# digital_PIN_interface.net
KiCad netlist of a schematic drawn in Altium Designer
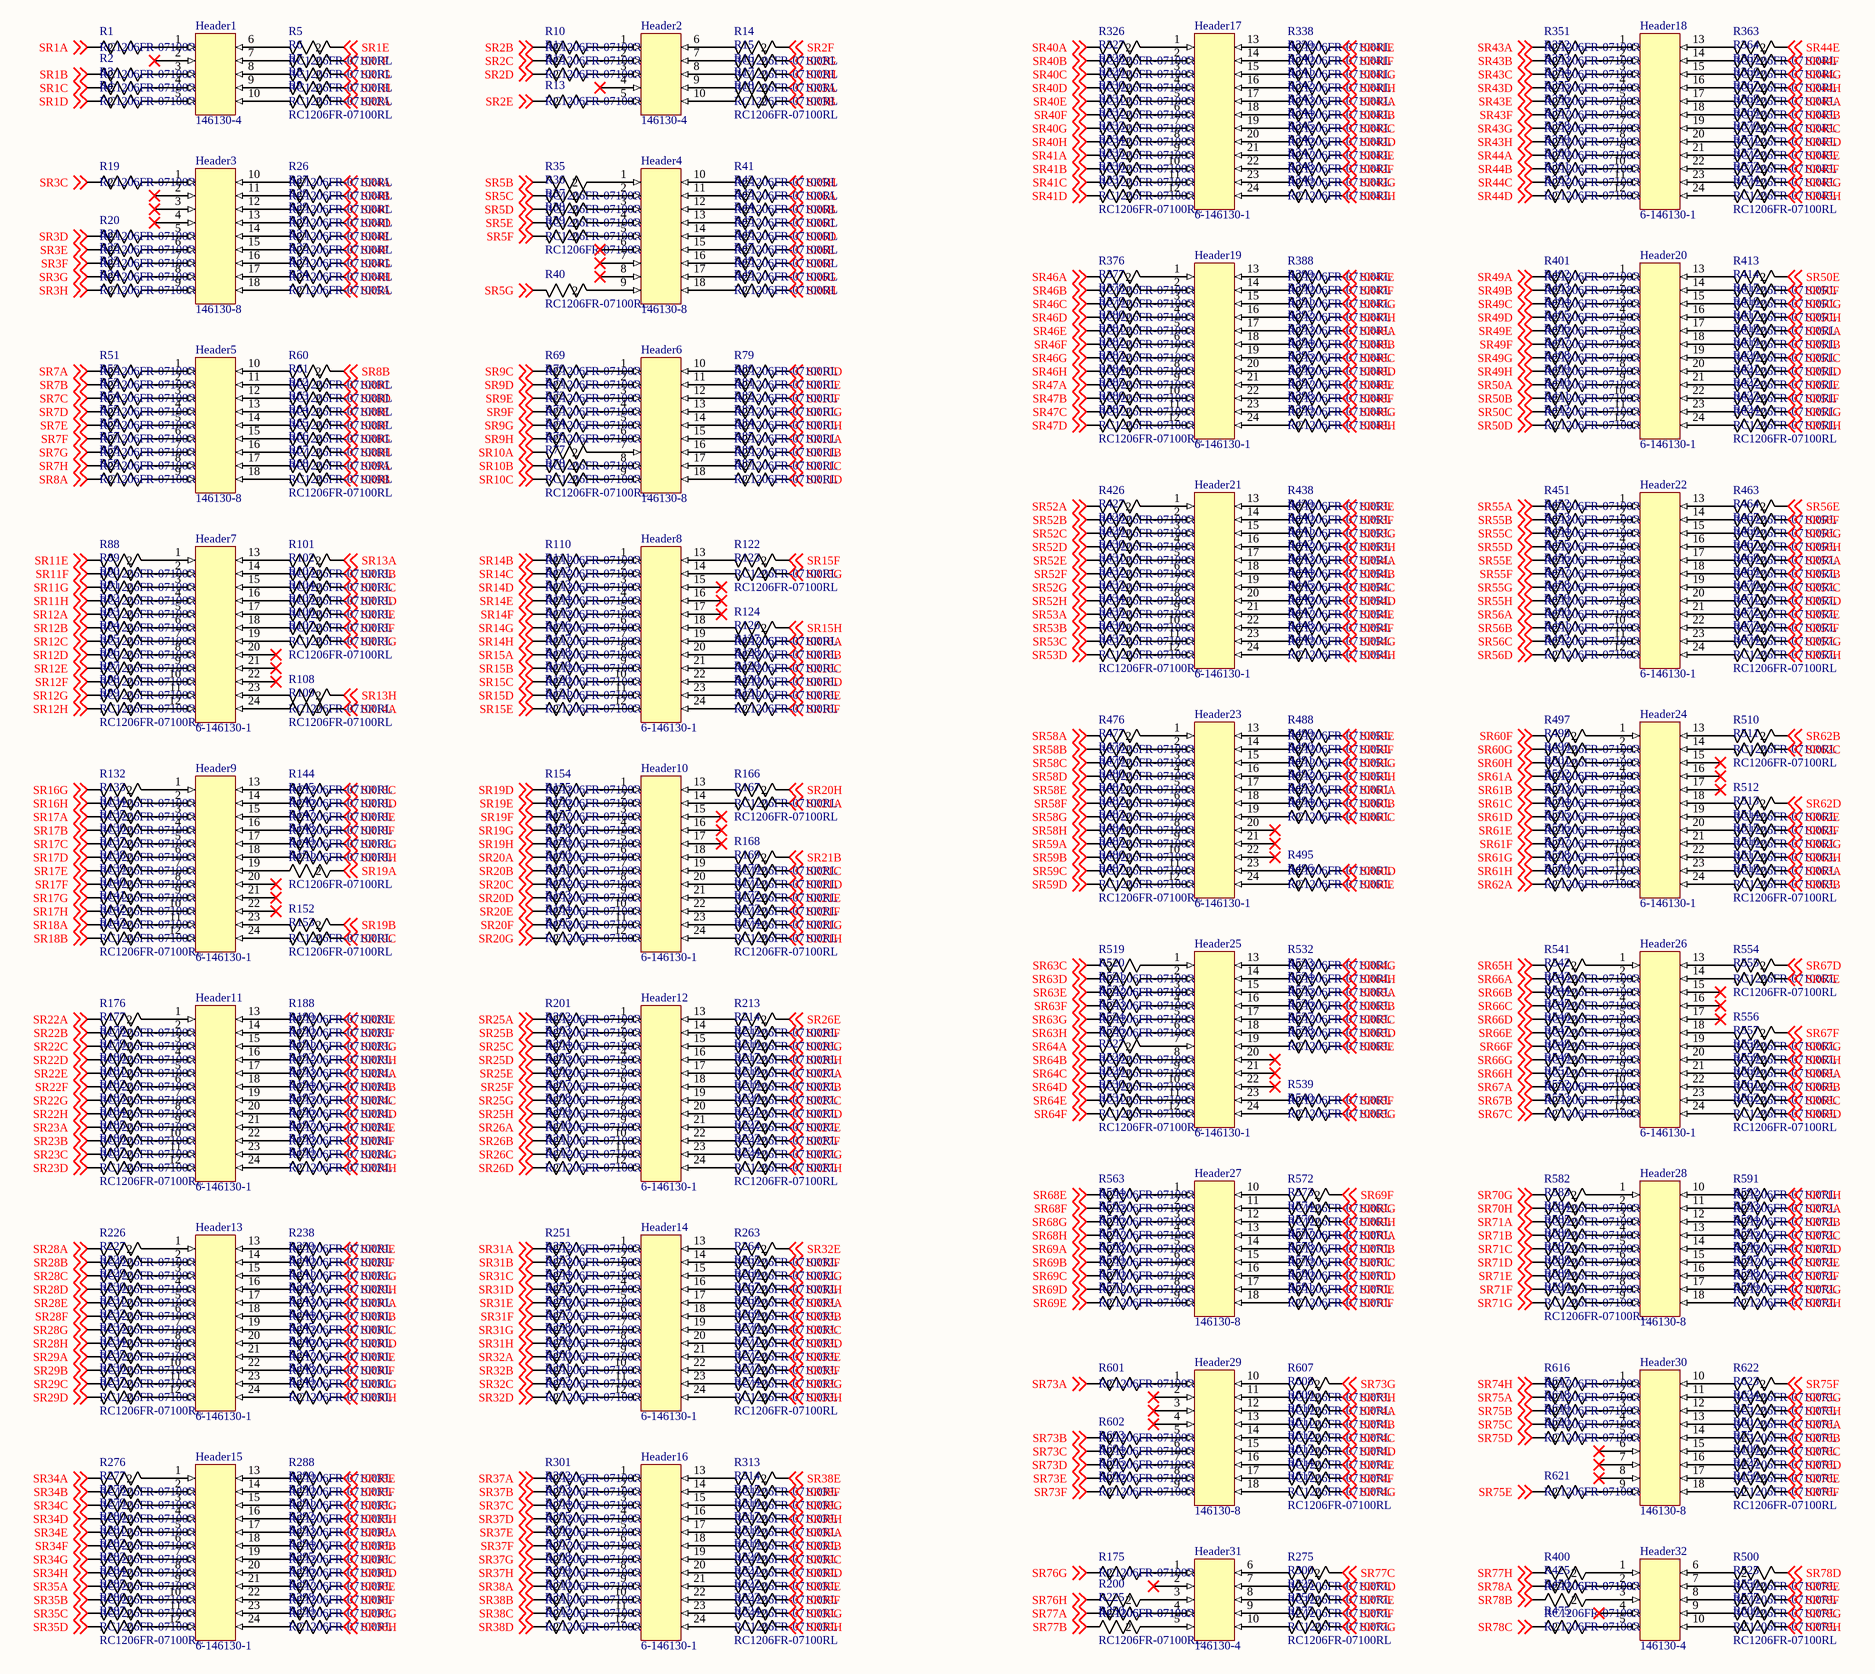
[diagram p0: digital_PIN_interface.SchDoc]

(export (version "E")
  (design (tool "Eeschema 10.0.6"))
  (components
    (comp (ref "Header1")
      (value "146130-4")
      (footprint "CONN_5-146130-7_TYCO - duplicate - duplicate - duplicate")
      (description "2*5 Header")
      (libsource (lib "5-146130-7") (part "146130-4"))
    )
    (comp (ref "Header2")
      (value "146130-4")
      (footprint "CONN_5-146130-7_TYCO - duplicate - duplicate - duplicate")
      (description "2*5 Header")
      (libsource (lib "5-146130-7") (part "146130-4"))
    )
    (comp (ref "Header3")
      (value "146130-8")
      (footprint "CONN_5-146130-7_TYCO - duplicate - duplicate")
      (description "2*9 Header")
      (libsource (lib "5-146130-7") (part "146130-8"))
    )
    (comp (ref "Header4")
      (value "146130-8")
      (footprint "CONN_5-146130-7_TYCO - duplicate - duplicate")
      (description "2*9 Header")
      (libsource (lib "5-146130-7") (part "146130-8"))
    )
    (comp (ref "Header5")
      (value "146130-8")
      (footprint "CONN_5-146130-7_TYCO - duplicate - duplicate")
      (description "2*9 Header")
      (libsource (lib "5-146130-7") (part "146130-8"))
    )
    (comp (ref "Header6")
      (value "146130-8")
      (footprint "CONN_5-146130-7_TYCO - duplicate - duplicate")
      (description "2*9 Header")
      (libsource (lib "5-146130-7") (part "146130-8"))
    )
    (comp (ref "Header7")
      (value "6-146130-1")
      (footprint "CONN_5-146130-7_TYCO - duplicate")
      (description "2*12 Header")
      (libsource (lib "5-146130-7") (part "6-146130-1"))
    )
    (comp (ref "Header8")
      (value "6-146130-1")
      (footprint "CONN_5-146130-7_TYCO - duplicate")
      (description "2*12 Header")
      (libsource (lib "5-146130-7") (part "6-146130-1"))
    )
    (comp (ref "Header9")
      (value "6-146130-1")
      (footprint "CONN_5-146130-7_TYCO - duplicate")
      (description "2*12 Header")
      (libsource (lib "5-146130-7") (part "6-146130-1"))
    )
    (comp (ref "Header10")
      (value "6-146130-1")
      (footprint "CONN_5-146130-7_TYCO - duplicate")
      (description "2*12 Header")
      (libsource (lib "5-146130-7") (part "6-146130-1"))
    )
    (comp (ref "Header11")
      (value "6-146130-1")
      (footprint "CONN_5-146130-7_TYCO - duplicate")
      (description "2*12 Header")
      (libsource (lib "5-146130-7") (part "6-146130-1"))
    )
    (comp (ref "Header12")
      (value "6-146130-1")
      (footprint "CONN_5-146130-7_TYCO - duplicate")
      (description "2*12 Header")
      (libsource (lib "5-146130-7") (part "6-146130-1"))
    )
    (comp (ref "Header13")
      (value "6-146130-1")
      (footprint "CONN_5-146130-7_TYCO - duplicate")
      (description "2*12 Header")
      (libsource (lib "5-146130-7") (part "6-146130-1"))
    )
    (comp (ref "Header14")
      (value "6-146130-1")
      (footprint "CONN_5-146130-7_TYCO - duplicate")
      (description "2*12 Header")
      (libsource (lib "5-146130-7") (part "6-146130-1"))
    )
    (comp (ref "Header15")
      (value "6-146130-1")
      (footprint "CONN_5-146130-7_TYCO - duplicate")
      (description "2*12 Header")
      (libsource (lib "5-146130-7") (part "6-146130-1"))
    )
    (comp (ref "Header16")
      (value "6-146130-1")
      (footprint "CONN_5-146130-7_TYCO - duplicate")
      (description "2*12 Header")
      (libsource (lib "5-146130-7") (part "6-146130-1"))
    )
    (comp (ref "Header17")
      (value "6-146130-1")
      (footprint "CONN_5-146130-7_TYCO - duplicate")
      (description "2*12 Header")
      (libsource (lib "5-146130-7") (part "6-146130-1"))
    )
    (comp (ref "Header18")
      (value "6-146130-1")
      (footprint "CONN_5-146130-7_TYCO - duplicate")
      (description "2*12 Header")
      (libsource (lib "5-146130-7") (part "6-146130-1"))
    )
    (comp (ref "Header19")
      (value "6-146130-1")
      (footprint "CONN_5-146130-7_TYCO - duplicate")
      (description "2*12 Header")
      (libsource (lib "5-146130-7") (part "6-146130-1"))
    )
    (comp (ref "Header20")
      (value "6-146130-1")
      (footprint "CONN_5-146130-7_TYCO - duplicate")
      (description "2*12 Header")
      (libsource (lib "5-146130-7") (part "6-146130-1"))
    )
    (comp (ref "Header21")
      (value "6-146130-1")
      (footprint "CONN_5-146130-7_TYCO - duplicate")
      (description "2*12 Header")
      (libsource (lib "5-146130-7") (part "6-146130-1"))
    )
    (comp (ref "Header22")
      (value "6-146130-1")
      (footprint "CONN_5-146130-7_TYCO - duplicate")
      (description "2*12 Header")
      (libsource (lib "5-146130-7") (part "6-146130-1"))
    )
    (comp (ref "Header23")
      (value "6-146130-1")
      (footprint "CONN_5-146130-7_TYCO - duplicate")
      (description "2*12 Header")
      (libsource (lib "5-146130-7") (part "6-146130-1"))
    )
    (comp (ref "Header24")
      (value "6-146130-1")
      (footprint "CONN_5-146130-7_TYCO - duplicate")
      (description "2*12 Header")
      (libsource (lib "5-146130-7") (part "6-146130-1"))
    )
    (comp (ref "Header25")
      (value "6-146130-1")
      (footprint "CONN_5-146130-7_TYCO - duplicate")
      (description "2*12 Header")
      (libsource (lib "5-146130-7") (part "6-146130-1"))
    )
    (comp (ref "Header26")
      (value "6-146130-1")
      (footprint "CONN_5-146130-7_TYCO - duplicate")
      (description "2*12 Header")
      (libsource (lib "5-146130-7") (part "6-146130-1"))
    )
    (comp (ref "Header27")
      (value "146130-8")
      (footprint "CONN_5-146130-7_TYCO - duplicate - duplicate")
      (description "2*9 Header")
      (libsource (lib "5-146130-7") (part "146130-8"))
    )
    (comp (ref "Header28")
      (value "146130-8")
      (footprint "CONN_5-146130-7_TYCO - duplicate - duplicate")
      (description "2*9 Header")
      (libsource (lib "5-146130-7") (part "146130-8"))
    )
    (comp (ref "Header29")
      (value "146130-8")
      (footprint "CONN_5-146130-7_TYCO - duplicate - duplicate")
      (description "2*9 Header")
      (libsource (lib "5-146130-7") (part "146130-8"))
    )
    (comp (ref "Header30")
      (value "146130-8")
      (footprint "CONN_5-146130-7_TYCO - duplicate - duplicate")
      (description "2*9 Header")
      (libsource (lib "5-146130-7") (part "146130-8"))
    )
    (comp (ref "Header31")
      (value "146130-4")
      (footprint "CONN_5-146130-7_TYCO - duplicate - duplicate - duplicate")
      (description "2*5 Header")
      (libsource (lib "5-146130-7") (part "146130-4"))
    )
    (comp (ref "Header32")
      (value "146130-4")
      (footprint "CONN_5-146130-7_TYCO - duplicate - duplicate - duplicate")
      (description "2*5 Header")
      (libsource (lib "5-146130-7") (part "146130-4"))
    )
    (comp (ref "R1")
      (value "RC1206FR-07100RL")
      (footprint "RC1206N_YAG")
      (description "No Description Available")
      (fields (field (name "COPYRIGHT") "Copyright (C) 2022 Ultra Librarian. All rights reserved."))
      (libsource (lib "RC1206FR-07100RL") (part "RC1206FR-07100RL"))
    )
    (comp (ref "R2")
      (value "RC1206FR-07100RL")
      (footprint "RC1206N_YAG")
      (description "No Description Available")
      (fields (field (name "COPYRIGHT") "Copyright (C) 2022 Ultra Librarian. All rights reserved."))
      (libsource (lib "RC1206FR-07100RL") (part "RC1206FR-07100RL"))
    )
    (comp (ref "R3")
      (value "RC1206FR-07100RL")
      (footprint "RC1206N_YAG")
      (description "No Description Available")
      (fields (field (name "COPYRIGHT") "Copyright (C) 2022 Ultra Librarian. All rights reserved."))
      (libsource (lib "RC1206FR-07100RL") (part "RC1206FR-07100RL"))
    )
    (comp (ref "R4")
      (value "RC1206FR-07100RL")
      (footprint "RC1206N_YAG")
      (description "No Description Available")
      (fields (field (name "COPYRIGHT") "Copyright (C) 2022 Ultra Librarian. All rights reserved."))
      (libsource (lib "RC1206FR-07100RL") (part "RC1206FR-07100RL"))
    )
    (comp (ref "R5")
      (value "RC1206FR-07100RL")
      (footprint "RC1206N_YAG")
      (description "No Description Available")
      (fields (field (name "COPYRIGHT") "Copyright (C) 2022 Ultra Librarian. All rights reserved."))
      (libsource (lib "RC1206FR-07100RL") (part "RC1206FR-07100RL"))
    )
    (comp (ref "R6")
      (value "RC1206FR-07100RL")
      (footprint "RC1206N_YAG")
      (description "No Description Available")
      (fields (field (name "COPYRIGHT") "Copyright (C) 2022 Ultra Librarian. All rights reserved."))
      (libsource (lib "RC1206FR-07100RL") (part "RC1206FR-07100RL"))
    )
    (comp (ref "R7")
      (value "RC1206FR-07100RL")
      (footprint "RC1206N_YAG")
      (description "No Description Available")
      (fields (field (name "COPYRIGHT") "Copyright (C) 2022 Ultra Librarian. All rights reserved."))
      (libsource (lib "RC1206FR-07100RL") (part "RC1206FR-07100RL"))
    )
    (comp (ref "R8")
      (value "RC1206FR-07100RL")
      (footprint "RC1206N_YAG")
      (description "No Description Available")
      (fields (field (name "COPYRIGHT") "Copyright (C) 2022 Ultra Librarian. All rights reserved."))
      (libsource (lib "RC1206FR-07100RL") (part "RC1206FR-07100RL"))
    )
    (comp (ref "R9")
      (value "RC1206FR-07100RL")
      (footprint "RC1206N_YAG")
      (description "No Description Available")
      (fields (field (name "COPYRIGHT") "Copyright (C) 2022 Ultra Librarian. All rights reserved."))
      (libsource (lib "RC1206FR-07100RL") (part "RC1206FR-07100RL"))
    )
    (comp (ref "R10")
      (value "RC1206FR-07100RL")
      (footprint "RC1206N_YAG")
      (description "No Description Available")
      (fields (field (name "COPYRIGHT") "Copyright (C) 2022 Ultra Librarian. All rights reserved."))
      (libsource (lib "RC1206FR-07100RL") (part "RC1206FR-07100RL"))
    )
    (comp (ref "R11")
      (value "RC1206FR-07100RL")
      (footprint "RC1206N_YAG")
      (description "No Description Available")
      (fields (field (name "COPYRIGHT") "Copyright (C) 2022 Ultra Librarian. All rights reserved."))
      (libsource (lib "RC1206FR-07100RL") (part "RC1206FR-07100RL"))
    )
    (comp (ref "R12")
      (value "RC1206FR-07100RL")
      (footprint "RC1206N_YAG")
      (description "No Description Available")
      (fields (field (name "COPYRIGHT") "Copyright (C) 2022 Ultra Librarian. All rights reserved."))
      (libsource (lib "RC1206FR-07100RL") (part "RC1206FR-07100RL"))
    )
    (comp (ref "R13")
      (value "RC1206FR-07100RL")
      (footprint "RC1206N_YAG")
      (description "No Description Available")
      (fields (field (name "COPYRIGHT") "Copyright (C) 2022 Ultra Librarian. All rights reserved."))
      (libsource (lib "RC1206FR-07100RL") (part "RC1206FR-07100RL"))
    )
    (comp (ref "R14")
      (value "RC1206FR-07100RL")
      (footprint "RC1206N_YAG")
      (description "No Description Available")
      (fields (field (name "COPYRIGHT") "Copyright (C) 2022 Ultra Librarian. All rights reserved."))
      (libsource (lib "RC1206FR-07100RL") (part "RC1206FR-07100RL"))
    )
    (comp (ref "R15")
      (value "RC1206FR-07100RL")
      (footprint "RC1206N_YAG")
      (description "No Description Available")
      (fields (field (name "COPYRIGHT") "Copyright (C) 2022 Ultra Librarian. All rights reserved."))
      (libsource (lib "RC1206FR-07100RL") (part "RC1206FR-07100RL"))
    )
    (comp (ref "R16")
      (value "RC1206FR-07100RL")
      (footprint "RC1206N_YAG")
      (description "No Description Available")
      (fields (field (name "COPYRIGHT") "Copyright (C) 2022 Ultra Librarian. All rights reserved."))
      (libsource (lib "RC1206FR-07100RL") (part "RC1206FR-07100RL"))
    )
    (comp (ref "R17")
      (value "RC1206FR-07100RL")
      (footprint "RC1206N_YAG")
      (description "No Description Available")
      (fields (field (name "COPYRIGHT") "Copyright (C) 2022 Ultra Librarian. All rights reserved."))
      (libsource (lib "RC1206FR-07100RL") (part "RC1206FR-07100RL"))
    )
    (comp (ref "R18")
      (value "RC1206FR-07100RL")
      (footprint "RC1206N_YAG")
      (description "No Description Available")
      (fields (field (name "COPYRIGHT") "Copyright (C) 2022 Ultra Librarian. All rights reserved."))
      (libsource (lib "RC1206FR-07100RL") (part "RC1206FR-07100RL"))
    )
    (comp (ref "R19")
      (value "RC1206FR-07100RL")
      (footprint "RC1206N_YAG")
      (description "No Description Available")
      (fields (field (name "COPYRIGHT") "Copyright (C) 2022 Ultra Librarian. All rights reserved."))
      (libsource (lib "RC1206FR-07100RL") (part "RC1206FR-07100RL"))
    )
    (comp (ref "R20")
      (value "RC1206FR-07100RL")
      (footprint "RC1206N_YAG")
      (description "No Description Available")
      (fields (field (name "COPYRIGHT") "Copyright (C) 2022 Ultra Librarian. All rights reserved."))
      (libsource (lib "RC1206FR-07100RL") (part "RC1206FR-07100RL"))
    )
    (comp (ref "R21")
      (value "RC1206FR-07100RL")
      (footprint "RC1206N_YAG")
      (description "No Description Available")
      (fields (field (name "COPYRIGHT") "Copyright (C) 2022 Ultra Librarian. All rights reserved."))
      (libsource (lib "RC1206FR-07100RL") (part "RC1206FR-07100RL"))
    )
    (comp (ref "R22")
      (value "RC1206FR-07100RL")
      (footprint "RC1206N_YAG")
      (description "No Description Available")
      (fields (field (name "COPYRIGHT") "Copyright (C) 2022 Ultra Librarian. All rights reserved."))
      (libsource (lib "RC1206FR-07100RL") (part "RC1206FR-07100RL"))
    )
    (comp (ref "R23")
      (value "RC1206FR-07100RL")
      (footprint "RC1206N_YAG")
      (description "No Description Available")
      (fields (field (name "COPYRIGHT") "Copyright (C) 2022 Ultra Librarian. All rights reserved."))
      (libsource (lib "RC1206FR-07100RL") (part "RC1206FR-07100RL"))
    )
    (comp (ref "R24")
      (value "RC1206FR-07100RL")
      (footprint "RC1206N_YAG")
      (description "No Description Available")
      (fields (field (name "COPYRIGHT") "Copyright (C) 2022 Ultra Librarian. All rights reserved."))
      (libsource (lib "RC1206FR-07100RL") (part "RC1206FR-07100RL"))
    )
    (comp (ref "R25")
      (value "RC1206FR-07100RL")
      (footprint "RC1206N_YAG")
      (description "No Description Available")
      (fields (field (name "COPYRIGHT") "Copyright (C) 2022 Ultra Librarian. All rights reserved."))
      (libsource (lib "RC1206FR-07100RL") (part "RC1206FR-07100RL"))
    )
    (comp (ref "R26")
      (value "RC1206FR-07100RL")
      (footprint "RC1206N_YAG")
      (description "No Description Available")
      (fields (field (name "COPYRIGHT") "Copyright (C) 2022 Ultra Librarian. All rights reserved."))
      (libsource (lib "RC1206FR-07100RL") (part "RC1206FR-07100RL"))
    )
    (comp (ref "R27")
      (value "RC1206FR-07100RL")
      (footprint "RC1206N_YAG")
      (description "No Description Available")
      (fields (field (name "COPYRIGHT") "Copyright (C) 2022 Ultra Librarian. All rights reserved."))
      (libsource (lib "RC1206FR-07100RL") (part "RC1206FR-07100RL"))
    )
    (comp (ref "R28")
      (value "RC1206FR-07100RL")
      (footprint "RC1206N_YAG")
      (description "No Description Available")
      (fields (field (name "COPYRIGHT") "Copyright (C) 2022 Ultra Librarian. All rights reserved."))
      (libsource (lib "RC1206FR-07100RL") (part "RC1206FR-07100RL"))
    )
    (comp (ref "R29")
      (value "RC1206FR-07100RL")
      (footprint "RC1206N_YAG")
      (description "No Description Available")
      (fields (field (name "COPYRIGHT") "Copyright (C) 2022 Ultra Librarian. All rights reserved."))
      (libsource (lib "RC1206FR-07100RL") (part "RC1206FR-07100RL"))
    )
    (comp (ref "R30")
      (value "RC1206FR-07100RL")
      (footprint "RC1206N_YAG")
      (description "No Description Available")
      (fields (field (name "COPYRIGHT") "Copyright (C) 2022 Ultra Librarian. All rights reserved."))
      (libsource (lib "RC1206FR-07100RL") (part "RC1206FR-07100RL"))
    )
    (comp (ref "R31")
      (value "RC1206FR-07100RL")
      (footprint "RC1206N_YAG")
      (description "No Description Available")
      (fields (field (name "COPYRIGHT") "Copyright (C) 2022 Ultra Librarian. All rights reserved."))
      (libsource (lib "RC1206FR-07100RL") (part "RC1206FR-07100RL"))
    )
    (comp (ref "R32")
      (value "RC1206FR-07100RL")
      (footprint "RC1206N_YAG")
      (description "No Description Available")
      (fields (field (name "COPYRIGHT") "Copyright (C) 2022 Ultra Librarian. All rights reserved."))
      (libsource (lib "RC1206FR-07100RL") (part "RC1206FR-07100RL"))
    )
    (comp (ref "R33")
      (value "RC1206FR-07100RL")
      (footprint "RC1206N_YAG")
      (description "No Description Available")
      (fields (field (name "COPYRIGHT") "Copyright (C) 2022 Ultra Librarian. All rights reserved."))
      (libsource (lib "RC1206FR-07100RL") (part "RC1206FR-07100RL"))
    )
    (comp (ref "R34")
      (value "RC1206FR-07100RL")
      (footprint "RC1206N_YAG")
      (description "No Description Available")
      (fields (field (name "COPYRIGHT") "Copyright (C) 2022 Ultra Librarian. All rights reserved."))
      (libsource (lib "RC1206FR-07100RL") (part "RC1206FR-07100RL"))
    )
    (comp (ref "R35")
      (value "RC1206FR-07100RL")
      (footprint "RC1206N_YAG")
      (description "No Description Available")
      (fields (field (name "COPYRIGHT") "Copyright (C) 2022 Ultra Librarian. All rights reserved."))
      (libsource (lib "RC1206FR-07100RL") (part "RC1206FR-07100RL"))
    )
    (comp (ref "R36")
      (value "RC1206FR-07100RL")
      (footprint "RC1206N_YAG")
      (description "No Description Available")
      (fields (field (name "COPYRIGHT") "Copyright (C) 2022 Ultra Librarian. All rights reserved."))
      (libsource (lib "RC1206FR-07100RL") (part "RC1206FR-07100RL"))
    )
    (comp (ref "R37")
      (value "RC1206FR-07100RL")
      (footprint "RC1206N_YAG")
      (description "No Description Available")
      (fields (field (name "COPYRIGHT") "Copyright (C) 2022 Ultra Librarian. All rights reserved."))
      (libsource (lib "RC1206FR-07100RL") (part "RC1206FR-07100RL"))
    )
    (comp (ref "R38")
      (value "RC1206FR-07100RL")
      (footprint "RC1206N_YAG")
      (description "No Description Available")
      (fields (field (name "COPYRIGHT") "Copyright (C) 2022 Ultra Librarian. All rights reserved."))
      (libsource (lib "RC1206FR-07100RL") (part "RC1206FR-07100RL"))
    )
    (comp (ref "R39")
      (value "RC1206FR-07100RL")
      (footprint "RC1206N_YAG")
      (description "No Description Available")
      (fields (field (name "COPYRIGHT") "Copyright (C) 2022 Ultra Librarian. All rights reserved."))
      (libsource (lib "RC1206FR-07100RL") (part "RC1206FR-07100RL"))
    )
    (comp (ref "R40")
      (value "RC1206FR-07100RL")
      (footprint "RC1206N_YAG")
      (description "No Description Available")
      (fields (field (name "COPYRIGHT") "Copyright (C) 2022 Ultra Librarian. All rights reserved."))
      (libsource (lib "RC1206FR-07100RL") (part "RC1206FR-07100RL"))
    )
    (comp (ref "R41")
      (value "RC1206FR-07100RL")
      (footprint "RC1206N_YAG")
      (description "No Description Available")
      (fields (field (name "COPYRIGHT") "Copyright (C) 2022 Ultra Librarian. All rights reserved."))
      (libsource (lib "RC1206FR-07100RL") (part "RC1206FR-07100RL"))
    )
    (comp (ref "R42")
      (value "RC1206FR-07100RL")
      (footprint "RC1206N_YAG")
      (description "No Description Available")
      (fields (field (name "COPYRIGHT") "Copyright (C) 2022 Ultra Librarian. All rights reserved."))
      (libsource (lib "RC1206FR-07100RL") (part "RC1206FR-07100RL"))
    )
    (comp (ref "R43")
      (value "RC1206FR-07100RL")
      (footprint "RC1206N_YAG")
      (description "No Description Available")
      (fields (field (name "COPYRIGHT") "Copyright (C) 2022 Ultra Librarian. All rights reserved."))
      (libsource (lib "RC1206FR-07100RL") (part "RC1206FR-07100RL"))
    )
    (comp (ref "R44")
      (value "RC1206FR-07100RL")
      (footprint "RC1206N_YAG")
      (description "No Description Available")
      (fields (field (name "COPYRIGHT") "Copyright (C) 2022 Ultra Librarian. All rights reserved."))
      (libsource (lib "RC1206FR-07100RL") (part "RC1206FR-07100RL"))
    )
    (comp (ref "R45")
      (value "RC1206FR-07100RL")
      (footprint "RC1206N_YAG")
      (description "No Description Available")
      (fields (field (name "COPYRIGHT") "Copyright (C) 2022 Ultra Librarian. All rights reserved."))
      (libsource (lib "RC1206FR-07100RL") (part "RC1206FR-07100RL"))
    )
    (comp (ref "R46")
      (value "RC1206FR-07100RL")
      (footprint "RC1206N_YAG")
      (description "No Description Available")
      (fields (field (name "COPYRIGHT") "Copyright (C) 2022 Ultra Librarian. All rights reserved."))
      (libsource (lib "RC1206FR-07100RL") (part "RC1206FR-07100RL"))
    )
    (comp (ref "R47")
      (value "RC1206FR-07100RL")
      (footprint "RC1206N_YAG")
      (description "No Description Available")
      (fields (field (name "COPYRIGHT") "Copyright (C) 2022 Ultra Librarian. All rights reserved."))
      (libsource (lib "RC1206FR-07100RL") (part "RC1206FR-07100RL"))
    )
    (comp (ref "R48")
      (value "RC1206FR-07100RL")
      (footprint "RC1206N_YAG")
      (description "No Description Available")
      (fields (field (name "COPYRIGHT") "Copyright (C) 2022 Ultra Librarian. All rights reserved."))
      (libsource (lib "RC1206FR-07100RL") (part "RC1206FR-07100RL"))
    )
    (comp (ref "R49")
      (value "RC1206FR-07100RL")
      (footprint "RC1206N_YAG")
      (description "No Description Available")
      (fields (field (name "COPYRIGHT") "Copyright (C) 2022 Ultra Librarian. All rights reserved."))
      (libsource (lib "RC1206FR-07100RL") (part "RC1206FR-07100RL"))
    )
    (comp (ref "R50")
      (value "RC1206FR-07100RL")
      (footprint "RC1206N_YAG")
      (description "No Description Available")
      (fields (field (name "COPYRIGHT") "Copyright (C) 2022 Ultra Librarian. All rights reserved."))
      (libsource (lib "RC1206FR-07100RL") (part "RC1206FR-07100RL"))
    )
    (comp (ref "R51")
      (value "RC1206FR-07100RL")
      (footprint "RC1206N_YAG")
      (description "No Description Available")
      (fields (field (name "COPYRIGHT") "Copyright (C) 2022 Ultra Librarian. All rights reserved."))
      (libsource (lib "RC1206FR-07100RL") (part "RC1206FR-07100RL"))
    )
    (comp (ref "R52")
      (value "RC1206FR-07100RL")
      (footprint "RC1206N_YAG")
      (description "No Description Available")
      (fields (field (name "COPYRIGHT") "Copyright (C) 2022 Ultra Librarian. All rights reserved."))
      (libsource (lib "RC1206FR-07100RL") (part "RC1206FR-07100RL"))
    )
    (comp (ref "R53")
      (value "RC1206FR-07100RL")
      (footprint "RC1206N_YAG")
      (description "No Description Available")
      (fields (field (name "COPYRIGHT") "Copyright (C) 2022 Ultra Librarian. All rights reserved."))
      (libsource (lib "RC1206FR-07100RL") (part "RC1206FR-07100RL"))
    )
    (comp (ref "R54")
      (value "RC1206FR-07100RL")
      (footprint "RC1206N_YAG")
      (description "No Description Available")
      (fields (field (name "COPYRIGHT") "Copyright (C) 2022 Ultra Librarian. All rights reserved."))
      (libsource (lib "RC1206FR-07100RL") (part "RC1206FR-07100RL"))
    )
    (comp (ref "R55")
      (value "RC1206FR-07100RL")
      (footprint "RC1206N_YAG")
      (description "No Description Available")
      (fields (field (name "COPYRIGHT") "Copyright (C) 2022 Ultra Librarian. All rights reserved."))
      (libsource (lib "RC1206FR-07100RL") (part "RC1206FR-07100RL"))
    )
    (comp (ref "R56")
      (value "RC1206FR-07100RL")
      (footprint "RC1206N_YAG")
      (description "No Description Available")
      (fields (field (name "COPYRIGHT") "Copyright (C) 2022 Ultra Librarian. All rights reserved."))
      (libsource (lib "RC1206FR-07100RL") (part "RC1206FR-07100RL"))
    )
    (comp (ref "R57")
      (value "RC1206FR-07100RL")
      (footprint "RC1206N_YAG")
      (description "No Description Available")
      (fields (field (name "COPYRIGHT") "Copyright (C) 2022 Ultra Librarian. All rights reserved."))
      (libsource (lib "RC1206FR-07100RL") (part "RC1206FR-07100RL"))
    )
    (comp (ref "R58")
      (value "RC1206FR-07100RL")
      (footprint "RC1206N_YAG")
      (description "No Description Available")
      (fields (field (name "COPYRIGHT") "Copyright (C) 2022 Ultra Librarian. All rights reserved."))
      (libsource (lib "RC1206FR-07100RL") (part "RC1206FR-07100RL"))
    )
    (comp (ref "R59")
      (value "RC1206FR-07100RL")
      (footprint "RC1206N_YAG")
      (description "No Description Available")
      (fields (field (name "COPYRIGHT") "Copyright (C) 2022 Ultra Librarian. All rights reserved."))
      (libsource (lib "RC1206FR-07100RL") (part "RC1206FR-07100RL"))
    )
    (comp (ref "R60")
      (value "RC1206FR-07100RL")
      (footprint "RC1206N_YAG")
      (description "No Description Available")
      (fields (field (name "COPYRIGHT") "Copyright (C) 2022 Ultra Librarian. All rights reserved."))
      (libsource (lib "RC1206FR-07100RL") (part "RC1206FR-07100RL"))
    )
    (comp (ref "R61")
      (value "RC1206FR-07100RL")
      (footprint "RC1206N_YAG")
      (description "No Description Available")
      (fields (field (name "COPYRIGHT") "Copyright (C) 2022 Ultra Librarian. All rights reserved."))
      (libsource (lib "RC1206FR-07100RL") (part "RC1206FR-07100RL"))
    )
    (comp (ref "R62")
      (value "RC1206FR-07100RL")
      (footprint "RC1206N_YAG")
      (description "No Description Available")
      (fields (field (name "COPYRIGHT") "Copyright (C) 2022 Ultra Librarian. All rights reserved."))
      (libsource (lib "RC1206FR-07100RL") (part "RC1206FR-07100RL"))
    )
    (comp (ref "R63")
      (value "RC1206FR-07100RL")
      (footprint "RC1206N_YAG")
      (description "No Description Available")
      (fields (field (name "COPYRIGHT") "Copyright (C) 2022 Ultra Librarian. All rights reserved."))
      (libsource (lib "RC1206FR-07100RL") (part "RC1206FR-07100RL"))
    )
    (comp (ref "R64")
      (value "RC1206FR-07100RL")
      (footprint "RC1206N_YAG")
      (description "No Description Available")
      (fields (field (name "COPYRIGHT") "Copyright (C) 2022 Ultra Librarian. All rights reserved."))
      (libsource (lib "RC1206FR-07100RL") (part "RC1206FR-07100RL"))
    )
    (comp (ref "R65")
      (value "RC1206FR-07100RL")
      (footprint "RC1206N_YAG")
      (description "No Description Available")
      (fields (field (name "COPYRIGHT") "Copyright (C) 2022 Ultra Librarian. All rights reserved."))
      (libsource (lib "RC1206FR-07100RL") (part "RC1206FR-07100RL"))
    )
    (comp (ref "R66")
      (value "RC1206FR-07100RL")
      (footprint "RC1206N_YAG")
      (description "No Description Available")
      (fields (field (name "COPYRIGHT") "Copyright (C) 2022 Ultra Librarian. All rights reserved."))
      (libsource (lib "RC1206FR-07100RL") (part "RC1206FR-07100RL"))
    )
    (comp (ref "R67")
      (value "RC1206FR-07100RL")
      (footprint "RC1206N_YAG")
      (description "No Description Available")
      (fields (field (name "COPYRIGHT") "Copyright (C) 2022 Ultra Librarian. All rights reserved."))
      (libsource (lib "RC1206FR-07100RL") (part "RC1206FR-07100RL"))
    )
    (comp (ref "R68")
      (value "RC1206FR-07100RL")
      (footprint "RC1206N_YAG")
      (description "No Description Available")
      (fields (field (name "COPYRIGHT") "Copyright (C) 2022 Ultra Librarian. All rights reserved."))
      (libsource (lib "RC1206FR-07100RL") (part "RC1206FR-07100RL"))
    )
    (comp (ref "R69")
      (value "RC1206FR-07100RL")
      (footprint "RC1206N_YAG")
      (description "No Description Available")
      (fields (field (name "COPYRIGHT") "Copyright (C) 2022 Ultra Librarian. All rights reserved."))
      (libsource (lib "RC1206FR-07100RL") (part "RC1206FR-07100RL"))
    )
    (comp (ref "R70")
      (value "RC1206FR-07100RL")
      (footprint "RC1206N_YAG")
      (description "No Description Available")
      (fields (field (name "COPYRIGHT") "Copyright (C) 2022 Ultra Librarian. All rights reserved."))
      (libsource (lib "RC1206FR-07100RL") (part "RC1206FR-07100RL"))
    )
    (comp (ref "R71")
      (value "RC1206FR-07100RL")
      (footprint "RC1206N_YAG")
      (description "No Description Available")
      (fields (field (name "COPYRIGHT") "Copyright (C) 2022 Ultra Librarian. All rights reserved."))
      (libsource (lib "RC1206FR-07100RL") (part "RC1206FR-07100RL"))
    )
    (comp (ref "R72")
      (value "RC1206FR-07100RL")
      (footprint "RC1206N_YAG")
      (description "No Description Available")
      (fields (field (name "COPYRIGHT") "Copyright (C) 2022 Ultra Librarian. All rights reserved."))
      (libsource (lib "RC1206FR-07100RL") (part "RC1206FR-07100RL"))
    )
    (comp (ref "R73")
      (value "RC1206FR-07100RL")
      (footprint "RC1206N_YAG")
      (description "No Description Available")
      (fields (field (name "COPYRIGHT") "Copyright (C) 2022 Ultra Librarian. All rights reserved."))
      (libsource (lib "RC1206FR-07100RL") (part "RC1206FR-07100RL"))
    )
    (comp (ref "R74")
      (value "RC1206FR-07100RL")
      (footprint "RC1206N_YAG")
      (description "No Description Available")
      (fields (field (name "COPYRIGHT") "Copyright (C) 2022 Ultra Librarian. All rights reserved."))
      (libsource (lib "RC1206FR-07100RL") (part "RC1206FR-07100RL"))
    )
    (comp (ref "R75")
      (value "RC1206FR-07100RL")
      (footprint "RC1206N_YAG")
      (description "No Description Available")
      (fields (field (name "COPYRIGHT") "Copyright (C) 2022 Ultra Librarian. All rights reserved."))
      (libsource (lib "RC1206FR-07100RL") (part "RC1206FR-07100RL"))
    )
    (comp (ref "R76")
      (value "RC1206FR-07100RL")
      (footprint "RC1206N_YAG")
      (description "No Description Available")
      (fields (field (name "COPYRIGHT") "Copyright (C) 2022 Ultra Librarian. All rights reserved."))
      (libsource (lib "RC1206FR-07100RL") (part "RC1206FR-07100RL"))
    )
    (comp (ref "R77")
      (value "RC1206FR-07100RL")
      (footprint "RC1206N_YAG")
      (description "No Description Available")
      (fields (field (name "COPYRIGHT") "Copyright (C) 2022 Ultra Librarian. All rights reserved."))
      (libsource (lib "RC1206FR-07100RL") (part "RC1206FR-07100RL"))
    )
    (comp (ref "R78")
      (value "RC1206FR-07100RL")
      (footprint "RC1206N_YAG")
      (description "No Description Available")
      (fields (field (name "COPYRIGHT") "Copyright (C) 2022 Ultra Librarian. All rights reserved."))
      (libsource (lib "RC1206FR-07100RL") (part "RC1206FR-07100RL"))
    )
    (comp (ref "R79")
      (value "RC1206FR-07100RL")
      (footprint "RC1206N_YAG")
      (description "No Description Available")
      (fields (field (name "COPYRIGHT") "Copyright (C) 2022 Ultra Librarian. All rights reserved."))
      (libsource (lib "RC1206FR-07100RL") (part "RC1206FR-07100RL"))
    )
    (comp (ref "R80")
      (value "RC1206FR-07100RL")
      (footprint "RC1206N_YAG")
      (description "No Description Available")
      (fields (field (name "COPYRIGHT") "Copyright (C) 2022 Ultra Librarian. All rights reserved."))
      (libsource (lib "RC1206FR-07100RL") (part "RC1206FR-07100RL"))
    )
    (comp (ref "R81")
      (value "RC1206FR-07100RL")
      (footprint "RC1206N_YAG")
      (description "No Description Available")
      (fields (field (name "COPYRIGHT") "Copyright (C) 2022 Ultra Librarian. All rights reserved."))
      (libsource (lib "RC1206FR-07100RL") (part "RC1206FR-07100RL"))
    )
    (comp (ref "R82")
      (value "RC1206FR-07100RL")
      (footprint "RC1206N_YAG")
      (description "No Description Available")
      (fields (field (name "COPYRIGHT") "Copyright (C) 2022 Ultra Librarian. All rights reserved."))
      (libsource (lib "RC1206FR-07100RL") (part "RC1206FR-07100RL"))
    )
    (comp (ref "R83")
      (value "RC1206FR-07100RL")
      (footprint "RC1206N_YAG")
      (description "No Description Available")
      (fields (field (name "COPYRIGHT") "Copyright (C) 2022 Ultra Librarian. All rights reserved."))
      (libsource (lib "RC1206FR-07100RL") (part "RC1206FR-07100RL"))
    )
    (comp (ref "R84")
      (value "RC1206FR-07100RL")
      (footprint "RC1206N_YAG")
      (description "No Description Available")
      (fields (field (name "COPYRIGHT") "Copyright (C) 2022 Ultra Librarian. All rights reserved."))
      (libsource (lib "RC1206FR-07100RL") (part "RC1206FR-07100RL"))
    )
    (comp (ref "R85")
      (value "RC1206FR-07100RL")
      (footprint "RC1206N_YAG")
      (description "No Description Available")
      (fields (field (name "COPYRIGHT") "Copyright (C) 2022 Ultra Librarian. All rights reserved."))
      (libsource (lib "RC1206FR-07100RL") (part "RC1206FR-07100RL"))
    )
    (comp (ref "R86")
      (value "RC1206FR-07100RL")
      (footprint "RC1206N_YAG")
      (description "No Description Available")
      (fields (field (name "COPYRIGHT") "Copyright (C) 2022 Ultra Librarian. All rights reserved."))
      (libsource (lib "RC1206FR-07100RL") (part "RC1206FR-07100RL"))
    )
    (comp (ref "R87")
      (value "RC1206FR-07100RL")
      (footprint "RC1206N_YAG")
      (description "No Description Available")
      (fields (field (name "COPYRIGHT") "Copyright (C) 2022 Ultra Librarian. All rights reserved."))
      (libsource (lib "RC1206FR-07100RL") (part "RC1206FR-07100RL"))
    )
    (comp (ref "R88")
      (value "RC1206FR-07100RL")
      (footprint "RC1206N_YAG")
      (description "No Description Available")
      (fields (field (name "COPYRIGHT") "Copyright (C) 2022 Ultra Librarian. All rights reserved."))
      (libsource (lib "RC1206FR-07100RL") (part "RC1206FR-07100RL"))
    )
    (comp (ref "R89")
      (value "RC1206FR-07100RL")
      (footprint "RC1206N_YAG")
      (description "No Description Available")
      (fields (field (name "COPYRIGHT") "Copyright (C) 2022 Ultra Librarian. All rights reserved."))
      (libsource (lib "RC1206FR-07100RL") (part "RC1206FR-07100RL"))
    )
    (comp (ref "R90")
      (value "RC1206FR-07100RL")
      (footprint "RC1206N_YAG")
      (description "No Description Available")
      (fields (field (name "COPYRIGHT") "Copyright (C) 2022 Ultra Librarian. All rights reserved."))
      (libsource (lib "RC1206FR-07100RL") (part "RC1206FR-07100RL"))
    )
    (comp (ref "R91")
      (value "RC1206FR-07100RL")
      (footprint "RC1206N_YAG")
      (description "No Description Available")
      (fields (field (name "COPYRIGHT") "Copyright (C) 2022 Ultra Librarian. All rights reserved."))
      (libsource (lib "RC1206FR-07100RL") (part "RC1206FR-07100RL"))
    )
    (comp (ref "R92")
      (value "RC1206FR-07100RL")
      (footprint "RC1206N_YAG")
      (description "No Description Available")
      (fields (field (name "COPYRIGHT") "Copyright (C) 2022 Ultra Librarian. All rights reserved."))
      (libsource (lib "RC1206FR-07100RL") (part "RC1206FR-07100RL"))
    )
    (comp (ref "R93")
      (value "RC1206FR-07100RL")
      (footprint "RC1206N_YAG")
      (description "No Description Available")
      (fields (field (name "COPYRIGHT") "Copyright (C) 2022 Ultra Librarian. All rights reserved."))
      (libsource (lib "RC1206FR-07100RL") (part "RC1206FR-07100RL"))
    )
    (comp (ref "R94")
      (value "RC1206FR-07100RL")
      (footprint "RC1206N_YAG")
      (description "No Description Available")
      (fields (field (name "COPYRIGHT") "Copyright (C) 2022 Ultra Librarian. All rights reserved."))
      (libsource (lib "RC1206FR-07100RL") (part "RC1206FR-07100RL"))
    )
    (comp (ref "R95")
      (value "RC1206FR-07100RL")
      (footprint "RC1206N_YAG")
      (description "No Description Available")
      (fields (field (name "COPYRIGHT") "Copyright (C) 2022 Ultra Librarian. All rights reserved."))
      (libsource (lib "RC1206FR-07100RL") (part "RC1206FR-07100RL"))
    )
    (comp (ref "R96")
      (value "RC1206FR-07100RL")
      (footprint "RC1206N_YAG")
      (description "No Description Available")
      (fields (field (name "COPYRIGHT") "Copyright (C) 2022 Ultra Librarian. All rights reserved."))
      (libsource (lib "RC1206FR-07100RL") (part "RC1206FR-07100RL"))
    )
    (comp (ref "R97")
      (value "RC1206FR-07100RL")
      (footprint "RC1206N_YAG")
      (description "No Description Available")
      (fields (field (name "COPYRIGHT") "Copyright (C) 2022 Ultra Librarian. All rights reserved."))
      (libsource (lib "RC1206FR-07100RL") (part "RC1206FR-07100RL"))
    )
    (comp (ref "R98")
      (value "RC1206FR-07100RL")
      (footprint "RC1206N_YAG")
      (description "No Description Available")
      (fields (field (name "COPYRIGHT") "Copyright (C) 2022 Ultra Librarian. All rights reserved."))
      (libsource (lib "RC1206FR-07100RL") (part "RC1206FR-07100RL"))
    )
    (comp (ref "R99")
      (value "RC1206FR-07100RL")
      (footprint "RC1206N_YAG")
      (description "No Description Available")
      (fields (field (name "COPYRIGHT") "Copyright (C) 2022 Ultra Librarian. All rights reserved."))
      (libsource (lib "RC1206FR-07100RL") (part "RC1206FR-07100RL"))
    )
    (comp (ref "R100")
      (value "RC1206FR-07100RL")
      (footprint "RC1206N_YAG")
      (description "No Description Available")
      (fields (field (name "COPYRIGHT") "Copyright (C) 2022 Ultra Librarian. All rights reserved."))
      (libsource (lib "RC1206FR-07100RL") (part "RC1206FR-07100RL"))
    )
    (comp (ref "R101")
      (value "RC1206FR-07100RL")
      (footprint "RC1206N_YAG")
      (description "No Description Available")
      (fields (field (name "COPYRIGHT") "Copyright (C) 2022 Ultra Librarian. All rights reserved."))
      (libsource (lib "RC1206FR-07100RL") (part "RC1206FR-07100RL"))
    )
    (comp (ref "R102")
      (value "RC1206FR-07100RL")
      (footprint "RC1206N_YAG")
      (description "No Description Available")
      (fields (field (name "COPYRIGHT") "Copyright (C) 2022 Ultra Librarian. All rights reserved."))
      (libsource (lib "RC1206FR-07100RL") (part "RC1206FR-07100RL"))
    )
    (comp (ref "R103")
      (value "RC1206FR-07100RL")
      (footprint "RC1206N_YAG")
      (description "No Description Available")
      (fields (field (name "COPYRIGHT") "Copyright (C) 2022 Ultra Librarian. All rights reserved."))
      (libsource (lib "RC1206FR-07100RL") (part "RC1206FR-07100RL"))
    )
    (comp (ref "R104")
      (value "RC1206FR-07100RL")
      (footprint "RC1206N_YAG")
      (description "No Description Available")
      (fields (field (name "COPYRIGHT") "Copyright (C) 2022 Ultra Librarian. All rights reserved."))
      (libsource (lib "RC1206FR-07100RL") (part "RC1206FR-07100RL"))
    )
    (comp (ref "R105")
      (value "RC1206FR-07100RL")
      (footprint "RC1206N_YAG")
      (description "No Description Available")
      (fields (field (name "COPYRIGHT") "Copyright (C) 2022 Ultra Librarian. All rights reserved."))
      (libsource (lib "RC1206FR-07100RL") (part "RC1206FR-07100RL"))
    )
    (comp (ref "R106")
      (value "RC1206FR-07100RL")
      (footprint "RC1206N_YAG")
      (description "No Description Available")
      (fields (field (name "COPYRIGHT") "Copyright (C) 2022 Ultra Librarian. All rights reserved."))
      (libsource (lib "RC1206FR-07100RL") (part "RC1206FR-07100RL"))
    )
    (comp (ref "R107")
      (value "RC1206FR-07100RL")
      (footprint "RC1206N_YAG")
      (description "No Description Available")
      (fields (field (name "COPYRIGHT") "Copyright (C) 2022 Ultra Librarian. All rights reserved."))
      (libsource (lib "RC1206FR-07100RL") (part "RC1206FR-07100RL"))
    )
    (comp (ref "R108")
      (value "RC1206FR-07100RL")
      (footprint "RC1206N_YAG")
      (description "No Description Available")
      (fields (field (name "COPYRIGHT") "Copyright (C) 2022 Ultra Librarian. All rights reserved."))
      (libsource (lib "RC1206FR-07100RL") (part "RC1206FR-07100RL"))
    )
    (comp (ref "R109")
      (value "RC1206FR-07100RL")
      (footprint "RC1206N_YAG")
      (description "No Description Available")
      (fields (field (name "COPYRIGHT") "Copyright (C) 2022 Ultra Librarian. All rights reserved."))
      (libsource (lib "RC1206FR-07100RL") (part "RC1206FR-07100RL"))
    )
    (comp (ref "R110")
      (value "RC1206FR-07100RL")
      (footprint "RC1206N_YAG")
      (description "No Description Available")
      (fields (field (name "COPYRIGHT") "Copyright (C) 2022 Ultra Librarian. All rights reserved."))
      (libsource (lib "RC1206FR-07100RL") (part "RC1206FR-07100RL"))
    )
    (comp (ref "R111")
      (value "RC1206FR-07100RL")
      (footprint "RC1206N_YAG")
      (description "No Description Available")
      (fields (field (name "COPYRIGHT") "Copyright (C) 2022 Ultra Librarian. All rights reserved."))
      (libsource (lib "RC1206FR-07100RL") (part "RC1206FR-07100RL"))
    )
    (comp (ref "R112")
      (value "RC1206FR-07100RL")
      (footprint "RC1206N_YAG")
      (description "No Description Available")
      (fields (field (name "COPYRIGHT") "Copyright (C) 2022 Ultra Librarian. All rights reserved."))
      (libsource (lib "RC1206FR-07100RL") (part "RC1206FR-07100RL"))
    )
    (comp (ref "R113")
      (value "RC1206FR-07100RL")
      (footprint "RC1206N_YAG")
      (description "No Description Available")
      (fields (field (name "COPYRIGHT") "Copyright (C) 2022 Ultra Librarian. All rights reserved."))
      (libsource (lib "RC1206FR-07100RL") (part "RC1206FR-07100RL"))
    )
    (comp (ref "R114")
      (value "RC1206FR-07100RL")
      (footprint "RC1206N_YAG")
      (description "No Description Available")
      (fields (field (name "COPYRIGHT") "Copyright (C) 2022 Ultra Librarian. All rights reserved."))
      (libsource (lib "RC1206FR-07100RL") (part "RC1206FR-07100RL"))
    )
    (comp (ref "R115")
      (value "RC1206FR-07100RL")
      (footprint "RC1206N_YAG")
      (description "No Description Available")
      (fields (field (name "COPYRIGHT") "Copyright (C) 2022 Ultra Librarian. All rights reserved."))
      (libsource (lib "RC1206FR-07100RL") (part "RC1206FR-07100RL"))
    )
    (comp (ref "R116")
      (value "RC1206FR-07100RL")
      (footprint "RC1206N_YAG")
      (description "No Description Available")
      (fields (field (name "COPYRIGHT") "Copyright (C) 2022 Ultra Librarian. All rights reserved."))
      (libsource (lib "RC1206FR-07100RL") (part "RC1206FR-07100RL"))
    )
    (comp (ref "R117")
      (value "RC1206FR-07100RL")
      (footprint "RC1206N_YAG")
      (description "No Description Available")
      (fields (field (name "COPYRIGHT") "Copyright (C) 2022 Ultra Librarian. All rights reserved."))
      (libsource (lib "RC1206FR-07100RL") (part "RC1206FR-07100RL"))
    )
    (comp (ref "R118")
      (value "RC1206FR-07100RL")
      (footprint "RC1206N_YAG")
      (description "No Description Available")
      (fields (field (name "COPYRIGHT") "Copyright (C) 2022 Ultra Librarian. All rights reserved."))
      (libsource (lib "RC1206FR-07100RL") (part "RC1206FR-07100RL"))
    )
    (comp (ref "R119")
      (value "RC1206FR-07100RL")
      (footprint "RC1206N_YAG")
      (description "No Description Available")
      (fields (field (name "COPYRIGHT") "Copyright (C) 2022 Ultra Librarian. All rights reserved."))
      (libsource (lib "RC1206FR-07100RL") (part "RC1206FR-07100RL"))
    )
    (comp (ref "R120")
      (value "RC1206FR-07100RL")
      (footprint "RC1206N_YAG")
      (description "No Description Available")
      (fields (field (name "COPYRIGHT") "Copyright (C) 2022 Ultra Librarian. All rights reserved."))
      (libsource (lib "RC1206FR-07100RL") (part "RC1206FR-07100RL"))
    )
    (comp (ref "R121")
      (value "RC1206FR-07100RL")
      (footprint "RC1206N_YAG")
      (description "No Description Available")
      (fields (field (name "COPYRIGHT") "Copyright (C) 2022 Ultra Librarian. All rights reserved."))
      (libsource (lib "RC1206FR-07100RL") (part "RC1206FR-07100RL"))
    )
    (comp (ref "R122")
      (value "RC1206FR-07100RL")
      (footprint "RC1206N_YAG")
      (description "No Description Available")
      (fields (field (name "COPYRIGHT") "Copyright (C) 2022 Ultra Librarian. All rights reserved."))
      (libsource (lib "RC1206FR-07100RL") (part "RC1206FR-07100RL"))
    )
    (comp (ref "R123")
      (value "RC1206FR-07100RL")
      (footprint "RC1206N_YAG")
      (description "No Description Available")
      (fields (field (name "COPYRIGHT") "Copyright (C) 2022 Ultra Librarian. All rights reserved."))
      (libsource (lib "RC1206FR-07100RL") (part "RC1206FR-07100RL"))
    )
    (comp (ref "R124")
      (value "RC1206FR-07100RL")
      (footprint "RC1206N_YAG")
      (description "No Description Available")
      (fields (field (name "COPYRIGHT") "Copyright (C) 2022 Ultra Librarian. All rights reserved."))
      (libsource (lib "RC1206FR-07100RL") (part "RC1206FR-07100RL"))
    )
    (comp (ref "R125")
      (value "RC1206FR-07100RL")
      (footprint "RC1206N_YAG")
      (description "No Description Available")
      (fields (field (name "COPYRIGHT") "Copyright (C) 2022 Ultra Librarian. All rights reserved."))
      (libsource (lib "RC1206FR-07100RL") (part "RC1206FR-07100RL"))
    )
    (comp (ref "R126")
      (value "RC1206FR-07100RL")
      (footprint "RC1206N_YAG")
      (description "No Description Available")
      (fields (field (name "COPYRIGHT") "Copyright (C) 2022 Ultra Librarian. All rights reserved."))
      (libsource (lib "RC1206FR-07100RL") (part "RC1206FR-07100RL"))
    )
    (comp (ref "R127")
      (value "RC1206FR-07100RL")
      (footprint "RC1206N_YAG")
      (description "No Description Available")
      (fields (field (name "COPYRIGHT") "Copyright (C) 2022 Ultra Librarian. All rights reserved."))
      (libsource (lib "RC1206FR-07100RL") (part "RC1206FR-07100RL"))
    )
    (comp (ref "R128")
      (value "RC1206FR-07100RL")
      (footprint "RC1206N_YAG")
      (description "No Description Available")
      (fields (field (name "COPYRIGHT") "Copyright (C) 2022 Ultra Librarian. All rights reserved."))
      (libsource (lib "RC1206FR-07100RL") (part "RC1206FR-07100RL"))
    )
    (comp (ref "R129")
      (value "RC1206FR-07100RL")
      (footprint "RC1206N_YAG")
      (description "No Description Available")
      (fields (field (name "COPYRIGHT") "Copyright (C) 2022 Ultra Librarian. All rights reserved."))
      (libsource (lib "RC1206FR-07100RL") (part "RC1206FR-07100RL"))
    )
    (comp (ref "R130")
      (value "RC1206FR-07100RL")
      (footprint "RC1206N_YAG")
      (description "No Description Available")
      (fields (field (name "COPYRIGHT") "Copyright (C) 2022 Ultra Librarian. All rights reserved."))
      (libsource (lib "RC1206FR-07100RL") (part "RC1206FR-07100RL"))
    )
    (comp (ref "R131")
      (value "RC1206FR-07100RL")
      (footprint "RC1206N_YAG")
      (description "No Description Available")
      (fields (field (name "COPYRIGHT") "Copyright (C) 2022 Ultra Librarian. All rights reserved."))
      (libsource (lib "RC1206FR-07100RL") (part "RC1206FR-07100RL"))
    )
    (comp (ref "R132")
      (value "RC1206FR-07100RL")
      (footprint "RC1206N_YAG")
      (description "No Description Available")
      (fields (field (name "COPYRIGHT") "Copyright (C) 2022 Ultra Librarian. All rights reserved."))
      (libsource (lib "RC1206FR-07100RL") (part "RC1206FR-07100RL"))
    )
    (comp (ref "R133")
      (value "RC1206FR-07100RL")
      (footprint "RC1206N_YAG")
      (description "No Description Available")
      (fields (field (name "COPYRIGHT") "Copyright (C) 2022 Ultra Librarian. All rights reserved."))
      (libsource (lib "RC1206FR-07100RL") (part "RC1206FR-07100RL"))
    )
    (comp (ref "R134")
      (value "RC1206FR-07100RL")
      (footprint "RC1206N_YAG")
      (description "No Description Available")
      (fields (field (name "COPYRIGHT") "Copyright (C) 2022 Ultra Librarian. All rights reserved."))
      (libsource (lib "RC1206FR-07100RL") (part "RC1206FR-07100RL"))
    )
    (comp (ref "R135")
      (value "RC1206FR-07100RL")
      (footprint "RC1206N_YAG")
      (description "No Description Available")
      (fields (field (name "COPYRIGHT") "Copyright (C) 2022 Ultra Librarian. All rights reserved."))
      (libsource (lib "RC1206FR-07100RL") (part "RC1206FR-07100RL"))
    )
    (comp (ref "R136")
      (value "RC1206FR-07100RL")
      (footprint "RC1206N_YAG")
      (description "No Description Available")
      (fields (field (name "COPYRIGHT") "Copyright (C) 2022 Ultra Librarian. All rights reserved."))
      (libsource (lib "RC1206FR-07100RL") (part "RC1206FR-07100RL"))
    )
    (comp (ref "R137")
      (value "RC1206FR-07100RL")
      (footprint "RC1206N_YAG")
      (description "No Description Available")
      (fields (field (name "COPYRIGHT") "Copyright (C) 2022 Ultra Librarian. All rights reserved."))
      (libsource (lib "RC1206FR-07100RL") (part "RC1206FR-07100RL"))
    )
    (comp (ref "R138")
      (value "RC1206FR-07100RL")
      (footprint "RC1206N_YAG")
      (description "No Description Available")
      (fields (field (name "COPYRIGHT") "Copyright (C) 2022 Ultra Librarian. All rights reserved."))
      (libsource (lib "RC1206FR-07100RL") (part "RC1206FR-07100RL"))
    )
    (comp (ref "R139")
      (value "RC1206FR-07100RL")
      (footprint "RC1206N_YAG")
      (description "No Description Available")
      (fields (field (name "COPYRIGHT") "Copyright (C) 2022 Ultra Librarian. All rights reserved."))
      (libsource (lib "RC1206FR-07100RL") (part "RC1206FR-07100RL"))
    )
    (comp (ref "R140")
      (value "RC1206FR-07100RL")
      (footprint "RC1206N_YAG")
      (description "No Description Available")
      (fields (field (name "COPYRIGHT") "Copyright (C) 2022 Ultra Librarian. All rights reserved."))
      (libsource (lib "RC1206FR-07100RL") (part "RC1206FR-07100RL"))
    )
    (comp (ref "R141")
      (value "RC1206FR-07100RL")
      (footprint "RC1206N_YAG")
      (description "No Description Available")
      (fields (field (name "COPYRIGHT") "Copyright (C) 2022 Ultra Librarian. All rights reserved."))
      (libsource (lib "RC1206FR-07100RL") (part "RC1206FR-07100RL"))
    )
    (comp (ref "R142")
      (value "RC1206FR-07100RL")
      (footprint "RC1206N_YAG")
      (description "No Description Available")
      (fields (field (name "COPYRIGHT") "Copyright (C) 2022 Ultra Librarian. All rights reserved."))
      (libsource (lib "RC1206FR-07100RL") (part "RC1206FR-07100RL"))
    )
    (comp (ref "R143")
      (value "RC1206FR-07100RL")
      (footprint "RC1206N_YAG")
      (description "No Description Available")
      (fields (field (name "COPYRIGHT") "Copyright (C) 2022 Ultra Librarian. All rights reserved."))
      (libsource (lib "RC1206FR-07100RL") (part "RC1206FR-07100RL"))
    )
    (comp (ref "R144")
      (value "RC1206FR-07100RL")
      (footprint "RC1206N_YAG")
      (description "No Description Available")
      (fields (field (name "COPYRIGHT") "Copyright (C) 2022 Ultra Librarian. All rights reserved."))
      (libsource (lib "RC1206FR-07100RL") (part "RC1206FR-07100RL"))
    )
    (comp (ref "R145")
      (value "RC1206FR-07100RL")
      (footprint "RC1206N_YAG")
      (description "No Description Available")
      (fields (field (name "COPYRIGHT") "Copyright (C) 2022 Ultra Librarian. All rights reserved."))
      (libsource (lib "RC1206FR-07100RL") (part "RC1206FR-07100RL"))
    )
    (comp (ref "R146")
      (value "RC1206FR-07100RL")
      (footprint "RC1206N_YAG")
      (description "No Description Available")
      (fields (field (name "COPYRIGHT") "Copyright (C) 2022 Ultra Librarian. All rights reserved."))
      (libsource (lib "RC1206FR-07100RL") (part "RC1206FR-07100RL"))
    )
    (comp (ref "R147")
      (value "RC1206FR-07100RL")
      (footprint "RC1206N_YAG")
      (description "No Description Available")
      (fields (field (name "COPYRIGHT") "Copyright (C) 2022 Ultra Librarian. All rights reserved."))
      (libsource (lib "RC1206FR-07100RL") (part "RC1206FR-07100RL"))
    )
    (comp (ref "R148")
      (value "RC1206FR-07100RL")
      (footprint "RC1206N_YAG")
      (description "No Description Available")
      (fields (field (name "COPYRIGHT") "Copyright (C) 2022 Ultra Librarian. All rights reserved."))
      (libsource (lib "RC1206FR-07100RL") (part "RC1206FR-07100RL"))
    )
    (comp (ref "R149")
      (value "RC1206FR-07100RL")
      (footprint "RC1206N_YAG")
      (description "No Description Available")
      (fields (field (name "COPYRIGHT") "Copyright (C) 2022 Ultra Librarian. All rights reserved."))
      (libsource (lib "RC1206FR-07100RL") (part "RC1206FR-07100RL"))
    )
    (comp (ref "R150")
      (value "RC1206FR-07100RL")
      (footprint "RC1206N_YAG")
      (description "No Description Available")
      (fields (field (name "COPYRIGHT") "Copyright (C) 2022 Ultra Librarian. All rights reserved."))
      (libsource (lib "RC1206FR-07100RL") (part "RC1206FR-07100RL"))
    )
    (comp (ref "R151")
      (value "RC1206FR-07100RL")
      (footprint "RC1206N_YAG")
      (description "No Description Available")
      (fields (field (name "COPYRIGHT") "Copyright (C) 2022 Ultra Librarian. All rights reserved."))
      (libsource (lib "RC1206FR-07100RL") (part "RC1206FR-07100RL"))
    )
    (comp (ref "R152")
      (value "RC1206FR-07100RL")
      (footprint "RC1206N_YAG")
      (description "No Description Available")
      (fields (field (name "COPYRIGHT") "Copyright (C) 2022 Ultra Librarian. All rights reserved."))
      (libsource (lib "RC1206FR-07100RL") (part "RC1206FR-07100RL"))
    )
    (comp (ref "R153")
      (value "RC1206FR-07100RL")
      (footprint "RC1206N_YAG")
      (description "No Description Available")
      (fields (field (name "COPYRIGHT") "Copyright (C) 2022 Ultra Librarian. All rights reserved."))
      (libsource (lib "RC1206FR-07100RL") (part "RC1206FR-07100RL"))
    )
    (comp (ref "R154")
      (value "RC1206FR-07100RL")
      (footprint "RC1206N_YAG")
      (description "No Description Available")
      (fields (field (name "COPYRIGHT") "Copyright (C) 2022 Ultra Librarian. All rights reserved."))
      (libsource (lib "RC1206FR-07100RL") (part "RC1206FR-07100RL"))
    )
    (comp (ref "R155")
      (value "RC1206FR-07100RL")
      (footprint "RC1206N_YAG")
      (description "No Description Available")
      (fields (field (name "COPYRIGHT") "Copyright (C) 2022 Ultra Librarian. All rights reserved."))
      (libsource (lib "RC1206FR-07100RL") (part "RC1206FR-07100RL"))
    )
    (comp (ref "R156")
      (value "RC1206FR-07100RL")
      (footprint "RC1206N_YAG")
      (description "No Description Available")
      (fields (field (name "COPYRIGHT") "Copyright (C) 2022 Ultra Librarian. All rights reserved."))
      (libsource (lib "RC1206FR-07100RL") (part "RC1206FR-07100RL"))
    )
    (comp (ref "R157")
      (value "RC1206FR-07100RL")
      (footprint "RC1206N_YAG")
      (description "No Description Available")
      (fields (field (name "COPYRIGHT") "Copyright (C) 2022 Ultra Librarian. All rights reserved."))
      (libsource (lib "RC1206FR-07100RL") (part "RC1206FR-07100RL"))
    )
    (comp (ref "R158")
      (value "RC1206FR-07100RL")
      (footprint "RC1206N_YAG")
      (description "No Description Available")
      (fields (field (name "COPYRIGHT") "Copyright (C) 2022 Ultra Librarian. All rights reserved."))
      (libsource (lib "RC1206FR-07100RL") (part "RC1206FR-07100RL"))
    )
    (comp (ref "R159")
      (value "RC1206FR-07100RL")
      (footprint "RC1206N_YAG")
      (description "No Description Available")
      (fields (field (name "COPYRIGHT") "Copyright (C) 2022 Ultra Librarian. All rights reserved."))
      (libsource (lib "RC1206FR-07100RL") (part "RC1206FR-07100RL"))
    )
    (comp (ref "R160")
      (value "RC1206FR-07100RL")
      (footprint "RC1206N_YAG")
      (description "No Description Available")
      (fields (field (name "COPYRIGHT") "Copyright (C) 2022 Ultra Librarian. All rights reserved."))
      (libsource (lib "RC1206FR-07100RL") (part "RC1206FR-07100RL"))
    )
    (comp (ref "R161")
      (value "RC1206FR-07100RL")
      (footprint "RC1206N_YAG")
      (description "No Description Available")
      (fields (field (name "COPYRIGHT") "Copyright (C) 2022 Ultra Librarian. All rights reserved."))
      (libsource (lib "RC1206FR-07100RL") (part "RC1206FR-07100RL"))
    )
    (comp (ref "R162")
      (value "RC1206FR-07100RL")
      (footprint "RC1206N_YAG")
      (description "No Description Available")
      (fields (field (name "COPYRIGHT") "Copyright (C) 2022 Ultra Librarian. All rights reserved."))
      (libsource (lib "RC1206FR-07100RL") (part "RC1206FR-07100RL"))
    )
    (comp (ref "R163")
      (value "RC1206FR-07100RL")
      (footprint "RC1206N_YAG")
      (description "No Description Available")
      (fields (field (name "COPYRIGHT") "Copyright (C) 2022 Ultra Librarian. All rights reserved."))
      (libsource (lib "RC1206FR-07100RL") (part "RC1206FR-07100RL"))
    )
    (comp (ref "R164")
      (value "RC1206FR-07100RL")
      (footprint "RC1206N_YAG")
      (description "No Description Available")
      (fields (field (name "COPYRIGHT") "Copyright (C) 2022 Ultra Librarian. All rights reserved."))
      (libsource (lib "RC1206FR-07100RL") (part "RC1206FR-07100RL"))
    )
    (comp (ref "R165")
      (value "RC1206FR-07100RL")
      (footprint "RC1206N_YAG")
      (description "No Description Available")
      (fields (field (name "COPYRIGHT") "Copyright (C) 2022 Ultra Librarian. All rights reserved."))
      (libsource (lib "RC1206FR-07100RL") (part "RC1206FR-07100RL"))
    )
    (comp (ref "R166")
      (value "RC1206FR-07100RL")
      (footprint "RC1206N_YAG")
      (description "No Description Available")
      (fields (field (name "COPYRIGHT") "Copyright (C) 2022 Ultra Librarian. All rights reserved."))
      (libsource (lib "RC1206FR-07100RL") (part "RC1206FR-07100RL"))
    )
    (comp (ref "R167")
      (value "RC1206FR-07100RL")
      (footprint "RC1206N_YAG")
      (description "No Description Available")
      (fields (field (name "COPYRIGHT") "Copyright (C) 2022 Ultra Librarian. All rights reserved."))
      (libsource (lib "RC1206FR-07100RL") (part "RC1206FR-07100RL"))
    )
    (comp (ref "R168")
      (value "RC1206FR-07100RL")
      (footprint "RC1206N_YAG")
      (description "No Description Available")
      (fields (field (name "COPYRIGHT") "Copyright (C) 2022 Ultra Librarian. All rights reserved."))
      (libsource (lib "RC1206FR-07100RL") (part "RC1206FR-07100RL"))
    )
    (comp (ref "R169")
      (value "RC1206FR-07100RL")
      (footprint "RC1206N_YAG")
      (description "No Description Available")
      (fields (field (name "COPYRIGHT") "Copyright (C) 2022 Ultra Librarian. All rights reserved."))
      (libsource (lib "RC1206FR-07100RL") (part "RC1206FR-07100RL"))
    )
    (comp (ref "R170")
      (value "RC1206FR-07100RL")
      (footprint "RC1206N_YAG")
      (description "No Description Available")
      (fields (field (name "COPYRIGHT") "Copyright (C) 2022 Ultra Librarian. All rights reserved."))
      (libsource (lib "RC1206FR-07100RL") (part "RC1206FR-07100RL"))
    )
    (comp (ref "R171")
      (value "RC1206FR-07100RL")
      (footprint "RC1206N_YAG")
      (description "No Description Available")
      (fields (field (name "COPYRIGHT") "Copyright (C) 2022 Ultra Librarian. All rights reserved."))
      (libsource (lib "RC1206FR-07100RL") (part "RC1206FR-07100RL"))
    )
    (comp (ref "R172")
      (value "RC1206FR-07100RL")
      (footprint "RC1206N_YAG")
      (description "No Description Available")
      (fields (field (name "COPYRIGHT") "Copyright (C) 2022 Ultra Librarian. All rights reserved."))
      (libsource (lib "RC1206FR-07100RL") (part "RC1206FR-07100RL"))
    )
    (comp (ref "R173")
      (value "RC1206FR-07100RL")
      (footprint "RC1206N_YAG")
      (description "No Description Available")
      (fields (field (name "COPYRIGHT") "Copyright (C) 2022 Ultra Librarian. All rights reserved."))
      (libsource (lib "RC1206FR-07100RL") (part "RC1206FR-07100RL"))
    )
    (comp (ref "R174")
      (value "RC1206FR-07100RL")
      (footprint "RC1206N_YAG")
      (description "No Description Available")
      (fields (field (name "COPYRIGHT") "Copyright (C) 2022 Ultra Librarian. All rights reserved."))
      (libsource (lib "RC1206FR-07100RL") (part "RC1206FR-07100RL"))
    )
    (comp (ref "R175")
      (value "RC1206FR-07100RL")
      (footprint "RC1206N_YAG")
      (description "No Description Available")
      (fields (field (name "COPYRIGHT") "Copyright (C) 2022 Ultra Librarian. All rights reserved."))
      (libsource (lib "RC1206FR-07100RL") (part "RC1206FR-07100RL"))
    )
    (comp (ref "R176")
      (value "RC1206FR-07100RL")
      (footprint "RC1206N_YAG")
      (description "No Description Available")
      (fields (field (name "COPYRIGHT") "Copyright (C) 2022 Ultra Librarian. All rights reserved."))
      (libsource (lib "RC1206FR-07100RL") (part "RC1206FR-07100RL"))
    )
    (comp (ref "R177")
      (value "RC1206FR-07100RL")
      (footprint "RC1206N_YAG")
      (description "No Description Available")
      (fields (field (name "COPYRIGHT") "Copyright (C) 2022 Ultra Librarian. All rights reserved."))
      (libsource (lib "RC1206FR-07100RL") (part "RC1206FR-07100RL"))
    )
    (comp (ref "R178")
      (value "RC1206FR-07100RL")
      (footprint "RC1206N_YAG")
      (description "No Description Available")
      (fields (field (name "COPYRIGHT") "Copyright (C) 2022 Ultra Librarian. All rights reserved."))
      (libsource (lib "RC1206FR-07100RL") (part "RC1206FR-07100RL"))
    )
    (comp (ref "R179")
      (value "RC1206FR-07100RL")
      (footprint "RC1206N_YAG")
      (description "No Description Available")
      (fields (field (name "COPYRIGHT") "Copyright (C) 2022 Ultra Librarian. All rights reserved."))
      (libsource (lib "RC1206FR-07100RL") (part "RC1206FR-07100RL"))
    )
    (comp (ref "R180")
      (value "RC1206FR-07100RL")
      (footprint "RC1206N_YAG")
      (description "No Description Available")
      (fields (field (name "COPYRIGHT") "Copyright (C) 2022 Ultra Librarian. All rights reserved."))
      (libsource (lib "RC1206FR-07100RL") (part "RC1206FR-07100RL"))
    )
    (comp (ref "R181")
      (value "RC1206FR-07100RL")
      (footprint "RC1206N_YAG")
      (description "No Description Available")
      (fields (field (name "COPYRIGHT") "Copyright (C) 2022 Ultra Librarian. All rights reserved."))
      (libsource (lib "RC1206FR-07100RL") (part "RC1206FR-07100RL"))
    )
    (comp (ref "R182")
      (value "RC1206FR-07100RL")
      (footprint "RC1206N_YAG")
      (description "No Description Available")
      (fields (field (name "COPYRIGHT") "Copyright (C) 2022 Ultra Librarian. All rights reserved."))
      (libsource (lib "RC1206FR-07100RL") (part "RC1206FR-07100RL"))
    )
    (comp (ref "R183")
      (value "RC1206FR-07100RL")
      (footprint "RC1206N_YAG")
      (description "No Description Available")
      (fields (field (name "COPYRIGHT") "Copyright (C) 2022 Ultra Librarian. All rights reserved."))
      (libsource (lib "RC1206FR-07100RL") (part "RC1206FR-07100RL"))
    )
    (comp (ref "R184")
      (value "RC1206FR-07100RL")
      (footprint "RC1206N_YAG")
      (description "No Description Available")
      (fields (field (name "COPYRIGHT") "Copyright (C) 2022 Ultra Librarian. All rights reserved."))
      (libsource (lib "RC1206FR-07100RL") (part "RC1206FR-07100RL"))
    )
    (comp (ref "R185")
      (value "RC1206FR-07100RL")
      (footprint "RC1206N_YAG")
      (description "No Description Available")
      (fields (field (name "COPYRIGHT") "Copyright (C) 2022 Ultra Librarian. All rights reserved."))
      (libsource (lib "RC1206FR-07100RL") (part "RC1206FR-07100RL"))
    )
    (comp (ref "R186")
      (value "RC1206FR-07100RL")
      (footprint "RC1206N_YAG")
      (description "No Description Available")
      (fields (field (name "COPYRIGHT") "Copyright (C) 2022 Ultra Librarian. All rights reserved."))
      (libsource (lib "RC1206FR-07100RL") (part "RC1206FR-07100RL"))
    )
    (comp (ref "R187")
      (value "RC1206FR-07100RL")
      (footprint "RC1206N_YAG")
      (description "No Description Available")
      (fields (field (name "COPYRIGHT") "Copyright (C) 2022 Ultra Librarian. All rights reserved."))
      (libsource (lib "RC1206FR-07100RL") (part "RC1206FR-07100RL"))
    )
    (comp (ref "R188")
      (value "RC1206FR-07100RL")
      (footprint "RC1206N_YAG")
      (description "No Description Available")
      (fields (field (name "COPYRIGHT") "Copyright (C) 2022 Ultra Librarian. All rights reserved."))
      (libsource (lib "RC1206FR-07100RL") (part "RC1206FR-07100RL"))
    )
    (comp (ref "R189")
      (value "RC1206FR-07100RL")
      (footprint "RC1206N_YAG")
      (description "No Description Available")
      (fields (field (name "COPYRIGHT") "Copyright (C) 2022 Ultra Librarian. All rights reserved."))
      (libsource (lib "RC1206FR-07100RL") (part "RC1206FR-07100RL"))
    )
    (comp (ref "R190")
      (value "RC1206FR-07100RL")
      (footprint "RC1206N_YAG")
      (description "No Description Available")
      (fields (field (name "COPYRIGHT") "Copyright (C) 2022 Ultra Librarian. All rights reserved."))
      (libsource (lib "RC1206FR-07100RL") (part "RC1206FR-07100RL"))
    )
    (comp (ref "R191")
      (value "RC1206FR-07100RL")
      (footprint "RC1206N_YAG")
      (description "No Description Available")
      (fields (field (name "COPYRIGHT") "Copyright (C) 2022 Ultra Librarian. All rights reserved."))
      (libsource (lib "RC1206FR-07100RL") (part "RC1206FR-07100RL"))
    )
    (comp (ref "R192")
      (value "RC1206FR-07100RL")
      (footprint "RC1206N_YAG")
      (description "No Description Available")
      (fields (field (name "COPYRIGHT") "Copyright (C) 2022 Ultra Librarian. All rights reserved."))
      (libsource (lib "RC1206FR-07100RL") (part "RC1206FR-07100RL"))
    )
    (comp (ref "R193")
      (value "RC1206FR-07100RL")
      (footprint "RC1206N_YAG")
      (description "No Description Available")
      (fields (field (name "COPYRIGHT") "Copyright (C) 2022 Ultra Librarian. All rights reserved."))
      (libsource (lib "RC1206FR-07100RL") (part "RC1206FR-07100RL"))
    )
    (comp (ref "R194")
      (value "RC1206FR-07100RL")
      (footprint "RC1206N_YAG")
      (description "No Description Available")
      (fields (field (name "COPYRIGHT") "Copyright (C) 2022 Ultra Librarian. All rights reserved."))
      (libsource (lib "RC1206FR-07100RL") (part "RC1206FR-07100RL"))
    )
    (comp (ref "R195")
      (value "RC1206FR-07100RL")
      (footprint "RC1206N_YAG")
      (description "No Description Available")
      (fields (field (name "COPYRIGHT") "Copyright (C) 2022 Ultra Librarian. All rights reserved."))
      (libsource (lib "RC1206FR-07100RL") (part "RC1206FR-07100RL"))
    )
    (comp (ref "R196")
      (value "RC1206FR-07100RL")
      (footprint "RC1206N_YAG")
      (description "No Description Available")
      (fields (field (name "COPYRIGHT") "Copyright (C) 2022 Ultra Librarian. All rights reserved."))
      (libsource (lib "RC1206FR-07100RL") (part "RC1206FR-07100RL"))
    )
    (comp (ref "R197")
      (value "RC1206FR-07100RL")
      (footprint "RC1206N_YAG")
      (description "No Description Available")
      (fields (field (name "COPYRIGHT") "Copyright (C) 2022 Ultra Librarian. All rights reserved."))
      (libsource (lib "RC1206FR-07100RL") (part "RC1206FR-07100RL"))
    )
    (comp (ref "R198")
      (value "RC1206FR-07100RL")
      (footprint "RC1206N_YAG")
      (description "No Description Available")
      (fields (field (name "COPYRIGHT") "Copyright (C) 2022 Ultra Librarian. All rights reserved."))
      (libsource (lib "RC1206FR-07100RL") (part "RC1206FR-07100RL"))
    )
    (comp (ref "R199")
      (value "RC1206FR-07100RL")
      (footprint "RC1206N_YAG")
      (description "No Description Available")
      (fields (field (name "COPYRIGHT") "Copyright (C) 2022 Ultra Librarian. All rights reserved."))
      (libsource (lib "RC1206FR-07100RL") (part "RC1206FR-07100RL"))
    )
    (comp (ref "R200")
      (value "RC1206FR-07100RL")
      (footprint "RC1206N_YAG")
      (description "No Description Available")
      (fields (field (name "COPYRIGHT") "Copyright (C) 2022 Ultra Librarian. All rights reserved."))
      (libsource (lib "RC1206FR-07100RL") (part "RC1206FR-07100RL"))
    )
    (comp (ref "R201")
      (value "RC1206FR-07100RL")
      (footprint "RC1206N_YAG")
      (description "No Description Available")
      (fields (field (name "COPYRIGHT") "Copyright (C) 2022 Ultra Librarian. All rights reserved."))
      (libsource (lib "RC1206FR-07100RL") (part "RC1206FR-07100RL"))
    )
    (comp (ref "R202")
      (value "RC1206FR-07100RL")
      (footprint "RC1206N_YAG")
      (description "No Description Available")
      (fields (field (name "COPYRIGHT") "Copyright (C) 2022 Ultra Librarian. All rights reserved."))
      (libsource (lib "RC1206FR-07100RL") (part "RC1206FR-07100RL"))
    )
    (comp (ref "R203")
      (value "RC1206FR-07100RL")
      (footprint "RC1206N_YAG")
      (description "No Description Available")
      (fields (field (name "COPYRIGHT") "Copyright (C) 2022 Ultra Librarian. All rights reserved."))
      (libsource (lib "RC1206FR-07100RL") (part "RC1206FR-07100RL"))
    )
    (comp (ref "R204")
      (value "RC1206FR-07100RL")
      (footprint "RC1206N_YAG")
      (description "No Description Available")
      (fields (field (name "COPYRIGHT") "Copyright (C) 2022 Ultra Librarian. All rights reserved."))
      (libsource (lib "RC1206FR-07100RL") (part "RC1206FR-07100RL"))
    )
    (comp (ref "R205")
      (value "RC1206FR-07100RL")
      (footprint "RC1206N_YAG")
      (description "No Description Available")
      (fields (field (name "COPYRIGHT") "Copyright (C) 2022 Ultra Librarian. All rights reserved."))
      (libsource (lib "RC1206FR-07100RL") (part "RC1206FR-07100RL"))
    )
    (comp (ref "R206")
      (value "RC1206FR-07100RL")
      (footprint "RC1206N_YAG")
      (description "No Description Available")
      (fields (field (name "COPYRIGHT") "Copyright (C) 2022 Ultra Librarian. All rights reserved."))
      (libsource (lib "RC1206FR-07100RL") (part "RC1206FR-07100RL"))
    )
    (comp (ref "R207")
      (value "RC1206FR-07100RL")
      (footprint "RC1206N_YAG")
      (description "No Description Available")
      (fields (field (name "COPYRIGHT") "Copyright (C) 2022 Ultra Librarian. All rights reserved."))
      (libsource (lib "RC1206FR-07100RL") (part "RC1206FR-07100RL"))
    )
    (comp (ref "R208")
      (value "RC1206FR-07100RL")
      (footprint "RC1206N_YAG")
      (description "No Description Available")
      (fields (field (name "COPYRIGHT") "Copyright (C) 2022 Ultra Librarian. All rights reserved."))
      (libsource (lib "RC1206FR-07100RL") (part "RC1206FR-07100RL"))
    )
    (comp (ref "R209")
      (value "RC1206FR-07100RL")
      (footprint "RC1206N_YAG")
      (description "No Description Available")
      (fields (field (name "COPYRIGHT") "Copyright (C) 2022 Ultra Librarian. All rights reserved."))
      (libsource (lib "RC1206FR-07100RL") (part "RC1206FR-07100RL"))
    )
    (comp (ref "R210")
      (value "RC1206FR-07100RL")
      (footprint "RC1206N_YAG")
      (description "No Description Available")
      (fields (field (name "COPYRIGHT") "Copyright (C) 2022 Ultra Librarian. All rights reserved."))
      (libsource (lib "RC1206FR-07100RL") (part "RC1206FR-07100RL"))
    )
    (comp (ref "R211")
      (value "RC1206FR-07100RL")
      (footprint "RC1206N_YAG")
      (description "No Description Available")
      (fields (field (name "COPYRIGHT") "Copyright (C) 2022 Ultra Librarian. All rights reserved."))
      (libsource (lib "RC1206FR-07100RL") (part "RC1206FR-07100RL"))
    )
    (comp (ref "R212")
      (value "RC1206FR-07100RL")
      (footprint "RC1206N_YAG")
      (description "No Description Available")
      (fields (field (name "COPYRIGHT") "Copyright (C) 2022 Ultra Librarian. All rights reserved."))
      (libsource (lib "RC1206FR-07100RL") (part "RC1206FR-07100RL"))
    )
    (comp (ref "R213")
      (value "RC1206FR-07100RL")
      (footprint "RC1206N_YAG")
      (description "No Description Available")
      (fields (field (name "COPYRIGHT") "Copyright (C) 2022 Ultra Librarian. All rights reserved."))
      (libsource (lib "RC1206FR-07100RL") (part "RC1206FR-07100RL"))
    )
    (comp (ref "R214")
      (value "RC1206FR-07100RL")
      (footprint "RC1206N_YAG")
      (description "No Description Available")
      (fields (field (name "COPYRIGHT") "Copyright (C) 2022 Ultra Librarian. All rights reserved."))
      (libsource (lib "RC1206FR-07100RL") (part "RC1206FR-07100RL"))
    )
    (comp (ref "R215")
      (value "RC1206FR-07100RL")
      (footprint "RC1206N_YAG")
      (description "No Description Available")
      (fields (field (name "COPYRIGHT") "Copyright (C) 2022 Ultra Librarian. All rights reserved."))
      (libsource (lib "RC1206FR-07100RL") (part "RC1206FR-07100RL"))
    )
    (comp (ref "R216")
      (value "RC1206FR-07100RL")
      (footprint "RC1206N_YAG")
      (description "No Description Available")
      (fields (field (name "COPYRIGHT") "Copyright (C) 2022 Ultra Librarian. All rights reserved."))
      (libsource (lib "RC1206FR-07100RL") (part "RC1206FR-07100RL"))
    )
    (comp (ref "R217")
      (value "RC1206FR-07100RL")
      (footprint "RC1206N_YAG")
      (description "No Description Available")
      (fields (field (name "COPYRIGHT") "Copyright (C) 2022 Ultra Librarian. All rights reserved."))
      (libsource (lib "RC1206FR-07100RL") (part "RC1206FR-07100RL"))
    )
    (comp (ref "R218")
      (value "RC1206FR-07100RL")
      (footprint "RC1206N_YAG")
      (description "No Description Available")
      (fields (field (name "COPYRIGHT") "Copyright (C) 2022 Ultra Librarian. All rights reserved."))
      (libsource (lib "RC1206FR-07100RL") (part "RC1206FR-07100RL"))
    )
    (comp (ref "R219")
      (value "RC1206FR-07100RL")
      (footprint "RC1206N_YAG")
      (description "No Description Available")
      (fields (field (name "COPYRIGHT") "Copyright (C) 2022 Ultra Librarian. All rights reserved."))
      (libsource (lib "RC1206FR-07100RL") (part "RC1206FR-07100RL"))
    )
    (comp (ref "R220")
      (value "RC1206FR-07100RL")
      (footprint "RC1206N_YAG")
      (description "No Description Available")
      (fields (field (name "COPYRIGHT") "Copyright (C) 2022 Ultra Librarian. All rights reserved."))
      (libsource (lib "RC1206FR-07100RL") (part "RC1206FR-07100RL"))
    )
    (comp (ref "R221")
      (value "RC1206FR-07100RL")
      (footprint "RC1206N_YAG")
      (description "No Description Available")
      (fields (field (name "COPYRIGHT") "Copyright (C) 2022 Ultra Librarian. All rights reserved."))
      (libsource (lib "RC1206FR-07100RL") (part "RC1206FR-07100RL"))
    )
    (comp (ref "R222")
      (value "RC1206FR-07100RL")
      (footprint "RC1206N_YAG")
      (description "No Description Available")
      (fields (field (name "COPYRIGHT") "Copyright (C) 2022 Ultra Librarian. All rights reserved."))
      (libsource (lib "RC1206FR-07100RL") (part "RC1206FR-07100RL"))
    )
    (comp (ref "R223")
      (value "RC1206FR-07100RL")
      (footprint "RC1206N_YAG")
      (description "No Description Available")
      (fields (field (name "COPYRIGHT") "Copyright (C) 2022 Ultra Librarian. All rights reserved."))
      (libsource (lib "RC1206FR-07100RL") (part "RC1206FR-07100RL"))
    )
    (comp (ref "R224")
      (value "RC1206FR-07100RL")
      (footprint "RC1206N_YAG")
      (description "No Description Available")
      (fields (field (name "COPYRIGHT") "Copyright (C) 2022 Ultra Librarian. All rights reserved."))
      (libsource (lib "RC1206FR-07100RL") (part "RC1206FR-07100RL"))
    )
    (comp (ref "R225")
      (value "RC1206FR-07100RL")
      (footprint "RC1206N_YAG")
      (description "No Description Available")
      (fields (field (name "COPYRIGHT") "Copyright (C) 2022 Ultra Librarian. All rights reserved."))
      (libsource (lib "RC1206FR-07100RL") (part "RC1206FR-07100RL"))
    )
    (comp (ref "R226")
      (value "RC1206FR-07100RL")
      (footprint "RC1206N_YAG")
      (description "No Description Available")
      (fields (field (name "COPYRIGHT") "Copyright (C) 2022 Ultra Librarian. All rights reserved."))
      (libsource (lib "RC1206FR-07100RL") (part "RC1206FR-07100RL"))
    )
    (comp (ref "R227")
      (value "RC1206FR-07100RL")
      (footprint "RC1206N_YAG")
      (description "No Description Available")
      (fields (field (name "COPYRIGHT") "Copyright (C) 2022 Ultra Librarian. All rights reserved."))
      (libsource (lib "RC1206FR-07100RL") (part "RC1206FR-07100RL"))
    )
    (comp (ref "R228")
      (value "RC1206FR-07100RL")
      (footprint "RC1206N_YAG")
      (description "No Description Available")
      (fields (field (name "COPYRIGHT") "Copyright (C) 2022 Ultra Librarian. All rights reserved."))
      (libsource (lib "RC1206FR-07100RL") (part "RC1206FR-07100RL"))
    )
    (comp (ref "R229")
      (value "RC1206FR-07100RL")
      (footprint "RC1206N_YAG")
      (description "No Description Available")
      (fields (field (name "COPYRIGHT") "Copyright (C) 2022 Ultra Librarian. All rights reserved."))
      (libsource (lib "RC1206FR-07100RL") (part "RC1206FR-07100RL"))
    )
    (comp (ref "R230")
      (value "RC1206FR-07100RL")
      (footprint "RC1206N_YAG")
      (description "No Description Available")
      (fields (field (name "COPYRIGHT") "Copyright (C) 2022 Ultra Librarian. All rights reserved."))
      (libsource (lib "RC1206FR-07100RL") (part "RC1206FR-07100RL"))
    )
    (comp (ref "R231")
      (value "RC1206FR-07100RL")
      (footprint "RC1206N_YAG")
      (description "No Description Available")
      (fields (field (name "COPYRIGHT") "Copyright (C) 2022 Ultra Librarian. All rights reserved."))
      (libsource (lib "RC1206FR-07100RL") (part "RC1206FR-07100RL"))
    )
    (comp (ref "R232")
      (value "RC1206FR-07100RL")
      (footprint "RC1206N_YAG")
      (description "No Description Available")
      (fields (field (name "COPYRIGHT") "Copyright (C) 2022 Ultra Librarian. All rights reserved."))
      (libsource (lib "RC1206FR-07100RL") (part "RC1206FR-07100RL"))
    )
    (comp (ref "R233")
      (value "RC1206FR-07100RL")
      (footprint "RC1206N_YAG")
      (description "No Description Available")
      (fields (field (name "COPYRIGHT") "Copyright (C) 2022 Ultra Librarian. All rights reserved."))
      (libsource (lib "RC1206FR-07100RL") (part "RC1206FR-07100RL"))
    )
    (comp (ref "R234")
      (value "RC1206FR-07100RL")
      (footprint "RC1206N_YAG")
      (description "No Description Available")
      (fields (field (name "COPYRIGHT") "Copyright (C) 2022 Ultra Librarian. All rights reserved."))
      (libsource (lib "RC1206FR-07100RL") (part "RC1206FR-07100RL"))
    )
    (comp (ref "R235")
      (value "RC1206FR-07100RL")
      (footprint "RC1206N_YAG")
      (description "No Description Available")
      (fields (field (name "COPYRIGHT") "Copyright (C) 2022 Ultra Librarian. All rights reserved."))
      (libsource (lib "RC1206FR-07100RL") (part "RC1206FR-07100RL"))
    )
    (comp (ref "R236")
      (value "RC1206FR-07100RL")
      (footprint "RC1206N_YAG")
      (description "No Description Available")
      (fields (field (name "COPYRIGHT") "Copyright (C) 2022 Ultra Librarian. All rights reserved."))
      (libsource (lib "RC1206FR-07100RL") (part "RC1206FR-07100RL"))
    )
    (comp (ref "R237")
      (value "RC1206FR-07100RL")
      (footprint "RC1206N_YAG")
      (description "No Description Available")
      (fields (field (name "COPYRIGHT") "Copyright (C) 2022 Ultra Librarian. All rights reserved."))
      (libsource (lib "RC1206FR-07100RL") (part "RC1206FR-07100RL"))
    )
    (comp (ref "R238")
      (value "RC1206FR-07100RL")
      (footprint "RC1206N_YAG")
      (description "No Description Available")
      (fields (field (name "COPYRIGHT") "Copyright (C) 2022 Ultra Librarian. All rights reserved."))
      (libsource (lib "RC1206FR-07100RL") (part "RC1206FR-07100RL"))
    )
    (comp (ref "R239")
      (value "RC1206FR-07100RL")
      (footprint "RC1206N_YAG")
      (description "No Description Available")
      (fields (field (name "COPYRIGHT") "Copyright (C) 2022 Ultra Librarian. All rights reserved."))
      (libsource (lib "RC1206FR-07100RL") (part "RC1206FR-07100RL"))
    )
    (comp (ref "R240")
      (value "RC1206FR-07100RL")
      (footprint "RC1206N_YAG")
      (description "No Description Available")
      (fields (field (name "COPYRIGHT") "Copyright (C) 2022 Ultra Librarian. All rights reserved."))
      (libsource (lib "RC1206FR-07100RL") (part "RC1206FR-07100RL"))
    )
    (comp (ref "R241")
      (value "RC1206FR-07100RL")
      (footprint "RC1206N_YAG")
      (description "No Description Available")
      (fields (field (name "COPYRIGHT") "Copyright (C) 2022 Ultra Librarian. All rights reserved."))
      (libsource (lib "RC1206FR-07100RL") (part "RC1206FR-07100RL"))
    )
    (comp (ref "R242")
      (value "RC1206FR-07100RL")
      (footprint "RC1206N_YAG")
      (description "No Description Available")
      (fields (field (name "COPYRIGHT") "Copyright (C) 2022 Ultra Librarian. All rights reserved."))
      (libsource (lib "RC1206FR-07100RL") (part "RC1206FR-07100RL"))
    )
    (comp (ref "R243")
      (value "RC1206FR-07100RL")
      (footprint "RC1206N_YAG")
      (description "No Description Available")
      (fields (field (name "COPYRIGHT") "Copyright (C) 2022 Ultra Librarian. All rights reserved."))
      (libsource (lib "RC1206FR-07100RL") (part "RC1206FR-07100RL"))
    )
    (comp (ref "R244")
      (value "RC1206FR-07100RL")
      (footprint "RC1206N_YAG")
      (description "No Description Available")
      (fields (field (name "COPYRIGHT") "Copyright (C) 2022 Ultra Librarian. All rights reserved."))
      (libsource (lib "RC1206FR-07100RL") (part "RC1206FR-07100RL"))
    )
    (comp (ref "R245")
      (value "RC1206FR-07100RL")
      (footprint "RC1206N_YAG")
      (description "No Description Available")
      (fields (field (name "COPYRIGHT") "Copyright (C) 2022 Ultra Librarian. All rights reserved."))
      (libsource (lib "RC1206FR-07100RL") (part "RC1206FR-07100RL"))
    )
    (comp (ref "R246")
      (value "RC1206FR-07100RL")
      (footprint "RC1206N_YAG")
      (description "No Description Available")
      (fields (field (name "COPYRIGHT") "Copyright (C) 2022 Ultra Librarian. All rights reserved."))
      (libsource (lib "RC1206FR-07100RL") (part "RC1206FR-07100RL"))
    )
    (comp (ref "R247")
      (value "RC1206FR-07100RL")
      (footprint "RC1206N_YAG")
      (description "No Description Available")
      (fields (field (name "COPYRIGHT") "Copyright (C) 2022 Ultra Librarian. All rights reserved."))
      (libsource (lib "RC1206FR-07100RL") (part "RC1206FR-07100RL"))
    )
    (comp (ref "R248")
      (value "RC1206FR-07100RL")
      (footprint "RC1206N_YAG")
      (description "No Description Available")
      (fields (field (name "COPYRIGHT") "Copyright (C) 2022 Ultra Librarian. All rights reserved."))
      (libsource (lib "RC1206FR-07100RL") (part "RC1206FR-07100RL"))
    )
    (comp (ref "R249")
      (value "RC1206FR-07100RL")
      (footprint "RC1206N_YAG")
      (description "No Description Available")
      (fields (field (name "COPYRIGHT") "Copyright (C) 2022 Ultra Librarian. All rights reserved."))
      (libsource (lib "RC1206FR-07100RL") (part "RC1206FR-07100RL"))
    )
    (comp (ref "R250")
      (value "RC1206FR-07100RL")
      (footprint "RC1206N_YAG")
      (description "No Description Available")
      (fields (field (name "COPYRIGHT") "Copyright (C) 2022 Ultra Librarian. All rights reserved."))
      (libsource (lib "RC1206FR-07100RL") (part "RC1206FR-07100RL"))
    )
    (comp (ref "R251")
      (value "RC1206FR-07100RL")
      (footprint "RC1206N_YAG")
      (description "No Description Available")
      (fields (field (name "COPYRIGHT") "Copyright (C) 2022 Ultra Librarian. All rights reserved."))
      (libsource (lib "RC1206FR-07100RL") (part "RC1206FR-07100RL"))
    )
    (comp (ref "R252")
      (value "RC1206FR-07100RL")
      (footprint "RC1206N_YAG")
      (description "No Description Available")
      (fields (field (name "COPYRIGHT") "Copyright (C) 2022 Ultra Librarian. All rights reserved."))
      (libsource (lib "RC1206FR-07100RL") (part "RC1206FR-07100RL"))
    )
    (comp (ref "R253")
      (value "RC1206FR-07100RL")
      (footprint "RC1206N_YAG")
      (description "No Description Available")
      (fields (field (name "COPYRIGHT") "Copyright (C) 2022 Ultra Librarian. All rights reserved."))
      (libsource (lib "RC1206FR-07100RL") (part "RC1206FR-07100RL"))
    )
    (comp (ref "R254")
      (value "RC1206FR-07100RL")
      (footprint "RC1206N_YAG")
      (description "No Description Available")
      (fields (field (name "COPYRIGHT") "Copyright (C) 2022 Ultra Librarian. All rights reserved."))
      (libsource (lib "RC1206FR-07100RL") (part "RC1206FR-07100RL"))
    )
    (comp (ref "R255")
      (value "RC1206FR-07100RL")
      (footprint "RC1206N_YAG")
      (description "No Description Available")
      (fields (field (name "COPYRIGHT") "Copyright (C) 2022 Ultra Librarian. All rights reserved."))
      (libsource (lib "RC1206FR-07100RL") (part "RC1206FR-07100RL"))
    )
    (comp (ref "R256")
      (value "RC1206FR-07100RL")
      (footprint "RC1206N_YAG")
      (description "No Description Available")
      (fields (field (name "COPYRIGHT") "Copyright (C) 2022 Ultra Librarian. All rights reserved."))
      (libsource (lib "RC1206FR-07100RL") (part "RC1206FR-07100RL"))
    )
    (comp (ref "R257")
      (value "RC1206FR-07100RL")
      (footprint "RC1206N_YAG")
      (description "No Description Available")
      (fields (field (name "COPYRIGHT") "Copyright (C) 2022 Ultra Librarian. All rights reserved."))
      (libsource (lib "RC1206FR-07100RL") (part "RC1206FR-07100RL"))
    )
    (comp (ref "R258")
      (value "RC1206FR-07100RL")
      (footprint "RC1206N_YAG")
      (description "No Description Available")
      (fields (field (name "COPYRIGHT") "Copyright (C) 2022 Ultra Librarian. All rights reserved."))
      (libsource (lib "RC1206FR-07100RL") (part "RC1206FR-07100RL"))
    )
    (comp (ref "R259")
      (value "RC1206FR-07100RL")
      (footprint "RC1206N_YAG")
      (description "No Description Available")
      (fields (field (name "COPYRIGHT") "Copyright (C) 2022 Ultra Librarian. All rights reserved."))
      (libsource (lib "RC1206FR-07100RL") (part "RC1206FR-07100RL"))
    )
    (comp (ref "R260")
      (value "RC1206FR-07100RL")
      (footprint "RC1206N_YAG")
      (description "No Description Available")
      (fields (field (name "COPYRIGHT") "Copyright (C) 2022 Ultra Librarian. All rights reserved."))
      (libsource (lib "RC1206FR-07100RL") (part "RC1206FR-07100RL"))
    )
    (comp (ref "R261")
      (value "RC1206FR-07100RL")
      (footprint "RC1206N_YAG")
      (description "No Description Available")
      (fields (field (name "COPYRIGHT") "Copyright (C) 2022 Ultra Librarian. All rights reserved."))
      (libsource (lib "RC1206FR-07100RL") (part "RC1206FR-07100RL"))
    )
    (comp (ref "R262")
      (value "RC1206FR-07100RL")
      (footprint "RC1206N_YAG")
      (description "No Description Available")
      (fields (field (name "COPYRIGHT") "Copyright (C) 2022 Ultra Librarian. All rights reserved."))
      (libsource (lib "RC1206FR-07100RL") (part "RC1206FR-07100RL"))
    )
    (comp (ref "R263")
      (value "RC1206FR-07100RL")
      (footprint "RC1206N_YAG")
      (description "No Description Available")
      (fields (field (name "COPYRIGHT") "Copyright (C) 2022 Ultra Librarian. All rights reserved."))
      (libsource (lib "RC1206FR-07100RL") (part "RC1206FR-07100RL"))
    )
    (comp (ref "R264")
      (value "RC1206FR-07100RL")
      (footprint "RC1206N_YAG")
      (description "No Description Available")
      (fields (field (name "COPYRIGHT") "Copyright (C) 2022 Ultra Librarian. All rights reserved."))
      (libsource (lib "RC1206FR-07100RL") (part "RC1206FR-07100RL"))
    )
    (comp (ref "R265")
      (value "RC1206FR-07100RL")
      (footprint "RC1206N_YAG")
      (description "No Description Available")
      (fields (field (name "COPYRIGHT") "Copyright (C) 2022 Ultra Librarian. All rights reserved."))
      (libsource (lib "RC1206FR-07100RL") (part "RC1206FR-07100RL"))
    )
    (comp (ref "R266")
      (value "RC1206FR-07100RL")
      (footprint "RC1206N_YAG")
      (description "No Description Available")
      (fields (field (name "COPYRIGHT") "Copyright (C) 2022 Ultra Librarian. All rights reserved."))
      (libsource (lib "RC1206FR-07100RL") (part "RC1206FR-07100RL"))
    )
    (comp (ref "R267")
      (value "RC1206FR-07100RL")
      (footprint "RC1206N_YAG")
      (description "No Description Available")
      (fields (field (name "COPYRIGHT") "Copyright (C) 2022 Ultra Librarian. All rights reserved."))
      (libsource (lib "RC1206FR-07100RL") (part "RC1206FR-07100RL"))
    )
    (comp (ref "R268")
      (value "RC1206FR-07100RL")
      (footprint "RC1206N_YAG")
      (description "No Description Available")
      (fields (field (name "COPYRIGHT") "Copyright (C) 2022 Ultra Librarian. All rights reserved."))
      (libsource (lib "RC1206FR-07100RL") (part "RC1206FR-07100RL"))
    )
    (comp (ref "R269")
      (value "RC1206FR-07100RL")
      (footprint "RC1206N_YAG")
      (description "No Description Available")
      (fields (field (name "COPYRIGHT") "Copyright (C) 2022 Ultra Librarian. All rights reserved."))
      (libsource (lib "RC1206FR-07100RL") (part "RC1206FR-07100RL"))
    )
    (comp (ref "R270")
      (value "RC1206FR-07100RL")
      (footprint "RC1206N_YAG")
      (description "No Description Available")
      (fields (field (name "COPYRIGHT") "Copyright (C) 2022 Ultra Librarian. All rights reserved."))
      (libsource (lib "RC1206FR-07100RL") (part "RC1206FR-07100RL"))
    )
    (comp (ref "R271")
      (value "RC1206FR-07100RL")
      (footprint "RC1206N_YAG")
      (description "No Description Available")
      (fields (field (name "COPYRIGHT") "Copyright (C) 2022 Ultra Librarian. All rights reserved."))
      (libsource (lib "RC1206FR-07100RL") (part "RC1206FR-07100RL"))
    )
    (comp (ref "R272")
      (value "RC1206FR-07100RL")
      (footprint "RC1206N_YAG")
      (description "No Description Available")
      (fields (field (name "COPYRIGHT") "Copyright (C) 2022 Ultra Librarian. All rights reserved."))
      (libsource (lib "RC1206FR-07100RL") (part "RC1206FR-07100RL"))
    )
    (comp (ref "R273")
      (value "RC1206FR-07100RL")
      (footprint "RC1206N_YAG")
      (description "No Description Available")
      (fields (field (name "COPYRIGHT") "Copyright (C) 2022 Ultra Librarian. All rights reserved."))
      (libsource (lib "RC1206FR-07100RL") (part "RC1206FR-07100RL"))
    )
    (comp (ref "R274")
      (value "RC1206FR-07100RL")
      (footprint "RC1206N_YAG")
      (description "No Description Available")
      (fields (field (name "COPYRIGHT") "Copyright (C) 2022 Ultra Librarian. All rights reserved."))
      (libsource (lib "RC1206FR-07100RL") (part "RC1206FR-07100RL"))
    )
    (comp (ref "R275")
      (value "RC1206FR-07100RL")
      (footprint "RC1206N_YAG")
      (description "No Description Available")
      (fields (field (name "COPYRIGHT") "Copyright (C) 2022 Ultra Librarian. All rights reserved."))
      (libsource (lib "RC1206FR-07100RL") (part "RC1206FR-07100RL"))
    )
    (comp (ref "R276")
      (value "RC1206FR-07100RL")
      (footprint "RC1206N_YAG")
      (description "No Description Available")
      (fields (field (name "COPYRIGHT") "Copyright (C) 2022 Ultra Librarian. All rights reserved."))
      (libsource (lib "RC1206FR-07100RL") (part "RC1206FR-07100RL"))
    )
    (comp (ref "R277")
      (value "RC1206FR-07100RL")
      (footprint "RC1206N_YAG")
      (description "No Description Available")
      (fields (field (name "COPYRIGHT") "Copyright (C) 2022 Ultra Librarian. All rights reserved."))
      (libsource (lib "RC1206FR-07100RL") (part "RC1206FR-07100RL"))
    )
    (comp (ref "R278")
      (value "RC1206FR-07100RL")
      (footprint "RC1206N_YAG")
      (description "No Description Available")
      (fields (field (name "COPYRIGHT") "Copyright (C) 2022 Ultra Librarian. All rights reserved."))
      (libsource (lib "RC1206FR-07100RL") (part "RC1206FR-07100RL"))
    )
    (comp (ref "R279")
      (value "RC1206FR-07100RL")
      (footprint "RC1206N_YAG")
      (description "No Description Available")
      (fields (field (name "COPYRIGHT") "Copyright (C) 2022 Ultra Librarian. All rights reserved."))
      (libsource (lib "RC1206FR-07100RL") (part "RC1206FR-07100RL"))
    )
    (comp (ref "R280")
      (value "RC1206FR-07100RL")
      (footprint "RC1206N_YAG")
      (description "No Description Available")
      (fields (field (name "COPYRIGHT") "Copyright (C) 2022 Ultra Librarian. All rights reserved."))
      (libsource (lib "RC1206FR-07100RL") (part "RC1206FR-07100RL"))
    )
    (comp (ref "R281")
      (value "RC1206FR-07100RL")
      (footprint "RC1206N_YAG")
      (description "No Description Available")
      (fields (field (name "COPYRIGHT") "Copyright (C) 2022 Ultra Librarian. All rights reserved."))
      (libsource (lib "RC1206FR-07100RL") (part "RC1206FR-07100RL"))
    )
    (comp (ref "R282")
      (value "RC1206FR-07100RL")
      (footprint "RC1206N_YAG")
      (description "No Description Available")
      (fields (field (name "COPYRIGHT") "Copyright (C) 2022 Ultra Librarian. All rights reserved."))
      (libsource (lib "RC1206FR-07100RL") (part "RC1206FR-07100RL"))
    )
    (comp (ref "R283")
      (value "RC1206FR-07100RL")
      (footprint "RC1206N_YAG")
      (description "No Description Available")
      (fields (field (name "COPYRIGHT") "Copyright (C) 2022 Ultra Librarian. All rights reserved."))
      (libsource (lib "RC1206FR-07100RL") (part "RC1206FR-07100RL"))
    )
    (comp (ref "R284")
      (value "RC1206FR-07100RL")
      (footprint "RC1206N_YAG")
      (description "No Description Available")
      (fields (field (name "COPYRIGHT") "Copyright (C) 2022 Ultra Librarian. All rights reserved."))
      (libsource (lib "RC1206FR-07100RL") (part "RC1206FR-07100RL"))
    )
    (comp (ref "R285")
      (value "RC1206FR-07100RL")
      (footprint "RC1206N_YAG")
      (description "No Description Available")
      (fields (field (name "COPYRIGHT") "Copyright (C) 2022 Ultra Librarian. All rights reserved."))
      (libsource (lib "RC1206FR-07100RL") (part "RC1206FR-07100RL"))
    )
    (comp (ref "R286")
      (value "RC1206FR-07100RL")
      (footprint "RC1206N_YAG")
      (description "No Description Available")
      (fields (field (name "COPYRIGHT") "Copyright (C) 2022 Ultra Librarian. All rights reserved."))
      (libsource (lib "RC1206FR-07100RL") (part "RC1206FR-07100RL"))
    )
    (comp (ref "R287")
      (value "RC1206FR-07100RL")
      (footprint "RC1206N_YAG")
      (description "No Description Available")
      (fields (field (name "COPYRIGHT") "Copyright (C) 2022 Ultra Librarian. All rights reserved."))
      (libsource (lib "RC1206FR-07100RL") (part "RC1206FR-07100RL"))
    )
    (comp (ref "R288")
      (value "RC1206FR-07100RL")
      (footprint "RC1206N_YAG")
      (description "No Description Available")
      (fields (field (name "COPYRIGHT") "Copyright (C) 2022 Ultra Librarian. All rights reserved."))
      (libsource (lib "RC1206FR-07100RL") (part "RC1206FR-07100RL"))
    )
    (comp (ref "R289")
      (value "RC1206FR-07100RL")
      (footprint "RC1206N_YAG")
      (description "No Description Available")
      (fields (field (name "COPYRIGHT") "Copyright (C) 2022 Ultra Librarian. All rights reserved."))
      (libsource (lib "RC1206FR-07100RL") (part "RC1206FR-07100RL"))
    )
    (comp (ref "R290")
      (value "RC1206FR-07100RL")
      (footprint "RC1206N_YAG")
      (description "No Description Available")
      (fields (field (name "COPYRIGHT") "Copyright (C) 2022 Ultra Librarian. All rights reserved."))
      (libsource (lib "RC1206FR-07100RL") (part "RC1206FR-07100RL"))
    )
    (comp (ref "R291")
      (value "RC1206FR-07100RL")
      (footprint "RC1206N_YAG")
      (description "No Description Available")
      (fields (field (name "COPYRIGHT") "Copyright (C) 2022 Ultra Librarian. All rights reserved."))
      (libsource (lib "RC1206FR-07100RL") (part "RC1206FR-07100RL"))
    )
    (comp (ref "R292")
      (value "RC1206FR-07100RL")
      (footprint "RC1206N_YAG")
      (description "No Description Available")
      (fields (field (name "COPYRIGHT") "Copyright (C) 2022 Ultra Librarian. All rights reserved."))
      (libsource (lib "RC1206FR-07100RL") (part "RC1206FR-07100RL"))
    )
    (comp (ref "R293")
      (value "RC1206FR-07100RL")
      (footprint "RC1206N_YAG")
      (description "No Description Available")
      (fields (field (name "COPYRIGHT") "Copyright (C) 2022 Ultra Librarian. All rights reserved."))
      (libsource (lib "RC1206FR-07100RL") (part "RC1206FR-07100RL"))
    )
    (comp (ref "R294")
      (value "RC1206FR-07100RL")
      (footprint "RC1206N_YAG")
      (description "No Description Available")
      (fields (field (name "COPYRIGHT") "Copyright (C) 2022 Ultra Librarian. All rights reserved."))
      (libsource (lib "RC1206FR-07100RL") (part "RC1206FR-07100RL"))
    )
    (comp (ref "R295")
      (value "RC1206FR-07100RL")
      (footprint "RC1206N_YAG")
      (description "No Description Available")
      (fields (field (name "COPYRIGHT") "Copyright (C) 2022 Ultra Librarian. All rights reserved."))
      (libsource (lib "RC1206FR-07100RL") (part "RC1206FR-07100RL"))
    )
    (comp (ref "R296")
      (value "RC1206FR-07100RL")
      (footprint "RC1206N_YAG")
      (description "No Description Available")
      (fields (field (name "COPYRIGHT") "Copyright (C) 2022 Ultra Librarian. All rights reserved."))
      (libsource (lib "RC1206FR-07100RL") (part "RC1206FR-07100RL"))
    )
    (comp (ref "R297")
      (value "RC1206FR-07100RL")
      (footprint "RC1206N_YAG")
      (description "No Description Available")
      (fields (field (name "COPYRIGHT") "Copyright (C) 2022 Ultra Librarian. All rights reserved."))
      (libsource (lib "RC1206FR-07100RL") (part "RC1206FR-07100RL"))
    )
    (comp (ref "R298")
      (value "RC1206FR-07100RL")
      (footprint "RC1206N_YAG")
      (description "No Description Available")
      (fields (field (name "COPYRIGHT") "Copyright (C) 2022 Ultra Librarian. All rights reserved."))
      (libsource (lib "RC1206FR-07100RL") (part "RC1206FR-07100RL"))
    )
    (comp (ref "R299")
      (value "RC1206FR-07100RL")
      (footprint "RC1206N_YAG")
      (description "No Description Available")
      (fields (field (name "COPYRIGHT") "Copyright (C) 2022 Ultra Librarian. All rights reserved."))
      (libsource (lib "RC1206FR-07100RL") (part "RC1206FR-07100RL"))
    )
    (comp (ref "R300")
      (value "RC1206FR-07100RL")
      (footprint "RC1206N_YAG")
      (description "No Description Available")
      (fields (field (name "COPYRIGHT") "Copyright (C) 2022 Ultra Librarian. All rights reserved."))
      (libsource (lib "RC1206FR-07100RL") (part "RC1206FR-07100RL"))
    )
    (comp (ref "R301")
      (value "RC1206FR-07100RL")
      (footprint "RC1206N_YAG")
      (description "No Description Available")
      (fields (field (name "COPYRIGHT") "Copyright (C) 2022 Ultra Librarian. All rights reserved."))
      (libsource (lib "RC1206FR-07100RL") (part "RC1206FR-07100RL"))
    )
    (comp (ref "R302")
      (value "RC1206FR-07100RL")
      (footprint "RC1206N_YAG")
      (description "No Description Available")
      (fields (field (name "COPYRIGHT") "Copyright (C) 2022 Ultra Librarian. All rights reserved."))
      (libsource (lib "RC1206FR-07100RL") (part "RC1206FR-07100RL"))
    )
    (comp (ref "R303")
      (value "RC1206FR-07100RL")
      (footprint "RC1206N_YAG")
      (description "No Description Available")
      (fields (field (name "COPYRIGHT") "Copyright (C) 2022 Ultra Librarian. All rights reserved."))
      (libsource (lib "RC1206FR-07100RL") (part "RC1206FR-07100RL"))
    )
    (comp (ref "R304")
      (value "RC1206FR-07100RL")
      (footprint "RC1206N_YAG")
      (description "No Description Available")
      (fields (field (name "COPYRIGHT") "Copyright (C) 2022 Ultra Librarian. All rights reserved."))
      (libsource (lib "RC1206FR-07100RL") (part "RC1206FR-07100RL"))
    )
    (comp (ref "R305")
      (value "RC1206FR-07100RL")
      (footprint "RC1206N_YAG")
      (description "No Description Available")
      (fields (field (name "COPYRIGHT") "Copyright (C) 2022 Ultra Librarian. All rights reserved."))
      (libsource (lib "RC1206FR-07100RL") (part "RC1206FR-07100RL"))
    )
    (comp (ref "R306")
      (value "RC1206FR-07100RL")
      (footprint "RC1206N_YAG")
      (description "No Description Available")
      (fields (field (name "COPYRIGHT") "Copyright (C) 2022 Ultra Librarian. All rights reserved."))
      (libsource (lib "RC1206FR-07100RL") (part "RC1206FR-07100RL"))
    )
    (comp (ref "R307")
      (value "RC1206FR-07100RL")
      (footprint "RC1206N_YAG")
      (description "No Description Available")
      (fields (field (name "COPYRIGHT") "Copyright (C) 2022 Ultra Librarian. All rights reserved."))
      (libsource (lib "RC1206FR-07100RL") (part "RC1206FR-07100RL"))
    )
    (comp (ref "R308")
      (value "RC1206FR-07100RL")
      (footprint "RC1206N_YAG")
      (description "No Description Available")
      (fields (field (name "COPYRIGHT") "Copyright (C) 2022 Ultra Librarian. All rights reserved."))
      (libsource (lib "RC1206FR-07100RL") (part "RC1206FR-07100RL"))
    )
    (comp (ref "R309")
      (value "RC1206FR-07100RL")
      (footprint "RC1206N_YAG")
      (description "No Description Available")
      (fields (field (name "COPYRIGHT") "Copyright (C) 2022 Ultra Librarian. All rights reserved."))
      (libsource (lib "RC1206FR-07100RL") (part "RC1206FR-07100RL"))
    )
    (comp (ref "R310")
      (value "RC1206FR-07100RL")
      (footprint "RC1206N_YAG")
      (description "No Description Available")
      (fields (field (name "COPYRIGHT") "Copyright (C) 2022 Ultra Librarian. All rights reserved."))
      (libsource (lib "RC1206FR-07100RL") (part "RC1206FR-07100RL"))
    )
    (comp (ref "R311")
      (value "RC1206FR-07100RL")
      (footprint "RC1206N_YAG")
      (description "No Description Available")
      (fields (field (name "COPYRIGHT") "Copyright (C) 2022 Ultra Librarian. All rights reserved."))
      (libsource (lib "RC1206FR-07100RL") (part "RC1206FR-07100RL"))
    )
    (comp (ref "R312")
      (value "RC1206FR-07100RL")
      (footprint "RC1206N_YAG")
      (description "No Description Available")
      (fields (field (name "COPYRIGHT") "Copyright (C) 2022 Ultra Librarian. All rights reserved."))
      (libsource (lib "RC1206FR-07100RL") (part "RC1206FR-07100RL"))
    )
    (comp (ref "R313")
      (value "RC1206FR-07100RL")
      (footprint "RC1206N_YAG")
      (description "No Description Available")
      (fields (field (name "COPYRIGHT") "Copyright (C) 2022 Ultra Librarian. All rights reserved."))
      (libsource (lib "RC1206FR-07100RL") (part "RC1206FR-07100RL"))
    )
    (comp (ref "R314")
      (value "RC1206FR-07100RL")
      (footprint "RC1206N_YAG")
      (description "No Description Available")
      (fields (field (name "COPYRIGHT") "Copyright (C) 2022 Ultra Librarian. All rights reserved."))
      (libsource (lib "RC1206FR-07100RL") (part "RC1206FR-07100RL"))
    )
    (comp (ref "R315")
      (value "RC1206FR-07100RL")
      (footprint "RC1206N_YAG")
      (description "No Description Available")
      (fields (field (name "COPYRIGHT") "Copyright (C) 2022 Ultra Librarian. All rights reserved."))
      (libsource (lib "RC1206FR-07100RL") (part "RC1206FR-07100RL"))
    )
    (comp (ref "R316")
      (value "RC1206FR-07100RL")
      (footprint "RC1206N_YAG")
      (description "No Description Available")
      (fields (field (name "COPYRIGHT") "Copyright (C) 2022 Ultra Librarian. All rights reserved."))
      (libsource (lib "RC1206FR-07100RL") (part "RC1206FR-07100RL"))
    )
    (comp (ref "R317")
      (value "RC1206FR-07100RL")
      (footprint "RC1206N_YAG")
      (description "No Description Available")
      (fields (field (name "COPYRIGHT") "Copyright (C) 2022 Ultra Librarian. All rights reserved."))
      (libsource (lib "RC1206FR-07100RL") (part "RC1206FR-07100RL"))
    )
    (comp (ref "R318")
      (value "RC1206FR-07100RL")
      (footprint "RC1206N_YAG")
      (description "No Description Available")
      (fields (field (name "COPYRIGHT") "Copyright (C) 2022 Ultra Librarian. All rights reserved."))
      (libsource (lib "RC1206FR-07100RL") (part "RC1206FR-07100RL"))
    )
    (comp (ref "R319")
      (value "RC1206FR-07100RL")
      (footprint "RC1206N_YAG")
      (description "No Description Available")
      (fields (field (name "COPYRIGHT") "Copyright (C) 2022 Ultra Librarian. All rights reserved."))
      (libsource (lib "RC1206FR-07100RL") (part "RC1206FR-07100RL"))
    )
    (comp (ref "R320")
      (value "RC1206FR-07100RL")
      (footprint "RC1206N_YAG")
      (description "No Description Available")
      (fields (field (name "COPYRIGHT") "Copyright (C) 2022 Ultra Librarian. All rights reserved."))
      (libsource (lib "RC1206FR-07100RL") (part "RC1206FR-07100RL"))
    )
    (comp (ref "R321")
      (value "RC1206FR-07100RL")
      (footprint "RC1206N_YAG")
      (description "No Description Available")
      (fields (field (name "COPYRIGHT") "Copyright (C) 2022 Ultra Librarian. All rights reserved."))
      (libsource (lib "RC1206FR-07100RL") (part "RC1206FR-07100RL"))
    )
    (comp (ref "R322")
      (value "RC1206FR-07100RL")
      (footprint "RC1206N_YAG")
      (description "No Description Available")
      (fields (field (name "COPYRIGHT") "Copyright (C) 2022 Ultra Librarian. All rights reserved."))
      (libsource (lib "RC1206FR-07100RL") (part "RC1206FR-07100RL"))
    )
    (comp (ref "R323")
      (value "RC1206FR-07100RL")
      (footprint "RC1206N_YAG")
      (description "No Description Available")
      (fields (field (name "COPYRIGHT") "Copyright (C) 2022 Ultra Librarian. All rights reserved."))
      (libsource (lib "RC1206FR-07100RL") (part "RC1206FR-07100RL"))
    )
    (comp (ref "R324")
      (value "RC1206FR-07100RL")
      (footprint "RC1206N_YAG")
      (description "No Description Available")
      (fields (field (name "COPYRIGHT") "Copyright (C) 2022 Ultra Librarian. All rights reserved."))
      (libsource (lib "RC1206FR-07100RL") (part "RC1206FR-07100RL"))
    )
    (comp (ref "R325")
      (value "RC1206FR-07100RL")
      (footprint "RC1206N_YAG")
      (description "No Description Available")
      (fields (field (name "COPYRIGHT") "Copyright (C) 2022 Ultra Librarian. All rights reserved."))
      (libsource (lib "RC1206FR-07100RL") (part "RC1206FR-07100RL"))
    )
    (comp (ref "R326")
      (value "RC1206FR-07100RL")
      (footprint "RC1206N_YAG")
      (description "No Description Available")
      (fields (field (name "COPYRIGHT") "Copyright (C) 2022 Ultra Librarian. All rights reserved."))
      (libsource (lib "RC1206FR-07100RL") (part "RC1206FR-07100RL"))
    )
    (comp (ref "R327")
      (value "RC1206FR-07100RL")
      (footprint "RC1206N_YAG")
      (description "No Description Available")
      (fields (field (name "COPYRIGHT") "Copyright (C) 2022 Ultra Librarian. All rights reserved."))
      (libsource (lib "RC1206FR-07100RL") (part "RC1206FR-07100RL"))
    )
    (comp (ref "R328")
      (value "RC1206FR-07100RL")
      (footprint "RC1206N_YAG")
      (description "No Description Available")
      (fields (field (name "COPYRIGHT") "Copyright (C) 2022 Ultra Librarian. All rights reserved."))
      (libsource (lib "RC1206FR-07100RL") (part "RC1206FR-07100RL"))
    )
    (comp (ref "R329")
      (value "RC1206FR-07100RL")
      (footprint "RC1206N_YAG")
      (description "No Description Available")
      (fields (field (name "COPYRIGHT") "Copyright (C) 2022 Ultra Librarian. All rights reserved."))
      (libsource (lib "RC1206FR-07100RL") (part "RC1206FR-07100RL"))
    )
    (comp (ref "R330")
      (value "RC1206FR-07100RL")
      (footprint "RC1206N_YAG")
      (description "No Description Available")
      (fields (field (name "COPYRIGHT") "Copyright (C) 2022 Ultra Librarian. All rights reserved."))
      (libsource (lib "RC1206FR-07100RL") (part "RC1206FR-07100RL"))
    )
    (comp (ref "R331")
      (value "RC1206FR-07100RL")
      (footprint "RC1206N_YAG")
      (description "No Description Available")
      (fields (field (name "COPYRIGHT") "Copyright (C) 2022 Ultra Librarian. All rights reserved."))
      (libsource (lib "RC1206FR-07100RL") (part "RC1206FR-07100RL"))
    )
    (comp (ref "R332")
      (value "RC1206FR-07100RL")
      (footprint "RC1206N_YAG")
      (description "No Description Available")
      (fields (field (name "COPYRIGHT") "Copyright (C) 2022 Ultra Librarian. All rights reserved."))
      (libsource (lib "RC1206FR-07100RL") (part "RC1206FR-07100RL"))
    )
    (comp (ref "R333")
      (value "RC1206FR-07100RL")
      (footprint "RC1206N_YAG")
      (description "No Description Available")
      (fields (field (name "COPYRIGHT") "Copyright (C) 2022 Ultra Librarian. All rights reserved."))
      (libsource (lib "RC1206FR-07100RL") (part "RC1206FR-07100RL"))
    )
    (comp (ref "R334")
      (value "RC1206FR-07100RL")
      (footprint "RC1206N_YAG")
      (description "No Description Available")
      (fields (field (name "COPYRIGHT") "Copyright (C) 2022 Ultra Librarian. All rights reserved."))
      (libsource (lib "RC1206FR-07100RL") (part "RC1206FR-07100RL"))
    )
    (comp (ref "R335")
      (value "RC1206FR-07100RL")
      (footprint "RC1206N_YAG")
      (description "No Description Available")
      (fields (field (name "COPYRIGHT") "Copyright (C) 2022 Ultra Librarian. All rights reserved."))
      (libsource (lib "RC1206FR-07100RL") (part "RC1206FR-07100RL"))
    )
    (comp (ref "R336")
      (value "RC1206FR-07100RL")
      (footprint "RC1206N_YAG")
      (description "No Description Available")
      (fields (field (name "COPYRIGHT") "Copyright (C) 2022 Ultra Librarian. All rights reserved."))
      (libsource (lib "RC1206FR-07100RL") (part "RC1206FR-07100RL"))
    )
    (comp (ref "R337")
      (value "RC1206FR-07100RL")
      (footprint "RC1206N_YAG")
      (description "No Description Available")
      (fields (field (name "COPYRIGHT") "Copyright (C) 2022 Ultra Librarian. All rights reserved."))
      (libsource (lib "RC1206FR-07100RL") (part "RC1206FR-07100RL"))
    )
    (comp (ref "R338")
      (value "RC1206FR-07100RL")
      (footprint "RC1206N_YAG")
      (description "No Description Available")
      (fields (field (name "COPYRIGHT") "Copyright (C) 2022 Ultra Librarian. All rights reserved."))
      (libsource (lib "RC1206FR-07100RL") (part "RC1206FR-07100RL"))
    )
    (comp (ref "R339")
      (value "RC1206FR-07100RL")
      (footprint "RC1206N_YAG")
      (description "No Description Available")
      (fields (field (name "COPYRIGHT") "Copyright (C) 2022 Ultra Librarian. All rights reserved."))
      (libsource (lib "RC1206FR-07100RL") (part "RC1206FR-07100RL"))
    )
    (comp (ref "R340")
      (value "RC1206FR-07100RL")
      (footprint "RC1206N_YAG")
      (description "No Description Available")
      (fields (field (name "COPYRIGHT") "Copyright (C) 2022 Ultra Librarian. All rights reserved."))
      (libsource (lib "RC1206FR-07100RL") (part "RC1206FR-07100RL"))
    )
    (comp (ref "R341")
      (value "RC1206FR-07100RL")
      (footprint "RC1206N_YAG")
      (description "No Description Available")
      (fields (field (name "COPYRIGHT") "Copyright (C) 2022 Ultra Librarian. All rights reserved."))
      (libsource (lib "RC1206FR-07100RL") (part "RC1206FR-07100RL"))
    )
    (comp (ref "R342")
      (value "RC1206FR-07100RL")
      (footprint "RC1206N_YAG")
      (description "No Description Available")
      (fields (field (name "COPYRIGHT") "Copyright (C) 2022 Ultra Librarian. All rights reserved."))
      (libsource (lib "RC1206FR-07100RL") (part "RC1206FR-07100RL"))
    )
    (comp (ref "R343")
      (value "RC1206FR-07100RL")
      (footprint "RC1206N_YAG")
      (description "No Description Available")
      (fields (field (name "COPYRIGHT") "Copyright (C) 2022 Ultra Librarian. All rights reserved."))
      (libsource (lib "RC1206FR-07100RL") (part "RC1206FR-07100RL"))
    )
    (comp (ref "R344")
      (value "RC1206FR-07100RL")
      (footprint "RC1206N_YAG")
      (description "No Description Available")
      (fields (field (name "COPYRIGHT") "Copyright (C) 2022 Ultra Librarian. All rights reserved."))
      (libsource (lib "RC1206FR-07100RL") (part "RC1206FR-07100RL"))
    )
    (comp (ref "R345")
      (value "RC1206FR-07100RL")
      (footprint "RC1206N_YAG")
      (description "No Description Available")
      (fields (field (name "COPYRIGHT") "Copyright (C) 2022 Ultra Librarian. All rights reserved."))
      (libsource (lib "RC1206FR-07100RL") (part "RC1206FR-07100RL"))
    )
    (comp (ref "R346")
      (value "RC1206FR-07100RL")
      (footprint "RC1206N_YAG")
      (description "No Description Available")
      (fields (field (name "COPYRIGHT") "Copyright (C) 2022 Ultra Librarian. All rights reserved."))
      (libsource (lib "RC1206FR-07100RL") (part "RC1206FR-07100RL"))
    )
    (comp (ref "R347")
      (value "RC1206FR-07100RL")
      (footprint "RC1206N_YAG")
      (description "No Description Available")
      (fields (field (name "COPYRIGHT") "Copyright (C) 2022 Ultra Librarian. All rights reserved."))
      (libsource (lib "RC1206FR-07100RL") (part "RC1206FR-07100RL"))
    )
    (comp (ref "R348")
      (value "RC1206FR-07100RL")
      (footprint "RC1206N_YAG")
      (description "No Description Available")
      (fields (field (name "COPYRIGHT") "Copyright (C) 2022 Ultra Librarian. All rights reserved."))
      (libsource (lib "RC1206FR-07100RL") (part "RC1206FR-07100RL"))
    )
    (comp (ref "R349")
      (value "RC1206FR-07100RL")
      (footprint "RC1206N_YAG")
      (description "No Description Available")
      (fields (field (name "COPYRIGHT") "Copyright (C) 2022 Ultra Librarian. All rights reserved."))
      (libsource (lib "RC1206FR-07100RL") (part "RC1206FR-07100RL"))
    )
    (comp (ref "R350")
      (value "RC1206FR-07100RL")
      (footprint "RC1206N_YAG")
      (description "No Description Available")
      (fields (field (name "COPYRIGHT") "Copyright (C) 2022 Ultra Librarian. All rights reserved."))
      (libsource (lib "RC1206FR-07100RL") (part "RC1206FR-07100RL"))
    )
    (comp (ref "R351")
      (value "RC1206FR-07100RL")
      (footprint "RC1206N_YAG")
      (description "No Description Available")
      (fields (field (name "COPYRIGHT") "Copyright (C) 2022 Ultra Librarian. All rights reserved."))
      (libsource (lib "RC1206FR-07100RL") (part "RC1206FR-07100RL"))
    )
    (comp (ref "R352")
      (value "RC1206FR-07100RL")
      (footprint "RC1206N_YAG")
      (description "No Description Available")
      (fields (field (name "COPYRIGHT") "Copyright (C) 2022 Ultra Librarian. All rights reserved."))
      (libsource (lib "RC1206FR-07100RL") (part "RC1206FR-07100RL"))
    )
    (comp (ref "R353")
      (value "RC1206FR-07100RL")
      (footprint "RC1206N_YAG")
      (description "No Description Available")
      (fields (field (name "COPYRIGHT") "Copyright (C) 2022 Ultra Librarian. All rights reserved."))
      (libsource (lib "RC1206FR-07100RL") (part "RC1206FR-07100RL"))
    )
    (comp (ref "R354")
      (value "RC1206FR-07100RL")
      (footprint "RC1206N_YAG")
      (description "No Description Available")
      (fields (field (name "COPYRIGHT") "Copyright (C) 2022 Ultra Librarian. All rights reserved."))
      (libsource (lib "RC1206FR-07100RL") (part "RC1206FR-07100RL"))
    )
    (comp (ref "R355")
      (value "RC1206FR-07100RL")
      (footprint "RC1206N_YAG")
      (description "No Description Available")
      (fields (field (name "COPYRIGHT") "Copyright (C) 2022 Ultra Librarian. All rights reserved."))
      (libsource (lib "RC1206FR-07100RL") (part "RC1206FR-07100RL"))
    )
    (comp (ref "R356")
      (value "RC1206FR-07100RL")
      (footprint "RC1206N_YAG")
      (description "No Description Available")
      (fields (field (name "COPYRIGHT") "Copyright (C) 2022 Ultra Librarian. All rights reserved."))
      (libsource (lib "RC1206FR-07100RL") (part "RC1206FR-07100RL"))
    )
    (comp (ref "R357")
      (value "RC1206FR-07100RL")
      (footprint "RC1206N_YAG")
      (description "No Description Available")
      (fields (field (name "COPYRIGHT") "Copyright (C) 2022 Ultra Librarian. All rights reserved."))
      (libsource (lib "RC1206FR-07100RL") (part "RC1206FR-07100RL"))
    )
    (comp (ref "R358")
      (value "RC1206FR-07100RL")
      (footprint "RC1206N_YAG")
      (description "No Description Available")
      (fields (field (name "COPYRIGHT") "Copyright (C) 2022 Ultra Librarian. All rights reserved."))
      (libsource (lib "RC1206FR-07100RL") (part "RC1206FR-07100RL"))
    )
    (comp (ref "R359")
      (value "RC1206FR-07100RL")
      (footprint "RC1206N_YAG")
      (description "No Description Available")
      (fields (field (name "COPYRIGHT") "Copyright (C) 2022 Ultra Librarian. All rights reserved."))
      (libsource (lib "RC1206FR-07100RL") (part "RC1206FR-07100RL"))
    )
    (comp (ref "R360")
      (value "RC1206FR-07100RL")
      (footprint "RC1206N_YAG")
      (description "No Description Available")
      (fields (field (name "COPYRIGHT") "Copyright (C) 2022 Ultra Librarian. All rights reserved."))
      (libsource (lib "RC1206FR-07100RL") (part "RC1206FR-07100RL"))
    )
    (comp (ref "R361")
      (value "RC1206FR-07100RL")
      (footprint "RC1206N_YAG")
      (description "No Description Available")
      (fields (field (name "COPYRIGHT") "Copyright (C) 2022 Ultra Librarian. All rights reserved."))
      (libsource (lib "RC1206FR-07100RL") (part "RC1206FR-07100RL"))
    )
    (comp (ref "R362")
      (value "RC1206FR-07100RL")
      (footprint "RC1206N_YAG")
      (description "No Description Available")
      (fields (field (name "COPYRIGHT") "Copyright (C) 2022 Ultra Librarian. All rights reserved."))
      (libsource (lib "RC1206FR-07100RL") (part "RC1206FR-07100RL"))
    )
    (comp (ref "R363")
      (value "RC1206FR-07100RL")
      (footprint "RC1206N_YAG")
      (description "No Description Available")
      (fields (field (name "COPYRIGHT") "Copyright (C) 2022 Ultra Librarian. All rights reserved."))
      (libsource (lib "RC1206FR-07100RL") (part "RC1206FR-07100RL"))
    )
    (comp (ref "R364")
      (value "RC1206FR-07100RL")
      (footprint "RC1206N_YAG")
      (description "No Description Available")
      (fields (field (name "COPYRIGHT") "Copyright (C) 2022 Ultra Librarian. All rights reserved."))
      (libsource (lib "RC1206FR-07100RL") (part "RC1206FR-07100RL"))
    )
    (comp (ref "R365")
      (value "RC1206FR-07100RL")
      (footprint "RC1206N_YAG")
      (description "No Description Available")
      (fields (field (name "COPYRIGHT") "Copyright (C) 2022 Ultra Librarian. All rights reserved."))
      (libsource (lib "RC1206FR-07100RL") (part "RC1206FR-07100RL"))
    )
    (comp (ref "R366")
      (value "RC1206FR-07100RL")
      (footprint "RC1206N_YAG")
      (description "No Description Available")
      (fields (field (name "COPYRIGHT") "Copyright (C) 2022 Ultra Librarian. All rights reserved."))
      (libsource (lib "RC1206FR-07100RL") (part "RC1206FR-07100RL"))
    )
    (comp (ref "R367")
      (value "RC1206FR-07100RL")
      (footprint "RC1206N_YAG")
      (description "No Description Available")
      (fields (field (name "COPYRIGHT") "Copyright (C) 2022 Ultra Librarian. All rights reserved."))
      (libsource (lib "RC1206FR-07100RL") (part "RC1206FR-07100RL"))
    )
    (comp (ref "R368")
      (value "RC1206FR-07100RL")
      (footprint "RC1206N_YAG")
      (description "No Description Available")
      (fields (field (name "COPYRIGHT") "Copyright (C) 2022 Ultra Librarian. All rights reserved."))
      (libsource (lib "RC1206FR-07100RL") (part "RC1206FR-07100RL"))
    )
    (comp (ref "R369")
      (value "RC1206FR-07100RL")
      (footprint "RC1206N_YAG")
      (description "No Description Available")
      (fields (field (name "COPYRIGHT") "Copyright (C) 2022 Ultra Librarian. All rights reserved."))
      (libsource (lib "RC1206FR-07100RL") (part "RC1206FR-07100RL"))
    )
    (comp (ref "R370")
      (value "RC1206FR-07100RL")
      (footprint "RC1206N_YAG")
      (description "No Description Available")
      (fields (field (name "COPYRIGHT") "Copyright (C) 2022 Ultra Librarian. All rights reserved."))
      (libsource (lib "RC1206FR-07100RL") (part "RC1206FR-07100RL"))
    )
    (comp (ref "R371")
      (value "RC1206FR-07100RL")
      (footprint "RC1206N_YAG")
      (description "No Description Available")
      (fields (field (name "COPYRIGHT") "Copyright (C) 2022 Ultra Librarian. All rights reserved."))
      (libsource (lib "RC1206FR-07100RL") (part "RC1206FR-07100RL"))
    )
    (comp (ref "R372")
      (value "RC1206FR-07100RL")
      (footprint "RC1206N_YAG")
      (description "No Description Available")
      (fields (field (name "COPYRIGHT") "Copyright (C) 2022 Ultra Librarian. All rights reserved."))
      (libsource (lib "RC1206FR-07100RL") (part "RC1206FR-07100RL"))
    )
    (comp (ref "R373")
      (value "RC1206FR-07100RL")
      (footprint "RC1206N_YAG")
      (description "No Description Available")
      (fields (field (name "COPYRIGHT") "Copyright (C) 2022 Ultra Librarian. All rights reserved."))
      (libsource (lib "RC1206FR-07100RL") (part "RC1206FR-07100RL"))
    )
    (comp (ref "R374")
      (value "RC1206FR-07100RL")
      (footprint "RC1206N_YAG")
      (description "No Description Available")
      (fields (field (name "COPYRIGHT") "Copyright (C) 2022 Ultra Librarian. All rights reserved."))
      (libsource (lib "RC1206FR-07100RL") (part "RC1206FR-07100RL"))
    )
    (comp (ref "R375")
      (value "RC1206FR-07100RL")
      (footprint "RC1206N_YAG")
      (description "No Description Available")
      (fields (field (name "COPYRIGHT") "Copyright (C) 2022 Ultra Librarian. All rights reserved."))
      (libsource (lib "RC1206FR-07100RL") (part "RC1206FR-07100RL"))
    )
    (comp (ref "R376")
      (value "RC1206FR-07100RL")
      (footprint "RC1206N_YAG")
      (description "No Description Available")
      (fields (field (name "COPYRIGHT") "Copyright (C) 2022 Ultra Librarian. All rights reserved."))
      (libsource (lib "RC1206FR-07100RL") (part "RC1206FR-07100RL"))
    )
    (comp (ref "R377")
      (value "RC1206FR-07100RL")
      (footprint "RC1206N_YAG")
      (description "No Description Available")
      (fields (field (name "COPYRIGHT") "Copyright (C) 2022 Ultra Librarian. All rights reserved."))
      (libsource (lib "RC1206FR-07100RL") (part "RC1206FR-07100RL"))
    )
    (comp (ref "R378")
      (value "RC1206FR-07100RL")
      (footprint "RC1206N_YAG")
      (description "No Description Available")
      (fields (field (name "COPYRIGHT") "Copyright (C) 2022 Ultra Librarian. All rights reserved."))
      (libsource (lib "RC1206FR-07100RL") (part "RC1206FR-07100RL"))
    )
    (comp (ref "R379")
      (value "RC1206FR-07100RL")
      (footprint "RC1206N_YAG")
      (description "No Description Available")
      (fields (field (name "COPYRIGHT") "Copyright (C) 2022 Ultra Librarian. All rights reserved."))
      (libsource (lib "RC1206FR-07100RL") (part "RC1206FR-07100RL"))
    )
    (comp (ref "R380")
      (value "RC1206FR-07100RL")
      (footprint "RC1206N_YAG")
      (description "No Description Available")
      (fields (field (name "COPYRIGHT") "Copyright (C) 2022 Ultra Librarian. All rights reserved."))
      (libsource (lib "RC1206FR-07100RL") (part "RC1206FR-07100RL"))
    )
    (comp (ref "R381")
      (value "RC1206FR-07100RL")
      (footprint "RC1206N_YAG")
      (description "No Description Available")
      (fields (field (name "COPYRIGHT") "Copyright (C) 2022 Ultra Librarian. All rights reserved."))
      (libsource (lib "RC1206FR-07100RL") (part "RC1206FR-07100RL"))
    )
    (comp (ref "R382")
      (value "RC1206FR-07100RL")
      (footprint "RC1206N_YAG")
      (description "No Description Available")
      (fields (field (name "COPYRIGHT") "Copyright (C) 2022 Ultra Librarian. All rights reserved."))
      (libsource (lib "RC1206FR-07100RL") (part "RC1206FR-07100RL"))
    )
    (comp (ref "R383")
      (value "RC1206FR-07100RL")
      (footprint "RC1206N_YAG")
      (description "No Description Available")
      (fields (field (name "COPYRIGHT") "Copyright (C) 2022 Ultra Librarian. All rights reserved."))
      (libsource (lib "RC1206FR-07100RL") (part "RC1206FR-07100RL"))
    )
    (comp (ref "R384")
      (value "RC1206FR-07100RL")
      (footprint "RC1206N_YAG")
      (description "No Description Available")
      (fields (field (name "COPYRIGHT") "Copyright (C) 2022 Ultra Librarian. All rights reserved."))
      (libsource (lib "RC1206FR-07100RL") (part "RC1206FR-07100RL"))
    )
    (comp (ref "R385")
      (value "RC1206FR-07100RL")
      (footprint "RC1206N_YAG")
      (description "No Description Available")
      (fields (field (name "COPYRIGHT") "Copyright (C) 2022 Ultra Librarian. All rights reserved."))
      (libsource (lib "RC1206FR-07100RL") (part "RC1206FR-07100RL"))
    )
    (comp (ref "R386")
      (value "RC1206FR-07100RL")
      (footprint "RC1206N_YAG")
      (description "No Description Available")
      (fields (field (name "COPYRIGHT") "Copyright (C) 2022 Ultra Librarian. All rights reserved."))
      (libsource (lib "RC1206FR-07100RL") (part "RC1206FR-07100RL"))
    )
    (comp (ref "R387")
      (value "RC1206FR-07100RL")
      (footprint "RC1206N_YAG")
      (description "No Description Available")
      (fields (field (name "COPYRIGHT") "Copyright (C) 2022 Ultra Librarian. All rights reserved."))
      (libsource (lib "RC1206FR-07100RL") (part "RC1206FR-07100RL"))
    )
    (comp (ref "R388")
      (value "RC1206FR-07100RL")
      (footprint "RC1206N_YAG")
      (description "No Description Available")
      (fields (field (name "COPYRIGHT") "Copyright (C) 2022 Ultra Librarian. All rights reserved."))
      (libsource (lib "RC1206FR-07100RL") (part "RC1206FR-07100RL"))
    )
    (comp (ref "R389")
      (value "RC1206FR-07100RL")
      (footprint "RC1206N_YAG")
      (description "No Description Available")
      (fields (field (name "COPYRIGHT") "Copyright (C) 2022 Ultra Librarian. All rights reserved."))
      (libsource (lib "RC1206FR-07100RL") (part "RC1206FR-07100RL"))
    )
    (comp (ref "R390")
      (value "RC1206FR-07100RL")
      (footprint "RC1206N_YAG")
      (description "No Description Available")
      (fields (field (name "COPYRIGHT") "Copyright (C) 2022 Ultra Librarian. All rights reserved."))
      (libsource (lib "RC1206FR-07100RL") (part "RC1206FR-07100RL"))
    )
    (comp (ref "R391")
      (value "RC1206FR-07100RL")
      (footprint "RC1206N_YAG")
      (description "No Description Available")
      (fields (field (name "COPYRIGHT") "Copyright (C) 2022 Ultra Librarian. All rights reserved."))
      (libsource (lib "RC1206FR-07100RL") (part "RC1206FR-07100RL"))
    )
    (comp (ref "R392")
      (value "RC1206FR-07100RL")
      (footprint "RC1206N_YAG")
      (description "No Description Available")
      (fields (field (name "COPYRIGHT") "Copyright (C) 2022 Ultra Librarian. All rights reserved."))
      (libsource (lib "RC1206FR-07100RL") (part "RC1206FR-07100RL"))
    )
    (comp (ref "R393")
      (value "RC1206FR-07100RL")
      (footprint "RC1206N_YAG")
      (description "No Description Available")
      (fields (field (name "COPYRIGHT") "Copyright (C) 2022 Ultra Librarian. All rights reserved."))
      (libsource (lib "RC1206FR-07100RL") (part "RC1206FR-07100RL"))
    )
    (comp (ref "R394")
      (value "RC1206FR-07100RL")
      (footprint "RC1206N_YAG")
      (description "No Description Available")
      (fields (field (name "COPYRIGHT") "Copyright (C) 2022 Ultra Librarian. All rights reserved."))
      (libsource (lib "RC1206FR-07100RL") (part "RC1206FR-07100RL"))
    )
    (comp (ref "R395")
      (value "RC1206FR-07100RL")
      (footprint "RC1206N_YAG")
      (description "No Description Available")
      (fields (field (name "COPYRIGHT") "Copyright (C) 2022 Ultra Librarian. All rights reserved."))
      (libsource (lib "RC1206FR-07100RL") (part "RC1206FR-07100RL"))
    )
    (comp (ref "R396")
      (value "RC1206FR-07100RL")
      (footprint "RC1206N_YAG")
      (description "No Description Available")
      (fields (field (name "COPYRIGHT") "Copyright (C) 2022 Ultra Librarian. All rights reserved."))
      (libsource (lib "RC1206FR-07100RL") (part "RC1206FR-07100RL"))
    )
    (comp (ref "R397")
      (value "RC1206FR-07100RL")
      (footprint "RC1206N_YAG")
      (description "No Description Available")
      (fields (field (name "COPYRIGHT") "Copyright (C) 2022 Ultra Librarian. All rights reserved."))
      (libsource (lib "RC1206FR-07100RL") (part "RC1206FR-07100RL"))
    )
    (comp (ref "R398")
      (value "RC1206FR-07100RL")
      (footprint "RC1206N_YAG")
      (description "No Description Available")
      (fields (field (name "COPYRIGHT") "Copyright (C) 2022 Ultra Librarian. All rights reserved."))
      (libsource (lib "RC1206FR-07100RL") (part "RC1206FR-07100RL"))
    )
    (comp (ref "R399")
      (value "RC1206FR-07100RL")
      (footprint "RC1206N_YAG")
      (description "No Description Available")
      (fields (field (name "COPYRIGHT") "Copyright (C) 2022 Ultra Librarian. All rights reserved."))
      (libsource (lib "RC1206FR-07100RL") (part "RC1206FR-07100RL"))
    )
    (comp (ref "R400")
      (value "RC1206FR-07100RL")
      (footprint "RC1206N_YAG")
      (description "No Description Available")
      (fields (field (name "COPYRIGHT") "Copyright (C) 2022 Ultra Librarian. All rights reserved."))
      (libsource (lib "RC1206FR-07100RL") (part "RC1206FR-07100RL"))
    )
    (comp (ref "R401")
      (value "RC1206FR-07100RL")
      (footprint "RC1206N_YAG")
      (description "No Description Available")
      (fields (field (name "COPYRIGHT") "Copyright (C) 2022 Ultra Librarian. All rights reserved."))
      (libsource (lib "RC1206FR-07100RL") (part "RC1206FR-07100RL"))
    )
    (comp (ref "R402")
      (value "RC1206FR-07100RL")
      (footprint "RC1206N_YAG")
      (description "No Description Available")
      (fields (field (name "COPYRIGHT") "Copyright (C) 2022 Ultra Librarian. All rights reserved."))
      (libsource (lib "RC1206FR-07100RL") (part "RC1206FR-07100RL"))
    )
    (comp (ref "R403")
      (value "RC1206FR-07100RL")
      (footprint "RC1206N_YAG")
      (description "No Description Available")
      (fields (field (name "COPYRIGHT") "Copyright (C) 2022 Ultra Librarian. All rights reserved."))
      (libsource (lib "RC1206FR-07100RL") (part "RC1206FR-07100RL"))
    )
    (comp (ref "R404")
      (value "RC1206FR-07100RL")
      (footprint "RC1206N_YAG")
      (description "No Description Available")
      (fields (field (name "COPYRIGHT") "Copyright (C) 2022 Ultra Librarian. All rights reserved."))
      (libsource (lib "RC1206FR-07100RL") (part "RC1206FR-07100RL"))
    )
    (comp (ref "R405")
      (value "RC1206FR-07100RL")
      (footprint "RC1206N_YAG")
      (description "No Description Available")
      (fields (field (name "COPYRIGHT") "Copyright (C) 2022 Ultra Librarian. All rights reserved."))
      (libsource (lib "RC1206FR-07100RL") (part "RC1206FR-07100RL"))
    )
    (comp (ref "R406")
      (value "RC1206FR-07100RL")
      (footprint "RC1206N_YAG")
      (description "No Description Available")
      (fields (field (name "COPYRIGHT") "Copyright (C) 2022 Ultra Librarian. All rights reserved."))
      (libsource (lib "RC1206FR-07100RL") (part "RC1206FR-07100RL"))
    )
    (comp (ref "R407")
      (value "RC1206FR-07100RL")
      (footprint "RC1206N_YAG")
      (description "No Description Available")
      (fields (field (name "COPYRIGHT") "Copyright (C) 2022 Ultra Librarian. All rights reserved."))
      (libsource (lib "RC1206FR-07100RL") (part "RC1206FR-07100RL"))
    )
    (comp (ref "R408")
      (value "RC1206FR-07100RL")
      (footprint "RC1206N_YAG")
      (description "No Description Available")
      (fields (field (name "COPYRIGHT") "Copyright (C) 2022 Ultra Librarian. All rights reserved."))
      (libsource (lib "RC1206FR-07100RL") (part "RC1206FR-07100RL"))
    )
    (comp (ref "R409")
      (value "RC1206FR-07100RL")
      (footprint "RC1206N_YAG")
      (description "No Description Available")
      (fields (field (name "COPYRIGHT") "Copyright (C) 2022 Ultra Librarian. All rights reserved."))
      (libsource (lib "RC1206FR-07100RL") (part "RC1206FR-07100RL"))
    )
    (comp (ref "R410")
      (value "RC1206FR-07100RL")
      (footprint "RC1206N_YAG")
      (description "No Description Available")
      (fields (field (name "COPYRIGHT") "Copyright (C) 2022 Ultra Librarian. All rights reserved."))
      (libsource (lib "RC1206FR-07100RL") (part "RC1206FR-07100RL"))
    )
    (comp (ref "R411")
      (value "RC1206FR-07100RL")
      (footprint "RC1206N_YAG")
      (description "No Description Available")
      (fields (field (name "COPYRIGHT") "Copyright (C) 2022 Ultra Librarian. All rights reserved."))
      (libsource (lib "RC1206FR-07100RL") (part "RC1206FR-07100RL"))
    )
    (comp (ref "R412")
      (value "RC1206FR-07100RL")
      (footprint "RC1206N_YAG")
      (description "No Description Available")
      (fields (field (name "COPYRIGHT") "Copyright (C) 2022 Ultra Librarian. All rights reserved."))
      (libsource (lib "RC1206FR-07100RL") (part "RC1206FR-07100RL"))
    )
    (comp (ref "R413")
      (value "RC1206FR-07100RL")
      (footprint "RC1206N_YAG")
      (description "No Description Available")
      (fields (field (name "COPYRIGHT") "Copyright (C) 2022 Ultra Librarian. All rights reserved."))
      (libsource (lib "RC1206FR-07100RL") (part "RC1206FR-07100RL"))
    )
    (comp (ref "R414")
      (value "RC1206FR-07100RL")
      (footprint "RC1206N_YAG")
      (description "No Description Available")
      (fields (field (name "COPYRIGHT") "Copyright (C) 2022 Ultra Librarian. All rights reserved."))
      (libsource (lib "RC1206FR-07100RL") (part "RC1206FR-07100RL"))
    )
    (comp (ref "R415")
      (value "RC1206FR-07100RL")
      (footprint "RC1206N_YAG")
      (description "No Description Available")
      (fields (field (name "COPYRIGHT") "Copyright (C) 2022 Ultra Librarian. All rights reserved."))
      (libsource (lib "RC1206FR-07100RL") (part "RC1206FR-07100RL"))
    )
    (comp (ref "R416")
      (value "RC1206FR-07100RL")
      (footprint "RC1206N_YAG")
      (description "No Description Available")
      (fields (field (name "COPYRIGHT") "Copyright (C) 2022 Ultra Librarian. All rights reserved."))
      (libsource (lib "RC1206FR-07100RL") (part "RC1206FR-07100RL"))
    )
    (comp (ref "R417")
      (value "RC1206FR-07100RL")
      (footprint "RC1206N_YAG")
      (description "No Description Available")
      (fields (field (name "COPYRIGHT") "Copyright (C) 2022 Ultra Librarian. All rights reserved."))
      (libsource (lib "RC1206FR-07100RL") (part "RC1206FR-07100RL"))
    )
    (comp (ref "R418")
      (value "RC1206FR-07100RL")
      (footprint "RC1206N_YAG")
      (description "No Description Available")
      (fields (field (name "COPYRIGHT") "Copyright (C) 2022 Ultra Librarian. All rights reserved."))
      (libsource (lib "RC1206FR-07100RL") (part "RC1206FR-07100RL"))
    )
    (comp (ref "R419")
      (value "RC1206FR-07100RL")
      (footprint "RC1206N_YAG")
      (description "No Description Available")
      (fields (field (name "COPYRIGHT") "Copyright (C) 2022 Ultra Librarian. All rights reserved."))
      (libsource (lib "RC1206FR-07100RL") (part "RC1206FR-07100RL"))
    )
    (comp (ref "R420")
      (value "RC1206FR-07100RL")
      (footprint "RC1206N_YAG")
      (description "No Description Available")
      (fields (field (name "COPYRIGHT") "Copyright (C) 2022 Ultra Librarian. All rights reserved."))
      (libsource (lib "RC1206FR-07100RL") (part "RC1206FR-07100RL"))
    )
    (comp (ref "R421")
      (value "RC1206FR-07100RL")
      (footprint "RC1206N_YAG")
      (description "No Description Available")
      (fields (field (name "COPYRIGHT") "Copyright (C) 2022 Ultra Librarian. All rights reserved."))
      (libsource (lib "RC1206FR-07100RL") (part "RC1206FR-07100RL"))
    )
    (comp (ref "R422")
      (value "RC1206FR-07100RL")
      (footprint "RC1206N_YAG")
      (description "No Description Available")
      (fields (field (name "COPYRIGHT") "Copyright (C) 2022 Ultra Librarian. All rights reserved."))
      (libsource (lib "RC1206FR-07100RL") (part "RC1206FR-07100RL"))
    )
    (comp (ref "R423")
      (value "RC1206FR-07100RL")
      (footprint "RC1206N_YAG")
      (description "No Description Available")
      (fields (field (name "COPYRIGHT") "Copyright (C) 2022 Ultra Librarian. All rights reserved."))
      (libsource (lib "RC1206FR-07100RL") (part "RC1206FR-07100RL"))
    )
    (comp (ref "R424")
      (value "RC1206FR-07100RL")
      (footprint "RC1206N_YAG")
      (description "No Description Available")
      (fields (field (name "COPYRIGHT") "Copyright (C) 2022 Ultra Librarian. All rights reserved."))
      (libsource (lib "RC1206FR-07100RL") (part "RC1206FR-07100RL"))
    )
    (comp (ref "R425")
      (value "RC1206FR-07100RL")
      (footprint "RC1206N_YAG")
      (description "No Description Available")
      (fields (field (name "COPYRIGHT") "Copyright (C) 2022 Ultra Librarian. All rights reserved."))
      (libsource (lib "RC1206FR-07100RL") (part "RC1206FR-07100RL"))
    )
    (comp (ref "R426")
      (value "RC1206FR-07100RL")
      (footprint "RC1206N_YAG")
      (description "No Description Available")
      (fields (field (name "COPYRIGHT") "Copyright (C) 2022 Ultra Librarian. All rights reserved."))
      (libsource (lib "RC1206FR-07100RL") (part "RC1206FR-07100RL"))
    )
    (comp (ref "R427")
      (value "RC1206FR-07100RL")
      (footprint "RC1206N_YAG")
      (description "No Description Available")
      (fields (field (name "COPYRIGHT") "Copyright (C) 2022 Ultra Librarian. All rights reserved."))
      (libsource (lib "RC1206FR-07100RL") (part "RC1206FR-07100RL"))
    )
    (comp (ref "R428")
      (value "RC1206FR-07100RL")
      (footprint "RC1206N_YAG")
      (description "No Description Available")
      (fields (field (name "COPYRIGHT") "Copyright (C) 2022 Ultra Librarian. All rights reserved."))
      (libsource (lib "RC1206FR-07100RL") (part "RC1206FR-07100RL"))
    )
    (comp (ref "R429")
      (value "RC1206FR-07100RL")
      (footprint "RC1206N_YAG")
      (description "No Description Available")
      (fields (field (name "COPYRIGHT") "Copyright (C) 2022 Ultra Librarian. All rights reserved."))
      (libsource (lib "RC1206FR-07100RL") (part "RC1206FR-07100RL"))
    )
    (comp (ref "R430")
      (value "RC1206FR-07100RL")
      (footprint "RC1206N_YAG")
      (description "No Description Available")
      (fields (field (name "COPYRIGHT") "Copyright (C) 2022 Ultra Librarian. All rights reserved."))
      (libsource (lib "RC1206FR-07100RL") (part "RC1206FR-07100RL"))
    )
    (comp (ref "R431")
      (value "RC1206FR-07100RL")
      (footprint "RC1206N_YAG")
      (description "No Description Available")
      (fields (field (name "COPYRIGHT") "Copyright (C) 2022 Ultra Librarian. All rights reserved."))
      (libsource (lib "RC1206FR-07100RL") (part "RC1206FR-07100RL"))
    )
    (comp (ref "R432")
      (value "RC1206FR-07100RL")
      (footprint "RC1206N_YAG")
      (description "No Description Available")
      (fields (field (name "COPYRIGHT") "Copyright (C) 2022 Ultra Librarian. All rights reserved."))
      (libsource (lib "RC1206FR-07100RL") (part "RC1206FR-07100RL"))
    )
    (comp (ref "R433")
      (value "RC1206FR-07100RL")
      (footprint "RC1206N_YAG")
      (description "No Description Available")
      (fields (field (name "COPYRIGHT") "Copyright (C) 2022 Ultra Librarian. All rights reserved."))
      (libsource (lib "RC1206FR-07100RL") (part "RC1206FR-07100RL"))
    )
    (comp (ref "R434")
      (value "RC1206FR-07100RL")
      (footprint "RC1206N_YAG")
      (description "No Description Available")
      (fields (field (name "COPYRIGHT") "Copyright (C) 2022 Ultra Librarian. All rights reserved."))
      (libsource (lib "RC1206FR-07100RL") (part "RC1206FR-07100RL"))
    )
    (comp (ref "R435")
      (value "RC1206FR-07100RL")
      (footprint "RC1206N_YAG")
      (description "No Description Available")
      (fields (field (name "COPYRIGHT") "Copyright (C) 2022 Ultra Librarian. All rights reserved."))
      (libsource (lib "RC1206FR-07100RL") (part "RC1206FR-07100RL"))
    )
    (comp (ref "R436")
      (value "RC1206FR-07100RL")
      (footprint "RC1206N_YAG")
      (description "No Description Available")
      (fields (field (name "COPYRIGHT") "Copyright (C) 2022 Ultra Librarian. All rights reserved."))
      (libsource (lib "RC1206FR-07100RL") (part "RC1206FR-07100RL"))
    )
    (comp (ref "R437")
      (value "RC1206FR-07100RL")
      (footprint "RC1206N_YAG")
      (description "No Description Available")
      (fields (field (name "COPYRIGHT") "Copyright (C) 2022 Ultra Librarian. All rights reserved."))
      (libsource (lib "RC1206FR-07100RL") (part "RC1206FR-07100RL"))
    )
    (comp (ref "R438")
      (value "RC1206FR-07100RL")
      (footprint "RC1206N_YAG")
      (description "No Description Available")
      (fields (field (name "COPYRIGHT") "Copyright (C) 2022 Ultra Librarian. All rights reserved."))
      (libsource (lib "RC1206FR-07100RL") (part "RC1206FR-07100RL"))
    )
    (comp (ref "R439")
      (value "RC1206FR-07100RL")
      (footprint "RC1206N_YAG")
      (description "No Description Available")
      (fields (field (name "COPYRIGHT") "Copyright (C) 2022 Ultra Librarian. All rights reserved."))
      (libsource (lib "RC1206FR-07100RL") (part "RC1206FR-07100RL"))
    )
    (comp (ref "R440")
      (value "RC1206FR-07100RL")
      (footprint "RC1206N_YAG")
      (description "No Description Available")
      (fields (field (name "COPYRIGHT") "Copyright (C) 2022 Ultra Librarian. All rights reserved."))
      (libsource (lib "RC1206FR-07100RL") (part "RC1206FR-07100RL"))
    )
    (comp (ref "R441")
      (value "RC1206FR-07100RL")
      (footprint "RC1206N_YAG")
      (description "No Description Available")
      (fields (field (name "COPYRIGHT") "Copyright (C) 2022 Ultra Librarian. All rights reserved."))
      (libsource (lib "RC1206FR-07100RL") (part "RC1206FR-07100RL"))
    )
    (comp (ref "R442")
      (value "RC1206FR-07100RL")
      (footprint "RC1206N_YAG")
      (description "No Description Available")
      (fields (field (name "COPYRIGHT") "Copyright (C) 2022 Ultra Librarian. All rights reserved."))
      (libsource (lib "RC1206FR-07100RL") (part "RC1206FR-07100RL"))
    )
    (comp (ref "R443")
      (value "RC1206FR-07100RL")
      (footprint "RC1206N_YAG")
      (description "No Description Available")
      (fields (field (name "COPYRIGHT") "Copyright (C) 2022 Ultra Librarian. All rights reserved."))
      (libsource (lib "RC1206FR-07100RL") (part "RC1206FR-07100RL"))
    )
    (comp (ref "R444")
      (value "RC1206FR-07100RL")
      (footprint "RC1206N_YAG")
      (description "No Description Available")
      (fields (field (name "COPYRIGHT") "Copyright (C) 2022 Ultra Librarian. All rights reserved."))
      (libsource (lib "RC1206FR-07100RL") (part "RC1206FR-07100RL"))
    )
    (comp (ref "R445")
      (value "RC1206FR-07100RL")
      (footprint "RC1206N_YAG")
      (description "No Description Available")
      (fields (field (name "COPYRIGHT") "Copyright (C) 2022 Ultra Librarian. All rights reserved."))
      (libsource (lib "RC1206FR-07100RL") (part "RC1206FR-07100RL"))
    )
    (comp (ref "R446")
      (value "RC1206FR-07100RL")
      (footprint "RC1206N_YAG")
      (description "No Description Available")
      (fields (field (name "COPYRIGHT") "Copyright (C) 2022 Ultra Librarian. All rights reserved."))
      (libsource (lib "RC1206FR-07100RL") (part "RC1206FR-07100RL"))
    )
    (comp (ref "R447")
      (value "RC1206FR-07100RL")
      (footprint "RC1206N_YAG")
      (description "No Description Available")
      (fields (field (name "COPYRIGHT") "Copyright (C) 2022 Ultra Librarian. All rights reserved."))
      (libsource (lib "RC1206FR-07100RL") (part "RC1206FR-07100RL"))
    )
    (comp (ref "R448")
      (value "RC1206FR-07100RL")
      (footprint "RC1206N_YAG")
      (description "No Description Available")
      (fields (field (name "COPYRIGHT") "Copyright (C) 2022 Ultra Librarian. All rights reserved."))
      (libsource (lib "RC1206FR-07100RL") (part "RC1206FR-07100RL"))
    )
    (comp (ref "R449")
      (value "RC1206FR-07100RL")
      (footprint "RC1206N_YAG")
      (description "No Description Available")
      (fields (field (name "COPYRIGHT") "Copyright (C) 2022 Ultra Librarian. All rights reserved."))
      (libsource (lib "RC1206FR-07100RL") (part "RC1206FR-07100RL"))
    )
    (comp (ref "R450")
      (value "RC1206FR-07100RL")
      (footprint "RC1206N_YAG")
      (description "No Description Available")
      (fields (field (name "COPYRIGHT") "Copyright (C) 2022 Ultra Librarian. All rights reserved."))
      (libsource (lib "RC1206FR-07100RL") (part "RC1206FR-07100RL"))
    )
    (comp (ref "R451")
      (value "RC1206FR-07100RL")
      (footprint "RC1206N_YAG")
      (description "No Description Available")
      (fields (field (name "COPYRIGHT") "Copyright (C) 2022 Ultra Librarian. All rights reserved."))
      (libsource (lib "RC1206FR-07100RL") (part "RC1206FR-07100RL"))
    )
    (comp (ref "R452")
      (value "RC1206FR-07100RL")
      (footprint "RC1206N_YAG")
      (description "No Description Available")
      (fields (field (name "COPYRIGHT") "Copyright (C) 2022 Ultra Librarian. All rights reserved."))
      (libsource (lib "RC1206FR-07100RL") (part "RC1206FR-07100RL"))
    )
    (comp (ref "R453")
      (value "RC1206FR-07100RL")
      (footprint "RC1206N_YAG")
      (description "No Description Available")
      (fields (field (name "COPYRIGHT") "Copyright (C) 2022 Ultra Librarian. All rights reserved."))
      (libsource (lib "RC1206FR-07100RL") (part "RC1206FR-07100RL"))
    )
    (comp (ref "R454")
      (value "RC1206FR-07100RL")
      (footprint "RC1206N_YAG")
      (description "No Description Available")
      (fields (field (name "COPYRIGHT") "Copyright (C) 2022 Ultra Librarian. All rights reserved."))
      (libsource (lib "RC1206FR-07100RL") (part "RC1206FR-07100RL"))
    )
    (comp (ref "R455")
      (value "RC1206FR-07100RL")
      (footprint "RC1206N_YAG")
      (description "No Description Available")
      (fields (field (name "COPYRIGHT") "Copyright (C) 2022 Ultra Librarian. All rights reserved."))
      (libsource (lib "RC1206FR-07100RL") (part "RC1206FR-07100RL"))
    )
    (comp (ref "R456")
      (value "RC1206FR-07100RL")
      (footprint "RC1206N_YAG")
      (description "No Description Available")
      (fields (field (name "COPYRIGHT") "Copyright (C) 2022 Ultra Librarian. All rights reserved."))
      (libsource (lib "RC1206FR-07100RL") (part "RC1206FR-07100RL"))
    )
    (comp (ref "R457")
      (value "RC1206FR-07100RL")
      (footprint "RC1206N_YAG")
      (description "No Description Available")
      (fields (field (name "COPYRIGHT") "Copyright (C) 2022 Ultra Librarian. All rights reserved."))
      (libsource (lib "RC1206FR-07100RL") (part "RC1206FR-07100RL"))
    )
    (comp (ref "R458")
      (value "RC1206FR-07100RL")
      (footprint "RC1206N_YAG")
      (description "No Description Available")
      (fields (field (name "COPYRIGHT") "Copyright (C) 2022 Ultra Librarian. All rights reserved."))
      (libsource (lib "RC1206FR-07100RL") (part "RC1206FR-07100RL"))
    )
    (comp (ref "R459")
      (value "RC1206FR-07100RL")
      (footprint "RC1206N_YAG")
      (description "No Description Available")
      (fields (field (name "COPYRIGHT") "Copyright (C) 2022 Ultra Librarian. All rights reserved."))
      (libsource (lib "RC1206FR-07100RL") (part "RC1206FR-07100RL"))
    )
    (comp (ref "R460")
      (value "RC1206FR-07100RL")
      (footprint "RC1206N_YAG")
      (description "No Description Available")
      (fields (field (name "COPYRIGHT") "Copyright (C) 2022 Ultra Librarian. All rights reserved."))
      (libsource (lib "RC1206FR-07100RL") (part "RC1206FR-07100RL"))
    )
    (comp (ref "R461")
      (value "RC1206FR-07100RL")
      (footprint "RC1206N_YAG")
      (description "No Description Available")
      (fields (field (name "COPYRIGHT") "Copyright (C) 2022 Ultra Librarian. All rights reserved."))
      (libsource (lib "RC1206FR-07100RL") (part "RC1206FR-07100RL"))
    )
    (comp (ref "R462")
      (value "RC1206FR-07100RL")
      (footprint "RC1206N_YAG")
      (description "No Description Available")
      (fields (field (name "COPYRIGHT") "Copyright (C) 2022 Ultra Librarian. All rights reserved."))
      (libsource (lib "RC1206FR-07100RL") (part "RC1206FR-07100RL"))
    )
    (comp (ref "R463")
      (value "RC1206FR-07100RL")
      (footprint "RC1206N_YAG")
      (description "No Description Available")
      (fields (field (name "COPYRIGHT") "Copyright (C) 2022 Ultra Librarian. All rights reserved."))
      (libsource (lib "RC1206FR-07100RL") (part "RC1206FR-07100RL"))
    )
    (comp (ref "R464")
      (value "RC1206FR-07100RL")
      (footprint "RC1206N_YAG")
      (description "No Description Available")
      (fields (field (name "COPYRIGHT") "Copyright (C) 2022 Ultra Librarian. All rights reserved."))
      (libsource (lib "RC1206FR-07100RL") (part "RC1206FR-07100RL"))
    )
    (comp (ref "R465")
      (value "RC1206FR-07100RL")
      (footprint "RC1206N_YAG")
      (description "No Description Available")
      (fields (field (name "COPYRIGHT") "Copyright (C) 2022 Ultra Librarian. All rights reserved."))
      (libsource (lib "RC1206FR-07100RL") (part "RC1206FR-07100RL"))
    )
    (comp (ref "R466")
      (value "RC1206FR-07100RL")
      (footprint "RC1206N_YAG")
      (description "No Description Available")
      (fields (field (name "COPYRIGHT") "Copyright (C) 2022 Ultra Librarian. All rights reserved."))
      (libsource (lib "RC1206FR-07100RL") (part "RC1206FR-07100RL"))
    )
    (comp (ref "R467")
      (value "RC1206FR-07100RL")
      (footprint "RC1206N_YAG")
      (description "No Description Available")
      (fields (field (name "COPYRIGHT") "Copyright (C) 2022 Ultra Librarian. All rights reserved."))
      (libsource (lib "RC1206FR-07100RL") (part "RC1206FR-07100RL"))
    )
    (comp (ref "R468")
      (value "RC1206FR-07100RL")
      (footprint "RC1206N_YAG")
      (description "No Description Available")
      (fields (field (name "COPYRIGHT") "Copyright (C) 2022 Ultra Librarian. All rights reserved."))
      (libsource (lib "RC1206FR-07100RL") (part "RC1206FR-07100RL"))
    )
    (comp (ref "R469")
      (value "RC1206FR-07100RL")
      (footprint "RC1206N_YAG")
      (description "No Description Available")
      (fields (field (name "COPYRIGHT") "Copyright (C) 2022 Ultra Librarian. All rights reserved."))
      (libsource (lib "RC1206FR-07100RL") (part "RC1206FR-07100RL"))
    )
    (comp (ref "R470")
      (value "RC1206FR-07100RL")
      (footprint "RC1206N_YAG")
      (description "No Description Available")
      (fields (field (name "COPYRIGHT") "Copyright (C) 2022 Ultra Librarian. All rights reserved."))
      (libsource (lib "RC1206FR-07100RL") (part "RC1206FR-07100RL"))
    )
    (comp (ref "R471")
      (value "RC1206FR-07100RL")
      (footprint "RC1206N_YAG")
      (description "No Description Available")
      (fields (field (name "COPYRIGHT") "Copyright (C) 2022 Ultra Librarian. All rights reserved."))
      (libsource (lib "RC1206FR-07100RL") (part "RC1206FR-07100RL"))
    )
    (comp (ref "R472")
      (value "RC1206FR-07100RL")
      (footprint "RC1206N_YAG")
      (description "No Description Available")
      (fields (field (name "COPYRIGHT") "Copyright (C) 2022 Ultra Librarian. All rights reserved."))
      (libsource (lib "RC1206FR-07100RL") (part "RC1206FR-07100RL"))
    )
    (comp (ref "R473")
      (value "RC1206FR-07100RL")
      (footprint "RC1206N_YAG")
      (description "No Description Available")
      (fields (field (name "COPYRIGHT") "Copyright (C) 2022 Ultra Librarian. All rights reserved."))
      (libsource (lib "RC1206FR-07100RL") (part "RC1206FR-07100RL"))
    )
    (comp (ref "R474")
      (value "RC1206FR-07100RL")
      (footprint "RC1206N_YAG")
      (description "No Description Available")
      (fields (field (name "COPYRIGHT") "Copyright (C) 2022 Ultra Librarian. All rights reserved."))
      (libsource (lib "RC1206FR-07100RL") (part "RC1206FR-07100RL"))
    )
    (comp (ref "R475")
      (value "RC1206FR-07100RL")
      (footprint "RC1206N_YAG")
      (description "No Description Available")
      (fields (field (name "COPYRIGHT") "Copyright (C) 2022 Ultra Librarian. All rights reserved."))
      (libsource (lib "RC1206FR-07100RL") (part "RC1206FR-07100RL"))
    )
    (comp (ref "R476")
      (value "RC1206FR-07100RL")
      (footprint "RC1206N_YAG")
      (description "No Description Available")
      (fields (field (name "COPYRIGHT") "Copyright (C) 2022 Ultra Librarian. All rights reserved."))
      (libsource (lib "RC1206FR-07100RL") (part "RC1206FR-07100RL"))
    )
    (comp (ref "R477")
      (value "RC1206FR-07100RL")
      (footprint "RC1206N_YAG")
      (description "No Description Available")
      (fields (field (name "COPYRIGHT") "Copyright (C) 2022 Ultra Librarian. All rights reserved."))
      (libsource (lib "RC1206FR-07100RL") (part "RC1206FR-07100RL"))
    )
    (comp (ref "R478")
      (value "RC1206FR-07100RL")
      (footprint "RC1206N_YAG")
      (description "No Description Available")
      (fields (field (name "COPYRIGHT") "Copyright (C) 2022 Ultra Librarian. All rights reserved."))
      (libsource (lib "RC1206FR-07100RL") (part "RC1206FR-07100RL"))
    )
    (comp (ref "R479")
      (value "RC1206FR-07100RL")
      (footprint "RC1206N_YAG")
      (description "No Description Available")
      (fields (field (name "COPYRIGHT") "Copyright (C) 2022 Ultra Librarian. All rights reserved."))
      (libsource (lib "RC1206FR-07100RL") (part "RC1206FR-07100RL"))
    )
    (comp (ref "R480")
      (value "RC1206FR-07100RL")
      (footprint "RC1206N_YAG")
      (description "No Description Available")
      (fields (field (name "COPYRIGHT") "Copyright (C) 2022 Ultra Librarian. All rights reserved."))
      (libsource (lib "RC1206FR-07100RL") (part "RC1206FR-07100RL"))
    )
    (comp (ref "R481")
      (value "RC1206FR-07100RL")
      (footprint "RC1206N_YAG")
      (description "No Description Available")
      (fields (field (name "COPYRIGHT") "Copyright (C) 2022 Ultra Librarian. All rights reserved."))
      (libsource (lib "RC1206FR-07100RL") (part "RC1206FR-07100RL"))
    )
    (comp (ref "R482")
      (value "RC1206FR-07100RL")
      (footprint "RC1206N_YAG")
      (description "No Description Available")
      (fields (field (name "COPYRIGHT") "Copyright (C) 2022 Ultra Librarian. All rights reserved."))
      (libsource (lib "RC1206FR-07100RL") (part "RC1206FR-07100RL"))
    )
    (comp (ref "R483")
      (value "RC1206FR-07100RL")
      (footprint "RC1206N_YAG")
      (description "No Description Available")
      (fields (field (name "COPYRIGHT") "Copyright (C) 2022 Ultra Librarian. All rights reserved."))
      (libsource (lib "RC1206FR-07100RL") (part "RC1206FR-07100RL"))
    )
    (comp (ref "R484")
      (value "RC1206FR-07100RL")
      (footprint "RC1206N_YAG")
      (description "No Description Available")
      (fields (field (name "COPYRIGHT") "Copyright (C) 2022 Ultra Librarian. All rights reserved."))
      (libsource (lib "RC1206FR-07100RL") (part "RC1206FR-07100RL"))
    )
    (comp (ref "R485")
      (value "RC1206FR-07100RL")
      (footprint "RC1206N_YAG")
      (description "No Description Available")
      (fields (field (name "COPYRIGHT") "Copyright (C) 2022 Ultra Librarian. All rights reserved."))
      (libsource (lib "RC1206FR-07100RL") (part "RC1206FR-07100RL"))
    )
    (comp (ref "R486")
      (value "RC1206FR-07100RL")
      (footprint "RC1206N_YAG")
      (description "No Description Available")
      (fields (field (name "COPYRIGHT") "Copyright (C) 2022 Ultra Librarian. All rights reserved."))
      (libsource (lib "RC1206FR-07100RL") (part "RC1206FR-07100RL"))
    )
    (comp (ref "R487")
      (value "RC1206FR-07100RL")
      (footprint "RC1206N_YAG")
      (description "No Description Available")
      (fields (field (name "COPYRIGHT") "Copyright (C) 2022 Ultra Librarian. All rights reserved."))
      (libsource (lib "RC1206FR-07100RL") (part "RC1206FR-07100RL"))
    )
    (comp (ref "R488")
      (value "RC1206FR-07100RL")
      (footprint "RC1206N_YAG")
      (description "No Description Available")
      (fields (field (name "COPYRIGHT") "Copyright (C) 2022 Ultra Librarian. All rights reserved."))
      (libsource (lib "RC1206FR-07100RL") (part "RC1206FR-07100RL"))
    )
    (comp (ref "R489")
      (value "RC1206FR-07100RL")
      (footprint "RC1206N_YAG")
      (description "No Description Available")
      (fields (field (name "COPYRIGHT") "Copyright (C) 2022 Ultra Librarian. All rights reserved."))
      (libsource (lib "RC1206FR-07100RL") (part "RC1206FR-07100RL"))
    )
    (comp (ref "R490")
      (value "RC1206FR-07100RL")
      (footprint "RC1206N_YAG")
      (description "No Description Available")
      (fields (field (name "COPYRIGHT") "Copyright (C) 2022 Ultra Librarian. All rights reserved."))
      (libsource (lib "RC1206FR-07100RL") (part "RC1206FR-07100RL"))
    )
    (comp (ref "R491")
      (value "RC1206FR-07100RL")
      (footprint "RC1206N_YAG")
      (description "No Description Available")
      (fields (field (name "COPYRIGHT") "Copyright (C) 2022 Ultra Librarian. All rights reserved."))
      (libsource (lib "RC1206FR-07100RL") (part "RC1206FR-07100RL"))
    )
    (comp (ref "R492")
      (value "RC1206FR-07100RL")
      (footprint "RC1206N_YAG")
      (description "No Description Available")
      (fields (field (name "COPYRIGHT") "Copyright (C) 2022 Ultra Librarian. All rights reserved."))
      (libsource (lib "RC1206FR-07100RL") (part "RC1206FR-07100RL"))
    )
    (comp (ref "R493")
      (value "RC1206FR-07100RL")
      (footprint "RC1206N_YAG")
      (description "No Description Available")
      (fields (field (name "COPYRIGHT") "Copyright (C) 2022 Ultra Librarian. All rights reserved."))
      (libsource (lib "RC1206FR-07100RL") (part "RC1206FR-07100RL"))
    )
    (comp (ref "R494")
      (value "RC1206FR-07100RL")
      (footprint "RC1206N_YAG")
      (description "No Description Available")
      (fields (field (name "COPYRIGHT") "Copyright (C) 2022 Ultra Librarian. All rights reserved."))
      (libsource (lib "RC1206FR-07100RL") (part "RC1206FR-07100RL"))
    )
    (comp (ref "R495")
      (value "RC1206FR-07100RL")
      (footprint "RC1206N_YAG")
      (description "No Description Available")
      (fields (field (name "COPYRIGHT") "Copyright (C) 2022 Ultra Librarian. All rights reserved."))
      (libsource (lib "RC1206FR-07100RL") (part "RC1206FR-07100RL"))
    )
    (comp (ref "R496")
      (value "RC1206FR-07100RL")
      (footprint "RC1206N_YAG")
      (description "No Description Available")
      (fields (field (name "COPYRIGHT") "Copyright (C) 2022 Ultra Librarian. All rights reserved."))
      (libsource (lib "RC1206FR-07100RL") (part "RC1206FR-07100RL"))
    )
    (comp (ref "R497")
      (value "RC1206FR-07100RL")
      (footprint "RC1206N_YAG")
      (description "No Description Available")
      (fields (field (name "COPYRIGHT") "Copyright (C) 2022 Ultra Librarian. All rights reserved."))
      (libsource (lib "RC1206FR-07100RL") (part "RC1206FR-07100RL"))
    )
    (comp (ref "R498")
      (value "RC1206FR-07100RL")
      (footprint "RC1206N_YAG")
      (description "No Description Available")
      (fields (field (name "COPYRIGHT") "Copyright (C) 2022 Ultra Librarian. All rights reserved."))
      (libsource (lib "RC1206FR-07100RL") (part "RC1206FR-07100RL"))
    )
    (comp (ref "R499")
      (value "RC1206FR-07100RL")
      (footprint "RC1206N_YAG")
      (description "No Description Available")
      (fields (field (name "COPYRIGHT") "Copyright (C) 2022 Ultra Librarian. All rights reserved."))
      (libsource (lib "RC1206FR-07100RL") (part "RC1206FR-07100RL"))
    )
    (comp (ref "R500")
      (value "RC1206FR-07100RL")
      (footprint "RC1206N_YAG")
      (description "No Description Available")
      (fields (field (name "COPYRIGHT") "Copyright (C) 2022 Ultra Librarian. All rights reserved."))
      (libsource (lib "RC1206FR-07100RL") (part "RC1206FR-07100RL"))
    )
    (comp (ref "R501")
      (value "RC1206FR-07100RL")
      (footprint "RC1206N_YAG")
      (description "No Description Available")
      (fields (field (name "COPYRIGHT") "Copyright (C) 2022 Ultra Librarian. All rights reserved."))
      (libsource (lib "RC1206FR-07100RL") (part "RC1206FR-07100RL"))
    )
    (comp (ref "R502")
      (value "RC1206FR-07100RL")
      (footprint "RC1206N_YAG")
      (description "No Description Available")
      (fields (field (name "COPYRIGHT") "Copyright (C) 2022 Ultra Librarian. All rights reserved."))
      (libsource (lib "RC1206FR-07100RL") (part "RC1206FR-07100RL"))
    )
    (comp (ref "R503")
      (value "RC1206FR-07100RL")
      (footprint "RC1206N_YAG")
      (description "No Description Available")
      (fields (field (name "COPYRIGHT") "Copyright (C) 2022 Ultra Librarian. All rights reserved."))
      (libsource (lib "RC1206FR-07100RL") (part "RC1206FR-07100RL"))
    )
    (comp (ref "R504")
      (value "RC1206FR-07100RL")
      (footprint "RC1206N_YAG")
      (description "No Description Available")
      (fields (field (name "COPYRIGHT") "Copyright (C) 2022 Ultra Librarian. All rights reserved."))
      (libsource (lib "RC1206FR-07100RL") (part "RC1206FR-07100RL"))
    )
    (comp (ref "R505")
      (value "RC1206FR-07100RL")
      (footprint "RC1206N_YAG")
      (description "No Description Available")
      (fields (field (name "COPYRIGHT") "Copyright (C) 2022 Ultra Librarian. All rights reserved."))
      (libsource (lib "RC1206FR-07100RL") (part "RC1206FR-07100RL"))
    )
    (comp (ref "R506")
      (value "RC1206FR-07100RL")
      (footprint "RC1206N_YAG")
      (description "No Description Available")
      (fields (field (name "COPYRIGHT") "Copyright (C) 2022 Ultra Librarian. All rights reserved."))
      (libsource (lib "RC1206FR-07100RL") (part "RC1206FR-07100RL"))
    )
    (comp (ref "R507")
      (value "RC1206FR-07100RL")
      (footprint "RC1206N_YAG")
      (description "No Description Available")
      (fields (field (name "COPYRIGHT") "Copyright (C) 2022 Ultra Librarian. All rights reserved."))
      (libsource (lib "RC1206FR-07100RL") (part "RC1206FR-07100RL"))
    )
    (comp (ref "R508")
      (value "RC1206FR-07100RL")
      (footprint "RC1206N_YAG")
      (description "No Description Available")
      (fields (field (name "COPYRIGHT") "Copyright (C) 2022 Ultra Librarian. All rights reserved."))
      (libsource (lib "RC1206FR-07100RL") (part "RC1206FR-07100RL"))
    )
    (comp (ref "R509")
      (value "RC1206FR-07100RL")
      (footprint "RC1206N_YAG")
      (description "No Description Available")
      (fields (field (name "COPYRIGHT") "Copyright (C) 2022 Ultra Librarian. All rights reserved."))
      (libsource (lib "RC1206FR-07100RL") (part "RC1206FR-07100RL"))
    )
    (comp (ref "R510")
      (value "RC1206FR-07100RL")
      (footprint "RC1206N_YAG")
      (description "No Description Available")
      (fields (field (name "COPYRIGHT") "Copyright (C) 2022 Ultra Librarian. All rights reserved."))
      (libsource (lib "RC1206FR-07100RL") (part "RC1206FR-07100RL"))
    )
    (comp (ref "R511")
      (value "RC1206FR-07100RL")
      (footprint "RC1206N_YAG")
      (description "No Description Available")
      (fields (field (name "COPYRIGHT") "Copyright (C) 2022 Ultra Librarian. All rights reserved."))
      (libsource (lib "RC1206FR-07100RL") (part "RC1206FR-07100RL"))
    )
    (comp (ref "R512")
      (value "RC1206FR-07100RL")
      (footprint "RC1206N_YAG")
      (description "No Description Available")
      (fields (field (name "COPYRIGHT") "Copyright (C) 2022 Ultra Librarian. All rights reserved."))
      (libsource (lib "RC1206FR-07100RL") (part "RC1206FR-07100RL"))
    )
    (comp (ref "R513")
      (value "RC1206FR-07100RL")
      (footprint "RC1206N_YAG")
      (description "No Description Available")
      (fields (field (name "COPYRIGHT") "Copyright (C) 2022 Ultra Librarian. All rights reserved."))
      (libsource (lib "RC1206FR-07100RL") (part "RC1206FR-07100RL"))
    )
    (comp (ref "R514")
      (value "RC1206FR-07100RL")
      (footprint "RC1206N_YAG")
      (description "No Description Available")
      (fields (field (name "COPYRIGHT") "Copyright (C) 2022 Ultra Librarian. All rights reserved."))
      (libsource (lib "RC1206FR-07100RL") (part "RC1206FR-07100RL"))
    )
    (comp (ref "R515")
      (value "RC1206FR-07100RL")
      (footprint "RC1206N_YAG")
      (description "No Description Available")
      (fields (field (name "COPYRIGHT") "Copyright (C) 2022 Ultra Librarian. All rights reserved."))
      (libsource (lib "RC1206FR-07100RL") (part "RC1206FR-07100RL"))
    )
    (comp (ref "R516")
      (value "RC1206FR-07100RL")
      (footprint "RC1206N_YAG")
      (description "No Description Available")
      (fields (field (name "COPYRIGHT") "Copyright (C) 2022 Ultra Librarian. All rights reserved."))
      (libsource (lib "RC1206FR-07100RL") (part "RC1206FR-07100RL"))
    )
    (comp (ref "R517")
      (value "RC1206FR-07100RL")
      (footprint "RC1206N_YAG")
      (description "No Description Available")
      (fields (field (name "COPYRIGHT") "Copyright (C) 2022 Ultra Librarian. All rights reserved."))
      (libsource (lib "RC1206FR-07100RL") (part "RC1206FR-07100RL"))
    )
    (comp (ref "R518")
      (value "RC1206FR-07100RL")
      (footprint "RC1206N_YAG")
      (description "No Description Available")
      (fields (field (name "COPYRIGHT") "Copyright (C) 2022 Ultra Librarian. All rights reserved."))
      (libsource (lib "RC1206FR-07100RL") (part "RC1206FR-07100RL"))
    )
    (comp (ref "R519")
      (value "RC1206FR-07100RL")
      (footprint "RC1206N_YAG")
      (description "No Description Available")
      (fields (field (name "COPYRIGHT") "Copyright (C) 2022 Ultra Librarian. All rights reserved."))
      (libsource (lib "RC1206FR-07100RL") (part "RC1206FR-07100RL"))
    )
    (comp (ref "R520")
      (value "RC1206FR-07100RL")
      (footprint "RC1206N_YAG")
      (description "No Description Available")
      (fields (field (name "COPYRIGHT") "Copyright (C) 2022 Ultra Librarian. All rights reserved."))
      (libsource (lib "RC1206FR-07100RL") (part "RC1206FR-07100RL"))
    )
    (comp (ref "R521")
      (value "RC1206FR-07100RL")
      (footprint "RC1206N_YAG")
      (description "No Description Available")
      (fields (field (name "COPYRIGHT") "Copyright (C) 2022 Ultra Librarian. All rights reserved."))
      (libsource (lib "RC1206FR-07100RL") (part "RC1206FR-07100RL"))
    )
    (comp (ref "R522")
      (value "RC1206FR-07100RL")
      (footprint "RC1206N_YAG")
      (description "No Description Available")
      (fields (field (name "COPYRIGHT") "Copyright (C) 2022 Ultra Librarian. All rights reserved."))
      (libsource (lib "RC1206FR-07100RL") (part "RC1206FR-07100RL"))
    )
    (comp (ref "R523")
      (value "RC1206FR-07100RL")
      (footprint "RC1206N_YAG")
      (description "No Description Available")
      (fields (field (name "COPYRIGHT") "Copyright (C) 2022 Ultra Librarian. All rights reserved."))
      (libsource (lib "RC1206FR-07100RL") (part "RC1206FR-07100RL"))
    )
    (comp (ref "R524")
      (value "RC1206FR-07100RL")
      (footprint "RC1206N_YAG")
      (description "No Description Available")
      (fields (field (name "COPYRIGHT") "Copyright (C) 2022 Ultra Librarian. All rights reserved."))
      (libsource (lib "RC1206FR-07100RL") (part "RC1206FR-07100RL"))
    )
    (comp (ref "R525")
      (value "RC1206FR-07100RL")
      (footprint "RC1206N_YAG")
      (description "No Description Available")
      (fields (field (name "COPYRIGHT") "Copyright (C) 2022 Ultra Librarian. All rights reserved."))
      (libsource (lib "RC1206FR-07100RL") (part "RC1206FR-07100RL"))
    )
    (comp (ref "R526")
      (value "RC1206FR-07100RL")
      (footprint "RC1206N_YAG")
      (description "No Description Available")
      (fields (field (name "COPYRIGHT") "Copyright (C) 2022 Ultra Librarian. All rights reserved."))
      (libsource (lib "RC1206FR-07100RL") (part "RC1206FR-07100RL"))
    )
    (comp (ref "R527")
      (value "RC1206FR-07100RL")
      (footprint "RC1206N_YAG")
      (description "No Description Available")
      (fields (field (name "COPYRIGHT") "Copyright (C) 2022 Ultra Librarian. All rights reserved."))
      (libsource (lib "RC1206FR-07100RL") (part "RC1206FR-07100RL"))
    )
    (comp (ref "R528")
      (value "RC1206FR-07100RL")
      (footprint "RC1206N_YAG")
      (description "No Description Available")
      (fields (field (name "COPYRIGHT") "Copyright (C) 2022 Ultra Librarian. All rights reserved."))
      (libsource (lib "RC1206FR-07100RL") (part "RC1206FR-07100RL"))
    )
    (comp (ref "R529")
      (value "RC1206FR-07100RL")
      (footprint "RC1206N_YAG")
      (description "No Description Available")
      (fields (field (name "COPYRIGHT") "Copyright (C) 2022 Ultra Librarian. All rights reserved."))
      (libsource (lib "RC1206FR-07100RL") (part "RC1206FR-07100RL"))
    )
    (comp (ref "R530")
      (value "RC1206FR-07100RL")
      (footprint "RC1206N_YAG")
      (description "No Description Available")
      (fields (field (name "COPYRIGHT") "Copyright (C) 2022 Ultra Librarian. All rights reserved."))
      (libsource (lib "RC1206FR-07100RL") (part "RC1206FR-07100RL"))
    )
    (comp (ref "R531")
      (value "RC1206FR-07100RL")
      (footprint "RC1206N_YAG")
      (description "No Description Available")
      (fields (field (name "COPYRIGHT") "Copyright (C) 2022 Ultra Librarian. All rights reserved."))
      (libsource (lib "RC1206FR-07100RL") (part "RC1206FR-07100RL"))
    )
    (comp (ref "R532")
      (value "RC1206FR-07100RL")
      (footprint "RC1206N_YAG")
      (description "No Description Available")
      (fields (field (name "COPYRIGHT") "Copyright (C) 2022 Ultra Librarian. All rights reserved."))
      (libsource (lib "RC1206FR-07100RL") (part "RC1206FR-07100RL"))
    )
    (comp (ref "R533")
      (value "RC1206FR-07100RL")
      (footprint "RC1206N_YAG")
      (description "No Description Available")
      (fields (field (name "COPYRIGHT") "Copyright (C) 2022 Ultra Librarian. All rights reserved."))
      (libsource (lib "RC1206FR-07100RL") (part "RC1206FR-07100RL"))
    )
    (comp (ref "R534")
      (value "RC1206FR-07100RL")
      (footprint "RC1206N_YAG")
      (description "No Description Available")
      (fields (field (name "COPYRIGHT") "Copyright (C) 2022 Ultra Librarian. All rights reserved."))
      (libsource (lib "RC1206FR-07100RL") (part "RC1206FR-07100RL"))
    )
    (comp (ref "R535")
      (value "RC1206FR-07100RL")
      (footprint "RC1206N_YAG")
      (description "No Description Available")
      (fields (field (name "COPYRIGHT") "Copyright (C) 2022 Ultra Librarian. All rights reserved."))
      (libsource (lib "RC1206FR-07100RL") (part "RC1206FR-07100RL"))
    )
    (comp (ref "R536")
      (value "RC1206FR-07100RL")
      (footprint "RC1206N_YAG")
      (description "No Description Available")
      (fields (field (name "COPYRIGHT") "Copyright (C) 2022 Ultra Librarian. All rights reserved."))
      (libsource (lib "RC1206FR-07100RL") (part "RC1206FR-07100RL"))
    )
    (comp (ref "R537")
      (value "RC1206FR-07100RL")
      (footprint "RC1206N_YAG")
      (description "No Description Available")
      (fields (field (name "COPYRIGHT") "Copyright (C) 2022 Ultra Librarian. All rights reserved."))
      (libsource (lib "RC1206FR-07100RL") (part "RC1206FR-07100RL"))
    )
    (comp (ref "R538")
      (value "RC1206FR-07100RL")
      (footprint "RC1206N_YAG")
      (description "No Description Available")
      (fields (field (name "COPYRIGHT") "Copyright (C) 2022 Ultra Librarian. All rights reserved."))
      (libsource (lib "RC1206FR-07100RL") (part "RC1206FR-07100RL"))
    )
    (comp (ref "R539")
      (value "RC1206FR-07100RL")
      (footprint "RC1206N_YAG")
      (description "No Description Available")
      (fields (field (name "COPYRIGHT") "Copyright (C) 2022 Ultra Librarian. All rights reserved."))
      (libsource (lib "RC1206FR-07100RL") (part "RC1206FR-07100RL"))
    )
    (comp (ref "R540")
      (value "RC1206FR-07100RL")
      (footprint "RC1206N_YAG")
      (description "No Description Available")
      (fields (field (name "COPYRIGHT") "Copyright (C) 2022 Ultra Librarian. All rights reserved."))
      (libsource (lib "RC1206FR-07100RL") (part "RC1206FR-07100RL"))
    )
    (comp (ref "R541")
      (value "RC1206FR-07100RL")
      (footprint "RC1206N_YAG")
      (description "No Description Available")
      (fields (field (name "COPYRIGHT") "Copyright (C) 2022 Ultra Librarian. All rights reserved."))
      (libsource (lib "RC1206FR-07100RL") (part "RC1206FR-07100RL"))
    )
    (comp (ref "R542")
      (value "RC1206FR-07100RL")
      (footprint "RC1206N_YAG")
      (description "No Description Available")
      (fields (field (name "COPYRIGHT") "Copyright (C) 2022 Ultra Librarian. All rights reserved."))
      (libsource (lib "RC1206FR-07100RL") (part "RC1206FR-07100RL"))
    )
    (comp (ref "R543")
      (value "RC1206FR-07100RL")
      (footprint "RC1206N_YAG")
      (description "No Description Available")
      (fields (field (name "COPYRIGHT") "Copyright (C) 2022 Ultra Librarian. All rights reserved."))
      (libsource (lib "RC1206FR-07100RL") (part "RC1206FR-07100RL"))
    )
    (comp (ref "R544")
      (value "RC1206FR-07100RL")
      (footprint "RC1206N_YAG")
      (description "No Description Available")
      (fields (field (name "COPYRIGHT") "Copyright (C) 2022 Ultra Librarian. All rights reserved."))
      (libsource (lib "RC1206FR-07100RL") (part "RC1206FR-07100RL"))
    )
    (comp (ref "R545")
      (value "RC1206FR-07100RL")
      (footprint "RC1206N_YAG")
      (description "No Description Available")
      (fields (field (name "COPYRIGHT") "Copyright (C) 2022 Ultra Librarian. All rights reserved."))
      (libsource (lib "RC1206FR-07100RL") (part "RC1206FR-07100RL"))
    )
    (comp (ref "R546")
      (value "RC1206FR-07100RL")
      (footprint "RC1206N_YAG")
      (description "No Description Available")
      (fields (field (name "COPYRIGHT") "Copyright (C) 2022 Ultra Librarian. All rights reserved."))
      (libsource (lib "RC1206FR-07100RL") (part "RC1206FR-07100RL"))
    )
    (comp (ref "R547")
      (value "RC1206FR-07100RL")
      (footprint "RC1206N_YAG")
      (description "No Description Available")
      (fields (field (name "COPYRIGHT") "Copyright (C) 2022 Ultra Librarian. All rights reserved."))
      (libsource (lib "RC1206FR-07100RL") (part "RC1206FR-07100RL"))
    )
    (comp (ref "R548")
      (value "RC1206FR-07100RL")
      (footprint "RC1206N_YAG")
      (description "No Description Available")
      (fields (field (name "COPYRIGHT") "Copyright (C) 2022 Ultra Librarian. All rights reserved."))
      (libsource (lib "RC1206FR-07100RL") (part "RC1206FR-07100RL"))
    )
    (comp (ref "R549")
      (value "RC1206FR-07100RL")
      (footprint "RC1206N_YAG")
      (description "No Description Available")
      (fields (field (name "COPYRIGHT") "Copyright (C) 2022 Ultra Librarian. All rights reserved."))
      (libsource (lib "RC1206FR-07100RL") (part "RC1206FR-07100RL"))
    )
    (comp (ref "R550")
      (value "RC1206FR-07100RL")
      (footprint "RC1206N_YAG")
      (description "No Description Available")
      (fields (field (name "COPYRIGHT") "Copyright (C) 2022 Ultra Librarian. All rights reserved."))
      (libsource (lib "RC1206FR-07100RL") (part "RC1206FR-07100RL"))
    )
    (comp (ref "R551")
      (value "RC1206FR-07100RL")
      (footprint "RC1206N_YAG")
      (description "No Description Available")
      (fields (field (name "COPYRIGHT") "Copyright (C) 2022 Ultra Librarian. All rights reserved."))
      (libsource (lib "RC1206FR-07100RL") (part "RC1206FR-07100RL"))
    )
    (comp (ref "R552")
      (value "RC1206FR-07100RL")
      (footprint "RC1206N_YAG")
      (description "No Description Available")
      (fields (field (name "COPYRIGHT") "Copyright (C) 2022 Ultra Librarian. All rights reserved."))
      (libsource (lib "RC1206FR-07100RL") (part "RC1206FR-07100RL"))
    )
    (comp (ref "R553")
      (value "RC1206FR-07100RL")
      (footprint "RC1206N_YAG")
      (description "No Description Available")
      (fields (field (name "COPYRIGHT") "Copyright (C) 2022 Ultra Librarian. All rights reserved."))
      (libsource (lib "RC1206FR-07100RL") (part "RC1206FR-07100RL"))
    )
    (comp (ref "R554")
      (value "RC1206FR-07100RL")
      (footprint "RC1206N_YAG")
      (description "No Description Available")
      (fields (field (name "COPYRIGHT") "Copyright (C) 2022 Ultra Librarian. All rights reserved."))
      (libsource (lib "RC1206FR-07100RL") (part "RC1206FR-07100RL"))
    )
    (comp (ref "R555")
      (value "RC1206FR-07100RL")
      (footprint "RC1206N_YAG")
      (description "No Description Available")
      (fields (field (name "COPYRIGHT") "Copyright (C) 2022 Ultra Librarian. All rights reserved."))
      (libsource (lib "RC1206FR-07100RL") (part "RC1206FR-07100RL"))
    )
    (comp (ref "R556")
      (value "RC1206FR-07100RL")
      (footprint "RC1206N_YAG")
      (description "No Description Available")
      (fields (field (name "COPYRIGHT") "Copyright (C) 2022 Ultra Librarian. All rights reserved."))
      (libsource (lib "RC1206FR-07100RL") (part "RC1206FR-07100RL"))
    )
    (comp (ref "R557")
      (value "RC1206FR-07100RL")
      (footprint "RC1206N_YAG")
      (description "No Description Available")
      (fields (field (name "COPYRIGHT") "Copyright (C) 2022 Ultra Librarian. All rights reserved."))
      (libsource (lib "RC1206FR-07100RL") (part "RC1206FR-07100RL"))
    )
    (comp (ref "R558")
      (value "RC1206FR-07100RL")
      (footprint "RC1206N_YAG")
      (description "No Description Available")
      (fields (field (name "COPYRIGHT") "Copyright (C) 2022 Ultra Librarian. All rights reserved."))
      (libsource (lib "RC1206FR-07100RL") (part "RC1206FR-07100RL"))
    )
    (comp (ref "R559")
      (value "RC1206FR-07100RL")
      (footprint "RC1206N_YAG")
      (description "No Description Available")
      (fields (field (name "COPYRIGHT") "Copyright (C) 2022 Ultra Librarian. All rights reserved."))
      (libsource (lib "RC1206FR-07100RL") (part "RC1206FR-07100RL"))
    )
    (comp (ref "R560")
      (value "RC1206FR-07100RL")
      (footprint "RC1206N_YAG")
      (description "No Description Available")
      (fields (field (name "COPYRIGHT") "Copyright (C) 2022 Ultra Librarian. All rights reserved."))
      (libsource (lib "RC1206FR-07100RL") (part "RC1206FR-07100RL"))
    )
    (comp (ref "R561")
      (value "RC1206FR-07100RL")
      (footprint "RC1206N_YAG")
      (description "No Description Available")
      (fields (field (name "COPYRIGHT") "Copyright (C) 2022 Ultra Librarian. All rights reserved."))
      (libsource (lib "RC1206FR-07100RL") (part "RC1206FR-07100RL"))
    )
    (comp (ref "R562")
      (value "RC1206FR-07100RL")
      (footprint "RC1206N_YAG")
      (description "No Description Available")
      (fields (field (name "COPYRIGHT") "Copyright (C) 2022 Ultra Librarian. All rights reserved."))
      (libsource (lib "RC1206FR-07100RL") (part "RC1206FR-07100RL"))
    )
    (comp (ref "R563")
      (value "RC1206FR-07100RL")
      (footprint "RC1206N_YAG")
      (description "No Description Available")
      (fields (field (name "COPYRIGHT") "Copyright (C) 2022 Ultra Librarian. All rights reserved."))
      (libsource (lib "RC1206FR-07100RL") (part "RC1206FR-07100RL"))
    )
    (comp (ref "R564")
      (value "RC1206FR-07100RL")
      (footprint "RC1206N_YAG")
      (description "No Description Available")
      (fields (field (name "COPYRIGHT") "Copyright (C) 2022 Ultra Librarian. All rights reserved."))
      (libsource (lib "RC1206FR-07100RL") (part "RC1206FR-07100RL"))
    )
    (comp (ref "R565")
      (value "RC1206FR-07100RL")
      (footprint "RC1206N_YAG")
      (description "No Description Available")
      (fields (field (name "COPYRIGHT") "Copyright (C) 2022 Ultra Librarian. All rights reserved."))
      (libsource (lib "RC1206FR-07100RL") (part "RC1206FR-07100RL"))
    )
    (comp (ref "R566")
      (value "RC1206FR-07100RL")
      (footprint "RC1206N_YAG")
      (description "No Description Available")
      (fields (field (name "COPYRIGHT") "Copyright (C) 2022 Ultra Librarian. All rights reserved."))
      (libsource (lib "RC1206FR-07100RL") (part "RC1206FR-07100RL"))
    )
    (comp (ref "R567")
      (value "RC1206FR-07100RL")
      (footprint "RC1206N_YAG")
      (description "No Description Available")
      (fields (field (name "COPYRIGHT") "Copyright (C) 2022 Ultra Librarian. All rights reserved."))
      (libsource (lib "RC1206FR-07100RL") (part "RC1206FR-07100RL"))
    )
    (comp (ref "R568")
      (value "RC1206FR-07100RL")
      (footprint "RC1206N_YAG")
      (description "No Description Available")
      (fields (field (name "COPYRIGHT") "Copyright (C) 2022 Ultra Librarian. All rights reserved."))
      (libsource (lib "RC1206FR-07100RL") (part "RC1206FR-07100RL"))
    )
    (comp (ref "R569")
      (value "RC1206FR-07100RL")
      (footprint "RC1206N_YAG")
      (description "No Description Available")
      (fields (field (name "COPYRIGHT") "Copyright (C) 2022 Ultra Librarian. All rights reserved."))
      (libsource (lib "RC1206FR-07100RL") (part "RC1206FR-07100RL"))
    )
    (comp (ref "R570")
      (value "RC1206FR-07100RL")
      (footprint "RC1206N_YAG")
      (description "No Description Available")
      (fields (field (name "COPYRIGHT") "Copyright (C) 2022 Ultra Librarian. All rights reserved."))
      (libsource (lib "RC1206FR-07100RL") (part "RC1206FR-07100RL"))
    )
    (comp (ref "R571")
      (value "RC1206FR-07100RL")
      (footprint "RC1206N_YAG")
      (description "No Description Available")
      (fields (field (name "COPYRIGHT") "Copyright (C) 2022 Ultra Librarian. All rights reserved."))
      (libsource (lib "RC1206FR-07100RL") (part "RC1206FR-07100RL"))
    )
    (comp (ref "R572")
      (value "RC1206FR-07100RL")
      (footprint "RC1206N_YAG")
      (description "No Description Available")
      (fields (field (name "COPYRIGHT") "Copyright (C) 2022 Ultra Librarian. All rights reserved."))
      (libsource (lib "RC1206FR-07100RL") (part "RC1206FR-07100RL"))
    )
    (comp (ref "R573")
      (value "RC1206FR-07100RL")
      (footprint "RC1206N_YAG")
      (description "No Description Available")
      (fields (field (name "COPYRIGHT") "Copyright (C) 2022 Ultra Librarian. All rights reserved."))
      (libsource (lib "RC1206FR-07100RL") (part "RC1206FR-07100RL"))
    )
    (comp (ref "R574")
      (value "RC1206FR-07100RL")
      (footprint "RC1206N_YAG")
      (description "No Description Available")
      (fields (field (name "COPYRIGHT") "Copyright (C) 2022 Ultra Librarian. All rights reserved."))
      (libsource (lib "RC1206FR-07100RL") (part "RC1206FR-07100RL"))
    )
    (comp (ref "R575")
      (value "RC1206FR-07100RL")
      (footprint "RC1206N_YAG")
      (description "No Description Available")
      (fields (field (name "COPYRIGHT") "Copyright (C) 2022 Ultra Librarian. All rights reserved."))
      (libsource (lib "RC1206FR-07100RL") (part "RC1206FR-07100RL"))
    )
    (comp (ref "R576")
      (value "RC1206FR-07100RL")
      (footprint "RC1206N_YAG")
      (description "No Description Available")
      (fields (field (name "COPYRIGHT") "Copyright (C) 2022 Ultra Librarian. All rights reserved."))
      (libsource (lib "RC1206FR-07100RL") (part "RC1206FR-07100RL"))
    )
    (comp (ref "R577")
      (value "RC1206FR-07100RL")
      (footprint "RC1206N_YAG")
      (description "No Description Available")
      (fields (field (name "COPYRIGHT") "Copyright (C) 2022 Ultra Librarian. All rights reserved."))
      (libsource (lib "RC1206FR-07100RL") (part "RC1206FR-07100RL"))
    )
    (comp (ref "R578")
      (value "RC1206FR-07100RL")
      (footprint "RC1206N_YAG")
      (description "No Description Available")
      (fields (field (name "COPYRIGHT") "Copyright (C) 2022 Ultra Librarian. All rights reserved."))
      (libsource (lib "RC1206FR-07100RL") (part "RC1206FR-07100RL"))
    )
    (comp (ref "R579")
      (value "RC1206FR-07100RL")
      (footprint "RC1206N_YAG")
      (description "No Description Available")
      (fields (field (name "COPYRIGHT") "Copyright (C) 2022 Ultra Librarian. All rights reserved."))
      (libsource (lib "RC1206FR-07100RL") (part "RC1206FR-07100RL"))
    )
    (comp (ref "R580")
      (value "RC1206FR-07100RL")
      (footprint "RC1206N_YAG")
      (description "No Description Available")
      (fields (field (name "COPYRIGHT") "Copyright (C) 2022 Ultra Librarian. All rights reserved."))
      (libsource (lib "RC1206FR-07100RL") (part "RC1206FR-07100RL"))
    )
    (comp (ref "R581")
      (value "RC1206FR-07100RL")
      (footprint "RC1206N_YAG")
      (description "No Description Available")
      (fields (field (name "COPYRIGHT") "Copyright (C) 2022 Ultra Librarian. All rights reserved."))
      (libsource (lib "RC1206FR-07100RL") (part "RC1206FR-07100RL"))
    )
    (comp (ref "R582")
      (value "RC1206FR-07100RL")
      (footprint "RC1206N_YAG")
      (description "No Description Available")
      (fields (field (name "COPYRIGHT") "Copyright (C) 2022 Ultra Librarian. All rights reserved."))
      (libsource (lib "RC1206FR-07100RL") (part "RC1206FR-07100RL"))
    )
    (comp (ref "R583")
      (value "RC1206FR-07100RL")
      (footprint "RC1206N_YAG")
      (description "No Description Available")
      (fields (field (name "COPYRIGHT") "Copyright (C) 2022 Ultra Librarian. All rights reserved."))
      (libsource (lib "RC1206FR-07100RL") (part "RC1206FR-07100RL"))
    )
    (comp (ref "R584")
      (value "RC1206FR-07100RL")
      (footprint "RC1206N_YAG")
      (description "No Description Available")
      (fields (field (name "COPYRIGHT") "Copyright (C) 2022 Ultra Librarian. All rights reserved."))
      (libsource (lib "RC1206FR-07100RL") (part "RC1206FR-07100RL"))
    )
    (comp (ref "R585")
      (value "RC1206FR-07100RL")
      (footprint "RC1206N_YAG")
      (description "No Description Available")
      (fields (field (name "COPYRIGHT") "Copyright (C) 2022 Ultra Librarian. All rights reserved."))
      (libsource (lib "RC1206FR-07100RL") (part "RC1206FR-07100RL"))
    )
    (comp (ref "R586")
      (value "RC1206FR-07100RL")
      (footprint "RC1206N_YAG")
      (description "No Description Available")
      (fields (field (name "COPYRIGHT") "Copyright (C) 2022 Ultra Librarian. All rights reserved."))
      (libsource (lib "RC1206FR-07100RL") (part "RC1206FR-07100RL"))
    )
    (comp (ref "R587")
      (value "RC1206FR-07100RL")
      (footprint "RC1206N_YAG")
      (description "No Description Available")
      (fields (field (name "COPYRIGHT") "Copyright (C) 2022 Ultra Librarian. All rights reserved."))
      (libsource (lib "RC1206FR-07100RL") (part "RC1206FR-07100RL"))
    )
    (comp (ref "R588")
      (value "RC1206FR-07100RL")
      (footprint "RC1206N_YAG")
      (description "No Description Available")
      (fields (field (name "COPYRIGHT") "Copyright (C) 2022 Ultra Librarian. All rights reserved."))
      (libsource (lib "RC1206FR-07100RL") (part "RC1206FR-07100RL"))
    )
    (comp (ref "R589")
      (value "RC1206FR-07100RL")
      (footprint "RC1206N_YAG")
      (description "No Description Available")
      (fields (field (name "COPYRIGHT") "Copyright (C) 2022 Ultra Librarian. All rights reserved."))
      (libsource (lib "RC1206FR-07100RL") (part "RC1206FR-07100RL"))
    )
    (comp (ref "R590")
      (value "RC1206FR-07100RL")
      (footprint "RC1206N_YAG")
      (description "No Description Available")
      (fields (field (name "COPYRIGHT") "Copyright (C) 2022 Ultra Librarian. All rights reserved."))
      (libsource (lib "RC1206FR-07100RL") (part "RC1206FR-07100RL"))
    )
    (comp (ref "R591")
      (value "RC1206FR-07100RL")
      (footprint "RC1206N_YAG")
      (description "No Description Available")
      (fields (field (name "COPYRIGHT") "Copyright (C) 2022 Ultra Librarian. All rights reserved."))
      (libsource (lib "RC1206FR-07100RL") (part "RC1206FR-07100RL"))
    )
    (comp (ref "R592")
      (value "RC1206FR-07100RL")
      (footprint "RC1206N_YAG")
      (description "No Description Available")
      (fields (field (name "COPYRIGHT") "Copyright (C) 2022 Ultra Librarian. All rights reserved."))
      (libsource (lib "RC1206FR-07100RL") (part "RC1206FR-07100RL"))
    )
    (comp (ref "R593")
      (value "RC1206FR-07100RL")
      (footprint "RC1206N_YAG")
      (description "No Description Available")
      (fields (field (name "COPYRIGHT") "Copyright (C) 2022 Ultra Librarian. All rights reserved."))
      (libsource (lib "RC1206FR-07100RL") (part "RC1206FR-07100RL"))
    )
    (comp (ref "R594")
      (value "RC1206FR-07100RL")
      (footprint "RC1206N_YAG")
      (description "No Description Available")
      (fields (field (name "COPYRIGHT") "Copyright (C) 2022 Ultra Librarian. All rights reserved."))
      (libsource (lib "RC1206FR-07100RL") (part "RC1206FR-07100RL"))
    )
    (comp (ref "R595")
      (value "RC1206FR-07100RL")
      (footprint "RC1206N_YAG")
      (description "No Description Available")
      (fields (field (name "COPYRIGHT") "Copyright (C) 2022 Ultra Librarian. All rights reserved."))
      (libsource (lib "RC1206FR-07100RL") (part "RC1206FR-07100RL"))
    )
    (comp (ref "R596")
      (value "RC1206FR-07100RL")
      (footprint "RC1206N_YAG")
      (description "No Description Available")
      (fields (field (name "COPYRIGHT") "Copyright (C) 2022 Ultra Librarian. All rights reserved."))
      (libsource (lib "RC1206FR-07100RL") (part "RC1206FR-07100RL"))
    )
    (comp (ref "R597")
      (value "RC1206FR-07100RL")
      (footprint "RC1206N_YAG")
      (description "No Description Available")
      (fields (field (name "COPYRIGHT") "Copyright (C) 2022 Ultra Librarian. All rights reserved."))
      (libsource (lib "RC1206FR-07100RL") (part "RC1206FR-07100RL"))
    )
    (comp (ref "R598")
      (value "RC1206FR-07100RL")
      (footprint "RC1206N_YAG")
      (description "No Description Available")
      (fields (field (name "COPYRIGHT") "Copyright (C) 2022 Ultra Librarian. All rights reserved."))
      (libsource (lib "RC1206FR-07100RL") (part "RC1206FR-07100RL"))
    )
    (comp (ref "R599")
      (value "RC1206FR-07100RL")
      (footprint "RC1206N_YAG")
      (description "No Description Available")
      (fields (field (name "COPYRIGHT") "Copyright (C) 2022 Ultra Librarian. All rights reserved."))
      (libsource (lib "RC1206FR-07100RL") (part "RC1206FR-07100RL"))
    )
    (comp (ref "R600")
      (value "RC1206FR-07100RL")
      (footprint "RC1206N_YAG")
      (description "No Description Available")
      (fields (field (name "COPYRIGHT") "Copyright (C) 2022 Ultra Librarian. All rights reserved."))
      (libsource (lib "RC1206FR-07100RL") (part "RC1206FR-07100RL"))
    )
    (comp (ref "R601")
      (value "RC1206FR-07100RL")
      (footprint "RC1206N_YAG")
      (description "No Description Available")
      (fields (field (name "COPYRIGHT") "Copyright (C) 2022 Ultra Librarian. All rights reserved."))
      (libsource (lib "RC1206FR-07100RL") (part "RC1206FR-07100RL"))
    )
    (comp (ref "R602")
      (value "RC1206FR-07100RL")
      (footprint "RC1206N_YAG")
      (description "No Description Available")
      (fields (field (name "COPYRIGHT") "Copyright (C) 2022 Ultra Librarian. All rights reserved."))
      (libsource (lib "RC1206FR-07100RL") (part "RC1206FR-07100RL"))
    )
    (comp (ref "R603")
      (value "RC1206FR-07100RL")
      (footprint "RC1206N_YAG")
      (description "No Description Available")
      (fields (field (name "COPYRIGHT") "Copyright (C) 2022 Ultra Librarian. All rights reserved."))
      (libsource (lib "RC1206FR-07100RL") (part "RC1206FR-07100RL"))
    )
    (comp (ref "R604")
      (value "RC1206FR-07100RL")
      (footprint "RC1206N_YAG")
      (description "No Description Available")
      (fields (field (name "COPYRIGHT") "Copyright (C) 2022 Ultra Librarian. All rights reserved."))
      (libsource (lib "RC1206FR-07100RL") (part "RC1206FR-07100RL"))
    )
    (comp (ref "R605")
      (value "RC1206FR-07100RL")
      (footprint "RC1206N_YAG")
      (description "No Description Available")
      (fields (field (name "COPYRIGHT") "Copyright (C) 2022 Ultra Librarian. All rights reserved."))
      (libsource (lib "RC1206FR-07100RL") (part "RC1206FR-07100RL"))
    )
    (comp (ref "R606")
      (value "RC1206FR-07100RL")
      (footprint "RC1206N_YAG")
      (description "No Description Available")
      (fields (field (name "COPYRIGHT") "Copyright (C) 2022 Ultra Librarian. All rights reserved."))
      (libsource (lib "RC1206FR-07100RL") (part "RC1206FR-07100RL"))
    )
    (comp (ref "R607")
      (value "RC1206FR-07100RL")
      (footprint "RC1206N_YAG")
      (description "No Description Available")
      (fields (field (name "COPYRIGHT") "Copyright (C) 2022 Ultra Librarian. All rights reserved."))
      (libsource (lib "RC1206FR-07100RL") (part "RC1206FR-07100RL"))
    )
    (comp (ref "R608")
      (value "RC1206FR-07100RL")
      (footprint "RC1206N_YAG")
      (description "No Description Available")
      (fields (field (name "COPYRIGHT") "Copyright (C) 2022 Ultra Librarian. All rights reserved."))
      (libsource (lib "RC1206FR-07100RL") (part "RC1206FR-07100RL"))
    )
    (comp (ref "R609")
      (value "RC1206FR-07100RL")
      (footprint "RC1206N_YAG")
      (description "No Description Available")
      (fields (field (name "COPYRIGHT") "Copyright (C) 2022 Ultra Librarian. All rights reserved."))
      (libsource (lib "RC1206FR-07100RL") (part "RC1206FR-07100RL"))
    )
    (comp (ref "R610")
      (value "RC1206FR-07100RL")
      (footprint "RC1206N_YAG")
      (description "No Description Available")
      (fields (field (name "COPYRIGHT") "Copyright (C) 2022 Ultra Librarian. All rights reserved."))
      (libsource (lib "RC1206FR-07100RL") (part "RC1206FR-07100RL"))
    )
    (comp (ref "R611")
      (value "RC1206FR-07100RL")
      (footprint "RC1206N_YAG")
      (description "No Description Available")
      (fields (field (name "COPYRIGHT") "Copyright (C) 2022 Ultra Librarian. All rights reserved."))
      (libsource (lib "RC1206FR-07100RL") (part "RC1206FR-07100RL"))
    )
    (comp (ref "R612")
      (value "RC1206FR-07100RL")
      (footprint "RC1206N_YAG")
      (description "No Description Available")
      (fields (field (name "COPYRIGHT") "Copyright (C) 2022 Ultra Librarian. All rights reserved."))
      (libsource (lib "RC1206FR-07100RL") (part "RC1206FR-07100RL"))
    )
    (comp (ref "R613")
      (value "RC1206FR-07100RL")
      (footprint "RC1206N_YAG")
      (description "No Description Available")
      (fields (field (name "COPYRIGHT") "Copyright (C) 2022 Ultra Librarian. All rights reserved."))
      (libsource (lib "RC1206FR-07100RL") (part "RC1206FR-07100RL"))
    )
    (comp (ref "R614")
      (value "RC1206FR-07100RL")
      (footprint "RC1206N_YAG")
      (description "No Description Available")
      (fields (field (name "COPYRIGHT") "Copyright (C) 2022 Ultra Librarian. All rights reserved."))
      (libsource (lib "RC1206FR-07100RL") (part "RC1206FR-07100RL"))
    )
    (comp (ref "R615")
      (value "RC1206FR-07100RL")
      (footprint "RC1206N_YAG")
      (description "No Description Available")
      (fields (field (name "COPYRIGHT") "Copyright (C) 2022 Ultra Librarian. All rights reserved."))
      (libsource (lib "RC1206FR-07100RL") (part "RC1206FR-07100RL"))
    )
    (comp (ref "R616")
      (value "RC1206FR-07100RL")
      (footprint "RC1206N_YAG")
      (description "No Description Available")
      (fields (field (name "COPYRIGHT") "Copyright (C) 2022 Ultra Librarian. All rights reserved."))
      (libsource (lib "RC1206FR-07100RL") (part "RC1206FR-07100RL"))
    )
    (comp (ref "R617")
      (value "RC1206FR-07100RL")
      (footprint "RC1206N_YAG")
      (description "No Description Available")
      (fields (field (name "COPYRIGHT") "Copyright (C) 2022 Ultra Librarian. All rights reserved."))
      (libsource (lib "RC1206FR-07100RL") (part "RC1206FR-07100RL"))
    )
    (comp (ref "R618")
      (value "RC1206FR-07100RL")
      (footprint "RC1206N_YAG")
      (description "No Description Available")
      (fields (field (name "COPYRIGHT") "Copyright (C) 2022 Ultra Librarian. All rights reserved."))
      (libsource (lib "RC1206FR-07100RL") (part "RC1206FR-07100RL"))
    )
    (comp (ref "R619")
      (value "RC1206FR-07100RL")
      (footprint "RC1206N_YAG")
      (description "No Description Available")
      (fields (field (name "COPYRIGHT") "Copyright (C) 2022 Ultra Librarian. All rights reserved."))
      (libsource (lib "RC1206FR-07100RL") (part "RC1206FR-07100RL"))
    )
    (comp (ref "R620")
      (value "RC1206FR-07100RL")
      (footprint "RC1206N_YAG")
      (description "No Description Available")
      (fields (field (name "COPYRIGHT") "Copyright (C) 2022 Ultra Librarian. All rights reserved."))
      (libsource (lib "RC1206FR-07100RL") (part "RC1206FR-07100RL"))
    )
    (comp (ref "R621")
      (value "RC1206FR-07100RL")
      (footprint "RC1206N_YAG")
      (description "No Description Available")
      (fields (field (name "COPYRIGHT") "Copyright (C) 2022 Ultra Librarian. All rights reserved."))
      (libsource (lib "RC1206FR-07100RL") (part "RC1206FR-07100RL"))
    )
    (comp (ref "R622")
      (value "RC1206FR-07100RL")
      (footprint "RC1206N_YAG")
      (description "No Description Available")
      (fields (field (name "COPYRIGHT") "Copyright (C) 2022 Ultra Librarian. All rights reserved."))
      (libsource (lib "RC1206FR-07100RL") (part "RC1206FR-07100RL"))
    )
    (comp (ref "R623")
      (value "RC1206FR-07100RL")
      (footprint "RC1206N_YAG")
      (description "No Description Available")
      (fields (field (name "COPYRIGHT") "Copyright (C) 2022 Ultra Librarian. All rights reserved."))
      (libsource (lib "RC1206FR-07100RL") (part "RC1206FR-07100RL"))
    )
    (comp (ref "R624")
      (value "RC1206FR-07100RL")
      (footprint "RC1206N_YAG")
      (description "No Description Available")
      (fields (field (name "COPYRIGHT") "Copyright (C) 2022 Ultra Librarian. All rights reserved."))
      (libsource (lib "RC1206FR-07100RL") (part "RC1206FR-07100RL"))
    )
  )
  (nets
    (net (code "1") (name "Net-(Header1-Pad1)") (class "Default")
      (node (ref "Header1") (pin "1") (pintype "input"))
      (node (ref "R1") (pin "1") (pinfunction "1_1") (pintype "passive"))
    )
    (net (code "2") (name "Net-(Header1-Pad3)") (class "Default")
      (node (ref "Header1") (pin "3") (pintype "input"))
      (node (ref "R2") (pin "1") (pinfunction "1_1") (pintype "passive"))
    )
    (net (code "3") (name "Net-(Header1-Pad4)") (class "Default")
      (node (ref "Header1") (pin "4") (pintype "input"))
      (node (ref "R3") (pin "1") (pinfunction "1_1") (pintype "passive"))
    )
    (net (code "4") (name "Net-(Header1-Pad5)") (class "Default")
      (node (ref "Header1") (pin "5") (pintype "input"))
      (node (ref "R4") (pin "1") (pinfunction "1_1") (pintype "passive"))
    )
    (net (code "5") (name "Net-(Header1-Pad6)") (class "Default")
      (node (ref "Header1") (pin "6") (pintype "input"))
      (node (ref "R5") (pin "1") (pinfunction "1_1") (pintype "passive"))
    )
    (net (code "6") (name "Net-(Header1-Pad7)") (class "Default")
      (node (ref "Header1") (pin "7") (pintype "input"))
      (node (ref "R6") (pin "1") (pinfunction "1_1") (pintype "passive"))
    )
    (net (code "7") (name "Net-(Header1-Pad8)") (class "Default")
      (node (ref "Header1") (pin "8") (pintype "input"))
      (node (ref "R7") (pin "1") (pinfunction "1_1") (pintype "passive"))
    )
    (net (code "8") (name "Net-(Header1-Pad9)") (class "Default")
      (node (ref "Header1") (pin "9") (pintype "input"))
      (node (ref "R8") (pin "1") (pinfunction "1_1") (pintype "passive"))
    )
    (net (code "9") (name "Net-(Header1-Pad10)") (class "Default")
      (node (ref "Header1") (pin "10") (pintype "input"))
      (node (ref "R9") (pin "1") (pinfunction "1_1") (pintype "passive"))
    )
    (net (code "10") (name "Net-(Header2-Pad1)") (class "Default")
      (node (ref "Header2") (pin "1") (pintype "input"))
      (node (ref "R10") (pin "1") (pinfunction "1_1") (pintype "passive"))
    )
    (net (code "11") (name "Net-(Header2-Pad2)") (class "Default")
      (node (ref "Header2") (pin "2") (pintype "input"))
      (node (ref "R11") (pin "1") (pinfunction "1_1") (pintype "passive"))
    )
    (net (code "12") (name "Net-(Header2-Pad3)") (class "Default")
      (node (ref "Header2") (pin "3") (pintype "input"))
      (node (ref "R12") (pin "1") (pinfunction "1_1") (pintype "passive"))
    )
    (net (code "13") (name "Net-(Header2-Pad5)") (class "Default")
      (node (ref "Header2") (pin "5") (pintype "input"))
      (node (ref "R13") (pin "1") (pinfunction "1_1") (pintype "passive"))
    )
    (net (code "14") (name "Net-(Header2-Pad6)") (class "Default")
      (node (ref "Header2") (pin "6") (pintype "input"))
      (node (ref "R14") (pin "1") (pinfunction "1_1") (pintype "passive"))
    )
    (net (code "15") (name "Net-(Header2-Pad7)") (class "Default")
      (node (ref "Header2") (pin "7") (pintype "input"))
      (node (ref "R15") (pin "1") (pinfunction "1_1") (pintype "passive"))
    )
    (net (code "16") (name "Net-(Header2-Pad8)") (class "Default")
      (node (ref "Header2") (pin "8") (pintype "input"))
      (node (ref "R16") (pin "1") (pinfunction "1_1") (pintype "passive"))
    )
    (net (code "17") (name "Net-(Header2-Pad9)") (class "Default")
      (node (ref "Header2") (pin "9") (pintype "input"))
      (node (ref "R17") (pin "1") (pinfunction "1_1") (pintype "passive"))
    )
    (net (code "18") (name "Net-(Header2-Pad10)") (class "Default")
      (node (ref "Header2") (pin "10") (pintype "input"))
      (node (ref "R18") (pin "1") (pinfunction "1_1") (pintype "passive"))
    )
    (net (code "19") (name "Net-(Header3-Pad1)") (class "Default")
      (node (ref "Header3") (pin "1") (pintype "input"))
      (node (ref "R19") (pin "1") (pinfunction "1_1") (pintype "passive"))
    )
    (net (code "20") (name "Net-(Header3-Pad5)") (class "Default")
      (node (ref "Header3") (pin "5") (pintype "input"))
      (node (ref "R20") (pin "1") (pinfunction "1_1") (pintype "passive"))
    )
    (net (code "21") (name "Net-(Header3-Pad6)") (class "Default")
      (node (ref "Header3") (pin "6") (pintype "input"))
      (node (ref "R21") (pin "1") (pinfunction "1_1") (pintype "passive"))
    )
    (net (code "22") (name "Net-(Header3-Pad7)") (class "Default")
      (node (ref "Header3") (pin "7") (pintype "input"))
      (node (ref "R22") (pin "1") (pinfunction "1_1") (pintype "passive"))
    )
    (net (code "23") (name "Net-(Header3-Pad8)") (class "Default")
      (node (ref "Header3") (pin "8") (pintype "input"))
      (node (ref "R23") (pin "1") (pinfunction "1_1") (pintype "passive"))
    )
    (net (code "24") (name "Net-(Header3-Pad9)") (class "Default")
      (node (ref "Header3") (pin "9") (pintype "input"))
      (node (ref "R24") (pin "1") (pinfunction "1_1") (pintype "passive"))
    )
    (net (code "25") (name "Net-(Header3-Pad10)") (class "Default")
      (node (ref "Header3") (pin "10") (pintype "input"))
      (node (ref "R26") (pin "2") (pinfunction "2_2") (pintype "passive"))
    )
    (net (code "26") (name "Net-(Header3-Pad11)") (class "Default")
      (node (ref "Header3") (pin "11") (pintype "input"))
      (node (ref "R27") (pin "2") (pinfunction "2_2") (pintype "passive"))
    )
    (net (code "27") (name "Net-(Header3-Pad12)") (class "Default")
      (node (ref "Header3") (pin "12") (pintype "input"))
      (node (ref "R28") (pin "2") (pinfunction "2_2") (pintype "passive"))
    )
    (net (code "28") (name "Net-(Header3-Pad13)") (class "Default")
      (node (ref "Header3") (pin "13") (pintype "input"))
      (node (ref "R29") (pin "2") (pinfunction "2_2") (pintype "passive"))
    )
    (net (code "29") (name "Net-(Header3-Pad14)") (class "Default")
      (node (ref "Header3") (pin "14") (pintype "input"))
      (node (ref "R30") (pin "2") (pinfunction "2_2") (pintype "passive"))
    )
    (net (code "30") (name "Net-(Header3-Pad15)") (class "Default")
      (node (ref "Header3") (pin "15") (pintype "input"))
      (node (ref "R31") (pin "2") (pinfunction "2_2") (pintype "passive"))
    )
    (net (code "31") (name "Net-(Header3-Pad16)") (class "Default")
      (node (ref "Header3") (pin "16") (pintype "input"))
      (node (ref "R32") (pin "2") (pinfunction "2_2") (pintype "passive"))
    )
    (net (code "32") (name "Net-(Header3-Pad17)") (class "Default")
      (node (ref "Header3") (pin "17") (pintype "input"))
      (node (ref "R33") (pin "2") (pinfunction "2_2") (pintype "passive"))
    )
    (net (code "33") (name "Net-(Header3-Pad18)") (class "Default")
      (node (ref "Header3") (pin "18") (pintype "input"))
      (node (ref "R34") (pin "2") (pinfunction "2_2") (pintype "passive"))
    )
    (net (code "34") (name "Net-(Header4-Pad1)") (class "Default")
      (node (ref "Header4") (pin "1") (pintype "input"))
      (node (ref "R35") (pin "2") (pinfunction "2_2") (pintype "passive"))
    )
    (net (code "35") (name "Net-(Header4-Pad2)") (class "Default")
      (node (ref "Header4") (pin "2") (pintype "input"))
      (node (ref "R36") (pin "2") (pinfunction "2_2") (pintype "passive"))
    )
    (net (code "36") (name "Net-(Header4-Pad3)") (class "Default")
      (node (ref "Header4") (pin "3") (pintype "input"))
      (node (ref "R37") (pin "2") (pinfunction "2_2") (pintype "passive"))
    )
    (net (code "37") (name "Net-(Header4-Pad4)") (class "Default")
      (node (ref "Header4") (pin "4") (pintype "input"))
      (node (ref "R38") (pin "2") (pinfunction "2_2") (pintype "passive"))
    )
    (net (code "38") (name "Net-(Header4-Pad5)") (class "Default")
      (node (ref "Header4") (pin "5") (pintype "input"))
      (node (ref "R39") (pin "2") (pinfunction "2_2") (pintype "passive"))
    )
    (net (code "39") (name "Net-(Header4-Pad9)") (class "Default")
      (node (ref "Header4") (pin "9") (pintype "input"))
      (node (ref "R40") (pin "2") (pinfunction "2_2") (pintype "passive"))
    )
    (net (code "40") (name "Net-(Header4-Pad10)") (class "Default")
      (node (ref "Header4") (pin "10") (pintype "input"))
      (node (ref "R41") (pin "2") (pinfunction "2_2") (pintype "passive"))
    )
    (net (code "41") (name "Net-(Header4-Pad11)") (class "Default")
      (node (ref "Header4") (pin "11") (pintype "input"))
      (node (ref "R42") (pin "2") (pinfunction "2_2") (pintype "passive"))
    )
    (net (code "42") (name "Net-(Header4-Pad12)") (class "Default")
      (node (ref "Header4") (pin "12") (pintype "input"))
      (node (ref "R43") (pin "2") (pinfunction "2_2") (pintype "passive"))
    )
    (net (code "43") (name "Net-(Header4-Pad13)") (class "Default")
      (node (ref "Header4") (pin "13") (pintype "input"))
      (node (ref "R44") (pin "2") (pinfunction "2_2") (pintype "passive"))
    )
    (net (code "44") (name "Net-(Header4-Pad14)") (class "Default")
      (node (ref "Header4") (pin "14") (pintype "input"))
      (node (ref "R45") (pin "2") (pinfunction "2_2") (pintype "passive"))
    )
    (net (code "45") (name "Net-(Header4-Pad15)") (class "Default")
      (node (ref "Header4") (pin "15") (pintype "input"))
      (node (ref "R46") (pin "2") (pinfunction "2_2") (pintype "passive"))
    )
    (net (code "46") (name "Net-(Header4-Pad16)") (class "Default")
      (node (ref "Header4") (pin "16") (pintype "input"))
      (node (ref "R47") (pin "2") (pinfunction "2_2") (pintype "passive"))
    )
    (net (code "47") (name "Net-(Header4-Pad17)") (class "Default")
      (node (ref "Header4") (pin "17") (pintype "input"))
      (node (ref "R48") (pin "2") (pinfunction "2_2") (pintype "passive"))
    )
    (net (code "48") (name "Net-(Header4-Pad18)") (class "Default")
      (node (ref "Header4") (pin "18") (pintype "input"))
      (node (ref "R49") (pin "2") (pinfunction "2_2") (pintype "passive"))
    )
    (net (code "49") (name "Net-(Header5-Pad1)") (class "Default")
      (node (ref "Header5") (pin "1") (pintype "input"))
      (node (ref "R51") (pin "1") (pinfunction "1_1") (pintype "passive"))
    )
    (net (code "50") (name "Net-(Header5-Pad2)") (class "Default")
      (node (ref "Header5") (pin "2") (pintype "input"))
      (node (ref "R52") (pin "1") (pinfunction "1_1") (pintype "passive"))
    )
    (net (code "51") (name "Net-(Header5-Pad3)") (class "Default")
      (node (ref "Header5") (pin "3") (pintype "input"))
      (node (ref "R53") (pin "1") (pinfunction "1_1") (pintype "passive"))
    )
    (net (code "52") (name "Net-(Header5-Pad4)") (class "Default")
      (node (ref "Header5") (pin "4") (pintype "input"))
      (node (ref "R54") (pin "1") (pinfunction "1_1") (pintype "passive"))
    )
    (net (code "53") (name "Net-(Header5-Pad5)") (class "Default")
      (node (ref "Header5") (pin "5") (pintype "input"))
      (node (ref "R55") (pin "1") (pinfunction "1_1") (pintype "passive"))
    )
    (net (code "54") (name "Net-(Header5-Pad6)") (class "Default")
      (node (ref "Header5") (pin "6") (pintype "input"))
      (node (ref "R56") (pin "1") (pinfunction "1_1") (pintype "passive"))
    )
    (net (code "55") (name "Net-(Header5-Pad7)") (class "Default")
      (node (ref "Header5") (pin "7") (pintype "input"))
      (node (ref "R57") (pin "1") (pinfunction "1_1") (pintype "passive"))
    )
    (net (code "56") (name "Net-(Header5-Pad8)") (class "Default")
      (node (ref "Header5") (pin "8") (pintype "input"))
      (node (ref "R58") (pin "1") (pinfunction "1_1") (pintype "passive"))
    )
    (net (code "57") (name "Net-(Header5-Pad9)") (class "Default")
      (node (ref "Header5") (pin "9") (pintype "input"))
      (node (ref "R59") (pin "1") (pinfunction "1_1") (pintype "passive"))
    )
    (net (code "58") (name "Net-(Header5-Pad10)") (class "Default")
      (node (ref "Header5") (pin "10") (pintype "input"))
      (node (ref "R60") (pin "1") (pinfunction "1_1") (pintype "passive"))
    )
    (net (code "59") (name "Net-(Header5-Pad11)") (class "Default")
      (node (ref "Header5") (pin "11") (pintype "input"))
      (node (ref "R61") (pin "1") (pinfunction "1_1") (pintype "passive"))
    )
    (net (code "60") (name "Net-(Header5-Pad12)") (class "Default")
      (node (ref "Header5") (pin "12") (pintype "input"))
      (node (ref "R62") (pin "1") (pinfunction "1_1") (pintype "passive"))
    )
    (net (code "61") (name "Net-(Header5-Pad13)") (class "Default")
      (node (ref "Header5") (pin "13") (pintype "input"))
      (node (ref "R63") (pin "1") (pinfunction "1_1") (pintype "passive"))
    )
    (net (code "62") (name "Net-(Header5-Pad14)") (class "Default")
      (node (ref "Header5") (pin "14") (pintype "input"))
      (node (ref "R64") (pin "1") (pinfunction "1_1") (pintype "passive"))
    )
    (net (code "63") (name "Net-(Header5-Pad15)") (class "Default")
      (node (ref "Header5") (pin "15") (pintype "input"))
      (node (ref "R65") (pin "1") (pinfunction "1_1") (pintype "passive"))
    )
    (net (code "64") (name "Net-(Header5-Pad16)") (class "Default")
      (node (ref "Header5") (pin "16") (pintype "input"))
      (node (ref "R66") (pin "1") (pinfunction "1_1") (pintype "passive"))
    )
    (net (code "65") (name "Net-(Header5-Pad17)") (class "Default")
      (node (ref "Header5") (pin "17") (pintype "input"))
      (node (ref "R67") (pin "1") (pinfunction "1_1") (pintype "passive"))
    )
    (net (code "66") (name "Net-(Header5-Pad18)") (class "Default")
      (node (ref "Header5") (pin "18") (pintype "input"))
      (node (ref "R68") (pin "1") (pinfunction "1_1") (pintype "passive"))
    )
    (net (code "67") (name "Net-(Header6-Pad1)") (class "Default")
      (node (ref "Header6") (pin "1") (pintype "input"))
      (node (ref "R69") (pin "1") (pinfunction "1_1") (pintype "passive"))
    )
    (net (code "68") (name "Net-(Header6-Pad2)") (class "Default")
      (node (ref "Header6") (pin "2") (pintype "input"))
      (node (ref "R70") (pin "1") (pinfunction "1_1") (pintype "passive"))
    )
    (net (code "69") (name "Net-(Header6-Pad3)") (class "Default")
      (node (ref "Header6") (pin "3") (pintype "input"))
      (node (ref "R71") (pin "1") (pinfunction "1_1") (pintype "passive"))
    )
    (net (code "70") (name "Net-(Header6-Pad4)") (class "Default")
      (node (ref "Header6") (pin "4") (pintype "input"))
      (node (ref "R72") (pin "1") (pinfunction "1_1") (pintype "passive"))
    )
    (net (code "71") (name "Net-(Header6-Pad5)") (class "Default")
      (node (ref "Header6") (pin "5") (pintype "input"))
      (node (ref "R73") (pin "1") (pinfunction "1_1") (pintype "passive"))
    )
    (net (code "72") (name "Net-(Header6-Pad6)") (class "Default")
      (node (ref "Header6") (pin "6") (pintype "input"))
      (node (ref "R74") (pin "1") (pinfunction "1_1") (pintype "passive"))
    )
    (net (code "73") (name "Net-(Header6-Pad7)") (class "Default")
      (node (ref "Header6") (pin "7") (pintype "input"))
      (node (ref "R76") (pin "2") (pinfunction "2_2") (pintype "passive"))
    )
    (net (code "74") (name "Net-(Header6-Pad8)") (class "Default")
      (node (ref "Header6") (pin "8") (pintype "input"))
      (node (ref "R77") (pin "2") (pinfunction "2_2") (pintype "passive"))
    )
    (net (code "75") (name "Net-(Header6-Pad9)") (class "Default")
      (node (ref "Header6") (pin "9") (pintype "input"))
      (node (ref "R78") (pin "2") (pinfunction "2_2") (pintype "passive"))
    )
    (net (code "76") (name "Net-(Header6-Pad10)") (class "Default")
      (node (ref "Header6") (pin "10") (pintype "input"))
      (node (ref "R79") (pin "2") (pinfunction "2_2") (pintype "passive"))
    )
    (net (code "77") (name "Net-(Header6-Pad11)") (class "Default")
      (node (ref "Header6") (pin "11") (pintype "input"))
      (node (ref "R80") (pin "2") (pinfunction "2_2") (pintype "passive"))
    )
    (net (code "78") (name "Net-(Header6-Pad12)") (class "Default")
      (node (ref "Header6") (pin "12") (pintype "input"))
      (node (ref "R81") (pin "2") (pinfunction "2_2") (pintype "passive"))
    )
    (net (code "79") (name "Net-(Header6-Pad13)") (class "Default")
      (node (ref "Header6") (pin "13") (pintype "input"))
      (node (ref "R82") (pin "2") (pinfunction "2_2") (pintype "passive"))
    )
    (net (code "80") (name "Net-(Header6-Pad14)") (class "Default")
      (node (ref "Header6") (pin "14") (pintype "input"))
      (node (ref "R83") (pin "2") (pinfunction "2_2") (pintype "passive"))
    )
    (net (code "81") (name "Net-(Header6-Pad15)") (class "Default")
      (node (ref "Header6") (pin "15") (pintype "input"))
      (node (ref "R84") (pin "2") (pinfunction "2_2") (pintype "passive"))
    )
    (net (code "82") (name "Net-(Header6-Pad16)") (class "Default")
      (node (ref "Header6") (pin "16") (pintype "input"))
      (node (ref "R85") (pin "2") (pinfunction "2_2") (pintype "passive"))
    )
    (net (code "83") (name "Net-(Header6-Pad17)") (class "Default")
      (node (ref "Header6") (pin "17") (pintype "input"))
      (node (ref "R86") (pin "2") (pinfunction "2_2") (pintype "passive"))
    )
    (net (code "84") (name "Net-(Header6-Pad18)") (class "Default")
      (node (ref "Header6") (pin "18") (pintype "input"))
      (node (ref "R87") (pin "2") (pinfunction "2_2") (pintype "passive"))
    )
    (net (code "85") (name "Net-(Header7-Pad1)") (class "Default")
      (node (ref "Header7") (pin "1") (pintype "input"))
      (node (ref "R88") (pin "2") (pinfunction "2_2") (pintype "passive"))
    )
    (net (code "86") (name "Net-(Header7-Pad2)") (class "Default")
      (node (ref "Header7") (pin "2") (pintype "input"))
      (node (ref "R89") (pin "2") (pinfunction "2_2") (pintype "passive"))
    )
    (net (code "87") (name "Net-(Header7-Pad3)") (class "Default")
      (node (ref "Header7") (pin "3") (pintype "input"))
      (node (ref "R90") (pin "2") (pinfunction "2_2") (pintype "passive"))
    )
    (net (code "88") (name "Net-(Header7-Pad4)") (class "Default")
      (node (ref "Header7") (pin "4") (pintype "input"))
      (node (ref "R91") (pin "2") (pinfunction "2_2") (pintype "passive"))
    )
    (net (code "89") (name "Net-(Header7-Pad5)") (class "Default")
      (node (ref "Header7") (pin "5") (pintype "input"))
      (node (ref "R92") (pin "2") (pinfunction "2_2") (pintype "passive"))
    )
    (net (code "90") (name "Net-(Header7-Pad6)") (class "Default")
      (node (ref "Header7") (pin "6") (pintype "input"))
      (node (ref "R93") (pin "2") (pinfunction "2_2") (pintype "passive"))
    )
    (net (code "91") (name "Net-(Header7-Pad7)") (class "Default")
      (node (ref "Header7") (pin "7") (pintype "input"))
      (node (ref "R94") (pin "2") (pinfunction "2_2") (pintype "passive"))
    )
    (net (code "92") (name "Net-(Header7-Pad8)") (class "Default")
      (node (ref "Header7") (pin "8") (pintype "input"))
      (node (ref "R95") (pin "2") (pinfunction "2_2") (pintype "passive"))
    )
    (net (code "93") (name "Net-(Header7-Pad9)") (class "Default")
      (node (ref "Header7") (pin "9") (pintype "input"))
      (node (ref "R96") (pin "2") (pinfunction "2_2") (pintype "passive"))
    )
    (net (code "94") (name "Net-(Header7-Pad10)") (class "Default")
      (node (ref "Header7") (pin "10") (pintype "input"))
      (node (ref "R97") (pin "2") (pinfunction "2_2") (pintype "passive"))
    )
    (net (code "95") (name "Net-(Header7-Pad11)") (class "Default")
      (node (ref "Header7") (pin "11") (pintype "input"))
      (node (ref "R98") (pin "2") (pinfunction "2_2") (pintype "passive"))
    )
    (net (code "96") (name "Net-(Header7-Pad12)") (class "Default")
      (node (ref "Header7") (pin "12") (pintype "input"))
      (node (ref "R99") (pin "2") (pinfunction "2_2") (pintype "passive"))
    )
    (net (code "97") (name "Net-(Header7-Pad13)") (class "Default")
      (node (ref "Header7") (pin "13") (pintype "input"))
      (node (ref "R101") (pin "1") (pinfunction "1_1") (pintype "passive"))
    )
    (net (code "98") (name "Net-(Header7-Pad14)") (class "Default")
      (node (ref "Header7") (pin "14") (pintype "input"))
      (node (ref "R102") (pin "1") (pinfunction "1_1") (pintype "passive"))
    )
    (net (code "99") (name "Net-(Header7-Pad15)") (class "Default")
      (node (ref "Header7") (pin "15") (pintype "input"))
      (node (ref "R103") (pin "1") (pinfunction "1_1") (pintype "passive"))
    )
    (net (code "100") (name "Net-(Header7-Pad16)") (class "Default")
      (node (ref "Header7") (pin "16") (pintype "input"))
      (node (ref "R104") (pin "1") (pinfunction "1_1") (pintype "passive"))
    )
    (net (code "101") (name "Net-(Header7-Pad17)") (class "Default")
      (node (ref "Header7") (pin "17") (pintype "input"))
      (node (ref "R105") (pin "1") (pinfunction "1_1") (pintype "passive"))
    )
    (net (code "102") (name "Net-(Header7-Pad18)") (class "Default")
      (node (ref "Header7") (pin "18") (pintype "input"))
      (node (ref "R106") (pin "1") (pinfunction "1_1") (pintype "passive"))
    )
    (net (code "103") (name "Net-(Header7-Pad19)") (class "Default")
      (node (ref "Header7") (pin "19") (pintype "input"))
      (node (ref "R107") (pin "1") (pinfunction "1_1") (pintype "passive"))
    )
    (net (code "104") (name "Net-(Header7-Pad23)") (class "Default")
      (node (ref "Header7") (pin "23") (pintype "input"))
      (node (ref "R108") (pin "1") (pinfunction "1_1") (pintype "passive"))
    )
    (net (code "105") (name "Net-(Header7-Pad24)") (class "Default")
      (node (ref "Header7") (pin "24") (pintype "input"))
      (node (ref "R109") (pin "1") (pinfunction "1_1") (pintype "passive"))
    )
    (net (code "106") (name "Net-(Header8-Pad1)") (class "Default")
      (node (ref "Header8") (pin "1") (pintype "input"))
      (node (ref "R110") (pin "1") (pinfunction "1_1") (pintype "passive"))
    )
    (net (code "107") (name "Net-(Header8-Pad2)") (class "Default")
      (node (ref "Header8") (pin "2") (pintype "input"))
      (node (ref "R111") (pin "1") (pinfunction "1_1") (pintype "passive"))
    )
    (net (code "108") (name "Net-(Header8-Pad3)") (class "Default")
      (node (ref "Header8") (pin "3") (pintype "input"))
      (node (ref "R112") (pin "1") (pinfunction "1_1") (pintype "passive"))
    )
    (net (code "109") (name "Net-(Header8-Pad4)") (class "Default")
      (node (ref "Header8") (pin "4") (pintype "input"))
      (node (ref "R113") (pin "1") (pinfunction "1_1") (pintype "passive"))
    )
    (net (code "110") (name "Net-(Header8-Pad5)") (class "Default")
      (node (ref "Header8") (pin "5") (pintype "input"))
      (node (ref "R114") (pin "1") (pinfunction "1_1") (pintype "passive"))
    )
    (net (code "111") (name "Net-(Header8-Pad6)") (class "Default")
      (node (ref "Header8") (pin "6") (pintype "input"))
      (node (ref "R115") (pin "1") (pinfunction "1_1") (pintype "passive"))
    )
    (net (code "112") (name "Net-(Header8-Pad7)") (class "Default")
      (node (ref "Header8") (pin "7") (pintype "input"))
      (node (ref "R116") (pin "1") (pinfunction "1_1") (pintype "passive"))
    )
    (net (code "113") (name "Net-(Header8-Pad8)") (class "Default")
      (node (ref "Header8") (pin "8") (pintype "input"))
      (node (ref "R117") (pin "1") (pinfunction "1_1") (pintype "passive"))
    )
    (net (code "114") (name "Net-(Header8-Pad9)") (class "Default")
      (node (ref "Header8") (pin "9") (pintype "input"))
      (node (ref "R118") (pin "1") (pinfunction "1_1") (pintype "passive"))
    )
    (net (code "115") (name "Net-(Header8-Pad10)") (class "Default")
      (node (ref "Header8") (pin "10") (pintype "input"))
      (node (ref "R119") (pin "1") (pinfunction "1_1") (pintype "passive"))
    )
    (net (code "116") (name "Net-(Header8-Pad11)") (class "Default")
      (node (ref "Header8") (pin "11") (pintype "input"))
      (node (ref "R120") (pin "1") (pinfunction "1_1") (pintype "passive"))
    )
    (net (code "117") (name "Net-(Header8-Pad12)") (class "Default")
      (node (ref "Header8") (pin "12") (pintype "input"))
      (node (ref "R121") (pin "1") (pinfunction "1_1") (pintype "passive"))
    )
    (net (code "118") (name "Net-(Header8-Pad13)") (class "Default")
      (node (ref "Header8") (pin "13") (pintype "input"))
      (node (ref "R122") (pin "1") (pinfunction "1_1") (pintype "passive"))
    )
    (net (code "119") (name "Net-(Header8-Pad14)") (class "Default")
      (node (ref "Header8") (pin "14") (pintype "input"))
      (node (ref "R123") (pin "1") (pinfunction "1_1") (pintype "passive"))
    )
    (net (code "120") (name "Net-(Header8-Pad18)") (class "Default")
      (node (ref "Header8") (pin "18") (pintype "input"))
      (node (ref "R124") (pin "1") (pinfunction "1_1") (pintype "passive"))
    )
    (net (code "121") (name "Net-(Header8-Pad19)") (class "Default")
      (node (ref "Header8") (pin "19") (pintype "input"))
      (node (ref "R126") (pin "2") (pinfunction "2_2") (pintype "passive"))
    )
    (net (code "122") (name "Net-(Header8-Pad20)") (class "Default")
      (node (ref "Header8") (pin "20") (pintype "input"))
      (node (ref "R127") (pin "2") (pinfunction "2_2") (pintype "passive"))
    )
    (net (code "123") (name "Net-(Header8-Pad21)") (class "Default")
      (node (ref "Header8") (pin "21") (pintype "input"))
      (node (ref "R128") (pin "2") (pinfunction "2_2") (pintype "passive"))
    )
    (net (code "124") (name "Net-(Header8-Pad22)") (class "Default")
      (node (ref "Header8") (pin "22") (pintype "input"))
      (node (ref "R129") (pin "2") (pinfunction "2_2") (pintype "passive"))
    )
    (net (code "125") (name "Net-(Header8-Pad23)") (class "Default")
      (node (ref "Header8") (pin "23") (pintype "input"))
      (node (ref "R130") (pin "2") (pinfunction "2_2") (pintype "passive"))
    )
    (net (code "126") (name "Net-(Header8-Pad24)") (class "Default")
      (node (ref "Header8") (pin "24") (pintype "input"))
      (node (ref "R131") (pin "2") (pinfunction "2_2") (pintype "passive"))
    )
    (net (code "127") (name "Net-(Header9-Pad1)") (class "Default")
      (node (ref "Header9") (pin "1") (pintype "input"))
      (node (ref "R132") (pin "2") (pinfunction "2_2") (pintype "passive"))
    )
    (net (code "128") (name "Net-(Header9-Pad2)") (class "Default")
      (node (ref "Header9") (pin "2") (pintype "input"))
      (node (ref "R133") (pin "2") (pinfunction "2_2") (pintype "passive"))
    )
    (net (code "129") (name "Net-(Header9-Pad3)") (class "Default")
      (node (ref "Header9") (pin "3") (pintype "input"))
      (node (ref "R134") (pin "2") (pinfunction "2_2") (pintype "passive"))
    )
    (net (code "130") (name "Net-(Header9-Pad4)") (class "Default")
      (node (ref "Header9") (pin "4") (pintype "input"))
      (node (ref "R135") (pin "2") (pinfunction "2_2") (pintype "passive"))
    )
    (net (code "131") (name "Net-(Header9-Pad5)") (class "Default")
      (node (ref "Header9") (pin "5") (pintype "input"))
      (node (ref "R136") (pin "2") (pinfunction "2_2") (pintype "passive"))
    )
    (net (code "132") (name "Net-(Header9-Pad6)") (class "Default")
      (node (ref "Header9") (pin "6") (pintype "input"))
      (node (ref "R137") (pin "2") (pinfunction "2_2") (pintype "passive"))
    )
    (net (code "133") (name "Net-(Header9-Pad7)") (class "Default")
      (node (ref "Header9") (pin "7") (pintype "input"))
      (node (ref "R138") (pin "2") (pinfunction "2_2") (pintype "passive"))
    )
    (net (code "134") (name "Net-(Header9-Pad8)") (class "Default")
      (node (ref "Header9") (pin "8") (pintype "input"))
      (node (ref "R139") (pin "2") (pinfunction "2_2") (pintype "passive"))
    )
    (net (code "135") (name "Net-(Header9-Pad9)") (class "Default")
      (node (ref "Header9") (pin "9") (pintype "input"))
      (node (ref "R140") (pin "2") (pinfunction "2_2") (pintype "passive"))
    )
    (net (code "136") (name "Net-(Header9-Pad10)") (class "Default")
      (node (ref "Header9") (pin "10") (pintype "input"))
      (node (ref "R141") (pin "2") (pinfunction "2_2") (pintype "passive"))
    )
    (net (code "137") (name "Net-(Header9-Pad11)") (class "Default")
      (node (ref "Header9") (pin "11") (pintype "input"))
      (node (ref "R142") (pin "2") (pinfunction "2_2") (pintype "passive"))
    )
    (net (code "138") (name "Net-(Header9-Pad12)") (class "Default")
      (node (ref "Header9") (pin "12") (pintype "input"))
      (node (ref "R143") (pin "2") (pinfunction "2_2") (pintype "passive"))
    )
    (net (code "139") (name "Net-(Header9-Pad13)") (class "Default")
      (node (ref "Header9") (pin "13") (pintype "input"))
      (node (ref "R144") (pin "2") (pinfunction "2_2") (pintype "passive"))
    )
    (net (code "140") (name "Net-(Header9-Pad14)") (class "Default")
      (node (ref "Header9") (pin "14") (pintype "input"))
      (node (ref "R145") (pin "2") (pinfunction "2_2") (pintype "passive"))
    )
    (net (code "141") (name "Net-(Header9-Pad15)") (class "Default")
      (node (ref "Header9") (pin "15") (pintype "input"))
      (node (ref "R146") (pin "2") (pinfunction "2_2") (pintype "passive"))
    )
    (net (code "142") (name "Net-(Header9-Pad16)") (class "Default")
      (node (ref "Header9") (pin "16") (pintype "input"))
      (node (ref "R147") (pin "2") (pinfunction "2_2") (pintype "passive"))
    )
    (net (code "143") (name "Net-(Header9-Pad17)") (class "Default")
      (node (ref "Header9") (pin "17") (pintype "input"))
      (node (ref "R148") (pin "2") (pinfunction "2_2") (pintype "passive"))
    )
    (net (code "144") (name "Net-(Header9-Pad18)") (class "Default")
      (node (ref "Header9") (pin "18") (pintype "input"))
      (node (ref "R149") (pin "2") (pinfunction "2_2") (pintype "passive"))
    )
    (net (code "145") (name "Net-(Header9-Pad19)") (class "Default")
      (node (ref "Header9") (pin "19") (pintype "input"))
      (node (ref "R151") (pin "1") (pinfunction "1_1") (pintype "passive"))
    )
    (net (code "146") (name "Net-(Header9-Pad23)") (class "Default")
      (node (ref "Header9") (pin "23") (pintype "input"))
      (node (ref "R152") (pin "1") (pinfunction "1_1") (pintype "passive"))
    )
    (net (code "147") (name "Net-(Header9-Pad24)") (class "Default")
      (node (ref "Header9") (pin "24") (pintype "input"))
      (node (ref "R153") (pin "1") (pinfunction "1_1") (pintype "passive"))
    )
    (net (code "148") (name "Net-(Header10-Pad1)") (class "Default")
      (node (ref "Header10") (pin "1") (pintype "input"))
      (node (ref "R154") (pin "1") (pinfunction "1_1") (pintype "passive"))
    )
    (net (code "149") (name "Net-(Header10-Pad2)") (class "Default")
      (node (ref "Header10") (pin "2") (pintype "input"))
      (node (ref "R155") (pin "1") (pinfunction "1_1") (pintype "passive"))
    )
    (net (code "150") (name "Net-(Header10-Pad3)") (class "Default")
      (node (ref "Header10") (pin "3") (pintype "input"))
      (node (ref "R156") (pin "1") (pinfunction "1_1") (pintype "passive"))
    )
    (net (code "151") (name "Net-(Header10-Pad4)") (class "Default")
      (node (ref "Header10") (pin "4") (pintype "input"))
      (node (ref "R157") (pin "1") (pinfunction "1_1") (pintype "passive"))
    )
    (net (code "152") (name "Net-(Header10-Pad5)") (class "Default")
      (node (ref "Header10") (pin "5") (pintype "input"))
      (node (ref "R158") (pin "1") (pinfunction "1_1") (pintype "passive"))
    )
    (net (code "153") (name "Net-(Header10-Pad6)") (class "Default")
      (node (ref "Header10") (pin "6") (pintype "input"))
      (node (ref "R159") (pin "1") (pinfunction "1_1") (pintype "passive"))
    )
    (net (code "154") (name "Net-(Header10-Pad7)") (class "Default")
      (node (ref "Header10") (pin "7") (pintype "input"))
      (node (ref "R160") (pin "1") (pinfunction "1_1") (pintype "passive"))
    )
    (net (code "155") (name "Net-(Header10-Pad8)") (class "Default")
      (node (ref "Header10") (pin "8") (pintype "input"))
      (node (ref "R161") (pin "1") (pinfunction "1_1") (pintype "passive"))
    )
    (net (code "156") (name "Net-(Header10-Pad9)") (class "Default")
      (node (ref "Header10") (pin "9") (pintype "input"))
      (node (ref "R162") (pin "1") (pinfunction "1_1") (pintype "passive"))
    )
    (net (code "157") (name "Net-(Header10-Pad10)") (class "Default")
      (node (ref "Header10") (pin "10") (pintype "input"))
      (node (ref "R163") (pin "1") (pinfunction "1_1") (pintype "passive"))
    )
    (net (code "158") (name "Net-(Header10-Pad11)") (class "Default")
      (node (ref "Header10") (pin "11") (pintype "input"))
      (node (ref "R164") (pin "1") (pinfunction "1_1") (pintype "passive"))
    )
    (net (code "159") (name "Net-(Header10-Pad12)") (class "Default")
      (node (ref "Header10") (pin "12") (pintype "input"))
      (node (ref "R165") (pin "1") (pinfunction "1_1") (pintype "passive"))
    )
    (net (code "160") (name "Net-(Header10-Pad13)") (class "Default")
      (node (ref "Header10") (pin "13") (pintype "input"))
      (node (ref "R166") (pin "1") (pinfunction "1_1") (pintype "passive"))
    )
    (net (code "161") (name "Net-(Header10-Pad14)") (class "Default")
      (node (ref "Header10") (pin "14") (pintype "input"))
      (node (ref "R167") (pin "1") (pinfunction "1_1") (pintype "passive"))
    )
    (net (code "162") (name "Net-(Header10-Pad18)") (class "Default")
      (node (ref "Header10") (pin "18") (pintype "input"))
      (node (ref "R168") (pin "1") (pinfunction "1_1") (pintype "passive"))
    )
    (net (code "163") (name "Net-(Header10-Pad19)") (class "Default")
      (node (ref "Header10") (pin "19") (pintype "input"))
      (node (ref "R169") (pin "1") (pinfunction "1_1") (pintype "passive"))
    )
    (net (code "164") (name "Net-(Header10-Pad20)") (class "Default")
      (node (ref "Header10") (pin "20") (pintype "input"))
      (node (ref "R170") (pin "1") (pinfunction "1_1") (pintype "passive"))
    )
    (net (code "165") (name "Net-(Header10-Pad21)") (class "Default")
      (node (ref "Header10") (pin "21") (pintype "input"))
      (node (ref "R171") (pin "1") (pinfunction "1_1") (pintype "passive"))
    )
    (net (code "166") (name "Net-(Header10-Pad22)") (class "Default")
      (node (ref "Header10") (pin "22") (pintype "input"))
      (node (ref "R172") (pin "1") (pinfunction "1_1") (pintype "passive"))
    )
    (net (code "167") (name "Net-(Header10-Pad23)") (class "Default")
      (node (ref "Header10") (pin "23") (pintype "input"))
      (node (ref "R173") (pin "1") (pinfunction "1_1") (pintype "passive"))
    )
    (net (code "168") (name "Net-(Header10-Pad24)") (class "Default")
      (node (ref "Header10") (pin "24") (pintype "input"))
      (node (ref "R174") (pin "1") (pinfunction "1_1") (pintype "passive"))
    )
    (net (code "169") (name "Net-(Header11-Pad1)") (class "Default")
      (node (ref "Header11") (pin "1") (pintype "input"))
      (node (ref "R176") (pin "2") (pinfunction "2_2") (pintype "passive"))
    )
    (net (code "170") (name "Net-(Header11-Pad2)") (class "Default")
      (node (ref "Header11") (pin "2") (pintype "input"))
      (node (ref "R177") (pin "2") (pinfunction "2_2") (pintype "passive"))
    )
    (net (code "171") (name "Net-(Header11-Pad3)") (class "Default")
      (node (ref "Header11") (pin "3") (pintype "input"))
      (node (ref "R178") (pin "2") (pinfunction "2_2") (pintype "passive"))
    )
    (net (code "172") (name "Net-(Header11-Pad4)") (class "Default")
      (node (ref "Header11") (pin "4") (pintype "input"))
      (node (ref "R179") (pin "2") (pinfunction "2_2") (pintype "passive"))
    )
    (net (code "173") (name "Net-(Header11-Pad5)") (class "Default")
      (node (ref "Header11") (pin "5") (pintype "input"))
      (node (ref "R180") (pin "2") (pinfunction "2_2") (pintype "passive"))
    )
    (net (code "174") (name "Net-(Header11-Pad6)") (class "Default")
      (node (ref "Header11") (pin "6") (pintype "input"))
      (node (ref "R181") (pin "2") (pinfunction "2_2") (pintype "passive"))
    )
    (net (code "175") (name "Net-(Header11-Pad7)") (class "Default")
      (node (ref "Header11") (pin "7") (pintype "input"))
      (node (ref "R182") (pin "2") (pinfunction "2_2") (pintype "passive"))
    )
    (net (code "176") (name "Net-(Header11-Pad8)") (class "Default")
      (node (ref "Header11") (pin "8") (pintype "input"))
      (node (ref "R183") (pin "2") (pinfunction "2_2") (pintype "passive"))
    )
    (net (code "177") (name "Net-(Header11-Pad9)") (class "Default")
      (node (ref "Header11") (pin "9") (pintype "input"))
      (node (ref "R184") (pin "2") (pinfunction "2_2") (pintype "passive"))
    )
    (net (code "178") (name "Net-(Header11-Pad10)") (class "Default")
      (node (ref "Header11") (pin "10") (pintype "input"))
      (node (ref "R185") (pin "2") (pinfunction "2_2") (pintype "passive"))
    )
    (net (code "179") (name "Net-(Header11-Pad11)") (class "Default")
      (node (ref "Header11") (pin "11") (pintype "input"))
      (node (ref "R186") (pin "2") (pinfunction "2_2") (pintype "passive"))
    )
    (net (code "180") (name "Net-(Header11-Pad12)") (class "Default")
      (node (ref "Header11") (pin "12") (pintype "input"))
      (node (ref "R187") (pin "2") (pinfunction "2_2") (pintype "passive"))
    )
    (net (code "181") (name "Net-(Header11-Pad13)") (class "Default")
      (node (ref "Header11") (pin "13") (pintype "input"))
      (node (ref "R188") (pin "2") (pinfunction "2_2") (pintype "passive"))
    )
    (net (code "182") (name "Net-(Header11-Pad14)") (class "Default")
      (node (ref "Header11") (pin "14") (pintype "input"))
      (node (ref "R189") (pin "2") (pinfunction "2_2") (pintype "passive"))
    )
    (net (code "183") (name "Net-(Header11-Pad15)") (class "Default")
      (node (ref "Header11") (pin "15") (pintype "input"))
      (node (ref "R190") (pin "2") (pinfunction "2_2") (pintype "passive"))
    )
    (net (code "184") (name "Net-(Header11-Pad16)") (class "Default")
      (node (ref "Header11") (pin "16") (pintype "input"))
      (node (ref "R191") (pin "2") (pinfunction "2_2") (pintype "passive"))
    )
    (net (code "185") (name "Net-(Header11-Pad17)") (class "Default")
      (node (ref "Header11") (pin "17") (pintype "input"))
      (node (ref "R192") (pin "2") (pinfunction "2_2") (pintype "passive"))
    )
    (net (code "186") (name "Net-(Header11-Pad18)") (class "Default")
      (node (ref "Header11") (pin "18") (pintype "input"))
      (node (ref "R193") (pin "2") (pinfunction "2_2") (pintype "passive"))
    )
    (net (code "187") (name "Net-(Header11-Pad19)") (class "Default")
      (node (ref "Header11") (pin "19") (pintype "input"))
      (node (ref "R194") (pin "2") (pinfunction "2_2") (pintype "passive"))
    )
    (net (code "188") (name "Net-(Header11-Pad20)") (class "Default")
      (node (ref "Header11") (pin "20") (pintype "input"))
      (node (ref "R195") (pin "2") (pinfunction "2_2") (pintype "passive"))
    )
    (net (code "189") (name "Net-(Header11-Pad21)") (class "Default")
      (node (ref "Header11") (pin "21") (pintype "input"))
      (node (ref "R196") (pin "2") (pinfunction "2_2") (pintype "passive"))
    )
    (net (code "190") (name "Net-(Header11-Pad22)") (class "Default")
      (node (ref "Header11") (pin "22") (pintype "input"))
      (node (ref "R197") (pin "2") (pinfunction "2_2") (pintype "passive"))
    )
    (net (code "191") (name "Net-(Header11-Pad23)") (class "Default")
      (node (ref "Header11") (pin "23") (pintype "input"))
      (node (ref "R198") (pin "2") (pinfunction "2_2") (pintype "passive"))
    )
    (net (code "192") (name "Net-(Header11-Pad24)") (class "Default")
      (node (ref "Header11") (pin "24") (pintype "input"))
      (node (ref "R199") (pin "2") (pinfunction "2_2") (pintype "passive"))
    )
    (net (code "193") (name "Net-(Header12-Pad1)") (class "Default")
      (node (ref "Header12") (pin "1") (pintype "input"))
      (node (ref "R201") (pin "1") (pinfunction "1_1") (pintype "passive"))
    )
    (net (code "194") (name "Net-(Header12-Pad2)") (class "Default")
      (node (ref "Header12") (pin "2") (pintype "input"))
      (node (ref "R202") (pin "1") (pinfunction "1_1") (pintype "passive"))
    )
    (net (code "195") (name "Net-(Header12-Pad3)") (class "Default")
      (node (ref "Header12") (pin "3") (pintype "input"))
      (node (ref "R203") (pin "1") (pinfunction "1_1") (pintype "passive"))
    )
    (net (code "196") (name "Net-(Header12-Pad4)") (class "Default")
      (node (ref "Header12") (pin "4") (pintype "input"))
      (node (ref "R204") (pin "1") (pinfunction "1_1") (pintype "passive"))
    )
    (net (code "197") (name "Net-(Header12-Pad5)") (class "Default")
      (node (ref "Header12") (pin "5") (pintype "input"))
      (node (ref "R205") (pin "1") (pinfunction "1_1") (pintype "passive"))
    )
    (net (code "198") (name "Net-(Header12-Pad6)") (class "Default")
      (node (ref "Header12") (pin "6") (pintype "input"))
      (node (ref "R206") (pin "1") (pinfunction "1_1") (pintype "passive"))
    )
    (net (code "199") (name "Net-(Header12-Pad7)") (class "Default")
      (node (ref "Header12") (pin "7") (pintype "input"))
      (node (ref "R207") (pin "1") (pinfunction "1_1") (pintype "passive"))
    )
    (net (code "200") (name "Net-(Header12-Pad8)") (class "Default")
      (node (ref "Header12") (pin "8") (pintype "input"))
      (node (ref "R208") (pin "1") (pinfunction "1_1") (pintype "passive"))
    )
    (net (code "201") (name "Net-(Header12-Pad9)") (class "Default")
      (node (ref "Header12") (pin "9") (pintype "input"))
      (node (ref "R209") (pin "1") (pinfunction "1_1") (pintype "passive"))
    )
    (net (code "202") (name "Net-(Header12-Pad10)") (class "Default")
      (node (ref "Header12") (pin "10") (pintype "input"))
      (node (ref "R210") (pin "1") (pinfunction "1_1") (pintype "passive"))
    )
    (net (code "203") (name "Net-(Header12-Pad11)") (class "Default")
      (node (ref "Header12") (pin "11") (pintype "input"))
      (node (ref "R211") (pin "1") (pinfunction "1_1") (pintype "passive"))
    )
    (net (code "204") (name "Net-(Header12-Pad12)") (class "Default")
      (node (ref "Header12") (pin "12") (pintype "input"))
      (node (ref "R212") (pin "1") (pinfunction "1_1") (pintype "passive"))
    )
    (net (code "205") (name "Net-(Header12-Pad13)") (class "Default")
      (node (ref "Header12") (pin "13") (pintype "input"))
      (node (ref "R213") (pin "1") (pinfunction "1_1") (pintype "passive"))
    )
    (net (code "206") (name "Net-(Header12-Pad14)") (class "Default")
      (node (ref "Header12") (pin "14") (pintype "input"))
      (node (ref "R214") (pin "1") (pinfunction "1_1") (pintype "passive"))
    )
    (net (code "207") (name "Net-(Header12-Pad15)") (class "Default")
      (node (ref "Header12") (pin "15") (pintype "input"))
      (node (ref "R215") (pin "1") (pinfunction "1_1") (pintype "passive"))
    )
    (net (code "208") (name "Net-(Header12-Pad16)") (class "Default")
      (node (ref "Header12") (pin "16") (pintype "input"))
      (node (ref "R216") (pin "1") (pinfunction "1_1") (pintype "passive"))
    )
    (net (code "209") (name "Net-(Header12-Pad17)") (class "Default")
      (node (ref "Header12") (pin "17") (pintype "input"))
      (node (ref "R217") (pin "1") (pinfunction "1_1") (pintype "passive"))
    )
    (net (code "210") (name "Net-(Header12-Pad18)") (class "Default")
      (node (ref "Header12") (pin "18") (pintype "input"))
      (node (ref "R218") (pin "1") (pinfunction "1_1") (pintype "passive"))
    )
    (net (code "211") (name "Net-(Header12-Pad19)") (class "Default")
      (node (ref "Header12") (pin "19") (pintype "input"))
      (node (ref "R219") (pin "1") (pinfunction "1_1") (pintype "passive"))
    )
    (net (code "212") (name "Net-(Header12-Pad20)") (class "Default")
      (node (ref "Header12") (pin "20") (pintype "input"))
      (node (ref "R220") (pin "1") (pinfunction "1_1") (pintype "passive"))
    )
    (net (code "213") (name "Net-(Header12-Pad21)") (class "Default")
      (node (ref "Header12") (pin "21") (pintype "input"))
      (node (ref "R221") (pin "1") (pinfunction "1_1") (pintype "passive"))
    )
    (net (code "214") (name "Net-(Header12-Pad22)") (class "Default")
      (node (ref "Header12") (pin "22") (pintype "input"))
      (node (ref "R222") (pin "1") (pinfunction "1_1") (pintype "passive"))
    )
    (net (code "215") (name "Net-(Header12-Pad23)") (class "Default")
      (node (ref "Header12") (pin "23") (pintype "input"))
      (node (ref "R223") (pin "1") (pinfunction "1_1") (pintype "passive"))
    )
    (net (code "216") (name "Net-(Header12-Pad24)") (class "Default")
      (node (ref "Header12") (pin "24") (pintype "input"))
      (node (ref "R224") (pin "1") (pinfunction "1_1") (pintype "passive"))
    )
    (net (code "217") (name "Net-(Header13-Pad1)") (class "Default")
      (node (ref "Header13") (pin "1") (pintype "input"))
      (node (ref "R226") (pin "2") (pinfunction "2_2") (pintype "passive"))
    )
    (net (code "218") (name "Net-(Header13-Pad2)") (class "Default")
      (node (ref "Header13") (pin "2") (pintype "input"))
      (node (ref "R227") (pin "2") (pinfunction "2_2") (pintype "passive"))
    )
    (net (code "219") (name "Net-(Header13-Pad3)") (class "Default")
      (node (ref "Header13") (pin "3") (pintype "input"))
      (node (ref "R228") (pin "2") (pinfunction "2_2") (pintype "passive"))
    )
    (net (code "220") (name "Net-(Header13-Pad4)") (class "Default")
      (node (ref "Header13") (pin "4") (pintype "input"))
      (node (ref "R229") (pin "2") (pinfunction "2_2") (pintype "passive"))
    )
    (net (code "221") (name "Net-(Header13-Pad5)") (class "Default")
      (node (ref "Header13") (pin "5") (pintype "input"))
      (node (ref "R230") (pin "2") (pinfunction "2_2") (pintype "passive"))
    )
    (net (code "222") (name "Net-(Header13-Pad6)") (class "Default")
      (node (ref "Header13") (pin "6") (pintype "input"))
      (node (ref "R231") (pin "2") (pinfunction "2_2") (pintype "passive"))
    )
    (net (code "223") (name "Net-(Header13-Pad7)") (class "Default")
      (node (ref "Header13") (pin "7") (pintype "input"))
      (node (ref "R232") (pin "2") (pinfunction "2_2") (pintype "passive"))
    )
    (net (code "224") (name "Net-(Header13-Pad8)") (class "Default")
      (node (ref "Header13") (pin "8") (pintype "input"))
      (node (ref "R233") (pin "2") (pinfunction "2_2") (pintype "passive"))
    )
    (net (code "225") (name "Net-(Header13-Pad9)") (class "Default")
      (node (ref "Header13") (pin "9") (pintype "input"))
      (node (ref "R234") (pin "2") (pinfunction "2_2") (pintype "passive"))
    )
    (net (code "226") (name "Net-(Header13-Pad10)") (class "Default")
      (node (ref "Header13") (pin "10") (pintype "input"))
      (node (ref "R235") (pin "2") (pinfunction "2_2") (pintype "passive"))
    )
    (net (code "227") (name "Net-(Header13-Pad11)") (class "Default")
      (node (ref "Header13") (pin "11") (pintype "input"))
      (node (ref "R236") (pin "2") (pinfunction "2_2") (pintype "passive"))
    )
    (net (code "228") (name "Net-(Header13-Pad12)") (class "Default")
      (node (ref "Header13") (pin "12") (pintype "input"))
      (node (ref "R237") (pin "2") (pinfunction "2_2") (pintype "passive"))
    )
    (net (code "229") (name "Net-(Header13-Pad13)") (class "Default")
      (node (ref "Header13") (pin "13") (pintype "input"))
      (node (ref "R238") (pin "2") (pinfunction "2_2") (pintype "passive"))
    )
    (net (code "230") (name "Net-(Header13-Pad14)") (class "Default")
      (node (ref "Header13") (pin "14") (pintype "input"))
      (node (ref "R239") (pin "2") (pinfunction "2_2") (pintype "passive"))
    )
    (net (code "231") (name "Net-(Header13-Pad15)") (class "Default")
      (node (ref "Header13") (pin "15") (pintype "input"))
      (node (ref "R240") (pin "2") (pinfunction "2_2") (pintype "passive"))
    )
    (net (code "232") (name "Net-(Header13-Pad16)") (class "Default")
      (node (ref "Header13") (pin "16") (pintype "input"))
      (node (ref "R241") (pin "2") (pinfunction "2_2") (pintype "passive"))
    )
    (net (code "233") (name "Net-(Header13-Pad17)") (class "Default")
      (node (ref "Header13") (pin "17") (pintype "input"))
      (node (ref "R242") (pin "2") (pinfunction "2_2") (pintype "passive"))
    )
    (net (code "234") (name "Net-(Header13-Pad18)") (class "Default")
      (node (ref "Header13") (pin "18") (pintype "input"))
      (node (ref "R243") (pin "2") (pinfunction "2_2") (pintype "passive"))
    )
    (net (code "235") (name "Net-(Header13-Pad19)") (class "Default")
      (node (ref "Header13") (pin "19") (pintype "input"))
      (node (ref "R244") (pin "2") (pinfunction "2_2") (pintype "passive"))
    )
    (net (code "236") (name "Net-(Header13-Pad20)") (class "Default")
      (node (ref "Header13") (pin "20") (pintype "input"))
      (node (ref "R245") (pin "2") (pinfunction "2_2") (pintype "passive"))
    )
    (net (code "237") (name "Net-(Header13-Pad21)") (class "Default")
      (node (ref "Header13") (pin "21") (pintype "input"))
      (node (ref "R246") (pin "2") (pinfunction "2_2") (pintype "passive"))
    )
    (net (code "238") (name "Net-(Header13-Pad22)") (class "Default")
      (node (ref "Header13") (pin "22") (pintype "input"))
      (node (ref "R247") (pin "2") (pinfunction "2_2") (pintype "passive"))
    )
    (net (code "239") (name "Net-(Header13-Pad23)") (class "Default")
      (node (ref "Header13") (pin "23") (pintype "input"))
      (node (ref "R248") (pin "2") (pinfunction "2_2") (pintype "passive"))
    )
    (net (code "240") (name "Net-(Header13-Pad24)") (class "Default")
      (node (ref "Header13") (pin "24") (pintype "input"))
      (node (ref "R249") (pin "2") (pinfunction "2_2") (pintype "passive"))
    )
    (net (code "241") (name "Net-(Header14-Pad1)") (class "Default")
      (node (ref "Header14") (pin "1") (pintype "input"))
      (node (ref "R251") (pin "1") (pinfunction "1_1") (pintype "passive"))
    )
    (net (code "242") (name "Net-(Header14-Pad2)") (class "Default")
      (node (ref "Header14") (pin "2") (pintype "input"))
      (node (ref "R252") (pin "1") (pinfunction "1_1") (pintype "passive"))
    )
    (net (code "243") (name "Net-(Header14-Pad3)") (class "Default")
      (node (ref "Header14") (pin "3") (pintype "input"))
      (node (ref "R253") (pin "1") (pinfunction "1_1") (pintype "passive"))
    )
    (net (code "244") (name "Net-(Header14-Pad4)") (class "Default")
      (node (ref "Header14") (pin "4") (pintype "input"))
      (node (ref "R254") (pin "1") (pinfunction "1_1") (pintype "passive"))
    )
    (net (code "245") (name "Net-(Header14-Pad5)") (class "Default")
      (node (ref "Header14") (pin "5") (pintype "input"))
      (node (ref "R255") (pin "1") (pinfunction "1_1") (pintype "passive"))
    )
    (net (code "246") (name "Net-(Header14-Pad6)") (class "Default")
      (node (ref "Header14") (pin "6") (pintype "input"))
      (node (ref "R256") (pin "1") (pinfunction "1_1") (pintype "passive"))
    )
    (net (code "247") (name "Net-(Header14-Pad7)") (class "Default")
      (node (ref "Header14") (pin "7") (pintype "input"))
      (node (ref "R257") (pin "1") (pinfunction "1_1") (pintype "passive"))
    )
    (net (code "248") (name "Net-(Header14-Pad8)") (class "Default")
      (node (ref "Header14") (pin "8") (pintype "input"))
      (node (ref "R258") (pin "1") (pinfunction "1_1") (pintype "passive"))
    )
    (net (code "249") (name "Net-(Header14-Pad9)") (class "Default")
      (node (ref "Header14") (pin "9") (pintype "input"))
      (node (ref "R259") (pin "1") (pinfunction "1_1") (pintype "passive"))
    )
    (net (code "250") (name "Net-(Header14-Pad10)") (class "Default")
      (node (ref "Header14") (pin "10") (pintype "input"))
      (node (ref "R260") (pin "1") (pinfunction "1_1") (pintype "passive"))
    )
    (net (code "251") (name "Net-(Header14-Pad11)") (class "Default")
      (node (ref "Header14") (pin "11") (pintype "input"))
      (node (ref "R261") (pin "1") (pinfunction "1_1") (pintype "passive"))
    )
    (net (code "252") (name "Net-(Header14-Pad12)") (class "Default")
      (node (ref "Header14") (pin "12") (pintype "input"))
      (node (ref "R262") (pin "1") (pinfunction "1_1") (pintype "passive"))
    )
    (net (code "253") (name "Net-(Header14-Pad13)") (class "Default")
      (node (ref "Header14") (pin "13") (pintype "input"))
      (node (ref "R263") (pin "1") (pinfunction "1_1") (pintype "passive"))
    )
    (net (code "254") (name "Net-(Header14-Pad14)") (class "Default")
      (node (ref "Header14") (pin "14") (pintype "input"))
      (node (ref "R264") (pin "1") (pinfunction "1_1") (pintype "passive"))
    )
    (net (code "255") (name "Net-(Header14-Pad15)") (class "Default")
      (node (ref "Header14") (pin "15") (pintype "input"))
      (node (ref "R265") (pin "1") (pinfunction "1_1") (pintype "passive"))
    )
    (net (code "256") (name "Net-(Header14-Pad16)") (class "Default")
      (node (ref "Header14") (pin "16") (pintype "input"))
      (node (ref "R266") (pin "1") (pinfunction "1_1") (pintype "passive"))
    )
    (net (code "257") (name "Net-(Header14-Pad17)") (class "Default")
      (node (ref "Header14") (pin "17") (pintype "input"))
      (node (ref "R267") (pin "1") (pinfunction "1_1") (pintype "passive"))
    )
    (net (code "258") (name "Net-(Header14-Pad18)") (class "Default")
      (node (ref "Header14") (pin "18") (pintype "input"))
      (node (ref "R268") (pin "1") (pinfunction "1_1") (pintype "passive"))
    )
    (net (code "259") (name "Net-(Header14-Pad19)") (class "Default")
      (node (ref "Header14") (pin "19") (pintype "input"))
      (node (ref "R269") (pin "1") (pinfunction "1_1") (pintype "passive"))
    )
    (net (code "260") (name "Net-(Header14-Pad20)") (class "Default")
      (node (ref "Header14") (pin "20") (pintype "input"))
      (node (ref "R270") (pin "1") (pinfunction "1_1") (pintype "passive"))
    )
    (net (code "261") (name "Net-(Header14-Pad21)") (class "Default")
      (node (ref "Header14") (pin "21") (pintype "input"))
      (node (ref "R271") (pin "1") (pinfunction "1_1") (pintype "passive"))
    )
    (net (code "262") (name "Net-(Header14-Pad22)") (class "Default")
      (node (ref "Header14") (pin "22") (pintype "input"))
      (node (ref "R272") (pin "1") (pinfunction "1_1") (pintype "passive"))
    )
    (net (code "263") (name "Net-(Header14-Pad23)") (class "Default")
      (node (ref "Header14") (pin "23") (pintype "input"))
      (node (ref "R273") (pin "1") (pinfunction "1_1") (pintype "passive"))
    )
    (net (code "264") (name "Net-(Header14-Pad24)") (class "Default")
      (node (ref "Header14") (pin "24") (pintype "input"))
      (node (ref "R274") (pin "1") (pinfunction "1_1") (pintype "passive"))
    )
    (net (code "265") (name "Net-(Header15-Pad1)") (class "Default")
      (node (ref "Header15") (pin "1") (pintype "input"))
      (node (ref "R276") (pin "2") (pinfunction "2_2") (pintype "passive"))
    )
    (net (code "266") (name "Net-(Header15-Pad2)") (class "Default")
      (node (ref "Header15") (pin "2") (pintype "input"))
      (node (ref "R277") (pin "2") (pinfunction "2_2") (pintype "passive"))
    )
    (net (code "267") (name "Net-(Header15-Pad3)") (class "Default")
      (node (ref "Header15") (pin "3") (pintype "input"))
      (node (ref "R278") (pin "2") (pinfunction "2_2") (pintype "passive"))
    )
    (net (code "268") (name "Net-(Header15-Pad4)") (class "Default")
      (node (ref "Header15") (pin "4") (pintype "input"))
      (node (ref "R279") (pin "2") (pinfunction "2_2") (pintype "passive"))
    )
    (net (code "269") (name "Net-(Header15-Pad5)") (class "Default")
      (node (ref "Header15") (pin "5") (pintype "input"))
      (node (ref "R280") (pin "2") (pinfunction "2_2") (pintype "passive"))
    )
    (net (code "270") (name "Net-(Header15-Pad6)") (class "Default")
      (node (ref "Header15") (pin "6") (pintype "input"))
      (node (ref "R281") (pin "2") (pinfunction "2_2") (pintype "passive"))
    )
    (net (code "271") (name "Net-(Header15-Pad7)") (class "Default")
      (node (ref "Header15") (pin "7") (pintype "input"))
      (node (ref "R282") (pin "2") (pinfunction "2_2") (pintype "passive"))
    )
    (net (code "272") (name "Net-(Header15-Pad8)") (class "Default")
      (node (ref "Header15") (pin "8") (pintype "input"))
      (node (ref "R283") (pin "2") (pinfunction "2_2") (pintype "passive"))
    )
    (net (code "273") (name "Net-(Header15-Pad9)") (class "Default")
      (node (ref "Header15") (pin "9") (pintype "input"))
      (node (ref "R284") (pin "2") (pinfunction "2_2") (pintype "passive"))
    )
    (net (code "274") (name "Net-(Header15-Pad10)") (class "Default")
      (node (ref "Header15") (pin "10") (pintype "input"))
      (node (ref "R285") (pin "2") (pinfunction "2_2") (pintype "passive"))
    )
    (net (code "275") (name "Net-(Header15-Pad11)") (class "Default")
      (node (ref "Header15") (pin "11") (pintype "input"))
      (node (ref "R286") (pin "2") (pinfunction "2_2") (pintype "passive"))
    )
    (net (code "276") (name "Net-(Header15-Pad12)") (class "Default")
      (node (ref "Header15") (pin "12") (pintype "input"))
      (node (ref "R287") (pin "2") (pinfunction "2_2") (pintype "passive"))
    )
    (net (code "277") (name "Net-(Header15-Pad13)") (class "Default")
      (node (ref "Header15") (pin "13") (pintype "input"))
      (node (ref "R288") (pin "2") (pinfunction "2_2") (pintype "passive"))
    )
    (net (code "278") (name "Net-(Header15-Pad14)") (class "Default")
      (node (ref "Header15") (pin "14") (pintype "input"))
      (node (ref "R289") (pin "2") (pinfunction "2_2") (pintype "passive"))
    )
    (net (code "279") (name "Net-(Header15-Pad15)") (class "Default")
      (node (ref "Header15") (pin "15") (pintype "input"))
      (node (ref "R290") (pin "2") (pinfunction "2_2") (pintype "passive"))
    )
    (net (code "280") (name "Net-(Header15-Pad16)") (class "Default")
      (node (ref "Header15") (pin "16") (pintype "input"))
      (node (ref "R291") (pin "2") (pinfunction "2_2") (pintype "passive"))
    )
    (net (code "281") (name "Net-(Header15-Pad17)") (class "Default")
      (node (ref "Header15") (pin "17") (pintype "input"))
      (node (ref "R292") (pin "2") (pinfunction "2_2") (pintype "passive"))
    )
    (net (code "282") (name "Net-(Header15-Pad18)") (class "Default")
      (node (ref "Header15") (pin "18") (pintype "input"))
      (node (ref "R293") (pin "2") (pinfunction "2_2") (pintype "passive"))
    )
    (net (code "283") (name "Net-(Header15-Pad19)") (class "Default")
      (node (ref "Header15") (pin "19") (pintype "input"))
      (node (ref "R294") (pin "2") (pinfunction "2_2") (pintype "passive"))
    )
    (net (code "284") (name "Net-(Header15-Pad20)") (class "Default")
      (node (ref "Header15") (pin "20") (pintype "input"))
      (node (ref "R295") (pin "2") (pinfunction "2_2") (pintype "passive"))
    )
    (net (code "285") (name "Net-(Header15-Pad21)") (class "Default")
      (node (ref "Header15") (pin "21") (pintype "input"))
      (node (ref "R296") (pin "2") (pinfunction "2_2") (pintype "passive"))
    )
    (net (code "286") (name "Net-(Header15-Pad22)") (class "Default")
      (node (ref "Header15") (pin "22") (pintype "input"))
      (node (ref "R297") (pin "2") (pinfunction "2_2") (pintype "passive"))
    )
    (net (code "287") (name "Net-(Header15-Pad23)") (class "Default")
      (node (ref "Header15") (pin "23") (pintype "input"))
      (node (ref "R298") (pin "2") (pinfunction "2_2") (pintype "passive"))
    )
    (net (code "288") (name "Net-(Header15-Pad24)") (class "Default")
      (node (ref "Header15") (pin "24") (pintype "input"))
      (node (ref "R299") (pin "2") (pinfunction "2_2") (pintype "passive"))
    )
    (net (code "289") (name "Net-(Header16-Pad1)") (class "Default")
      (node (ref "Header16") (pin "1") (pintype "input"))
      (node (ref "R301") (pin "1") (pinfunction "1_1") (pintype "passive"))
    )
    (net (code "290") (name "Net-(Header16-Pad2)") (class "Default")
      (node (ref "Header16") (pin "2") (pintype "input"))
      (node (ref "R302") (pin "1") (pinfunction "1_1") (pintype "passive"))
    )
    (net (code "291") (name "Net-(Header16-Pad3)") (class "Default")
      (node (ref "Header16") (pin "3") (pintype "input"))
      (node (ref "R303") (pin "1") (pinfunction "1_1") (pintype "passive"))
    )
    (net (code "292") (name "Net-(Header16-Pad4)") (class "Default")
      (node (ref "Header16") (pin "4") (pintype "input"))
      (node (ref "R304") (pin "1") (pinfunction "1_1") (pintype "passive"))
    )
    (net (code "293") (name "Net-(Header16-Pad5)") (class "Default")
      (node (ref "Header16") (pin "5") (pintype "input"))
      (node (ref "R305") (pin "1") (pinfunction "1_1") (pintype "passive"))
    )
    (net (code "294") (name "Net-(Header16-Pad6)") (class "Default")
      (node (ref "Header16") (pin "6") (pintype "input"))
      (node (ref "R306") (pin "1") (pinfunction "1_1") (pintype "passive"))
    )
    (net (code "295") (name "Net-(Header16-Pad7)") (class "Default")
      (node (ref "Header16") (pin "7") (pintype "input"))
      (node (ref "R307") (pin "1") (pinfunction "1_1") (pintype "passive"))
    )
    (net (code "296") (name "Net-(Header16-Pad8)") (class "Default")
      (node (ref "Header16") (pin "8") (pintype "input"))
      (node (ref "R308") (pin "1") (pinfunction "1_1") (pintype "passive"))
    )
    (net (code "297") (name "Net-(Header16-Pad9)") (class "Default")
      (node (ref "Header16") (pin "9") (pintype "input"))
      (node (ref "R309") (pin "1") (pinfunction "1_1") (pintype "passive"))
    )
    (net (code "298") (name "Net-(Header16-Pad10)") (class "Default")
      (node (ref "Header16") (pin "10") (pintype "input"))
      (node (ref "R310") (pin "1") (pinfunction "1_1") (pintype "passive"))
    )
    (net (code "299") (name "Net-(Header16-Pad11)") (class "Default")
      (node (ref "Header16") (pin "11") (pintype "input"))
      (node (ref "R311") (pin "1") (pinfunction "1_1") (pintype "passive"))
    )
    (net (code "300") (name "Net-(Header16-Pad12)") (class "Default")
      (node (ref "Header16") (pin "12") (pintype "input"))
      (node (ref "R312") (pin "1") (pinfunction "1_1") (pintype "passive"))
    )
    (net (code "301") (name "Net-(Header16-Pad13)") (class "Default")
      (node (ref "Header16") (pin "13") (pintype "input"))
      (node (ref "R313") (pin "1") (pinfunction "1_1") (pintype "passive"))
    )
    (net (code "302") (name "Net-(Header16-Pad14)") (class "Default")
      (node (ref "Header16") (pin "14") (pintype "input"))
      (node (ref "R314") (pin "1") (pinfunction "1_1") (pintype "passive"))
    )
    (net (code "303") (name "Net-(Header16-Pad15)") (class "Default")
      (node (ref "Header16") (pin "15") (pintype "input"))
      (node (ref "R315") (pin "1") (pinfunction "1_1") (pintype "passive"))
    )
    (net (code "304") (name "Net-(Header16-Pad16)") (class "Default")
      (node (ref "Header16") (pin "16") (pintype "input"))
      (node (ref "R316") (pin "1") (pinfunction "1_1") (pintype "passive"))
    )
    (net (code "305") (name "Net-(Header16-Pad17)") (class "Default")
      (node (ref "Header16") (pin "17") (pintype "input"))
      (node (ref "R317") (pin "1") (pinfunction "1_1") (pintype "passive"))
    )
    (net (code "306") (name "Net-(Header16-Pad18)") (class "Default")
      (node (ref "Header16") (pin "18") (pintype "input"))
      (node (ref "R318") (pin "1") (pinfunction "1_1") (pintype "passive"))
    )
    (net (code "307") (name "Net-(Header16-Pad19)") (class "Default")
      (node (ref "Header16") (pin "19") (pintype "input"))
      (node (ref "R319") (pin "1") (pinfunction "1_1") (pintype "passive"))
    )
    (net (code "308") (name "Net-(Header16-Pad20)") (class "Default")
      (node (ref "Header16") (pin "20") (pintype "input"))
      (node (ref "R320") (pin "1") (pinfunction "1_1") (pintype "passive"))
    )
    (net (code "309") (name "Net-(Header16-Pad21)") (class "Default")
      (node (ref "Header16") (pin "21") (pintype "input"))
      (node (ref "R321") (pin "1") (pinfunction "1_1") (pintype "passive"))
    )
    (net (code "310") (name "Net-(Header16-Pad22)") (class "Default")
      (node (ref "Header16") (pin "22") (pintype "input"))
      (node (ref "R322") (pin "1") (pinfunction "1_1") (pintype "passive"))
    )
    (net (code "311") (name "Net-(Header16-Pad23)") (class "Default")
      (node (ref "Header16") (pin "23") (pintype "input"))
      (node (ref "R323") (pin "1") (pinfunction "1_1") (pintype "passive"))
    )
    (net (code "312") (name "Net-(Header16-Pad24)") (class "Default")
      (node (ref "Header16") (pin "24") (pintype "input"))
      (node (ref "R324") (pin "1") (pinfunction "1_1") (pintype "passive"))
    )
    (net (code "313") (name "Net-(Header17-Pad1)") (class "Default")
      (node (ref "Header17") (pin "1") (pintype "input"))
      (node (ref "R326") (pin "2") (pinfunction "2_2") (pintype "passive"))
    )
    (net (code "314") (name "Net-(Header17-Pad2)") (class "Default")
      (node (ref "Header17") (pin "2") (pintype "input"))
      (node (ref "R327") (pin "2") (pinfunction "2_2") (pintype "passive"))
    )
    (net (code "315") (name "Net-(Header17-Pad3)") (class "Default")
      (node (ref "Header17") (pin "3") (pintype "input"))
      (node (ref "R328") (pin "2") (pinfunction "2_2") (pintype "passive"))
    )
    (net (code "316") (name "Net-(Header17-Pad4)") (class "Default")
      (node (ref "Header17") (pin "4") (pintype "input"))
      (node (ref "R329") (pin "2") (pinfunction "2_2") (pintype "passive"))
    )
    (net (code "317") (name "Net-(Header17-Pad5)") (class "Default")
      (node (ref "Header17") (pin "5") (pintype "input"))
      (node (ref "R330") (pin "2") (pinfunction "2_2") (pintype "passive"))
    )
    (net (code "318") (name "Net-(Header17-Pad6)") (class "Default")
      (node (ref "Header17") (pin "6") (pintype "input"))
      (node (ref "R331") (pin "2") (pinfunction "2_2") (pintype "passive"))
    )
    (net (code "319") (name "Net-(Header17-Pad7)") (class "Default")
      (node (ref "Header17") (pin "7") (pintype "input"))
      (node (ref "R332") (pin "2") (pinfunction "2_2") (pintype "passive"))
    )
    (net (code "320") (name "Net-(Header17-Pad8)") (class "Default")
      (node (ref "Header17") (pin "8") (pintype "input"))
      (node (ref "R333") (pin "2") (pinfunction "2_2") (pintype "passive"))
    )
    (net (code "321") (name "Net-(Header17-Pad9)") (class "Default")
      (node (ref "Header17") (pin "9") (pintype "input"))
      (node (ref "R334") (pin "2") (pinfunction "2_2") (pintype "passive"))
    )
    (net (code "322") (name "Net-(Header17-Pad10)") (class "Default")
      (node (ref "Header17") (pin "10") (pintype "input"))
      (node (ref "R335") (pin "2") (pinfunction "2_2") (pintype "passive"))
    )
    (net (code "323") (name "Net-(Header17-Pad11)") (class "Default")
      (node (ref "Header17") (pin "11") (pintype "input"))
      (node (ref "R336") (pin "2") (pinfunction "2_2") (pintype "passive"))
    )
    (net (code "324") (name "Net-(Header17-Pad12)") (class "Default")
      (node (ref "Header17") (pin "12") (pintype "input"))
      (node (ref "R337") (pin "2") (pinfunction "2_2") (pintype "passive"))
    )
    (net (code "325") (name "Net-(Header17-Pad13)") (class "Default")
      (node (ref "Header17") (pin "13") (pintype "input"))
      (node (ref "R338") (pin "2") (pinfunction "2_2") (pintype "passive"))
    )
    (net (code "326") (name "Net-(Header17-Pad14)") (class "Default")
      (node (ref "Header17") (pin "14") (pintype "input"))
      (node (ref "R339") (pin "2") (pinfunction "2_2") (pintype "passive"))
    )
    (net (code "327") (name "Net-(Header17-Pad15)") (class "Default")
      (node (ref "Header17") (pin "15") (pintype "input"))
      (node (ref "R340") (pin "2") (pinfunction "2_2") (pintype "passive"))
    )
    (net (code "328") (name "Net-(Header17-Pad16)") (class "Default")
      (node (ref "Header17") (pin "16") (pintype "input"))
      (node (ref "R341") (pin "2") (pinfunction "2_2") (pintype "passive"))
    )
    (net (code "329") (name "Net-(Header17-Pad17)") (class "Default")
      (node (ref "Header17") (pin "17") (pintype "input"))
      (node (ref "R342") (pin "2") (pinfunction "2_2") (pintype "passive"))
    )
    (net (code "330") (name "Net-(Header17-Pad18)") (class "Default")
      (node (ref "Header17") (pin "18") (pintype "input"))
      (node (ref "R343") (pin "2") (pinfunction "2_2") (pintype "passive"))
    )
    (net (code "331") (name "Net-(Header17-Pad19)") (class "Default")
      (node (ref "Header17") (pin "19") (pintype "input"))
      (node (ref "R344") (pin "2") (pinfunction "2_2") (pintype "passive"))
    )
    (net (code "332") (name "Net-(Header17-Pad20)") (class "Default")
      (node (ref "Header17") (pin "20") (pintype "input"))
      (node (ref "R345") (pin "2") (pinfunction "2_2") (pintype "passive"))
    )
    (net (code "333") (name "Net-(Header17-Pad21)") (class "Default")
      (node (ref "Header17") (pin "21") (pintype "input"))
      (node (ref "R346") (pin "2") (pinfunction "2_2") (pintype "passive"))
    )
    (net (code "334") (name "Net-(Header17-Pad22)") (class "Default")
      (node (ref "Header17") (pin "22") (pintype "input"))
      (node (ref "R347") (pin "2") (pinfunction "2_2") (pintype "passive"))
    )
    (net (code "335") (name "Net-(Header17-Pad23)") (class "Default")
      (node (ref "Header17") (pin "23") (pintype "input"))
      (node (ref "R348") (pin "2") (pinfunction "2_2") (pintype "passive"))
    )
    (net (code "336") (name "Net-(Header17-Pad24)") (class "Default")
      (node (ref "Header17") (pin "24") (pintype "input"))
      (node (ref "R349") (pin "2") (pinfunction "2_2") (pintype "passive"))
    )
    (net (code "337") (name "Net-(Header18-Pad1)") (class "Default")
      (node (ref "Header18") (pin "1") (pintype "input"))
      (node (ref "R351") (pin "1") (pinfunction "1_1") (pintype "passive"))
    )
    (net (code "338") (name "Net-(Header18-Pad2)") (class "Default")
      (node (ref "Header18") (pin "2") (pintype "input"))
      (node (ref "R352") (pin "1") (pinfunction "1_1") (pintype "passive"))
    )
    (net (code "339") (name "Net-(Header18-Pad3)") (class "Default")
      (node (ref "Header18") (pin "3") (pintype "input"))
      (node (ref "R353") (pin "1") (pinfunction "1_1") (pintype "passive"))
    )
    (net (code "340") (name "Net-(Header18-Pad4)") (class "Default")
      (node (ref "Header18") (pin "4") (pintype "input"))
      (node (ref "R354") (pin "1") (pinfunction "1_1") (pintype "passive"))
    )
    (net (code "341") (name "Net-(Header18-Pad5)") (class "Default")
      (node (ref "Header18") (pin "5") (pintype "input"))
      (node (ref "R355") (pin "1") (pinfunction "1_1") (pintype "passive"))
    )
    (net (code "342") (name "Net-(Header18-Pad6)") (class "Default")
      (node (ref "Header18") (pin "6") (pintype "input"))
      (node (ref "R356") (pin "1") (pinfunction "1_1") (pintype "passive"))
    )
    (net (code "343") (name "Net-(Header18-Pad7)") (class "Default")
      (node (ref "Header18") (pin "7") (pintype "input"))
      (node (ref "R357") (pin "1") (pinfunction "1_1") (pintype "passive"))
    )
    (net (code "344") (name "Net-(Header18-Pad8)") (class "Default")
      (node (ref "Header18") (pin "8") (pintype "input"))
      (node (ref "R358") (pin "1") (pinfunction "1_1") (pintype "passive"))
    )
    (net (code "345") (name "Net-(Header18-Pad9)") (class "Default")
      (node (ref "Header18") (pin "9") (pintype "input"))
      (node (ref "R359") (pin "1") (pinfunction "1_1") (pintype "passive"))
    )
    (net (code "346") (name "Net-(Header18-Pad10)") (class "Default")
      (node (ref "Header18") (pin "10") (pintype "input"))
      (node (ref "R360") (pin "1") (pinfunction "1_1") (pintype "passive"))
    )
    (net (code "347") (name "Net-(Header18-Pad11)") (class "Default")
      (node (ref "Header18") (pin "11") (pintype "input"))
      (node (ref "R361") (pin "1") (pinfunction "1_1") (pintype "passive"))
    )
    (net (code "348") (name "Net-(Header18-Pad12)") (class "Default")
      (node (ref "Header18") (pin "12") (pintype "input"))
      (node (ref "R362") (pin "1") (pinfunction "1_1") (pintype "passive"))
    )
    (net (code "349") (name "Net-(Header18-Pad13)") (class "Default")
      (node (ref "Header18") (pin "13") (pintype "input"))
      (node (ref "R363") (pin "1") (pinfunction "1_1") (pintype "passive"))
    )
    (net (code "350") (name "Net-(Header18-Pad14)") (class "Default")
      (node (ref "Header18") (pin "14") (pintype "input"))
      (node (ref "R364") (pin "1") (pinfunction "1_1") (pintype "passive"))
    )
    (net (code "351") (name "Net-(Header18-Pad15)") (class "Default")
      (node (ref "Header18") (pin "15") (pintype "input"))
      (node (ref "R365") (pin "1") (pinfunction "1_1") (pintype "passive"))
    )
    (net (code "352") (name "Net-(Header18-Pad16)") (class "Default")
      (node (ref "Header18") (pin "16") (pintype "input"))
      (node (ref "R366") (pin "1") (pinfunction "1_1") (pintype "passive"))
    )
    (net (code "353") (name "Net-(Header18-Pad17)") (class "Default")
      (node (ref "Header18") (pin "17") (pintype "input"))
      (node (ref "R367") (pin "1") (pinfunction "1_1") (pintype "passive"))
    )
    (net (code "354") (name "Net-(Header18-Pad18)") (class "Default")
      (node (ref "Header18") (pin "18") (pintype "input"))
      (node (ref "R368") (pin "1") (pinfunction "1_1") (pintype "passive"))
    )
    (net (code "355") (name "Net-(Header18-Pad19)") (class "Default")
      (node (ref "Header18") (pin "19") (pintype "input"))
      (node (ref "R369") (pin "1") (pinfunction "1_1") (pintype "passive"))
    )
    (net (code "356") (name "Net-(Header18-Pad20)") (class "Default")
      (node (ref "Header18") (pin "20") (pintype "input"))
      (node (ref "R370") (pin "1") (pinfunction "1_1") (pintype "passive"))
    )
    (net (code "357") (name "Net-(Header18-Pad21)") (class "Default")
      (node (ref "Header18") (pin "21") (pintype "input"))
      (node (ref "R371") (pin "1") (pinfunction "1_1") (pintype "passive"))
    )
    (net (code "358") (name "Net-(Header18-Pad22)") (class "Default")
      (node (ref "Header18") (pin "22") (pintype "input"))
      (node (ref "R372") (pin "1") (pinfunction "1_1") (pintype "passive"))
    )
    (net (code "359") (name "Net-(Header18-Pad23)") (class "Default")
      (node (ref "Header18") (pin "23") (pintype "input"))
      (node (ref "R373") (pin "1") (pinfunction "1_1") (pintype "passive"))
    )
    (net (code "360") (name "Net-(Header18-Pad24)") (class "Default")
      (node (ref "Header18") (pin "24") (pintype "input"))
      (node (ref "R374") (pin "1") (pinfunction "1_1") (pintype "passive"))
    )
    (net (code "361") (name "Net-(Header19-Pad1)") (class "Default")
      (node (ref "Header19") (pin "1") (pintype "input"))
      (node (ref "R376") (pin "2") (pinfunction "2_2") (pintype "passive"))
    )
    (net (code "362") (name "Net-(Header19-Pad2)") (class "Default")
      (node (ref "Header19") (pin "2") (pintype "input"))
      (node (ref "R377") (pin "2") (pinfunction "2_2") (pintype "passive"))
    )
    (net (code "363") (name "Net-(Header19-Pad3)") (class "Default")
      (node (ref "Header19") (pin "3") (pintype "input"))
      (node (ref "R378") (pin "2") (pinfunction "2_2") (pintype "passive"))
    )
    (net (code "364") (name "Net-(Header19-Pad4)") (class "Default")
      (node (ref "Header19") (pin "4") (pintype "input"))
      (node (ref "R379") (pin "2") (pinfunction "2_2") (pintype "passive"))
    )
    (net (code "365") (name "Net-(Header19-Pad5)") (class "Default")
      (node (ref "Header19") (pin "5") (pintype "input"))
      (node (ref "R380") (pin "2") (pinfunction "2_2") (pintype "passive"))
    )
    (net (code "366") (name "Net-(Header19-Pad6)") (class "Default")
      (node (ref "Header19") (pin "6") (pintype "input"))
      (node (ref "R381") (pin "2") (pinfunction "2_2") (pintype "passive"))
    )
    (net (code "367") (name "Net-(Header19-Pad7)") (class "Default")
      (node (ref "Header19") (pin "7") (pintype "input"))
      (node (ref "R382") (pin "2") (pinfunction "2_2") (pintype "passive"))
    )
    (net (code "368") (name "Net-(Header19-Pad8)") (class "Default")
      (node (ref "Header19") (pin "8") (pintype "input"))
      (node (ref "R383") (pin "2") (pinfunction "2_2") (pintype "passive"))
    )
    (net (code "369") (name "Net-(Header19-Pad9)") (class "Default")
      (node (ref "Header19") (pin "9") (pintype "input"))
      (node (ref "R384") (pin "2") (pinfunction "2_2") (pintype "passive"))
    )
    (net (code "370") (name "Net-(Header19-Pad10)") (class "Default")
      (node (ref "Header19") (pin "10") (pintype "input"))
      (node (ref "R385") (pin "2") (pinfunction "2_2") (pintype "passive"))
    )
    (net (code "371") (name "Net-(Header19-Pad11)") (class "Default")
      (node (ref "Header19") (pin "11") (pintype "input"))
      (node (ref "R386") (pin "2") (pinfunction "2_2") (pintype "passive"))
    )
    (net (code "372") (name "Net-(Header19-Pad12)") (class "Default")
      (node (ref "Header19") (pin "12") (pintype "input"))
      (node (ref "R387") (pin "2") (pinfunction "2_2") (pintype "passive"))
    )
    (net (code "373") (name "Net-(Header19-Pad13)") (class "Default")
      (node (ref "Header19") (pin "13") (pintype "input"))
      (node (ref "R388") (pin "2") (pinfunction "2_2") (pintype "passive"))
    )
    (net (code "374") (name "Net-(Header19-Pad14)") (class "Default")
      (node (ref "Header19") (pin "14") (pintype "input"))
      (node (ref "R389") (pin "2") (pinfunction "2_2") (pintype "passive"))
    )
    (net (code "375") (name "Net-(Header19-Pad15)") (class "Default")
      (node (ref "Header19") (pin "15") (pintype "input"))
      (node (ref "R390") (pin "2") (pinfunction "2_2") (pintype "passive"))
    )
    (net (code "376") (name "Net-(Header19-Pad16)") (class "Default")
      (node (ref "Header19") (pin "16") (pintype "input"))
      (node (ref "R391") (pin "2") (pinfunction "2_2") (pintype "passive"))
    )
    (net (code "377") (name "Net-(Header19-Pad17)") (class "Default")
      (node (ref "Header19") (pin "17") (pintype "input"))
      (node (ref "R392") (pin "2") (pinfunction "2_2") (pintype "passive"))
    )
    (net (code "378") (name "Net-(Header19-Pad18)") (class "Default")
      (node (ref "Header19") (pin "18") (pintype "input"))
      (node (ref "R393") (pin "2") (pinfunction "2_2") (pintype "passive"))
    )
    (net (code "379") (name "Net-(Header19-Pad19)") (class "Default")
      (node (ref "Header19") (pin "19") (pintype "input"))
      (node (ref "R394") (pin "2") (pinfunction "2_2") (pintype "passive"))
    )
    (net (code "380") (name "Net-(Header19-Pad20)") (class "Default")
      (node (ref "Header19") (pin "20") (pintype "input"))
      (node (ref "R395") (pin "2") (pinfunction "2_2") (pintype "passive"))
    )
    (net (code "381") (name "Net-(Header19-Pad21)") (class "Default")
      (node (ref "Header19") (pin "21") (pintype "input"))
      (node (ref "R396") (pin "2") (pinfunction "2_2") (pintype "passive"))
    )
    (net (code "382") (name "Net-(Header19-Pad22)") (class "Default")
      (node (ref "Header19") (pin "22") (pintype "input"))
      (node (ref "R397") (pin "2") (pinfunction "2_2") (pintype "passive"))
    )
    (net (code "383") (name "Net-(Header19-Pad23)") (class "Default")
      (node (ref "Header19") (pin "23") (pintype "input"))
      (node (ref "R398") (pin "2") (pinfunction "2_2") (pintype "passive"))
    )
    (net (code "384") (name "Net-(Header19-Pad24)") (class "Default")
      (node (ref "Header19") (pin "24") (pintype "input"))
      (node (ref "R399") (pin "2") (pinfunction "2_2") (pintype "passive"))
    )
    (net (code "385") (name "Net-(Header20-Pad1)") (class "Default")
      (node (ref "Header20") (pin "1") (pintype "input"))
      (node (ref "R401") (pin "1") (pinfunction "1_1") (pintype "passive"))
    )
    (net (code "386") (name "Net-(Header20-Pad2)") (class "Default")
      (node (ref "Header20") (pin "2") (pintype "input"))
      (node (ref "R402") (pin "1") (pinfunction "1_1") (pintype "passive"))
    )
    (net (code "387") (name "Net-(Header20-Pad3)") (class "Default")
      (node (ref "Header20") (pin "3") (pintype "input"))
      (node (ref "R403") (pin "1") (pinfunction "1_1") (pintype "passive"))
    )
    (net (code "388") (name "Net-(Header20-Pad4)") (class "Default")
      (node (ref "Header20") (pin "4") (pintype "input"))
      (node (ref "R404") (pin "1") (pinfunction "1_1") (pintype "passive"))
    )
    (net (code "389") (name "Net-(Header20-Pad5)") (class "Default")
      (node (ref "Header20") (pin "5") (pintype "input"))
      (node (ref "R405") (pin "1") (pinfunction "1_1") (pintype "passive"))
    )
    (net (code "390") (name "Net-(Header20-Pad6)") (class "Default")
      (node (ref "Header20") (pin "6") (pintype "input"))
      (node (ref "R406") (pin "1") (pinfunction "1_1") (pintype "passive"))
    )
    (net (code "391") (name "Net-(Header20-Pad7)") (class "Default")
      (node (ref "Header20") (pin "7") (pintype "input"))
      (node (ref "R407") (pin "1") (pinfunction "1_1") (pintype "passive"))
    )
    (net (code "392") (name "Net-(Header20-Pad8)") (class "Default")
      (node (ref "Header20") (pin "8") (pintype "input"))
      (node (ref "R408") (pin "1") (pinfunction "1_1") (pintype "passive"))
    )
    (net (code "393") (name "Net-(Header20-Pad9)") (class "Default")
      (node (ref "Header20") (pin "9") (pintype "input"))
      (node (ref "R409") (pin "1") (pinfunction "1_1") (pintype "passive"))
    )
    (net (code "394") (name "Net-(Header20-Pad10)") (class "Default")
      (node (ref "Header20") (pin "10") (pintype "input"))
      (node (ref "R410") (pin "1") (pinfunction "1_1") (pintype "passive"))
    )
    (net (code "395") (name "Net-(Header20-Pad11)") (class "Default")
      (node (ref "Header20") (pin "11") (pintype "input"))
      (node (ref "R411") (pin "1") (pinfunction "1_1") (pintype "passive"))
    )
    (net (code "396") (name "Net-(Header20-Pad12)") (class "Default")
      (node (ref "Header20") (pin "12") (pintype "input"))
      (node (ref "R412") (pin "1") (pinfunction "1_1") (pintype "passive"))
    )
    (net (code "397") (name "Net-(Header20-Pad13)") (class "Default")
      (node (ref "Header20") (pin "13") (pintype "input"))
      (node (ref "R413") (pin "1") (pinfunction "1_1") (pintype "passive"))
    )
    (net (code "398") (name "Net-(Header20-Pad14)") (class "Default")
      (node (ref "Header20") (pin "14") (pintype "input"))
      (node (ref "R414") (pin "1") (pinfunction "1_1") (pintype "passive"))
    )
    (net (code "399") (name "Net-(Header20-Pad15)") (class "Default")
      (node (ref "Header20") (pin "15") (pintype "input"))
      (node (ref "R415") (pin "1") (pinfunction "1_1") (pintype "passive"))
    )
    (net (code "400") (name "Net-(Header20-Pad16)") (class "Default")
      (node (ref "Header20") (pin "16") (pintype "input"))
      (node (ref "R416") (pin "1") (pinfunction "1_1") (pintype "passive"))
    )
    (net (code "401") (name "Net-(Header20-Pad17)") (class "Default")
      (node (ref "Header20") (pin "17") (pintype "input"))
      (node (ref "R417") (pin "1") (pinfunction "1_1") (pintype "passive"))
    )
    (net (code "402") (name "Net-(Header20-Pad18)") (class "Default")
      (node (ref "Header20") (pin "18") (pintype "input"))
      (node (ref "R418") (pin "1") (pinfunction "1_1") (pintype "passive"))
    )
    (net (code "403") (name "Net-(Header20-Pad19)") (class "Default")
      (node (ref "Header20") (pin "19") (pintype "input"))
      (node (ref "R419") (pin "1") (pinfunction "1_1") (pintype "passive"))
    )
    (net (code "404") (name "Net-(Header20-Pad20)") (class "Default")
      (node (ref "Header20") (pin "20") (pintype "input"))
      (node (ref "R420") (pin "1") (pinfunction "1_1") (pintype "passive"))
    )
    (net (code "405") (name "Net-(Header20-Pad21)") (class "Default")
      (node (ref "Header20") (pin "21") (pintype "input"))
      (node (ref "R421") (pin "1") (pinfunction "1_1") (pintype "passive"))
    )
    (net (code "406") (name "Net-(Header20-Pad22)") (class "Default")
      (node (ref "Header20") (pin "22") (pintype "input"))
      (node (ref "R422") (pin "1") (pinfunction "1_1") (pintype "passive"))
    )
    (net (code "407") (name "Net-(Header20-Pad23)") (class "Default")
      (node (ref "Header20") (pin "23") (pintype "input"))
      (node (ref "R423") (pin "1") (pinfunction "1_1") (pintype "passive"))
    )
    (net (code "408") (name "Net-(Header20-Pad24)") (class "Default")
      (node (ref "Header20") (pin "24") (pintype "input"))
      (node (ref "R424") (pin "1") (pinfunction "1_1") (pintype "passive"))
    )
    (net (code "409") (name "Net-(Header21-Pad1)") (class "Default")
      (node (ref "Header21") (pin "1") (pintype "input"))
      (node (ref "R426") (pin "2") (pinfunction "2_2") (pintype "passive"))
    )
    (net (code "410") (name "Net-(Header21-Pad2)") (class "Default")
      (node (ref "Header21") (pin "2") (pintype "input"))
      (node (ref "R427") (pin "2") (pinfunction "2_2") (pintype "passive"))
    )
    (net (code "411") (name "Net-(Header21-Pad3)") (class "Default")
      (node (ref "Header21") (pin "3") (pintype "input"))
      (node (ref "R428") (pin "2") (pinfunction "2_2") (pintype "passive"))
    )
    (net (code "412") (name "Net-(Header21-Pad4)") (class "Default")
      (node (ref "Header21") (pin "4") (pintype "input"))
      (node (ref "R429") (pin "2") (pinfunction "2_2") (pintype "passive"))
    )
    (net (code "413") (name "Net-(Header21-Pad5)") (class "Default")
      (node (ref "Header21") (pin "5") (pintype "input"))
      (node (ref "R430") (pin "2") (pinfunction "2_2") (pintype "passive"))
    )
    (net (code "414") (name "Net-(Header21-Pad6)") (class "Default")
      (node (ref "Header21") (pin "6") (pintype "input"))
      (node (ref "R431") (pin "2") (pinfunction "2_2") (pintype "passive"))
    )
    (net (code "415") (name "Net-(Header21-Pad7)") (class "Default")
      (node (ref "Header21") (pin "7") (pintype "input"))
      (node (ref "R432") (pin "2") (pinfunction "2_2") (pintype "passive"))
    )
    (net (code "416") (name "Net-(Header21-Pad8)") (class "Default")
      (node (ref "Header21") (pin "8") (pintype "input"))
      (node (ref "R433") (pin "2") (pinfunction "2_2") (pintype "passive"))
    )
    (net (code "417") (name "Net-(Header21-Pad9)") (class "Default")
      (node (ref "Header21") (pin "9") (pintype "input"))
      (node (ref "R434") (pin "2") (pinfunction "2_2") (pintype "passive"))
    )
    (net (code "418") (name "Net-(Header21-Pad10)") (class "Default")
      (node (ref "Header21") (pin "10") (pintype "input"))
      (node (ref "R435") (pin "2") (pinfunction "2_2") (pintype "passive"))
    )
    (net (code "419") (name "Net-(Header21-Pad11)") (class "Default")
      (node (ref "Header21") (pin "11") (pintype "input"))
      (node (ref "R436") (pin "2") (pinfunction "2_2") (pintype "passive"))
    )
    (net (code "420") (name "Net-(Header21-Pad12)") (class "Default")
      (node (ref "Header21") (pin "12") (pintype "input"))
      (node (ref "R437") (pin "2") (pinfunction "2_2") (pintype "passive"))
    )
    (net (code "421") (name "Net-(Header21-Pad13)") (class "Default")
      (node (ref "Header21") (pin "13") (pintype "input"))
      (node (ref "R438") (pin "2") (pinfunction "2_2") (pintype "passive"))
    )
    (net (code "422") (name "Net-(Header21-Pad14)") (class "Default")
      (node (ref "Header21") (pin "14") (pintype "input"))
      (node (ref "R439") (pin "2") (pinfunction "2_2") (pintype "passive"))
    )
    (net (code "423") (name "Net-(Header21-Pad15)") (class "Default")
      (node (ref "Header21") (pin "15") (pintype "input"))
      (node (ref "R440") (pin "2") (pinfunction "2_2") (pintype "passive"))
    )
    (net (code "424") (name "Net-(Header21-Pad16)") (class "Default")
      (node (ref "Header21") (pin "16") (pintype "input"))
      (node (ref "R441") (pin "2") (pinfunction "2_2") (pintype "passive"))
    )
    (net (code "425") (name "Net-(Header21-Pad17)") (class "Default")
      (node (ref "Header21") (pin "17") (pintype "input"))
      (node (ref "R442") (pin "2") (pinfunction "2_2") (pintype "passive"))
    )
    (net (code "426") (name "Net-(Header21-Pad18)") (class "Default")
      (node (ref "Header21") (pin "18") (pintype "input"))
      (node (ref "R443") (pin "2") (pinfunction "2_2") (pintype "passive"))
    )
    (net (code "427") (name "Net-(Header21-Pad19)") (class "Default")
      (node (ref "Header21") (pin "19") (pintype "input"))
      (node (ref "R444") (pin "2") (pinfunction "2_2") (pintype "passive"))
    )
    (net (code "428") (name "Net-(Header21-Pad20)") (class "Default")
      (node (ref "Header21") (pin "20") (pintype "input"))
      (node (ref "R445") (pin "2") (pinfunction "2_2") (pintype "passive"))
    )
    (net (code "429") (name "Net-(Header21-Pad21)") (class "Default")
      (node (ref "Header21") (pin "21") (pintype "input"))
      (node (ref "R446") (pin "2") (pinfunction "2_2") (pintype "passive"))
    )
    (net (code "430") (name "Net-(Header21-Pad22)") (class "Default")
      (node (ref "Header21") (pin "22") (pintype "input"))
      (node (ref "R447") (pin "2") (pinfunction "2_2") (pintype "passive"))
    )
    (net (code "431") (name "Net-(Header21-Pad23)") (class "Default")
      (node (ref "Header21") (pin "23") (pintype "input"))
      (node (ref "R448") (pin "2") (pinfunction "2_2") (pintype "passive"))
    )
    (net (code "432") (name "Net-(Header21-Pad24)") (class "Default")
      (node (ref "Header21") (pin "24") (pintype "input"))
      (node (ref "R449") (pin "2") (pinfunction "2_2") (pintype "passive"))
    )
    (net (code "433") (name "Net-(Header22-Pad1)") (class "Default")
      (node (ref "Header22") (pin "1") (pintype "input"))
      (node (ref "R451") (pin "1") (pinfunction "1_1") (pintype "passive"))
    )
    (net (code "434") (name "Net-(Header22-Pad2)") (class "Default")
      (node (ref "Header22") (pin "2") (pintype "input"))
      (node (ref "R452") (pin "1") (pinfunction "1_1") (pintype "passive"))
    )
    (net (code "435") (name "Net-(Header22-Pad3)") (class "Default")
      (node (ref "Header22") (pin "3") (pintype "input"))
      (node (ref "R453") (pin "1") (pinfunction "1_1") (pintype "passive"))
    )
    (net (code "436") (name "Net-(Header22-Pad4)") (class "Default")
      (node (ref "Header22") (pin "4") (pintype "input"))
      (node (ref "R454") (pin "1") (pinfunction "1_1") (pintype "passive"))
    )
    (net (code "437") (name "Net-(Header22-Pad5)") (class "Default")
      (node (ref "Header22") (pin "5") (pintype "input"))
      (node (ref "R455") (pin "1") (pinfunction "1_1") (pintype "passive"))
    )
    (net (code "438") (name "Net-(Header22-Pad6)") (class "Default")
      (node (ref "Header22") (pin "6") (pintype "input"))
      (node (ref "R456") (pin "1") (pinfunction "1_1") (pintype "passive"))
    )
    (net (code "439") (name "Net-(Header22-Pad7)") (class "Default")
      (node (ref "Header22") (pin "7") (pintype "input"))
      (node (ref "R457") (pin "1") (pinfunction "1_1") (pintype "passive"))
    )
    (net (code "440") (name "Net-(Header22-Pad8)") (class "Default")
      (node (ref "Header22") (pin "8") (pintype "input"))
      (node (ref "R458") (pin "1") (pinfunction "1_1") (pintype "passive"))
    )
    (net (code "441") (name "Net-(Header22-Pad9)") (class "Default")
      (node (ref "Header22") (pin "9") (pintype "input"))
      (node (ref "R459") (pin "1") (pinfunction "1_1") (pintype "passive"))
    )
    (net (code "442") (name "Net-(Header22-Pad10)") (class "Default")
      (node (ref "Header22") (pin "10") (pintype "input"))
      (node (ref "R460") (pin "1") (pinfunction "1_1") (pintype "passive"))
    )
    (net (code "443") (name "Net-(Header22-Pad11)") (class "Default")
      (node (ref "Header22") (pin "11") (pintype "input"))
      (node (ref "R461") (pin "1") (pinfunction "1_1") (pintype "passive"))
    )
    (net (code "444") (name "Net-(Header22-Pad12)") (class "Default")
      (node (ref "Header22") (pin "12") (pintype "input"))
      (node (ref "R462") (pin "1") (pinfunction "1_1") (pintype "passive"))
    )
    (net (code "445") (name "Net-(Header22-Pad13)") (class "Default")
      (node (ref "Header22") (pin "13") (pintype "input"))
      (node (ref "R463") (pin "1") (pinfunction "1_1") (pintype "passive"))
    )
    (net (code "446") (name "Net-(Header22-Pad14)") (class "Default")
      (node (ref "Header22") (pin "14") (pintype "input"))
      (node (ref "R464") (pin "1") (pinfunction "1_1") (pintype "passive"))
    )
    (net (code "447") (name "Net-(Header22-Pad15)") (class "Default")
      (node (ref "Header22") (pin "15") (pintype "input"))
      (node (ref "R465") (pin "1") (pinfunction "1_1") (pintype "passive"))
    )
    (net (code "448") (name "Net-(Header22-Pad16)") (class "Default")
      (node (ref "Header22") (pin "16") (pintype "input"))
      (node (ref "R466") (pin "1") (pinfunction "1_1") (pintype "passive"))
    )
    (net (code "449") (name "Net-(Header22-Pad17)") (class "Default")
      (node (ref "Header22") (pin "17") (pintype "input"))
      (node (ref "R467") (pin "1") (pinfunction "1_1") (pintype "passive"))
    )
    (net (code "450") (name "Net-(Header22-Pad18)") (class "Default")
      (node (ref "Header22") (pin "18") (pintype "input"))
      (node (ref "R468") (pin "1") (pinfunction "1_1") (pintype "passive"))
    )
    (net (code "451") (name "Net-(Header22-Pad19)") (class "Default")
      (node (ref "Header22") (pin "19") (pintype "input"))
      (node (ref "R469") (pin "1") (pinfunction "1_1") (pintype "passive"))
    )
    (net (code "452") (name "Net-(Header22-Pad20)") (class "Default")
      (node (ref "Header22") (pin "20") (pintype "input"))
      (node (ref "R470") (pin "1") (pinfunction "1_1") (pintype "passive"))
    )
    (net (code "453") (name "Net-(Header22-Pad21)") (class "Default")
      (node (ref "Header22") (pin "21") (pintype "input"))
      (node (ref "R471") (pin "1") (pinfunction "1_1") (pintype "passive"))
    )
    (net (code "454") (name "Net-(Header22-Pad22)") (class "Default")
      (node (ref "Header22") (pin "22") (pintype "input"))
      (node (ref "R472") (pin "1") (pinfunction "1_1") (pintype "passive"))
    )
    (net (code "455") (name "Net-(Header22-Pad23)") (class "Default")
      (node (ref "Header22") (pin "23") (pintype "input"))
      (node (ref "R473") (pin "1") (pinfunction "1_1") (pintype "passive"))
    )
    (net (code "456") (name "Net-(Header22-Pad24)") (class "Default")
      (node (ref "Header22") (pin "24") (pintype "input"))
      (node (ref "R474") (pin "1") (pinfunction "1_1") (pintype "passive"))
    )
    (net (code "457") (name "Net-(Header23-Pad1)") (class "Default")
      (node (ref "Header23") (pin "1") (pintype "input"))
      (node (ref "R476") (pin "2") (pinfunction "2_2") (pintype "passive"))
    )
    (net (code "458") (name "Net-(Header23-Pad2)") (class "Default")
      (node (ref "Header23") (pin "2") (pintype "input"))
      (node (ref "R477") (pin "2") (pinfunction "2_2") (pintype "passive"))
    )
    (net (code "459") (name "Net-(Header23-Pad3)") (class "Default")
      (node (ref "Header23") (pin "3") (pintype "input"))
      (node (ref "R478") (pin "2") (pinfunction "2_2") (pintype "passive"))
    )
    (net (code "460") (name "Net-(Header23-Pad4)") (class "Default")
      (node (ref "Header23") (pin "4") (pintype "input"))
      (node (ref "R479") (pin "2") (pinfunction "2_2") (pintype "passive"))
    )
    (net (code "461") (name "Net-(Header23-Pad5)") (class "Default")
      (node (ref "Header23") (pin "5") (pintype "input"))
      (node (ref "R480") (pin "2") (pinfunction "2_2") (pintype "passive"))
    )
    (net (code "462") (name "Net-(Header23-Pad6)") (class "Default")
      (node (ref "Header23") (pin "6") (pintype "input"))
      (node (ref "R481") (pin "2") (pinfunction "2_2") (pintype "passive"))
    )
    (net (code "463") (name "Net-(Header23-Pad7)") (class "Default")
      (node (ref "Header23") (pin "7") (pintype "input"))
      (node (ref "R482") (pin "2") (pinfunction "2_2") (pintype "passive"))
    )
    (net (code "464") (name "Net-(Header23-Pad8)") (class "Default")
      (node (ref "Header23") (pin "8") (pintype "input"))
      (node (ref "R483") (pin "2") (pinfunction "2_2") (pintype "passive"))
    )
    (net (code "465") (name "Net-(Header23-Pad9)") (class "Default")
      (node (ref "Header23") (pin "9") (pintype "input"))
      (node (ref "R484") (pin "2") (pinfunction "2_2") (pintype "passive"))
    )
    (net (code "466") (name "Net-(Header23-Pad10)") (class "Default")
      (node (ref "Header23") (pin "10") (pintype "input"))
      (node (ref "R485") (pin "2") (pinfunction "2_2") (pintype "passive"))
    )
    (net (code "467") (name "Net-(Header23-Pad11)") (class "Default")
      (node (ref "Header23") (pin "11") (pintype "input"))
      (node (ref "R486") (pin "2") (pinfunction "2_2") (pintype "passive"))
    )
    (net (code "468") (name "Net-(Header23-Pad12)") (class "Default")
      (node (ref "Header23") (pin "12") (pintype "input"))
      (node (ref "R487") (pin "2") (pinfunction "2_2") (pintype "passive"))
    )
    (net (code "469") (name "Net-(Header23-Pad13)") (class "Default")
      (node (ref "Header23") (pin "13") (pintype "input"))
      (node (ref "R488") (pin "2") (pinfunction "2_2") (pintype "passive"))
    )
    (net (code "470") (name "Net-(Header23-Pad14)") (class "Default")
      (node (ref "Header23") (pin "14") (pintype "input"))
      (node (ref "R489") (pin "2") (pinfunction "2_2") (pintype "passive"))
    )
    (net (code "471") (name "Net-(Header23-Pad15)") (class "Default")
      (node (ref "Header23") (pin "15") (pintype "input"))
      (node (ref "R490") (pin "2") (pinfunction "2_2") (pintype "passive"))
    )
    (net (code "472") (name "Net-(Header23-Pad16)") (class "Default")
      (node (ref "Header23") (pin "16") (pintype "input"))
      (node (ref "R491") (pin "2") (pinfunction "2_2") (pintype "passive"))
    )
    (net (code "473") (name "Net-(Header23-Pad17)") (class "Default")
      (node (ref "Header23") (pin "17") (pintype "input"))
      (node (ref "R492") (pin "2") (pinfunction "2_2") (pintype "passive"))
    )
    (net (code "474") (name "Net-(Header23-Pad18)") (class "Default")
      (node (ref "Header23") (pin "18") (pintype "input"))
      (node (ref "R493") (pin "2") (pinfunction "2_2") (pintype "passive"))
    )
    (net (code "475") (name "Net-(Header23-Pad19)") (class "Default")
      (node (ref "Header23") (pin "19") (pintype "input"))
      (node (ref "R494") (pin "2") (pinfunction "2_2") (pintype "passive"))
    )
    (net (code "476") (name "Net-(Header23-Pad23)") (class "Default")
      (node (ref "Header23") (pin "23") (pintype "input"))
      (node (ref "R495") (pin "2") (pinfunction "2_2") (pintype "passive"))
    )
    (net (code "477") (name "Net-(Header23-Pad24)") (class "Default")
      (node (ref "Header23") (pin "24") (pintype "input"))
      (node (ref "R496") (pin "2") (pinfunction "2_2") (pintype "passive"))
    )
    (net (code "478") (name "Net-(Header24-Pad1)") (class "Default")
      (node (ref "Header24") (pin "1") (pintype "input"))
      (node (ref "R497") (pin "2") (pinfunction "2_2") (pintype "passive"))
    )
    (net (code "479") (name "Net-(Header24-Pad2)") (class "Default")
      (node (ref "Header24") (pin "2") (pintype "input"))
      (node (ref "R498") (pin "2") (pinfunction "2_2") (pintype "passive"))
    )
    (net (code "480") (name "Net-(Header24-Pad3)") (class "Default")
      (node (ref "Header24") (pin "3") (pintype "input"))
      (node (ref "R499") (pin "2") (pinfunction "2_2") (pintype "passive"))
    )
    (net (code "481") (name "Net-(Header24-Pad4)") (class "Default")
      (node (ref "Header24") (pin "4") (pintype "input"))
      (node (ref "R501") (pin "1") (pinfunction "1_1") (pintype "passive"))
    )
    (net (code "482") (name "Net-(Header24-Pad5)") (class "Default")
      (node (ref "Header24") (pin "5") (pintype "input"))
      (node (ref "R502") (pin "1") (pinfunction "1_1") (pintype "passive"))
    )
    (net (code "483") (name "Net-(Header24-Pad6)") (class "Default")
      (node (ref "Header24") (pin "6") (pintype "input"))
      (node (ref "R503") (pin "1") (pinfunction "1_1") (pintype "passive"))
    )
    (net (code "484") (name "Net-(Header24-Pad7)") (class "Default")
      (node (ref "Header24") (pin "7") (pintype "input"))
      (node (ref "R504") (pin "1") (pinfunction "1_1") (pintype "passive"))
    )
    (net (code "485") (name "Net-(Header24-Pad8)") (class "Default")
      (node (ref "Header24") (pin "8") (pintype "input"))
      (node (ref "R505") (pin "1") (pinfunction "1_1") (pintype "passive"))
    )
    (net (code "486") (name "Net-(Header24-Pad9)") (class "Default")
      (node (ref "Header24") (pin "9") (pintype "input"))
      (node (ref "R506") (pin "1") (pinfunction "1_1") (pintype "passive"))
    )
    (net (code "487") (name "Net-(Header24-Pad10)") (class "Default")
      (node (ref "Header24") (pin "10") (pintype "input"))
      (node (ref "R507") (pin "1") (pinfunction "1_1") (pintype "passive"))
    )
    (net (code "488") (name "Net-(Header24-Pad11)") (class "Default")
      (node (ref "Header24") (pin "11") (pintype "input"))
      (node (ref "R508") (pin "1") (pinfunction "1_1") (pintype "passive"))
    )
    (net (code "489") (name "Net-(Header24-Pad12)") (class "Default")
      (node (ref "Header24") (pin "12") (pintype "input"))
      (node (ref "R509") (pin "1") (pinfunction "1_1") (pintype "passive"))
    )
    (net (code "490") (name "Net-(Header24-Pad13)") (class "Default")
      (node (ref "Header24") (pin "13") (pintype "input"))
      (node (ref "R510") (pin "1") (pinfunction "1_1") (pintype "passive"))
    )
    (net (code "491") (name "Net-(Header24-Pad14)") (class "Default")
      (node (ref "Header24") (pin "14") (pintype "input"))
      (node (ref "R511") (pin "1") (pinfunction "1_1") (pintype "passive"))
    )
    (net (code "492") (name "Net-(Header24-Pad18)") (class "Default")
      (node (ref "Header24") (pin "18") (pintype "input"))
      (node (ref "R512") (pin "1") (pinfunction "1_1") (pintype "passive"))
    )
    (net (code "493") (name "Net-(Header24-Pad19)") (class "Default")
      (node (ref "Header24") (pin "19") (pintype "input"))
      (node (ref "R513") (pin "1") (pinfunction "1_1") (pintype "passive"))
    )
    (net (code "494") (name "Net-(Header24-Pad20)") (class "Default")
      (node (ref "Header24") (pin "20") (pintype "input"))
      (node (ref "R514") (pin "1") (pinfunction "1_1") (pintype "passive"))
    )
    (net (code "495") (name "Net-(Header24-Pad21)") (class "Default")
      (node (ref "Header24") (pin "21") (pintype "input"))
      (node (ref "R515") (pin "1") (pinfunction "1_1") (pintype "passive"))
    )
    (net (code "496") (name "Net-(Header24-Pad22)") (class "Default")
      (node (ref "Header24") (pin "22") (pintype "input"))
      (node (ref "R516") (pin "1") (pinfunction "1_1") (pintype "passive"))
    )
    (net (code "497") (name "Net-(Header24-Pad23)") (class "Default")
      (node (ref "Header24") (pin "23") (pintype "input"))
      (node (ref "R517") (pin "1") (pinfunction "1_1") (pintype "passive"))
    )
    (net (code "498") (name "Net-(Header24-Pad24)") (class "Default")
      (node (ref "Header24") (pin "24") (pintype "input"))
      (node (ref "R518") (pin "1") (pinfunction "1_1") (pintype "passive"))
    )
    (net (code "499") (name "Net-(Header25-Pad1)") (class "Default")
      (node (ref "Header25") (pin "1") (pintype "input"))
      (node (ref "R519") (pin "1") (pinfunction "1_1") (pintype "passive"))
    )
    (net (code "500") (name "Net-(Header25-Pad2)") (class "Default")
      (node (ref "Header25") (pin "2") (pintype "input"))
      (node (ref "R520") (pin "1") (pinfunction "1_1") (pintype "passive"))
    )
    (net (code "501") (name "Net-(Header25-Pad3)") (class "Default")
      (node (ref "Header25") (pin "3") (pintype "input"))
      (node (ref "R521") (pin "1") (pinfunction "1_1") (pintype "passive"))
    )
    (net (code "502") (name "Net-(Header25-Pad4)") (class "Default")
      (node (ref "Header25") (pin "4") (pintype "input"))
      (node (ref "R522") (pin "1") (pinfunction "1_1") (pintype "passive"))
    )
    (net (code "503") (name "Net-(Header25-Pad5)") (class "Default")
      (node (ref "Header25") (pin "5") (pintype "input"))
      (node (ref "R523") (pin "1") (pinfunction "1_1") (pintype "passive"))
    )
    (net (code "504") (name "Net-(Header25-Pad6)") (class "Default")
      (node (ref "Header25") (pin "6") (pintype "input"))
      (node (ref "R524") (pin "1") (pinfunction "1_1") (pintype "passive"))
    )
    (net (code "505") (name "Net-(Header25-Pad7)") (class "Default")
      (node (ref "Header25") (pin "7") (pintype "input"))
      (node (ref "R526") (pin "2") (pinfunction "2_2") (pintype "passive"))
    )
    (net (code "506") (name "Net-(Header25-Pad8)") (class "Default")
      (node (ref "Header25") (pin "8") (pintype "input"))
      (node (ref "R527") (pin "2") (pinfunction "2_2") (pintype "passive"))
    )
    (net (code "507") (name "Net-(Header25-Pad9)") (class "Default")
      (node (ref "Header25") (pin "9") (pintype "input"))
      (node (ref "R528") (pin "2") (pinfunction "2_2") (pintype "passive"))
    )
    (net (code "508") (name "Net-(Header25-Pad10)") (class "Default")
      (node (ref "Header25") (pin "10") (pintype "input"))
      (node (ref "R529") (pin "2") (pinfunction "2_2") (pintype "passive"))
    )
    (net (code "509") (name "Net-(Header25-Pad11)") (class "Default")
      (node (ref "Header25") (pin "11") (pintype "input"))
      (node (ref "R530") (pin "2") (pinfunction "2_2") (pintype "passive"))
    )
    (net (code "510") (name "Net-(Header25-Pad12)") (class "Default")
      (node (ref "Header25") (pin "12") (pintype "input"))
      (node (ref "R531") (pin "2") (pinfunction "2_2") (pintype "passive"))
    )
    (net (code "511") (name "Net-(Header25-Pad13)") (class "Default")
      (node (ref "Header25") (pin "13") (pintype "input"))
      (node (ref "R532") (pin "2") (pinfunction "2_2") (pintype "passive"))
    )
    (net (code "512") (name "Net-(Header25-Pad14)") (class "Default")
      (node (ref "Header25") (pin "14") (pintype "input"))
      (node (ref "R533") (pin "2") (pinfunction "2_2") (pintype "passive"))
    )
    (net (code "513") (name "Net-(Header25-Pad15)") (class "Default")
      (node (ref "Header25") (pin "15") (pintype "input"))
      (node (ref "R534") (pin "2") (pinfunction "2_2") (pintype "passive"))
    )
    (net (code "514") (name "Net-(Header25-Pad16)") (class "Default")
      (node (ref "Header25") (pin "16") (pintype "input"))
      (node (ref "R535") (pin "2") (pinfunction "2_2") (pintype "passive"))
    )
    (net (code "515") (name "Net-(Header25-Pad17)") (class "Default")
      (node (ref "Header25") (pin "17") (pintype "input"))
      (node (ref "R536") (pin "2") (pinfunction "2_2") (pintype "passive"))
    )
    (net (code "516") (name "Net-(Header25-Pad18)") (class "Default")
      (node (ref "Header25") (pin "18") (pintype "input"))
      (node (ref "R537") (pin "2") (pinfunction "2_2") (pintype "passive"))
    )
    (net (code "517") (name "Net-(Header25-Pad19)") (class "Default")
      (node (ref "Header25") (pin "19") (pintype "input"))
      (node (ref "R538") (pin "2") (pinfunction "2_2") (pintype "passive"))
    )
    (net (code "518") (name "Net-(Header25-Pad23)") (class "Default")
      (node (ref "Header25") (pin "23") (pintype "input"))
      (node (ref "R539") (pin "2") (pinfunction "2_2") (pintype "passive"))
    )
    (net (code "519") (name "Net-(Header25-Pad24)") (class "Default")
      (node (ref "Header25") (pin "24") (pintype "input"))
      (node (ref "R540") (pin "2") (pinfunction "2_2") (pintype "passive"))
    )
    (net (code "520") (name "Net-(Header26-Pad1)") (class "Default")
      (node (ref "Header26") (pin "1") (pintype "input"))
      (node (ref "R541") (pin "2") (pinfunction "2_2") (pintype "passive"))
    )
    (net (code "521") (name "Net-(Header26-Pad2)") (class "Default")
      (node (ref "Header26") (pin "2") (pintype "input"))
      (node (ref "R542") (pin "2") (pinfunction "2_2") (pintype "passive"))
    )
    (net (code "522") (name "Net-(Header26-Pad3)") (class "Default")
      (node (ref "Header26") (pin "3") (pintype "input"))
      (node (ref "R543") (pin "2") (pinfunction "2_2") (pintype "passive"))
    )
    (net (code "523") (name "Net-(Header26-Pad4)") (class "Default")
      (node (ref "Header26") (pin "4") (pintype "input"))
      (node (ref "R544") (pin "2") (pinfunction "2_2") (pintype "passive"))
    )
    (net (code "524") (name "Net-(Header26-Pad5)") (class "Default")
      (node (ref "Header26") (pin "5") (pintype "input"))
      (node (ref "R545") (pin "2") (pinfunction "2_2") (pintype "passive"))
    )
    (net (code "525") (name "Net-(Header26-Pad6)") (class "Default")
      (node (ref "Header26") (pin "6") (pintype "input"))
      (node (ref "R546") (pin "2") (pinfunction "2_2") (pintype "passive"))
    )
    (net (code "526") (name "Net-(Header26-Pad7)") (class "Default")
      (node (ref "Header26") (pin "7") (pintype "input"))
      (node (ref "R547") (pin "2") (pinfunction "2_2") (pintype "passive"))
    )
    (net (code "527") (name "Net-(Header26-Pad8)") (class "Default")
      (node (ref "Header26") (pin "8") (pintype "input"))
      (node (ref "R548") (pin "2") (pinfunction "2_2") (pintype "passive"))
    )
    (net (code "528") (name "Net-(Header26-Pad9)") (class "Default")
      (node (ref "Header26") (pin "9") (pintype "input"))
      (node (ref "R549") (pin "2") (pinfunction "2_2") (pintype "passive"))
    )
    (net (code "529") (name "Net-(Header26-Pad10)") (class "Default")
      (node (ref "Header26") (pin "10") (pintype "input"))
      (node (ref "R551") (pin "1") (pinfunction "1_1") (pintype "passive"))
    )
    (net (code "530") (name "Net-(Header26-Pad11)") (class "Default")
      (node (ref "Header26") (pin "11") (pintype "input"))
      (node (ref "R552") (pin "1") (pinfunction "1_1") (pintype "passive"))
    )
    (net (code "531") (name "Net-(Header26-Pad12)") (class "Default")
      (node (ref "Header26") (pin "12") (pintype "input"))
      (node (ref "R553") (pin "1") (pinfunction "1_1") (pintype "passive"))
    )
    (net (code "532") (name "Net-(Header26-Pad13)") (class "Default")
      (node (ref "Header26") (pin "13") (pintype "input"))
      (node (ref "R554") (pin "1") (pinfunction "1_1") (pintype "passive"))
    )
    (net (code "533") (name "Net-(Header26-Pad14)") (class "Default")
      (node (ref "Header26") (pin "14") (pintype "input"))
      (node (ref "R555") (pin "1") (pinfunction "1_1") (pintype "passive"))
    )
    (net (code "534") (name "Net-(Header26-Pad18)") (class "Default")
      (node (ref "Header26") (pin "18") (pintype "input"))
      (node (ref "R556") (pin "1") (pinfunction "1_1") (pintype "passive"))
    )
    (net (code "535") (name "Net-(Header26-Pad19)") (class "Default")
      (node (ref "Header26") (pin "19") (pintype "input"))
      (node (ref "R557") (pin "1") (pinfunction "1_1") (pintype "passive"))
    )
    (net (code "536") (name "Net-(Header26-Pad20)") (class "Default")
      (node (ref "Header26") (pin "20") (pintype "input"))
      (node (ref "R558") (pin "1") (pinfunction "1_1") (pintype "passive"))
    )
    (net (code "537") (name "Net-(Header26-Pad21)") (class "Default")
      (node (ref "Header26") (pin "21") (pintype "input"))
      (node (ref "R559") (pin "1") (pinfunction "1_1") (pintype "passive"))
    )
    (net (code "538") (name "Net-(Header26-Pad22)") (class "Default")
      (node (ref "Header26") (pin "22") (pintype "input"))
      (node (ref "R560") (pin "1") (pinfunction "1_1") (pintype "passive"))
    )
    (net (code "539") (name "Net-(Header26-Pad23)") (class "Default")
      (node (ref "Header26") (pin "23") (pintype "input"))
      (node (ref "R561") (pin "1") (pinfunction "1_1") (pintype "passive"))
    )
    (net (code "540") (name "Net-(Header26-Pad24)") (class "Default")
      (node (ref "Header26") (pin "24") (pintype "input"))
      (node (ref "R562") (pin "1") (pinfunction "1_1") (pintype "passive"))
    )
    (net (code "541") (name "Net-(Header27-Pad1)") (class "Default")
      (node (ref "Header27") (pin "1") (pintype "input"))
      (node (ref "R563") (pin "1") (pinfunction "1_1") (pintype "passive"))
    )
    (net (code "542") (name "Net-(Header27-Pad2)") (class "Default")
      (node (ref "Header27") (pin "2") (pintype "input"))
      (node (ref "R564") (pin "1") (pinfunction "1_1") (pintype "passive"))
    )
    (net (code "543") (name "Net-(Header27-Pad3)") (class "Default")
      (node (ref "Header27") (pin "3") (pintype "input"))
      (node (ref "R565") (pin "1") (pinfunction "1_1") (pintype "passive"))
    )
    (net (code "544") (name "Net-(Header27-Pad4)") (class "Default")
      (node (ref "Header27") (pin "4") (pintype "input"))
      (node (ref "R566") (pin "1") (pinfunction "1_1") (pintype "passive"))
    )
    (net (code "545") (name "Net-(Header27-Pad5)") (class "Default")
      (node (ref "Header27") (pin "5") (pintype "input"))
      (node (ref "R567") (pin "1") (pinfunction "1_1") (pintype "passive"))
    )
    (net (code "546") (name "Net-(Header27-Pad6)") (class "Default")
      (node (ref "Header27") (pin "6") (pintype "input"))
      (node (ref "R568") (pin "1") (pinfunction "1_1") (pintype "passive"))
    )
    (net (code "547") (name "Net-(Header27-Pad7)") (class "Default")
      (node (ref "Header27") (pin "7") (pintype "input"))
      (node (ref "R569") (pin "1") (pinfunction "1_1") (pintype "passive"))
    )
    (net (code "548") (name "Net-(Header27-Pad8)") (class "Default")
      (node (ref "Header27") (pin "8") (pintype "input"))
      (node (ref "R570") (pin "1") (pinfunction "1_1") (pintype "passive"))
    )
    (net (code "549") (name "Net-(Header27-Pad9)") (class "Default")
      (node (ref "Header27") (pin "9") (pintype "input"))
      (node (ref "R571") (pin "1") (pinfunction "1_1") (pintype "passive"))
    )
    (net (code "550") (name "Net-(Header27-Pad10)") (class "Default")
      (node (ref "Header27") (pin "10") (pintype "input"))
      (node (ref "R572") (pin "1") (pinfunction "1_1") (pintype "passive"))
    )
    (net (code "551") (name "Net-(Header27-Pad11)") (class "Default")
      (node (ref "Header27") (pin "11") (pintype "input"))
      (node (ref "R573") (pin "1") (pinfunction "1_1") (pintype "passive"))
    )
    (net (code "552") (name "Net-(Header27-Pad12)") (class "Default")
      (node (ref "Header27") (pin "12") (pintype "input"))
      (node (ref "R574") (pin "1") (pinfunction "1_1") (pintype "passive"))
    )
    (net (code "553") (name "Net-(Header27-Pad13)") (class "Default")
      (node (ref "Header27") (pin "13") (pintype "input"))
      (node (ref "R576") (pin "2") (pinfunction "2_2") (pintype "passive"))
    )
    (net (code "554") (name "Net-(Header27-Pad14)") (class "Default")
      (node (ref "Header27") (pin "14") (pintype "input"))
      (node (ref "R577") (pin "2") (pinfunction "2_2") (pintype "passive"))
    )
    (net (code "555") (name "Net-(Header27-Pad15)") (class "Default")
      (node (ref "Header27") (pin "15") (pintype "input"))
      (node (ref "R578") (pin "2") (pinfunction "2_2") (pintype "passive"))
    )
    (net (code "556") (name "Net-(Header27-Pad16)") (class "Default")
      (node (ref "Header27") (pin "16") (pintype "input"))
      (node (ref "R579") (pin "2") (pinfunction "2_2") (pintype "passive"))
    )
    (net (code "557") (name "Net-(Header27-Pad17)") (class "Default")
      (node (ref "Header27") (pin "17") (pintype "input"))
      (node (ref "R580") (pin "2") (pinfunction "2_2") (pintype "passive"))
    )
    (net (code "558") (name "Net-(Header27-Pad18)") (class "Default")
      (node (ref "Header27") (pin "18") (pintype "input"))
      (node (ref "R581") (pin "2") (pinfunction "2_2") (pintype "passive"))
    )
    (net (code "559") (name "Net-(Header28-Pad1)") (class "Default")
      (node (ref "Header28") (pin "1") (pintype "input"))
      (node (ref "R582") (pin "2") (pinfunction "2_2") (pintype "passive"))
    )
    (net (code "560") (name "Net-(Header28-Pad2)") (class "Default")
      (node (ref "Header28") (pin "2") (pintype "input"))
      (node (ref "R583") (pin "2") (pinfunction "2_2") (pintype "passive"))
    )
    (net (code "561") (name "Net-(Header28-Pad3)") (class "Default")
      (node (ref "Header28") (pin "3") (pintype "input"))
      (node (ref "R584") (pin "2") (pinfunction "2_2") (pintype "passive"))
    )
    (net (code "562") (name "Net-(Header28-Pad4)") (class "Default")
      (node (ref "Header28") (pin "4") (pintype "input"))
      (node (ref "R585") (pin "2") (pinfunction "2_2") (pintype "passive"))
    )
    (net (code "563") (name "Net-(Header28-Pad5)") (class "Default")
      (node (ref "Header28") (pin "5") (pintype "input"))
      (node (ref "R586") (pin "2") (pinfunction "2_2") (pintype "passive"))
    )
    (net (code "564") (name "Net-(Header28-Pad6)") (class "Default")
      (node (ref "Header28") (pin "6") (pintype "input"))
      (node (ref "R587") (pin "2") (pinfunction "2_2") (pintype "passive"))
    )
    (net (code "565") (name "Net-(Header28-Pad7)") (class "Default")
      (node (ref "Header28") (pin "7") (pintype "input"))
      (node (ref "R588") (pin "2") (pinfunction "2_2") (pintype "passive"))
    )
    (net (code "566") (name "Net-(Header28-Pad8)") (class "Default")
      (node (ref "Header28") (pin "8") (pintype "input"))
      (node (ref "R589") (pin "2") (pinfunction "2_2") (pintype "passive"))
    )
    (net (code "567") (name "Net-(Header28-Pad9)") (class "Default")
      (node (ref "Header28") (pin "9") (pintype "input"))
      (node (ref "R590") (pin "2") (pinfunction "2_2") (pintype "passive"))
    )
    (net (code "568") (name "Net-(Header28-Pad10)") (class "Default")
      (node (ref "Header28") (pin "10") (pintype "input"))
      (node (ref "R591") (pin "2") (pinfunction "2_2") (pintype "passive"))
    )
    (net (code "569") (name "Net-(Header28-Pad11)") (class "Default")
      (node (ref "Header28") (pin "11") (pintype "input"))
      (node (ref "R592") (pin "2") (pinfunction "2_2") (pintype "passive"))
    )
    (net (code "570") (name "Net-(Header28-Pad12)") (class "Default")
      (node (ref "Header28") (pin "12") (pintype "input"))
      (node (ref "R593") (pin "2") (pinfunction "2_2") (pintype "passive"))
    )
    (net (code "571") (name "Net-(Header28-Pad13)") (class "Default")
      (node (ref "Header28") (pin "13") (pintype "input"))
      (node (ref "R594") (pin "2") (pinfunction "2_2") (pintype "passive"))
    )
    (net (code "572") (name "Net-(Header28-Pad14)") (class "Default")
      (node (ref "Header28") (pin "14") (pintype "input"))
      (node (ref "R595") (pin "2") (pinfunction "2_2") (pintype "passive"))
    )
    (net (code "573") (name "Net-(Header28-Pad15)") (class "Default")
      (node (ref "Header28") (pin "15") (pintype "input"))
      (node (ref "R596") (pin "2") (pinfunction "2_2") (pintype "passive"))
    )
    (net (code "574") (name "Net-(Header28-Pad16)") (class "Default")
      (node (ref "Header28") (pin "16") (pintype "input"))
      (node (ref "R597") (pin "2") (pinfunction "2_2") (pintype "passive"))
    )
    (net (code "575") (name "Net-(Header28-Pad17)") (class "Default")
      (node (ref "Header28") (pin "17") (pintype "input"))
      (node (ref "R598") (pin "2") (pinfunction "2_2") (pintype "passive"))
    )
    (net (code "576") (name "Net-(Header28-Pad18)") (class "Default")
      (node (ref "Header28") (pin "18") (pintype "input"))
      (node (ref "R599") (pin "2") (pinfunction "2_2") (pintype "passive"))
    )
    (net (code "577") (name "Net-(Header29-Pad1)") (class "Default")
      (node (ref "Header29") (pin "1") (pintype "input"))
      (node (ref "R601") (pin "1") (pinfunction "1_1") (pintype "passive"))
    )
    (net (code "578") (name "Net-(Header29-Pad5)") (class "Default")
      (node (ref "Header29") (pin "5") (pintype "input"))
      (node (ref "R602") (pin "1") (pinfunction "1_1") (pintype "passive"))
    )
    (net (code "579") (name "Net-(Header29-Pad6)") (class "Default")
      (node (ref "Header29") (pin "6") (pintype "input"))
      (node (ref "R603") (pin "1") (pinfunction "1_1") (pintype "passive"))
    )
    (net (code "580") (name "Net-(Header29-Pad7)") (class "Default")
      (node (ref "Header29") (pin "7") (pintype "input"))
      (node (ref "R604") (pin "1") (pinfunction "1_1") (pintype "passive"))
    )
    (net (code "581") (name "Net-(Header29-Pad8)") (class "Default")
      (node (ref "Header29") (pin "8") (pintype "input"))
      (node (ref "R605") (pin "1") (pinfunction "1_1") (pintype "passive"))
    )
    (net (code "582") (name "Net-(Header29-Pad9)") (class "Default")
      (node (ref "Header29") (pin "9") (pintype "input"))
      (node (ref "R606") (pin "1") (pinfunction "1_1") (pintype "passive"))
    )
    (net (code "583") (name "Net-(Header29-Pad10)") (class "Default")
      (node (ref "Header29") (pin "10") (pintype "input"))
      (node (ref "R607") (pin "1") (pinfunction "1_1") (pintype "passive"))
    )
    (net (code "584") (name "Net-(Header29-Pad11)") (class "Default")
      (node (ref "Header29") (pin "11") (pintype "input"))
      (node (ref "R608") (pin "1") (pinfunction "1_1") (pintype "passive"))
    )
    (net (code "585") (name "Net-(Header29-Pad12)") (class "Default")
      (node (ref "Header29") (pin "12") (pintype "input"))
      (node (ref "R609") (pin "1") (pinfunction "1_1") (pintype "passive"))
    )
    (net (code "586") (name "Net-(Header29-Pad13)") (class "Default")
      (node (ref "Header29") (pin "13") (pintype "input"))
      (node (ref "R610") (pin "1") (pinfunction "1_1") (pintype "passive"))
    )
    (net (code "587") (name "Net-(Header29-Pad14)") (class "Default")
      (node (ref "Header29") (pin "14") (pintype "input"))
      (node (ref "R611") (pin "1") (pinfunction "1_1") (pintype "passive"))
    )
    (net (code "588") (name "Net-(Header29-Pad15)") (class "Default")
      (node (ref "Header29") (pin "15") (pintype "input"))
      (node (ref "R612") (pin "1") (pinfunction "1_1") (pintype "passive"))
    )
    (net (code "589") (name "Net-(Header29-Pad16)") (class "Default")
      (node (ref "Header29") (pin "16") (pintype "input"))
      (node (ref "R613") (pin "1") (pinfunction "1_1") (pintype "passive"))
    )
    (net (code "590") (name "Net-(Header29-Pad17)") (class "Default")
      (node (ref "Header29") (pin "17") (pintype "input"))
      (node (ref "R614") (pin "1") (pinfunction "1_1") (pintype "passive"))
    )
    (net (code "591") (name "Net-(Header29-Pad18)") (class "Default")
      (node (ref "Header29") (pin "18") (pintype "input"))
      (node (ref "R615") (pin "1") (pinfunction "1_1") (pintype "passive"))
    )
    (net (code "592") (name "Net-(Header30-Pad1)") (class "Default")
      (node (ref "Header30") (pin "1") (pintype "input"))
      (node (ref "R616") (pin "1") (pinfunction "1_1") (pintype "passive"))
    )
    (net (code "593") (name "Net-(Header30-Pad2)") (class "Default")
      (node (ref "Header30") (pin "2") (pintype "input"))
      (node (ref "R617") (pin "1") (pinfunction "1_1") (pintype "passive"))
    )
    (net (code "594") (name "Net-(Header30-Pad3)") (class "Default")
      (node (ref "Header30") (pin "3") (pintype "input"))
      (node (ref "R618") (pin "1") (pinfunction "1_1") (pintype "passive"))
    )
    (net (code "595") (name "Net-(Header30-Pad4)") (class "Default")
      (node (ref "Header30") (pin "4") (pintype "input"))
      (node (ref "R619") (pin "1") (pinfunction "1_1") (pintype "passive"))
    )
    (net (code "596") (name "Net-(Header30-Pad5)") (class "Default")
      (node (ref "Header30") (pin "5") (pintype "input"))
      (node (ref "R620") (pin "1") (pinfunction "1_1") (pintype "passive"))
    )
    (net (code "597") (name "Net-(Header30-Pad9)") (class "Default")
      (node (ref "Header30") (pin "9") (pintype "input"))
      (node (ref "R621") (pin "1") (pinfunction "1_1") (pintype "passive"))
    )
    (net (code "598") (name "Net-(Header30-Pad10)") (class "Default")
      (node (ref "Header30") (pin "10") (pintype "input"))
      (node (ref "R622") (pin "1") (pinfunction "1_1") (pintype "passive"))
    )
    (net (code "599") (name "Net-(Header30-Pad11)") (class "Default")
      (node (ref "Header30") (pin "11") (pintype "input"))
      (node (ref "R623") (pin "1") (pinfunction "1_1") (pintype "passive"))
    )
    (net (code "600") (name "Net-(Header30-Pad12)") (class "Default")
      (node (ref "Header30") (pin "12") (pintype "input"))
      (node (ref "R624") (pin "1") (pinfunction "1_1") (pintype "passive"))
    )
    (net (code "601") (name "Net-(Header30-Pad13)") (class "Default")
      (node (ref "Header30") (pin "13") (pintype "input"))
      (node (ref "R25") (pin "1") (pinfunction "1_1") (pintype "passive"))
    )
    (net (code "602") (name "Net-(Header30-Pad14)") (class "Default")
      (node (ref "Header30") (pin "14") (pintype "input"))
      (node (ref "R50") (pin "2") (pinfunction "2_2") (pintype "passive"))
    )
    (net (code "603") (name "Net-(Header30-Pad15)") (class "Default")
      (node (ref "Header30") (pin "15") (pintype "input"))
      (node (ref "R75") (pin "1") (pinfunction "1_1") (pintype "passive"))
    )
    (net (code "604") (name "Net-(Header30-Pad16)") (class "Default")
      (node (ref "Header30") (pin "16") (pintype "input"))
      (node (ref "R100") (pin "2") (pinfunction "2_2") (pintype "passive"))
    )
    (net (code "605") (name "Net-(Header30-Pad17)") (class "Default")
      (node (ref "Header30") (pin "17") (pintype "input"))
      (node (ref "R125") (pin "1") (pinfunction "1_1") (pintype "passive"))
    )
    (net (code "606") (name "Net-(Header30-Pad18)") (class "Default")
      (node (ref "Header30") (pin "18") (pintype "input"))
      (node (ref "R150") (pin "2") (pinfunction "2_2") (pintype "passive"))
    )
    (net (code "607") (name "Net-(Header31-Pad1)") (class "Default")
      (node (ref "Header31") (pin "1") (pintype "input"))
      (node (ref "R175") (pin "1") (pinfunction "1_1") (pintype "passive"))
    )
    (net (code "608") (name "Net-(Header31-Pad3)") (class "Default")
      (node (ref "Header31") (pin "3") (pintype "input"))
      (node (ref "R200") (pin "2") (pinfunction "2_2") (pintype "passive"))
    )
    (net (code "609") (name "Net-(Header31-Pad4)") (class "Default")
      (node (ref "Header31") (pin "4") (pintype "input"))
      (node (ref "R225") (pin "1") (pinfunction "1_1") (pintype "passive"))
    )
    (net (code "610") (name "Net-(Header31-Pad5)") (class "Default")
      (node (ref "Header31") (pin "5") (pintype "input"))
      (node (ref "R250") (pin "2") (pinfunction "2_2") (pintype "passive"))
    )
    (net (code "611") (name "Net-(Header31-Pad6)") (class "Default")
      (node (ref "Header31") (pin "6") (pintype "input"))
      (node (ref "R275") (pin "1") (pinfunction "1_1") (pintype "passive"))
    )
    (net (code "612") (name "Net-(Header31-Pad7)") (class "Default")
      (node (ref "Header31") (pin "7") (pintype "input"))
      (node (ref "R300") (pin "2") (pinfunction "2_2") (pintype "passive"))
    )
    (net (code "613") (name "Net-(Header31-Pad8)") (class "Default")
      (node (ref "Header31") (pin "8") (pintype "input"))
      (node (ref "R325") (pin "1") (pinfunction "1_1") (pintype "passive"))
    )
    (net (code "614") (name "Net-(Header31-Pad9)") (class "Default")
      (node (ref "Header31") (pin "9") (pintype "input"))
      (node (ref "R350") (pin "2") (pinfunction "2_2") (pintype "passive"))
    )
    (net (code "615") (name "Net-(Header31-Pad10)") (class "Default")
      (node (ref "Header31") (pin "10") (pintype "input"))
      (node (ref "R375") (pin "1") (pinfunction "1_1") (pintype "passive"))
    )
    (net (code "616") (name "Net-(Header32-Pad1)") (class "Default")
      (node (ref "Header32") (pin "1") (pintype "input"))
      (node (ref "R400") (pin "2") (pinfunction "2_2") (pintype "passive"))
    )
    (net (code "617") (name "Net-(Header32-Pad2)") (class "Default")
      (node (ref "Header32") (pin "2") (pintype "input"))
      (node (ref "R425") (pin "1") (pinfunction "1_1") (pintype "passive"))
    )
    (net (code "618") (name "Net-(Header32-Pad3)") (class "Default")
      (node (ref "Header32") (pin "3") (pintype "input"))
      (node (ref "R450") (pin "2") (pinfunction "2_2") (pintype "passive"))
    )
    (net (code "619") (name "Net-(Header32-Pad5)") (class "Default")
      (node (ref "Header32") (pin "5") (pintype "input"))
      (node (ref "R475") (pin "1") (pinfunction "1_1") (pintype "passive"))
    )
    (net (code "620") (name "Net-(Header32-Pad6)") (class "Default")
      (node (ref "Header32") (pin "6") (pintype "input"))
      (node (ref "R500") (pin "2") (pinfunction "2_2") (pintype "passive"))
    )
    (net (code "621") (name "Net-(Header32-Pad7)") (class "Default")
      (node (ref "Header32") (pin "7") (pintype "input"))
      (node (ref "R525") (pin "1") (pinfunction "1_1") (pintype "passive"))
    )
    (net (code "622") (name "Net-(Header32-Pad8)") (class "Default")
      (node (ref "Header32") (pin "8") (pintype "input"))
      (node (ref "R550") (pin "2") (pinfunction "2_2") (pintype "passive"))
    )
    (net (code "623") (name "Net-(Header32-Pad9)") (class "Default")
      (node (ref "Header32") (pin "9") (pintype "input"))
      (node (ref "R575") (pin "1") (pinfunction "1_1") (pintype "passive"))
    )
    (net (code "624") (name "Net-(Header32-Pad10)") (class "Default")
      (node (ref "Header32") (pin "10") (pintype "input"))
      (node (ref "R600") (pin "2") (pinfunction "2_2") (pintype "passive"))
    )
    (net (code "625") (name "SR1A") (class "Default")
      (node (ref "R1") (pin "2") (pinfunction "2_2") (pintype "passive"))
    )
    (net (code "626") (name "SR1B") (class "Default")
      (node (ref "R2") (pin "2") (pinfunction "2_2") (pintype "passive"))
    )
    (net (code "627") (name "SR1C") (class "Default")
      (node (ref "R3") (pin "2") (pinfunction "2_2") (pintype "passive"))
    )
    (net (code "628") (name "SR1D") (class "Default")
      (node (ref "R4") (pin "2") (pinfunction "2_2") (pintype "passive"))
    )
    (net (code "629") (name "SR1E") (class "Default")
      (node (ref "R5") (pin "2") (pinfunction "2_2") (pintype "passive"))
    )
    (net (code "630") (name "SR1F") (class "Default")
      (node (ref "R6") (pin "2") (pinfunction "2_2") (pintype "passive"))
    )
    (net (code "631") (name "SR1G") (class "Default")
      (node (ref "R7") (pin "2") (pinfunction "2_2") (pintype "passive"))
    )
    (net (code "632") (name "SR1H") (class "Default")
      (node (ref "R8") (pin "2") (pinfunction "2_2") (pintype "passive"))
    )
    (net (code "633") (name "SR2A") (class "Default")
      (node (ref "R9") (pin "2") (pinfunction "2_2") (pintype "passive"))
    )
    (net (code "634") (name "SR2B") (class "Default")
      (node (ref "R10") (pin "2") (pinfunction "2_2") (pintype "passive"))
    )
    (net (code "635") (name "SR2C") (class "Default")
      (node (ref "R11") (pin "2") (pinfunction "2_2") (pintype "passive"))
    )
    (net (code "636") (name "SR2D") (class "Default")
      (node (ref "R12") (pin "2") (pinfunction "2_2") (pintype "passive"))
    )
    (net (code "637") (name "SR2E") (class "Default")
      (node (ref "R13") (pin "2") (pinfunction "2_2") (pintype "passive"))
    )
    (net (code "638") (name "SR2F") (class "Default")
      (node (ref "R14") (pin "2") (pinfunction "2_2") (pintype "passive"))
    )
    (net (code "639") (name "SR2G") (class "Default")
      (node (ref "R15") (pin "2") (pinfunction "2_2") (pintype "passive"))
    )
    (net (code "640") (name "SR2H") (class "Default")
      (node (ref "R16") (pin "2") (pinfunction "2_2") (pintype "passive"))
    )
    (net (code "641") (name "SR3A") (class "Default")
      (node (ref "R17") (pin "2") (pinfunction "2_2") (pintype "passive"))
    )
    (net (code "642") (name "SR3B") (class "Default")
      (node (ref "R18") (pin "2") (pinfunction "2_2") (pintype "passive"))
    )
    (net (code "643") (name "SR3C") (class "Default")
      (node (ref "R19") (pin "2") (pinfunction "2_2") (pintype "passive"))
    )
    (net (code "644") (name "SR3D") (class "Default")
      (node (ref "R20") (pin "2") (pinfunction "2_2") (pintype "passive"))
    )
    (net (code "645") (name "SR3E") (class "Default")
      (node (ref "R21") (pin "2") (pinfunction "2_2") (pintype "passive"))
    )
    (net (code "646") (name "SR3F") (class "Default")
      (node (ref "R22") (pin "2") (pinfunction "2_2") (pintype "passive"))
    )
    (net (code "647") (name "SR3G") (class "Default")
      (node (ref "R23") (pin "2") (pinfunction "2_2") (pintype "passive"))
    )
    (net (code "648") (name "SR3H") (class "Default")
      (node (ref "R24") (pin "2") (pinfunction "2_2") (pintype "passive"))
    )
    (net (code "649") (name "SR4A") (class "Default")
      (node (ref "R26") (pin "1") (pinfunction "1_1") (pintype "passive"))
    )
    (net (code "650") (name "SR4B") (class "Default")
      (node (ref "R27") (pin "1") (pinfunction "1_1") (pintype "passive"))
    )
    (net (code "651") (name "SR4C") (class "Default")
      (node (ref "R28") (pin "1") (pinfunction "1_1") (pintype "passive"))
    )
    (net (code "652") (name "SR4D") (class "Default")
      (node (ref "R29") (pin "1") (pinfunction "1_1") (pintype "passive"))
    )
    (net (code "653") (name "SR4E") (class "Default")
      (node (ref "R30") (pin "1") (pinfunction "1_1") (pintype "passive"))
    )
    (net (code "654") (name "SR4F") (class "Default")
      (node (ref "R31") (pin "1") (pinfunction "1_1") (pintype "passive"))
    )
    (net (code "655") (name "SR4G") (class "Default")
      (node (ref "R32") (pin "1") (pinfunction "1_1") (pintype "passive"))
    )
    (net (code "656") (name "SR4H") (class "Default")
      (node (ref "R33") (pin "1") (pinfunction "1_1") (pintype "passive"))
    )
    (net (code "657") (name "SR5A") (class "Default")
      (node (ref "R34") (pin "1") (pinfunction "1_1") (pintype "passive"))
    )
    (net (code "658") (name "SR5B") (class "Default")
      (node (ref "R35") (pin "1") (pinfunction "1_1") (pintype "passive"))
    )
    (net (code "659") (name "SR5C") (class "Default")
      (node (ref "R36") (pin "1") (pinfunction "1_1") (pintype "passive"))
    )
    (net (code "660") (name "SR5D") (class "Default")
      (node (ref "R37") (pin "1") (pinfunction "1_1") (pintype "passive"))
    )
    (net (code "661") (name "SR5E") (class "Default")
      (node (ref "R38") (pin "1") (pinfunction "1_1") (pintype "passive"))
    )
    (net (code "662") (name "SR5F") (class "Default")
      (node (ref "R39") (pin "1") (pinfunction "1_1") (pintype "passive"))
    )
    (net (code "663") (name "SR5G") (class "Default")
      (node (ref "R40") (pin "1") (pinfunction "1_1") (pintype "passive"))
    )
    (net (code "664") (name "SR5H") (class "Default")
      (node (ref "R41") (pin "1") (pinfunction "1_1") (pintype "passive"))
    )
    (net (code "665") (name "SR6A") (class "Default")
      (node (ref "R42") (pin "1") (pinfunction "1_1") (pintype "passive"))
    )
    (net (code "666") (name "SR6B") (class "Default")
      (node (ref "R43") (pin "1") (pinfunction "1_1") (pintype "passive"))
    )
    (net (code "667") (name "SR6C") (class "Default")
      (node (ref "R44") (pin "1") (pinfunction "1_1") (pintype "passive"))
    )
    (net (code "668") (name "SR6D") (class "Default")
      (node (ref "R45") (pin "1") (pinfunction "1_1") (pintype "passive"))
    )
    (net (code "669") (name "SR6E") (class "Default")
      (node (ref "R46") (pin "1") (pinfunction "1_1") (pintype "passive"))
    )
    (net (code "670") (name "SR6F") (class "Default")
      (node (ref "R47") (pin "1") (pinfunction "1_1") (pintype "passive"))
    )
    (net (code "671") (name "SR6G") (class "Default")
      (node (ref "R48") (pin "1") (pinfunction "1_1") (pintype "passive"))
    )
    (net (code "672") (name "SR6H") (class "Default")
      (node (ref "R49") (pin "1") (pinfunction "1_1") (pintype "passive"))
    )
    (net (code "673") (name "SR7A") (class "Default")
      (node (ref "R51") (pin "2") (pinfunction "2_2") (pintype "passive"))
    )
    (net (code "674") (name "SR7B") (class "Default")
      (node (ref "R52") (pin "2") (pinfunction "2_2") (pintype "passive"))
    )
    (net (code "675") (name "SR7C") (class "Default")
      (node (ref "R53") (pin "2") (pinfunction "2_2") (pintype "passive"))
    )
    (net (code "676") (name "SR7D") (class "Default")
      (node (ref "R54") (pin "2") (pinfunction "2_2") (pintype "passive"))
    )
    (net (code "677") (name "SR7E") (class "Default")
      (node (ref "R55") (pin "2") (pinfunction "2_2") (pintype "passive"))
    )
    (net (code "678") (name "SR7F") (class "Default")
      (node (ref "R56") (pin "2") (pinfunction "2_2") (pintype "passive"))
    )
    (net (code "679") (name "SR7G") (class "Default")
      (node (ref "R57") (pin "2") (pinfunction "2_2") (pintype "passive"))
    )
    (net (code "680") (name "SR7H") (class "Default")
      (node (ref "R58") (pin "2") (pinfunction "2_2") (pintype "passive"))
    )
    (net (code "681") (name "SR8A") (class "Default")
      (node (ref "R59") (pin "2") (pinfunction "2_2") (pintype "passive"))
    )
    (net (code "682") (name "SR8B") (class "Default")
      (node (ref "R60") (pin "2") (pinfunction "2_2") (pintype "passive"))
    )
    (net (code "683") (name "SR8C") (class "Default")
      (node (ref "R61") (pin "2") (pinfunction "2_2") (pintype "passive"))
    )
    (net (code "684") (name "SR8D") (class "Default")
      (node (ref "R62") (pin "2") (pinfunction "2_2") (pintype "passive"))
    )
    (net (code "685") (name "SR8E") (class "Default")
      (node (ref "R63") (pin "2") (pinfunction "2_2") (pintype "passive"))
    )
    (net (code "686") (name "SR8F") (class "Default")
      (node (ref "R64") (pin "2") (pinfunction "2_2") (pintype "passive"))
    )
    (net (code "687") (name "SR8G") (class "Default")
      (node (ref "R65") (pin "2") (pinfunction "2_2") (pintype "passive"))
    )
    (net (code "688") (name "SR8H") (class "Default")
      (node (ref "R66") (pin "2") (pinfunction "2_2") (pintype "passive"))
    )
    (net (code "689") (name "SR9A") (class "Default")
      (node (ref "R67") (pin "2") (pinfunction "2_2") (pintype "passive"))
    )
    (net (code "690") (name "SR9B") (class "Default")
      (node (ref "R68") (pin "2") (pinfunction "2_2") (pintype "passive"))
    )
    (net (code "691") (name "SR9C") (class "Default")
      (node (ref "R69") (pin "2") (pinfunction "2_2") (pintype "passive"))
    )
    (net (code "692") (name "SR9D") (class "Default")
      (node (ref "R70") (pin "2") (pinfunction "2_2") (pintype "passive"))
    )
    (net (code "693") (name "SR9E") (class "Default")
      (node (ref "R71") (pin "2") (pinfunction "2_2") (pintype "passive"))
    )
    (net (code "694") (name "SR9F") (class "Default")
      (node (ref "R72") (pin "2") (pinfunction "2_2") (pintype "passive"))
    )
    (net (code "695") (name "SR9G") (class "Default")
      (node (ref "R73") (pin "2") (pinfunction "2_2") (pintype "passive"))
    )
    (net (code "696") (name "SR9H") (class "Default")
      (node (ref "R74") (pin "2") (pinfunction "2_2") (pintype "passive"))
    )
    (net (code "697") (name "SR10A") (class "Default")
      (node (ref "R76") (pin "1") (pinfunction "1_1") (pintype "passive"))
    )
    (net (code "698") (name "SR10B") (class "Default")
      (node (ref "R77") (pin "1") (pinfunction "1_1") (pintype "passive"))
    )
    (net (code "699") (name "SR10C") (class "Default")
      (node (ref "R78") (pin "1") (pinfunction "1_1") (pintype "passive"))
    )
    (net (code "700") (name "SR10D") (class "Default")
      (node (ref "R79") (pin "1") (pinfunction "1_1") (pintype "passive"))
    )
    (net (code "701") (name "SR10E") (class "Default")
      (node (ref "R80") (pin "1") (pinfunction "1_1") (pintype "passive"))
    )
    (net (code "702") (name "SR10F") (class "Default")
      (node (ref "R81") (pin "1") (pinfunction "1_1") (pintype "passive"))
    )
    (net (code "703") (name "SR10G") (class "Default")
      (node (ref "R82") (pin "1") (pinfunction "1_1") (pintype "passive"))
    )
    (net (code "704") (name "SR10H") (class "Default")
      (node (ref "R83") (pin "1") (pinfunction "1_1") (pintype "passive"))
    )
    (net (code "705") (name "SR11A") (class "Default")
      (node (ref "R84") (pin "1") (pinfunction "1_1") (pintype "passive"))
    )
    (net (code "706") (name "SR11B") (class "Default")
      (node (ref "R85") (pin "1") (pinfunction "1_1") (pintype "passive"))
    )
    (net (code "707") (name "SR11C") (class "Default")
      (node (ref "R86") (pin "1") (pinfunction "1_1") (pintype "passive"))
    )
    (net (code "708") (name "SR11D") (class "Default")
      (node (ref "R87") (pin "1") (pinfunction "1_1") (pintype "passive"))
    )
    (net (code "709") (name "SR11E") (class "Default")
      (node (ref "R88") (pin "1") (pinfunction "1_1") (pintype "passive"))
    )
    (net (code "710") (name "SR11F") (class "Default")
      (node (ref "R89") (pin "1") (pinfunction "1_1") (pintype "passive"))
    )
    (net (code "711") (name "SR11G") (class "Default")
      (node (ref "R90") (pin "1") (pinfunction "1_1") (pintype "passive"))
    )
    (net (code "712") (name "SR11H") (class "Default")
      (node (ref "R91") (pin "1") (pinfunction "1_1") (pintype "passive"))
    )
    (net (code "713") (name "SR12A") (class "Default")
      (node (ref "R92") (pin "1") (pinfunction "1_1") (pintype "passive"))
    )
    (net (code "714") (name "SR12B") (class "Default")
      (node (ref "R93") (pin "1") (pinfunction "1_1") (pintype "passive"))
    )
    (net (code "715") (name "SR12C") (class "Default")
      (node (ref "R94") (pin "1") (pinfunction "1_1") (pintype "passive"))
    )
    (net (code "716") (name "SR12D") (class "Default")
      (node (ref "R95") (pin "1") (pinfunction "1_1") (pintype "passive"))
    )
    (net (code "717") (name "SR12E") (class "Default")
      (node (ref "R96") (pin "1") (pinfunction "1_1") (pintype "passive"))
    )
    (net (code "718") (name "SR12F") (class "Default")
      (node (ref "R97") (pin "1") (pinfunction "1_1") (pintype "passive"))
    )
    (net (code "719") (name "SR12G") (class "Default")
      (node (ref "R98") (pin "1") (pinfunction "1_1") (pintype "passive"))
    )
    (net (code "720") (name "SR12H") (class "Default")
      (node (ref "R99") (pin "1") (pinfunction "1_1") (pintype "passive"))
    )
    (net (code "721") (name "SR13A") (class "Default")
      (node (ref "R101") (pin "2") (pinfunction "2_2") (pintype "passive"))
    )
    (net (code "722") (name "SR13B") (class "Default")
      (node (ref "R102") (pin "2") (pinfunction "2_2") (pintype "passive"))
    )
    (net (code "723") (name "SR13C") (class "Default")
      (node (ref "R103") (pin "2") (pinfunction "2_2") (pintype "passive"))
    )
    (net (code "724") (name "SR13D") (class "Default")
      (node (ref "R104") (pin "2") (pinfunction "2_2") (pintype "passive"))
    )
    (net (code "725") (name "SR13E") (class "Default")
      (node (ref "R105") (pin "2") (pinfunction "2_2") (pintype "passive"))
    )
    (net (code "726") (name "SR13F") (class "Default")
      (node (ref "R106") (pin "2") (pinfunction "2_2") (pintype "passive"))
    )
    (net (code "727") (name "SR13G") (class "Default")
      (node (ref "R107") (pin "2") (pinfunction "2_2") (pintype "passive"))
    )
    (net (code "728") (name "SR13H") (class "Default")
      (node (ref "R108") (pin "2") (pinfunction "2_2") (pintype "passive"))
    )
    (net (code "729") (name "SR14A") (class "Default")
      (node (ref "R109") (pin "2") (pinfunction "2_2") (pintype "passive"))
    )
    (net (code "730") (name "SR14B") (class "Default")
      (node (ref "R110") (pin "2") (pinfunction "2_2") (pintype "passive"))
    )
    (net (code "731") (name "SR14C") (class "Default")
      (node (ref "R111") (pin "2") (pinfunction "2_2") (pintype "passive"))
    )
    (net (code "732") (name "SR14D") (class "Default")
      (node (ref "R112") (pin "2") (pinfunction "2_2") (pintype "passive"))
    )
    (net (code "733") (name "SR14E") (class "Default")
      (node (ref "R113") (pin "2") (pinfunction "2_2") (pintype "passive"))
    )
    (net (code "734") (name "SR14F") (class "Default")
      (node (ref "R114") (pin "2") (pinfunction "2_2") (pintype "passive"))
    )
    (net (code "735") (name "SR14G") (class "Default")
      (node (ref "R115") (pin "2") (pinfunction "2_2") (pintype "passive"))
    )
    (net (code "736") (name "SR14H") (class "Default")
      (node (ref "R116") (pin "2") (pinfunction "2_2") (pintype "passive"))
    )
    (net (code "737") (name "SR15A") (class "Default")
      (node (ref "R117") (pin "2") (pinfunction "2_2") (pintype "passive"))
    )
    (net (code "738") (name "SR15B") (class "Default")
      (node (ref "R118") (pin "2") (pinfunction "2_2") (pintype "passive"))
    )
    (net (code "739") (name "SR15C") (class "Default")
      (node (ref "R119") (pin "2") (pinfunction "2_2") (pintype "passive"))
    )
    (net (code "740") (name "SR15D") (class "Default")
      (node (ref "R120") (pin "2") (pinfunction "2_2") (pintype "passive"))
    )
    (net (code "741") (name "SR15E") (class "Default")
      (node (ref "R121") (pin "2") (pinfunction "2_2") (pintype "passive"))
    )
    (net (code "742") (name "SR15F") (class "Default")
      (node (ref "R122") (pin "2") (pinfunction "2_2") (pintype "passive"))
    )
    (net (code "743") (name "SR15G") (class "Default")
      (node (ref "R123") (pin "2") (pinfunction "2_2") (pintype "passive"))
    )
    (net (code "744") (name "SR15H") (class "Default")
      (node (ref "R124") (pin "2") (pinfunction "2_2") (pintype "passive"))
    )
    (net (code "745") (name "SR16A") (class "Default")
      (node (ref "R126") (pin "1") (pinfunction "1_1") (pintype "passive"))
    )
    (net (code "746") (name "SR16B") (class "Default")
      (node (ref "R127") (pin "1") (pinfunction "1_1") (pintype "passive"))
    )
    (net (code "747") (name "SR16C") (class "Default")
      (node (ref "R128") (pin "1") (pinfunction "1_1") (pintype "passive"))
    )
    (net (code "748") (name "SR16D") (class "Default")
      (node (ref "R129") (pin "1") (pinfunction "1_1") (pintype "passive"))
    )
    (net (code "749") (name "SR16E") (class "Default")
      (node (ref "R130") (pin "1") (pinfunction "1_1") (pintype "passive"))
    )
    (net (code "750") (name "SR16F") (class "Default")
      (node (ref "R131") (pin "1") (pinfunction "1_1") (pintype "passive"))
    )
    (net (code "751") (name "SR16G") (class "Default")
      (node (ref "R132") (pin "1") (pinfunction "1_1") (pintype "passive"))
    )
    (net (code "752") (name "SR16H") (class "Default")
      (node (ref "R133") (pin "1") (pinfunction "1_1") (pintype "passive"))
    )
    (net (code "753") (name "SR17A") (class "Default")
      (node (ref "R134") (pin "1") (pinfunction "1_1") (pintype "passive"))
    )
    (net (code "754") (name "SR17B") (class "Default")
      (node (ref "R135") (pin "1") (pinfunction "1_1") (pintype "passive"))
    )
    (net (code "755") (name "SR17C") (class "Default")
      (node (ref "R136") (pin "1") (pinfunction "1_1") (pintype "passive"))
    )
    (net (code "756") (name "SR17D") (class "Default")
      (node (ref "R137") (pin "1") (pinfunction "1_1") (pintype "passive"))
    )
    (net (code "757") (name "SR17E") (class "Default")
      (node (ref "R138") (pin "1") (pinfunction "1_1") (pintype "passive"))
    )
    (net (code "758") (name "SR17F") (class "Default")
      (node (ref "R139") (pin "1") (pinfunction "1_1") (pintype "passive"))
    )
    (net (code "759") (name "SR17G") (class "Default")
      (node (ref "R140") (pin "1") (pinfunction "1_1") (pintype "passive"))
    )
    (net (code "760") (name "SR17H") (class "Default")
      (node (ref "R141") (pin "1") (pinfunction "1_1") (pintype "passive"))
    )
    (net (code "761") (name "SR18A") (class "Default")
      (node (ref "R142") (pin "1") (pinfunction "1_1") (pintype "passive"))
    )
    (net (code "762") (name "SR18B") (class "Default")
      (node (ref "R143") (pin "1") (pinfunction "1_1") (pintype "passive"))
    )
    (net (code "763") (name "SR18C") (class "Default")
      (node (ref "R144") (pin "1") (pinfunction "1_1") (pintype "passive"))
    )
    (net (code "764") (name "SR18D") (class "Default")
      (node (ref "R145") (pin "1") (pinfunction "1_1") (pintype "passive"))
    )
    (net (code "765") (name "SR18E") (class "Default")
      (node (ref "R146") (pin "1") (pinfunction "1_1") (pintype "passive"))
    )
    (net (code "766") (name "SR18F") (class "Default")
      (node (ref "R147") (pin "1") (pinfunction "1_1") (pintype "passive"))
    )
    (net (code "767") (name "SR18G") (class "Default")
      (node (ref "R148") (pin "1") (pinfunction "1_1") (pintype "passive"))
    )
    (net (code "768") (name "SR18H") (class "Default")
      (node (ref "R149") (pin "1") (pinfunction "1_1") (pintype "passive"))
    )
    (net (code "769") (name "SR19A") (class "Default")
      (node (ref "R151") (pin "2") (pinfunction "2_2") (pintype "passive"))
    )
    (net (code "770") (name "SR19B") (class "Default")
      (node (ref "R152") (pin "2") (pinfunction "2_2") (pintype "passive"))
    )
    (net (code "771") (name "SR19C") (class "Default")
      (node (ref "R153") (pin "2") (pinfunction "2_2") (pintype "passive"))
    )
    (net (code "772") (name "SR19D") (class "Default")
      (node (ref "R154") (pin "2") (pinfunction "2_2") (pintype "passive"))
    )
    (net (code "773") (name "SR19E") (class "Default")
      (node (ref "R155") (pin "2") (pinfunction "2_2") (pintype "passive"))
    )
    (net (code "774") (name "SR19F") (class "Default")
      (node (ref "R156") (pin "2") (pinfunction "2_2") (pintype "passive"))
    )
    (net (code "775") (name "SR19G") (class "Default")
      (node (ref "R157") (pin "2") (pinfunction "2_2") (pintype "passive"))
    )
    (net (code "776") (name "SR19H") (class "Default")
      (node (ref "R158") (pin "2") (pinfunction "2_2") (pintype "passive"))
    )
    (net (code "777") (name "SR20A") (class "Default")
      (node (ref "R159") (pin "2") (pinfunction "2_2") (pintype "passive"))
    )
    (net (code "778") (name "SR20B") (class "Default")
      (node (ref "R160") (pin "2") (pinfunction "2_2") (pintype "passive"))
    )
    (net (code "779") (name "SR20C") (class "Default")
      (node (ref "R161") (pin "2") (pinfunction "2_2") (pintype "passive"))
    )
    (net (code "780") (name "SR20D") (class "Default")
      (node (ref "R162") (pin "2") (pinfunction "2_2") (pintype "passive"))
    )
    (net (code "781") (name "SR20E") (class "Default")
      (node (ref "R163") (pin "2") (pinfunction "2_2") (pintype "passive"))
    )
    (net (code "782") (name "SR20F") (class "Default")
      (node (ref "R164") (pin "2") (pinfunction "2_2") (pintype "passive"))
    )
    (net (code "783") (name "SR20G") (class "Default")
      (node (ref "R165") (pin "2") (pinfunction "2_2") (pintype "passive"))
    )
    (net (code "784") (name "SR20H") (class "Default")
      (node (ref "R166") (pin "2") (pinfunction "2_2") (pintype "passive"))
    )
    (net (code "785") (name "SR21A") (class "Default")
      (node (ref "R167") (pin "2") (pinfunction "2_2") (pintype "passive"))
    )
    (net (code "786") (name "SR21B") (class "Default")
      (node (ref "R168") (pin "2") (pinfunction "2_2") (pintype "passive"))
    )
    (net (code "787") (name "SR21C") (class "Default")
      (node (ref "R169") (pin "2") (pinfunction "2_2") (pintype "passive"))
    )
    (net (code "788") (name "SR21D") (class "Default")
      (node (ref "R170") (pin "2") (pinfunction "2_2") (pintype "passive"))
    )
    (net (code "789") (name "SR21E") (class "Default")
      (node (ref "R171") (pin "2") (pinfunction "2_2") (pintype "passive"))
    )
    (net (code "790") (name "SR21F") (class "Default")
      (node (ref "R172") (pin "2") (pinfunction "2_2") (pintype "passive"))
    )
    (net (code "791") (name "SR21G") (class "Default")
      (node (ref "R173") (pin "2") (pinfunction "2_2") (pintype "passive"))
    )
    (net (code "792") (name "SR21H") (class "Default")
      (node (ref "R174") (pin "2") (pinfunction "2_2") (pintype "passive"))
    )
    (net (code "793") (name "SR22A") (class "Default")
      (node (ref "R176") (pin "1") (pinfunction "1_1") (pintype "passive"))
    )
    (net (code "794") (name "SR22B") (class "Default")
      (node (ref "R177") (pin "1") (pinfunction "1_1") (pintype "passive"))
    )
    (net (code "795") (name "SR22C") (class "Default")
      (node (ref "R178") (pin "1") (pinfunction "1_1") (pintype "passive"))
    )
    (net (code "796") (name "SR22D") (class "Default")
      (node (ref "R179") (pin "1") (pinfunction "1_1") (pintype "passive"))
    )
    (net (code "797") (name "SR22E") (class "Default")
      (node (ref "R180") (pin "1") (pinfunction "1_1") (pintype "passive"))
    )
    (net (code "798") (name "SR22F") (class "Default")
      (node (ref "R181") (pin "1") (pinfunction "1_1") (pintype "passive"))
    )
    (net (code "799") (name "SR22G") (class "Default")
      (node (ref "R182") (pin "1") (pinfunction "1_1") (pintype "passive"))
    )
    (net (code "800") (name "SR22H") (class "Default")
      (node (ref "R183") (pin "1") (pinfunction "1_1") (pintype "passive"))
    )
    (net (code "801") (name "SR23A") (class "Default")
      (node (ref "R184") (pin "1") (pinfunction "1_1") (pintype "passive"))
    )
    (net (code "802") (name "SR23B") (class "Default")
      (node (ref "R185") (pin "1") (pinfunction "1_1") (pintype "passive"))
    )
    (net (code "803") (name "SR23C") (class "Default")
      (node (ref "R186") (pin "1") (pinfunction "1_1") (pintype "passive"))
    )
    (net (code "804") (name "SR23D") (class "Default")
      (node (ref "R187") (pin "1") (pinfunction "1_1") (pintype "passive"))
    )
    (net (code "805") (name "SR23E") (class "Default")
      (node (ref "R188") (pin "1") (pinfunction "1_1") (pintype "passive"))
    )
    (net (code "806") (name "SR23F") (class "Default")
      (node (ref "R189") (pin "1") (pinfunction "1_1") (pintype "passive"))
    )
    (net (code "807") (name "SR23G") (class "Default")
      (node (ref "R190") (pin "1") (pinfunction "1_1") (pintype "passive"))
    )
    (net (code "808") (name "SR23H") (class "Default")
      (node (ref "R191") (pin "1") (pinfunction "1_1") (pintype "passive"))
    )
    (net (code "809") (name "SR24A") (class "Default")
      (node (ref "R192") (pin "1") (pinfunction "1_1") (pintype "passive"))
    )
    (net (code "810") (name "SR24B") (class "Default")
      (node (ref "R193") (pin "1") (pinfunction "1_1") (pintype "passive"))
    )
    (net (code "811") (name "SR24C") (class "Default")
      (node (ref "R194") (pin "1") (pinfunction "1_1") (pintype "passive"))
    )
    (net (code "812") (name "SR24D") (class "Default")
      (node (ref "R195") (pin "1") (pinfunction "1_1") (pintype "passive"))
    )
    (net (code "813") (name "SR24E") (class "Default")
      (node (ref "R196") (pin "1") (pinfunction "1_1") (pintype "passive"))
    )
    (net (code "814") (name "SR24F") (class "Default")
      (node (ref "R197") (pin "1") (pinfunction "1_1") (pintype "passive"))
    )
    (net (code "815") (name "SR24G") (class "Default")
      (node (ref "R198") (pin "1") (pinfunction "1_1") (pintype "passive"))
    )
    (net (code "816") (name "SR24H") (class "Default")
      (node (ref "R199") (pin "1") (pinfunction "1_1") (pintype "passive"))
    )
    (net (code "817") (name "SR25A") (class "Default")
      (node (ref "R201") (pin "2") (pinfunction "2_2") (pintype "passive"))
    )
    (net (code "818") (name "SR25B") (class "Default")
      (node (ref "R202") (pin "2") (pinfunction "2_2") (pintype "passive"))
    )
    (net (code "819") (name "SR25C") (class "Default")
      (node (ref "R203") (pin "2") (pinfunction "2_2") (pintype "passive"))
    )
    (net (code "820") (name "SR25D") (class "Default")
      (node (ref "R204") (pin "2") (pinfunction "2_2") (pintype "passive"))
    )
    (net (code "821") (name "SR25E") (class "Default")
      (node (ref "R205") (pin "2") (pinfunction "2_2") (pintype "passive"))
    )
    (net (code "822") (name "SR25F") (class "Default")
      (node (ref "R206") (pin "2") (pinfunction "2_2") (pintype "passive"))
    )
    (net (code "823") (name "SR25G") (class "Default")
      (node (ref "R207") (pin "2") (pinfunction "2_2") (pintype "passive"))
    )
    (net (code "824") (name "SR25H") (class "Default")
      (node (ref "R208") (pin "2") (pinfunction "2_2") (pintype "passive"))
    )
    (net (code "825") (name "SR26A") (class "Default")
      (node (ref "R209") (pin "2") (pinfunction "2_2") (pintype "passive"))
    )
    (net (code "826") (name "SR26B") (class "Default")
      (node (ref "R210") (pin "2") (pinfunction "2_2") (pintype "passive"))
    )
    (net (code "827") (name "SR26C") (class "Default")
      (node (ref "R211") (pin "2") (pinfunction "2_2") (pintype "passive"))
    )
    (net (code "828") (name "SR26D") (class "Default")
      (node (ref "R212") (pin "2") (pinfunction "2_2") (pintype "passive"))
    )
    (net (code "829") (name "SR26E") (class "Default")
      (node (ref "R213") (pin "2") (pinfunction "2_2") (pintype "passive"))
    )
    (net (code "830") (name "SR26F") (class "Default")
      (node (ref "R214") (pin "2") (pinfunction "2_2") (pintype "passive"))
    )
    (net (code "831") (name "SR26G") (class "Default")
      (node (ref "R215") (pin "2") (pinfunction "2_2") (pintype "passive"))
    )
    (net (code "832") (name "SR26H") (class "Default")
      (node (ref "R216") (pin "2") (pinfunction "2_2") (pintype "passive"))
    )
    (net (code "833") (name "SR27A") (class "Default")
      (node (ref "R217") (pin "2") (pinfunction "2_2") (pintype "passive"))
    )
    (net (code "834") (name "SR27B") (class "Default")
      (node (ref "R218") (pin "2") (pinfunction "2_2") (pintype "passive"))
    )
    (net (code "835") (name "SR27C") (class "Default")
      (node (ref "R219") (pin "2") (pinfunction "2_2") (pintype "passive"))
    )
    (net (code "836") (name "SR27D") (class "Default")
      (node (ref "R220") (pin "2") (pinfunction "2_2") (pintype "passive"))
    )
    (net (code "837") (name "SR27E") (class "Default")
      (node (ref "R221") (pin "2") (pinfunction "2_2") (pintype "passive"))
    )
    (net (code "838") (name "SR27F") (class "Default")
      (node (ref "R222") (pin "2") (pinfunction "2_2") (pintype "passive"))
    )
    (net (code "839") (name "SR27G") (class "Default")
      (node (ref "R223") (pin "2") (pinfunction "2_2") (pintype "passive"))
    )
    (net (code "840") (name "SR27H") (class "Default")
      (node (ref "R224") (pin "2") (pinfunction "2_2") (pintype "passive"))
    )
    (net (code "841") (name "SR28A") (class "Default")
      (node (ref "R226") (pin "1") (pinfunction "1_1") (pintype "passive"))
    )
    (net (code "842") (name "SR28B") (class "Default")
      (node (ref "R227") (pin "1") (pinfunction "1_1") (pintype "passive"))
    )
    (net (code "843") (name "SR28C") (class "Default")
      (node (ref "R228") (pin "1") (pinfunction "1_1") (pintype "passive"))
    )
    (net (code "844") (name "SR28D") (class "Default")
      (node (ref "R229") (pin "1") (pinfunction "1_1") (pintype "passive"))
    )
    (net (code "845") (name "SR28E") (class "Default")
      (node (ref "R230") (pin "1") (pinfunction "1_1") (pintype "passive"))
    )
    (net (code "846") (name "SR28F") (class "Default")
      (node (ref "R231") (pin "1") (pinfunction "1_1") (pintype "passive"))
    )
    (net (code "847") (name "SR28G") (class "Default")
      (node (ref "R232") (pin "1") (pinfunction "1_1") (pintype "passive"))
    )
    (net (code "848") (name "SR28H") (class "Default")
      (node (ref "R233") (pin "1") (pinfunction "1_1") (pintype "passive"))
    )
    (net (code "849") (name "SR29A") (class "Default")
      (node (ref "R234") (pin "1") (pinfunction "1_1") (pintype "passive"))
    )
    (net (code "850") (name "SR29B") (class "Default")
      (node (ref "R235") (pin "1") (pinfunction "1_1") (pintype "passive"))
    )
    (net (code "851") (name "SR29C") (class "Default")
      (node (ref "R236") (pin "1") (pinfunction "1_1") (pintype "passive"))
    )
    (net (code "852") (name "SR29D") (class "Default")
      (node (ref "R237") (pin "1") (pinfunction "1_1") (pintype "passive"))
    )
    (net (code "853") (name "SR29E") (class "Default")
      (node (ref "R238") (pin "1") (pinfunction "1_1") (pintype "passive"))
    )
    (net (code "854") (name "SR29F") (class "Default")
      (node (ref "R239") (pin "1") (pinfunction "1_1") (pintype "passive"))
    )
    (net (code "855") (name "SR29G") (class "Default")
      (node (ref "R240") (pin "1") (pinfunction "1_1") (pintype "passive"))
    )
    (net (code "856") (name "SR29H") (class "Default")
      (node (ref "R241") (pin "1") (pinfunction "1_1") (pintype "passive"))
    )
    (net (code "857") (name "SR30A") (class "Default")
      (node (ref "R242") (pin "1") (pinfunction "1_1") (pintype "passive"))
    )
    (net (code "858") (name "SR30B") (class "Default")
      (node (ref "R243") (pin "1") (pinfunction "1_1") (pintype "passive"))
    )
    (net (code "859") (name "SR30C") (class "Default")
      (node (ref "R244") (pin "1") (pinfunction "1_1") (pintype "passive"))
    )
    (net (code "860") (name "SR30D") (class "Default")
      (node (ref "R245") (pin "1") (pinfunction "1_1") (pintype "passive"))
    )
    (net (code "861") (name "SR30E") (class "Default")
      (node (ref "R246") (pin "1") (pinfunction "1_1") (pintype "passive"))
    )
    (net (code "862") (name "SR30F") (class "Default")
      (node (ref "R247") (pin "1") (pinfunction "1_1") (pintype "passive"))
    )
    (net (code "863") (name "SR30G") (class "Default")
      (node (ref "R248") (pin "1") (pinfunction "1_1") (pintype "passive"))
    )
    (net (code "864") (name "SR30H") (class "Default")
      (node (ref "R249") (pin "1") (pinfunction "1_1") (pintype "passive"))
    )
    (net (code "865") (name "SR31A") (class "Default")
      (node (ref "R251") (pin "2") (pinfunction "2_2") (pintype "passive"))
    )
    (net (code "866") (name "SR31B") (class "Default")
      (node (ref "R252") (pin "2") (pinfunction "2_2") (pintype "passive"))
    )
    (net (code "867") (name "SR31C") (class "Default")
      (node (ref "R253") (pin "2") (pinfunction "2_2") (pintype "passive"))
    )
    (net (code "868") (name "SR31D") (class "Default")
      (node (ref "R254") (pin "2") (pinfunction "2_2") (pintype "passive"))
    )
    (net (code "869") (name "SR31E") (class "Default")
      (node (ref "R255") (pin "2") (pinfunction "2_2") (pintype "passive"))
    )
    (net (code "870") (name "SR31F") (class "Default")
      (node (ref "R256") (pin "2") (pinfunction "2_2") (pintype "passive"))
    )
    (net (code "871") (name "SR31G") (class "Default")
      (node (ref "R257") (pin "2") (pinfunction "2_2") (pintype "passive"))
    )
    (net (code "872") (name "SR31H") (class "Default")
      (node (ref "R258") (pin "2") (pinfunction "2_2") (pintype "passive"))
    )
    (net (code "873") (name "SR32A") (class "Default")
      (node (ref "R259") (pin "2") (pinfunction "2_2") (pintype "passive"))
    )
    (net (code "874") (name "SR32B") (class "Default")
      (node (ref "R260") (pin "2") (pinfunction "2_2") (pintype "passive"))
    )
    (net (code "875") (name "SR32C") (class "Default")
      (node (ref "R261") (pin "2") (pinfunction "2_2") (pintype "passive"))
    )
    (net (code "876") (name "SR32D") (class "Default")
      (node (ref "R262") (pin "2") (pinfunction "2_2") (pintype "passive"))
    )
    (net (code "877") (name "SR32E") (class "Default")
      (node (ref "R263") (pin "2") (pinfunction "2_2") (pintype "passive"))
    )
    (net (code "878") (name "SR32F") (class "Default")
      (node (ref "R264") (pin "2") (pinfunction "2_2") (pintype "passive"))
    )
    (net (code "879") (name "SR32G") (class "Default")
      (node (ref "R265") (pin "2") (pinfunction "2_2") (pintype "passive"))
    )
    (net (code "880") (name "SR32H") (class "Default")
      (node (ref "R266") (pin "2") (pinfunction "2_2") (pintype "passive"))
    )
    (net (code "881") (name "SR33A") (class "Default")
      (node (ref "R267") (pin "2") (pinfunction "2_2") (pintype "passive"))
    )
    (net (code "882") (name "SR33B") (class "Default")
      (node (ref "R268") (pin "2") (pinfunction "2_2") (pintype "passive"))
    )
    (net (code "883") (name "SR33C") (class "Default")
      (node (ref "R269") (pin "2") (pinfunction "2_2") (pintype "passive"))
    )
    (net (code "884") (name "SR33D") (class "Default")
      (node (ref "R270") (pin "2") (pinfunction "2_2") (pintype "passive"))
    )
    (net (code "885") (name "SR33E") (class "Default")
      (node (ref "R271") (pin "2") (pinfunction "2_2") (pintype "passive"))
    )
    (net (code "886") (name "SR33F") (class "Default")
      (node (ref "R272") (pin "2") (pinfunction "2_2") (pintype "passive"))
    )
    (net (code "887") (name "SR33G") (class "Default")
      (node (ref "R273") (pin "2") (pinfunction "2_2") (pintype "passive"))
    )
    (net (code "888") (name "SR33H") (class "Default")
      (node (ref "R274") (pin "2") (pinfunction "2_2") (pintype "passive"))
    )
    (net (code "889") (name "SR34A") (class "Default")
      (node (ref "R276") (pin "1") (pinfunction "1_1") (pintype "passive"))
    )
    (net (code "890") (name "SR34B") (class "Default")
      (node (ref "R277") (pin "1") (pinfunction "1_1") (pintype "passive"))
    )
    (net (code "891") (name "SR34C") (class "Default")
      (node (ref "R278") (pin "1") (pinfunction "1_1") (pintype "passive"))
    )
    (net (code "892") (name "SR34D") (class "Default")
      (node (ref "R279") (pin "1") (pinfunction "1_1") (pintype "passive"))
    )
    (net (code "893") (name "SR34E") (class "Default")
      (node (ref "R280") (pin "1") (pinfunction "1_1") (pintype "passive"))
    )
    (net (code "894") (name "SR34F") (class "Default")
      (node (ref "R281") (pin "1") (pinfunction "1_1") (pintype "passive"))
    )
    (net (code "895") (name "SR34G") (class "Default")
      (node (ref "R282") (pin "1") (pinfunction "1_1") (pintype "passive"))
    )
    (net (code "896") (name "SR34H") (class "Default")
      (node (ref "R283") (pin "1") (pinfunction "1_1") (pintype "passive"))
    )
    (net (code "897") (name "SR35A") (class "Default")
      (node (ref "R284") (pin "1") (pinfunction "1_1") (pintype "passive"))
    )
    (net (code "898") (name "SR35B") (class "Default")
      (node (ref "R285") (pin "1") (pinfunction "1_1") (pintype "passive"))
    )
    (net (code "899") (name "SR35C") (class "Default")
      (node (ref "R286") (pin "1") (pinfunction "1_1") (pintype "passive"))
    )
    (net (code "900") (name "SR35D") (class "Default")
      (node (ref "R287") (pin "1") (pinfunction "1_1") (pintype "passive"))
    )
    (net (code "901") (name "SR35E") (class "Default")
      (node (ref "R288") (pin "1") (pinfunction "1_1") (pintype "passive"))
    )
    (net (code "902") (name "SR35F") (class "Default")
      (node (ref "R289") (pin "1") (pinfunction "1_1") (pintype "passive"))
    )
    (net (code "903") (name "SR35G") (class "Default")
      (node (ref "R290") (pin "1") (pinfunction "1_1") (pintype "passive"))
    )
    (net (code "904") (name "SR35H") (class "Default")
      (node (ref "R291") (pin "1") (pinfunction "1_1") (pintype "passive"))
    )
    (net (code "905") (name "SR36A") (class "Default")
      (node (ref "R292") (pin "1") (pinfunction "1_1") (pintype "passive"))
    )
    (net (code "906") (name "SR36B") (class "Default")
      (node (ref "R293") (pin "1") (pinfunction "1_1") (pintype "passive"))
    )
    (net (code "907") (name "SR36C") (class "Default")
      (node (ref "R294") (pin "1") (pinfunction "1_1") (pintype "passive"))
    )
    (net (code "908") (name "SR36D") (class "Default")
      (node (ref "R295") (pin "1") (pinfunction "1_1") (pintype "passive"))
    )
    (net (code "909") (name "SR36E") (class "Default")
      (node (ref "R296") (pin "1") (pinfunction "1_1") (pintype "passive"))
    )
    (net (code "910") (name "SR36F") (class "Default")
      (node (ref "R297") (pin "1") (pinfunction "1_1") (pintype "passive"))
    )
    (net (code "911") (name "SR36G") (class "Default")
      (node (ref "R298") (pin "1") (pinfunction "1_1") (pintype "passive"))
    )
    (net (code "912") (name "SR36H") (class "Default")
      (node (ref "R299") (pin "1") (pinfunction "1_1") (pintype "passive"))
    )
    (net (code "913") (name "SR37A") (class "Default")
      (node (ref "R301") (pin "2") (pinfunction "2_2") (pintype "passive"))
    )
    (net (code "914") (name "SR37B") (class "Default")
      (node (ref "R302") (pin "2") (pinfunction "2_2") (pintype "passive"))
    )
    (net (code "915") (name "SR37C") (class "Default")
      (node (ref "R303") (pin "2") (pinfunction "2_2") (pintype "passive"))
    )
    (net (code "916") (name "SR37D") (class "Default")
      (node (ref "R304") (pin "2") (pinfunction "2_2") (pintype "passive"))
    )
    (net (code "917") (name "SR37E") (class "Default")
      (node (ref "R305") (pin "2") (pinfunction "2_2") (pintype "passive"))
    )
    (net (code "918") (name "SR37F") (class "Default")
      (node (ref "R306") (pin "2") (pinfunction "2_2") (pintype "passive"))
    )
    (net (code "919") (name "SR37G") (class "Default")
      (node (ref "R307") (pin "2") (pinfunction "2_2") (pintype "passive"))
    )
    (net (code "920") (name "SR37H") (class "Default")
      (node (ref "R308") (pin "2") (pinfunction "2_2") (pintype "passive"))
    )
    (net (code "921") (name "SR38A") (class "Default")
      (node (ref "R309") (pin "2") (pinfunction "2_2") (pintype "passive"))
    )
    (net (code "922") (name "SR38B") (class "Default")
      (node (ref "R310") (pin "2") (pinfunction "2_2") (pintype "passive"))
    )
    (net (code "923") (name "SR38C") (class "Default")
      (node (ref "R311") (pin "2") (pinfunction "2_2") (pintype "passive"))
    )
    (net (code "924") (name "SR38D") (class "Default")
      (node (ref "R312") (pin "2") (pinfunction "2_2") (pintype "passive"))
    )
    (net (code "925") (name "SR38E") (class "Default")
      (node (ref "R313") (pin "2") (pinfunction "2_2") (pintype "passive"))
    )
    (net (code "926") (name "SR38F") (class "Default")
      (node (ref "R314") (pin "2") (pinfunction "2_2") (pintype "passive"))
    )
    (net (code "927") (name "SR38G") (class "Default")
      (node (ref "R315") (pin "2") (pinfunction "2_2") (pintype "passive"))
    )
    (net (code "928") (name "SR38H") (class "Default")
      (node (ref "R316") (pin "2") (pinfunction "2_2") (pintype "passive"))
    )
    (net (code "929") (name "SR39A") (class "Default")
      (node (ref "R317") (pin "2") (pinfunction "2_2") (pintype "passive"))
    )
    (net (code "930") (name "SR39B") (class "Default")
      (node (ref "R318") (pin "2") (pinfunction "2_2") (pintype "passive"))
    )
    (net (code "931") (name "SR39C") (class "Default")
      (node (ref "R319") (pin "2") (pinfunction "2_2") (pintype "passive"))
    )
    (net (code "932") (name "SR39D") (class "Default")
      (node (ref "R320") (pin "2") (pinfunction "2_2") (pintype "passive"))
    )
    (net (code "933") (name "SR39E") (class "Default")
      (node (ref "R321") (pin "2") (pinfunction "2_2") (pintype "passive"))
    )
    (net (code "934") (name "SR39F") (class "Default")
      (node (ref "R322") (pin "2") (pinfunction "2_2") (pintype "passive"))
    )
    (net (code "935") (name "SR39G") (class "Default")
      (node (ref "R323") (pin "2") (pinfunction "2_2") (pintype "passive"))
    )
    (net (code "936") (name "SR39H") (class "Default")
      (node (ref "R324") (pin "2") (pinfunction "2_2") (pintype "passive"))
    )
    (net (code "937") (name "SR40A") (class "Default")
      (node (ref "R326") (pin "1") (pinfunction "1_1") (pintype "passive"))
    )
    (net (code "938") (name "SR40B") (class "Default")
      (node (ref "R327") (pin "1") (pinfunction "1_1") (pintype "passive"))
    )
    (net (code "939") (name "SR40C") (class "Default")
      (node (ref "R328") (pin "1") (pinfunction "1_1") (pintype "passive"))
    )
    (net (code "940") (name "SR40D") (class "Default")
      (node (ref "R329") (pin "1") (pinfunction "1_1") (pintype "passive"))
    )
    (net (code "941") (name "SR40E") (class "Default")
      (node (ref "R330") (pin "1") (pinfunction "1_1") (pintype "passive"))
    )
    (net (code "942") (name "SR40F") (class "Default")
      (node (ref "R331") (pin "1") (pinfunction "1_1") (pintype "passive"))
    )
    (net (code "943") (name "SR40G") (class "Default")
      (node (ref "R332") (pin "1") (pinfunction "1_1") (pintype "passive"))
    )
    (net (code "944") (name "SR40H") (class "Default")
      (node (ref "R333") (pin "1") (pinfunction "1_1") (pintype "passive"))
    )
    (net (code "945") (name "SR41A") (class "Default")
      (node (ref "R334") (pin "1") (pinfunction "1_1") (pintype "passive"))
    )
    (net (code "946") (name "SR41B") (class "Default")
      (node (ref "R335") (pin "1") (pinfunction "1_1") (pintype "passive"))
    )
    (net (code "947") (name "SR41C") (class "Default")
      (node (ref "R336") (pin "1") (pinfunction "1_1") (pintype "passive"))
    )
    (net (code "948") (name "SR41D") (class "Default")
      (node (ref "R337") (pin "1") (pinfunction "1_1") (pintype "passive"))
    )
    (net (code "949") (name "SR41E") (class "Default")
      (node (ref "R338") (pin "1") (pinfunction "1_1") (pintype "passive"))
    )
    (net (code "950") (name "SR41F") (class "Default")
      (node (ref "R339") (pin "1") (pinfunction "1_1") (pintype "passive"))
    )
    (net (code "951") (name "SR41G") (class "Default")
      (node (ref "R340") (pin "1") (pinfunction "1_1") (pintype "passive"))
    )
    (net (code "952") (name "SR41H") (class "Default")
      (node (ref "R341") (pin "1") (pinfunction "1_1") (pintype "passive"))
    )
    (net (code "953") (name "SR42A") (class "Default")
      (node (ref "R342") (pin "1") (pinfunction "1_1") (pintype "passive"))
    )
    (net (code "954") (name "SR42B") (class "Default")
      (node (ref "R343") (pin "1") (pinfunction "1_1") (pintype "passive"))
    )
    (net (code "955") (name "SR42C") (class "Default")
      (node (ref "R344") (pin "1") (pinfunction "1_1") (pintype "passive"))
    )
    (net (code "956") (name "SR42D") (class "Default")
      (node (ref "R345") (pin "1") (pinfunction "1_1") (pintype "passive"))
    )
    (net (code "957") (name "SR42E") (class "Default")
      (node (ref "R346") (pin "1") (pinfunction "1_1") (pintype "passive"))
    )
    (net (code "958") (name "SR42F") (class "Default")
      (node (ref "R347") (pin "1") (pinfunction "1_1") (pintype "passive"))
    )
    (net (code "959") (name "SR42G") (class "Default")
      (node (ref "R348") (pin "1") (pinfunction "1_1") (pintype "passive"))
    )
    (net (code "960") (name "SR42H") (class "Default")
      (node (ref "R349") (pin "1") (pinfunction "1_1") (pintype "passive"))
    )
    (net (code "961") (name "SR43A") (class "Default")
      (node (ref "R351") (pin "2") (pinfunction "2_2") (pintype "passive"))
    )
    (net (code "962") (name "SR43B") (class "Default")
      (node (ref "R352") (pin "2") (pinfunction "2_2") (pintype "passive"))
    )
    (net (code "963") (name "SR43C") (class "Default")
      (node (ref "R353") (pin "2") (pinfunction "2_2") (pintype "passive"))
    )
    (net (code "964") (name "SR43D") (class "Default")
      (node (ref "R354") (pin "2") (pinfunction "2_2") (pintype "passive"))
    )
    (net (code "965") (name "SR43E") (class "Default")
      (node (ref "R355") (pin "2") (pinfunction "2_2") (pintype "passive"))
    )
    (net (code "966") (name "SR43F") (class "Default")
      (node (ref "R356") (pin "2") (pinfunction "2_2") (pintype "passive"))
    )
    (net (code "967") (name "SR43G") (class "Default")
      (node (ref "R357") (pin "2") (pinfunction "2_2") (pintype "passive"))
    )
    (net (code "968") (name "SR43H") (class "Default")
      (node (ref "R358") (pin "2") (pinfunction "2_2") (pintype "passive"))
    )
    (net (code "969") (name "SR44A") (class "Default")
      (node (ref "R359") (pin "2") (pinfunction "2_2") (pintype "passive"))
    )
    (net (code "970") (name "SR44B") (class "Default")
      (node (ref "R360") (pin "2") (pinfunction "2_2") (pintype "passive"))
    )
    (net (code "971") (name "SR44C") (class "Default")
      (node (ref "R361") (pin "2") (pinfunction "2_2") (pintype "passive"))
    )
    (net (code "972") (name "SR44D") (class "Default")
      (node (ref "R362") (pin "2") (pinfunction "2_2") (pintype "passive"))
    )
    (net (code "973") (name "SR44E") (class "Default")
      (node (ref "R363") (pin "2") (pinfunction "2_2") (pintype "passive"))
    )
    (net (code "974") (name "SR44F") (class "Default")
      (node (ref "R364") (pin "2") (pinfunction "2_2") (pintype "passive"))
    )
    (net (code "975") (name "SR44G") (class "Default")
      (node (ref "R365") (pin "2") (pinfunction "2_2") (pintype "passive"))
    )
    (net (code "976") (name "SR44H") (class "Default")
      (node (ref "R366") (pin "2") (pinfunction "2_2") (pintype "passive"))
    )
    (net (code "977") (name "SR45A") (class "Default")
      (node (ref "R367") (pin "2") (pinfunction "2_2") (pintype "passive"))
    )
    (net (code "978") (name "SR45B") (class "Default")
      (node (ref "R368") (pin "2") (pinfunction "2_2") (pintype "passive"))
    )
    (net (code "979") (name "SR45C") (class "Default")
      (node (ref "R369") (pin "2") (pinfunction "2_2") (pintype "passive"))
    )
    (net (code "980") (name "SR45D") (class "Default")
      (node (ref "R370") (pin "2") (pinfunction "2_2") (pintype "passive"))
    )
    (net (code "981") (name "SR45E") (class "Default")
      (node (ref "R371") (pin "2") (pinfunction "2_2") (pintype "passive"))
    )
    (net (code "982") (name "SR45F") (class "Default")
      (node (ref "R372") (pin "2") (pinfunction "2_2") (pintype "passive"))
    )
    (net (code "983") (name "SR45G") (class "Default")
      (node (ref "R373") (pin "2") (pinfunction "2_2") (pintype "passive"))
    )
    (net (code "984") (name "SR45H") (class "Default")
      (node (ref "R374") (pin "2") (pinfunction "2_2") (pintype "passive"))
    )
    (net (code "985") (name "SR46A") (class "Default")
      (node (ref "R376") (pin "1") (pinfunction "1_1") (pintype "passive"))
    )
    (net (code "986") (name "SR46B") (class "Default")
      (node (ref "R377") (pin "1") (pinfunction "1_1") (pintype "passive"))
    )
    (net (code "987") (name "SR46C") (class "Default")
      (node (ref "R378") (pin "1") (pinfunction "1_1") (pintype "passive"))
    )
    (net (code "988") (name "SR46D") (class "Default")
      (node (ref "R379") (pin "1") (pinfunction "1_1") (pintype "passive"))
    )
    (net (code "989") (name "SR46E") (class "Default")
      (node (ref "R380") (pin "1") (pinfunction "1_1") (pintype "passive"))
    )
    (net (code "990") (name "SR46F") (class "Default")
      (node (ref "R381") (pin "1") (pinfunction "1_1") (pintype "passive"))
    )
    (net (code "991") (name "SR46G") (class "Default")
      (node (ref "R382") (pin "1") (pinfunction "1_1") (pintype "passive"))
    )
    (net (code "992") (name "SR46H") (class "Default")
      (node (ref "R383") (pin "1") (pinfunction "1_1") (pintype "passive"))
    )
    (net (code "993") (name "SR47A") (class "Default")
      (node (ref "R384") (pin "1") (pinfunction "1_1") (pintype "passive"))
    )
    (net (code "994") (name "SR47B") (class "Default")
      (node (ref "R385") (pin "1") (pinfunction "1_1") (pintype "passive"))
    )
    (net (code "995") (name "SR47C") (class "Default")
      (node (ref "R386") (pin "1") (pinfunction "1_1") (pintype "passive"))
    )
    (net (code "996") (name "SR47D") (class "Default")
      (node (ref "R387") (pin "1") (pinfunction "1_1") (pintype "passive"))
    )
    (net (code "997") (name "SR47E") (class "Default")
      (node (ref "R388") (pin "1") (pinfunction "1_1") (pintype "passive"))
    )
    (net (code "998") (name "SR47F") (class "Default")
      (node (ref "R389") (pin "1") (pinfunction "1_1") (pintype "passive"))
    )
    (net (code "999") (name "SR47G") (class "Default")
      (node (ref "R390") (pin "1") (pinfunction "1_1") (pintype "passive"))
    )
    (net (code "1000") (name "SR47H") (class "Default")
      (node (ref "R391") (pin "1") (pinfunction "1_1") (pintype "passive"))
    )
    (net (code "1001") (name "SR48A") (class "Default")
      (node (ref "R392") (pin "1") (pinfunction "1_1") (pintype "passive"))
    )
    (net (code "1002") (name "SR48B") (class "Default")
      (node (ref "R393") (pin "1") (pinfunction "1_1") (pintype "passive"))
    )
    (net (code "1003") (name "SR48C") (class "Default")
      (node (ref "R394") (pin "1") (pinfunction "1_1") (pintype "passive"))
    )
    (net (code "1004") (name "SR48D") (class "Default")
      (node (ref "R395") (pin "1") (pinfunction "1_1") (pintype "passive"))
    )
    (net (code "1005") (name "SR48E") (class "Default")
      (node (ref "R396") (pin "1") (pinfunction "1_1") (pintype "passive"))
    )
    (net (code "1006") (name "SR48F") (class "Default")
      (node (ref "R397") (pin "1") (pinfunction "1_1") (pintype "passive"))
    )
    (net (code "1007") (name "SR48G") (class "Default")
      (node (ref "R398") (pin "1") (pinfunction "1_1") (pintype "passive"))
    )
    (net (code "1008") (name "SR48H") (class "Default")
      (node (ref "R399") (pin "1") (pinfunction "1_1") (pintype "passive"))
    )
    (net (code "1009") (name "SR49A") (class "Default")
      (node (ref "R401") (pin "2") (pinfunction "2_2") (pintype "passive"))
    )
    (net (code "1010") (name "SR49B") (class "Default")
      (node (ref "R402") (pin "2") (pinfunction "2_2") (pintype "passive"))
    )
    (net (code "1011") (name "SR49C") (class "Default")
      (node (ref "R403") (pin "2") (pinfunction "2_2") (pintype "passive"))
    )
    (net (code "1012") (name "SR49D") (class "Default")
      (node (ref "R404") (pin "2") (pinfunction "2_2") (pintype "passive"))
    )
    (net (code "1013") (name "SR49E") (class "Default")
      (node (ref "R405") (pin "2") (pinfunction "2_2") (pintype "passive"))
    )
    (net (code "1014") (name "SR49F") (class "Default")
      (node (ref "R406") (pin "2") (pinfunction "2_2") (pintype "passive"))
    )
    (net (code "1015") (name "SR49G") (class "Default")
      (node (ref "R407") (pin "2") (pinfunction "2_2") (pintype "passive"))
    )
    (net (code "1016") (name "SR49H") (class "Default")
      (node (ref "R408") (pin "2") (pinfunction "2_2") (pintype "passive"))
    )
    (net (code "1017") (name "SR50A") (class "Default")
      (node (ref "R409") (pin "2") (pinfunction "2_2") (pintype "passive"))
    )
    (net (code "1018") (name "SR50B") (class "Default")
      (node (ref "R410") (pin "2") (pinfunction "2_2") (pintype "passive"))
    )
    (net (code "1019") (name "SR50C") (class "Default")
      (node (ref "R411") (pin "2") (pinfunction "2_2") (pintype "passive"))
    )
    (net (code "1020") (name "SR50D") (class "Default")
      (node (ref "R412") (pin "2") (pinfunction "2_2") (pintype "passive"))
    )
    (net (code "1021") (name "SR50E") (class "Default")
      (node (ref "R413") (pin "2") (pinfunction "2_2") (pintype "passive"))
    )
    (net (code "1022") (name "SR50F") (class "Default")
      (node (ref "R414") (pin "2") (pinfunction "2_2") (pintype "passive"))
    )
    (net (code "1023") (name "SR50G") (class "Default")
      (node (ref "R415") (pin "2") (pinfunction "2_2") (pintype "passive"))
    )
    (net (code "1024") (name "SR50H") (class "Default")
      (node (ref "R416") (pin "2") (pinfunction "2_2") (pintype "passive"))
    )
    (net (code "1025") (name "SR51A") (class "Default")
      (node (ref "R417") (pin "2") (pinfunction "2_2") (pintype "passive"))
    )
    (net (code "1026") (name "SR51B") (class "Default")
      (node (ref "R418") (pin "2") (pinfunction "2_2") (pintype "passive"))
    )
    (net (code "1027") (name "SR51C") (class "Default")
      (node (ref "R419") (pin "2") (pinfunction "2_2") (pintype "passive"))
    )
    (net (code "1028") (name "SR51D") (class "Default")
      (node (ref "R420") (pin "2") (pinfunction "2_2") (pintype "passive"))
    )
    (net (code "1029") (name "SR51E") (class "Default")
      (node (ref "R421") (pin "2") (pinfunction "2_2") (pintype "passive"))
    )
    (net (code "1030") (name "SR51F") (class "Default")
      (node (ref "R422") (pin "2") (pinfunction "2_2") (pintype "passive"))
    )
    (net (code "1031") (name "SR51G") (class "Default")
      (node (ref "R423") (pin "2") (pinfunction "2_2") (pintype "passive"))
    )
    (net (code "1032") (name "SR51H") (class "Default")
      (node (ref "R424") (pin "2") (pinfunction "2_2") (pintype "passive"))
    )
    (net (code "1033") (name "SR52A") (class "Default")
      (node (ref "R426") (pin "1") (pinfunction "1_1") (pintype "passive"))
    )
    (net (code "1034") (name "SR52B") (class "Default")
      (node (ref "R427") (pin "1") (pinfunction "1_1") (pintype "passive"))
    )
    (net (code "1035") (name "SR52C") (class "Default")
      (node (ref "R428") (pin "1") (pinfunction "1_1") (pintype "passive"))
    )
    (net (code "1036") (name "SR52D") (class "Default")
      (node (ref "R429") (pin "1") (pinfunction "1_1") (pintype "passive"))
    )
    (net (code "1037") (name "SR52E") (class "Default")
      (node (ref "R430") (pin "1") (pinfunction "1_1") (pintype "passive"))
    )
    (net (code "1038") (name "SR52F") (class "Default")
      (node (ref "R431") (pin "1") (pinfunction "1_1") (pintype "passive"))
    )
    (net (code "1039") (name "SR52G") (class "Default")
      (node (ref "R432") (pin "1") (pinfunction "1_1") (pintype "passive"))
    )
    (net (code "1040") (name "SR52H") (class "Default")
      (node (ref "R433") (pin "1") (pinfunction "1_1") (pintype "passive"))
    )
    (net (code "1041") (name "SR53A") (class "Default")
      (node (ref "R434") (pin "1") (pinfunction "1_1") (pintype "passive"))
    )
    (net (code "1042") (name "SR53B") (class "Default")
      (node (ref "R435") (pin "1") (pinfunction "1_1") (pintype "passive"))
    )
    (net (code "1043") (name "SR53C") (class "Default")
      (node (ref "R436") (pin "1") (pinfunction "1_1") (pintype "passive"))
    )
    (net (code "1044") (name "SR53D") (class "Default")
      (node (ref "R437") (pin "1") (pinfunction "1_1") (pintype "passive"))
    )
    (net (code "1045") (name "SR53E") (class "Default")
      (node (ref "R438") (pin "1") (pinfunction "1_1") (pintype "passive"))
    )
    (net (code "1046") (name "SR53F") (class "Default")
      (node (ref "R439") (pin "1") (pinfunction "1_1") (pintype "passive"))
    )
    (net (code "1047") (name "SR53G") (class "Default")
      (node (ref "R440") (pin "1") (pinfunction "1_1") (pintype "passive"))
    )
    (net (code "1048") (name "SR53H") (class "Default")
      (node (ref "R441") (pin "1") (pinfunction "1_1") (pintype "passive"))
    )
    (net (code "1049") (name "SR54A") (class "Default")
      (node (ref "R442") (pin "1") (pinfunction "1_1") (pintype "passive"))
    )
    (net (code "1050") (name "SR54B") (class "Default")
      (node (ref "R443") (pin "1") (pinfunction "1_1") (pintype "passive"))
    )
    (net (code "1051") (name "SR54C") (class "Default")
      (node (ref "R444") (pin "1") (pinfunction "1_1") (pintype "passive"))
    )
    (net (code "1052") (name "SR54D") (class "Default")
      (node (ref "R445") (pin "1") (pinfunction "1_1") (pintype "passive"))
    )
    (net (code "1053") (name "SR54E") (class "Default")
      (node (ref "R446") (pin "1") (pinfunction "1_1") (pintype "passive"))
    )
    (net (code "1054") (name "SR54F") (class "Default")
      (node (ref "R447") (pin "1") (pinfunction "1_1") (pintype "passive"))
    )
    (net (code "1055") (name "SR54G") (class "Default")
      (node (ref "R448") (pin "1") (pinfunction "1_1") (pintype "passive"))
    )
    (net (code "1056") (name "SR54H") (class "Default")
      (node (ref "R449") (pin "1") (pinfunction "1_1") (pintype "passive"))
    )
    (net (code "1057") (name "SR55A") (class "Default")
      (node (ref "R451") (pin "2") (pinfunction "2_2") (pintype "passive"))
    )
    (net (code "1058") (name "SR55B") (class "Default")
      (node (ref "R452") (pin "2") (pinfunction "2_2") (pintype "passive"))
    )
    (net (code "1059") (name "SR55C") (class "Default")
      (node (ref "R453") (pin "2") (pinfunction "2_2") (pintype "passive"))
    )
    (net (code "1060") (name "SR55D") (class "Default")
      (node (ref "R454") (pin "2") (pinfunction "2_2") (pintype "passive"))
    )
    (net (code "1061") (name "SR55E") (class "Default")
      (node (ref "R455") (pin "2") (pinfunction "2_2") (pintype "passive"))
    )
    (net (code "1062") (name "SR55F") (class "Default")
      (node (ref "R456") (pin "2") (pinfunction "2_2") (pintype "passive"))
    )
    (net (code "1063") (name "SR55G") (class "Default")
      (node (ref "R457") (pin "2") (pinfunction "2_2") (pintype "passive"))
    )
    (net (code "1064") (name "SR55H") (class "Default")
      (node (ref "R458") (pin "2") (pinfunction "2_2") (pintype "passive"))
    )
    (net (code "1065") (name "SR56A") (class "Default")
      (node (ref "R459") (pin "2") (pinfunction "2_2") (pintype "passive"))
    )
    (net (code "1066") (name "SR56B") (class "Default")
      (node (ref "R460") (pin "2") (pinfunction "2_2") (pintype "passive"))
    )
    (net (code "1067") (name "SR56C") (class "Default")
      (node (ref "R461") (pin "2") (pinfunction "2_2") (pintype "passive"))
    )
    (net (code "1068") (name "SR56D") (class "Default")
      (node (ref "R462") (pin "2") (pinfunction "2_2") (pintype "passive"))
    )
    (net (code "1069") (name "SR56E") (class "Default")
      (node (ref "R463") (pin "2") (pinfunction "2_2") (pintype "passive"))
    )
    (net (code "1070") (name "SR56F") (class "Default")
      (node (ref "R464") (pin "2") (pinfunction "2_2") (pintype "passive"))
    )
    (net (code "1071") (name "SR56G") (class "Default")
      (node (ref "R465") (pin "2") (pinfunction "2_2") (pintype "passive"))
    )
    (net (code "1072") (name "SR56H") (class "Default")
      (node (ref "R466") (pin "2") (pinfunction "2_2") (pintype "passive"))
    )
    (net (code "1073") (name "SR57A") (class "Default")
      (node (ref "R467") (pin "2") (pinfunction "2_2") (pintype "passive"))
    )
    (net (code "1074") (name "SR57B") (class "Default")
      (node (ref "R468") (pin "2") (pinfunction "2_2") (pintype "passive"))
    )
    (net (code "1075") (name "SR57C") (class "Default")
      (node (ref "R469") (pin "2") (pinfunction "2_2") (pintype "passive"))
    )
    (net (code "1076") (name "SR57D") (class "Default")
      (node (ref "R470") (pin "2") (pinfunction "2_2") (pintype "passive"))
    )
    (net (code "1077") (name "SR57E") (class "Default")
      (node (ref "R471") (pin "2") (pinfunction "2_2") (pintype "passive"))
    )
    (net (code "1078") (name "SR57F") (class "Default")
      (node (ref "R472") (pin "2") (pinfunction "2_2") (pintype "passive"))
    )
    (net (code "1079") (name "SR57G") (class "Default")
      (node (ref "R473") (pin "2") (pinfunction "2_2") (pintype "passive"))
    )
    (net (code "1080") (name "SR57H") (class "Default")
      (node (ref "R474") (pin "2") (pinfunction "2_2") (pintype "passive"))
    )
    (net (code "1081") (name "SR58A") (class "Default")
      (node (ref "R476") (pin "1") (pinfunction "1_1") (pintype "passive"))
    )
    (net (code "1082") (name "SR58B") (class "Default")
      (node (ref "R477") (pin "1") (pinfunction "1_1") (pintype "passive"))
    )
    (net (code "1083") (name "SR58C") (class "Default")
      (node (ref "R478") (pin "1") (pinfunction "1_1") (pintype "passive"))
    )
    (net (code "1084") (name "SR58D") (class "Default")
      (node (ref "R479") (pin "1") (pinfunction "1_1") (pintype "passive"))
    )
    (net (code "1085") (name "SR58E") (class "Default")
      (node (ref "R480") (pin "1") (pinfunction "1_1") (pintype "passive"))
    )
    (net (code "1086") (name "SR58F") (class "Default")
      (node (ref "R481") (pin "1") (pinfunction "1_1") (pintype "passive"))
    )
    (net (code "1087") (name "SR58G") (class "Default")
      (node (ref "R482") (pin "1") (pinfunction "1_1") (pintype "passive"))
    )
    (net (code "1088") (name "SR58H") (class "Default")
      (node (ref "R483") (pin "1") (pinfunction "1_1") (pintype "passive"))
    )
    (net (code "1089") (name "SR59A") (class "Default")
      (node (ref "R484") (pin "1") (pinfunction "1_1") (pintype "passive"))
    )
    (net (code "1090") (name "SR59B") (class "Default")
      (node (ref "R485") (pin "1") (pinfunction "1_1") (pintype "passive"))
    )
    (net (code "1091") (name "SR59C") (class "Default")
      (node (ref "R486") (pin "1") (pinfunction "1_1") (pintype "passive"))
    )
    (net (code "1092") (name "SR59D") (class "Default")
      (node (ref "R487") (pin "1") (pinfunction "1_1") (pintype "passive"))
    )
    (net (code "1093") (name "SR59E") (class "Default")
      (node (ref "R488") (pin "1") (pinfunction "1_1") (pintype "passive"))
    )
    (net (code "1094") (name "SR59F") (class "Default")
      (node (ref "R489") (pin "1") (pinfunction "1_1") (pintype "passive"))
    )
    (net (code "1095") (name "SR59G") (class "Default")
      (node (ref "R490") (pin "1") (pinfunction "1_1") (pintype "passive"))
    )
    (net (code "1096") (name "SR59H") (class "Default")
      (node (ref "R491") (pin "1") (pinfunction "1_1") (pintype "passive"))
    )
    (net (code "1097") (name "SR60A") (class "Default")
      (node (ref "R492") (pin "1") (pinfunction "1_1") (pintype "passive"))
    )
    (net (code "1098") (name "SR60B") (class "Default")
      (node (ref "R493") (pin "1") (pinfunction "1_1") (pintype "passive"))
    )
    (net (code "1099") (name "SR60C") (class "Default")
      (node (ref "R494") (pin "1") (pinfunction "1_1") (pintype "passive"))
    )
    (net (code "1100") (name "SR60D") (class "Default")
      (node (ref "R495") (pin "1") (pinfunction "1_1") (pintype "passive"))
    )
    (net (code "1101") (name "SR60E") (class "Default")
      (node (ref "R496") (pin "1") (pinfunction "1_1") (pintype "passive"))
    )
    (net (code "1102") (name "SR60F") (class "Default")
      (node (ref "R497") (pin "1") (pinfunction "1_1") (pintype "passive"))
    )
    (net (code "1103") (name "SR60G") (class "Default")
      (node (ref "R498") (pin "1") (pinfunction "1_1") (pintype "passive"))
    )
    (net (code "1104") (name "SR60H") (class "Default")
      (node (ref "R499") (pin "1") (pinfunction "1_1") (pintype "passive"))
    )
    (net (code "1105") (name "SR61A") (class "Default")
      (node (ref "R501") (pin "2") (pinfunction "2_2") (pintype "passive"))
    )
    (net (code "1106") (name "SR61B") (class "Default")
      (node (ref "R502") (pin "2") (pinfunction "2_2") (pintype "passive"))
    )
    (net (code "1107") (name "SR61C") (class "Default")
      (node (ref "R503") (pin "2") (pinfunction "2_2") (pintype "passive"))
    )
    (net (code "1108") (name "SR61D") (class "Default")
      (node (ref "R504") (pin "2") (pinfunction "2_2") (pintype "passive"))
    )
    (net (code "1109") (name "SR61E") (class "Default")
      (node (ref "R505") (pin "2") (pinfunction "2_2") (pintype "passive"))
    )
    (net (code "1110") (name "SR61F") (class "Default")
      (node (ref "R506") (pin "2") (pinfunction "2_2") (pintype "passive"))
    )
    (net (code "1111") (name "SR61G") (class "Default")
      (node (ref "R507") (pin "2") (pinfunction "2_2") (pintype "passive"))
    )
    (net (code "1112") (name "SR61H") (class "Default")
      (node (ref "R508") (pin "2") (pinfunction "2_2") (pintype "passive"))
    )
    (net (code "1113") (name "SR62A") (class "Default")
      (node (ref "R509") (pin "2") (pinfunction "2_2") (pintype "passive"))
    )
    (net (code "1114") (name "SR62B") (class "Default")
      (node (ref "R510") (pin "2") (pinfunction "2_2") (pintype "passive"))
    )
    (net (code "1115") (name "SR62C") (class "Default")
      (node (ref "R511") (pin "2") (pinfunction "2_2") (pintype "passive"))
    )
    (net (code "1116") (name "SR62D") (class "Default")
      (node (ref "R512") (pin "2") (pinfunction "2_2") (pintype "passive"))
    )
    (net (code "1117") (name "SR62E") (class "Default")
      (node (ref "R513") (pin "2") (pinfunction "2_2") (pintype "passive"))
    )
    (net (code "1118") (name "SR62F") (class "Default")
      (node (ref "R514") (pin "2") (pinfunction "2_2") (pintype "passive"))
    )
    (net (code "1119") (name "SR62G") (class "Default")
      (node (ref "R515") (pin "2") (pinfunction "2_2") (pintype "passive"))
    )
    (net (code "1120") (name "SR62H") (class "Default")
      (node (ref "R516") (pin "2") (pinfunction "2_2") (pintype "passive"))
    )
    (net (code "1121") (name "SR63A") (class "Default")
      (node (ref "R517") (pin "2") (pinfunction "2_2") (pintype "passive"))
    )
    (net (code "1122") (name "SR63B") (class "Default")
      (node (ref "R518") (pin "2") (pinfunction "2_2") (pintype "passive"))
    )
    (net (code "1123") (name "SR63C") (class "Default")
      (node (ref "R519") (pin "2") (pinfunction "2_2") (pintype "passive"))
    )
    (net (code "1124") (name "SR63D") (class "Default")
      (node (ref "R520") (pin "2") (pinfunction "2_2") (pintype "passive"))
    )
    (net (code "1125") (name "SR63E") (class "Default")
      (node (ref "R521") (pin "2") (pinfunction "2_2") (pintype "passive"))
    )
    (net (code "1126") (name "SR63F") (class "Default")
      (node (ref "R522") (pin "2") (pinfunction "2_2") (pintype "passive"))
    )
    (net (code "1127") (name "SR63G") (class "Default")
      (node (ref "R523") (pin "2") (pinfunction "2_2") (pintype "passive"))
    )
    (net (code "1128") (name "SR63H") (class "Default")
      (node (ref "R524") (pin "2") (pinfunction "2_2") (pintype "passive"))
    )
    (net (code "1129") (name "SR64A") (class "Default")
      (node (ref "R526") (pin "1") (pinfunction "1_1") (pintype "passive"))
    )
    (net (code "1130") (name "SR64B") (class "Default")
      (node (ref "R527") (pin "1") (pinfunction "1_1") (pintype "passive"))
    )
    (net (code "1131") (name "SR64C") (class "Default")
      (node (ref "R528") (pin "1") (pinfunction "1_1") (pintype "passive"))
    )
    (net (code "1132") (name "SR64D") (class "Default")
      (node (ref "R529") (pin "1") (pinfunction "1_1") (pintype "passive"))
    )
    (net (code "1133") (name "SR64E") (class "Default")
      (node (ref "R530") (pin "1") (pinfunction "1_1") (pintype "passive"))
    )
    (net (code "1134") (name "SR64F") (class "Default")
      (node (ref "R531") (pin "1") (pinfunction "1_1") (pintype "passive"))
    )
    (net (code "1135") (name "SR64G") (class "Default")
      (node (ref "R532") (pin "1") (pinfunction "1_1") (pintype "passive"))
    )
    (net (code "1136") (name "SR64H") (class "Default")
      (node (ref "R533") (pin "1") (pinfunction "1_1") (pintype "passive"))
    )
    (net (code "1137") (name "SR65A") (class "Default")
      (node (ref "R534") (pin "1") (pinfunction "1_1") (pintype "passive"))
    )
    (net (code "1138") (name "SR65B") (class "Default")
      (node (ref "R535") (pin "1") (pinfunction "1_1") (pintype "passive"))
    )
    (net (code "1139") (name "SR65C") (class "Default")
      (node (ref "R536") (pin "1") (pinfunction "1_1") (pintype "passive"))
    )
    (net (code "1140") (name "SR65D") (class "Default")
      (node (ref "R537") (pin "1") (pinfunction "1_1") (pintype "passive"))
    )
    (net (code "1141") (name "SR65E") (class "Default")
      (node (ref "R538") (pin "1") (pinfunction "1_1") (pintype "passive"))
    )
    (net (code "1142") (name "SR65F") (class "Default")
      (node (ref "R539") (pin "1") (pinfunction "1_1") (pintype "passive"))
    )
    (net (code "1143") (name "SR65G") (class "Default")
      (node (ref "R540") (pin "1") (pinfunction "1_1") (pintype "passive"))
    )
    (net (code "1144") (name "SR65H") (class "Default")
      (node (ref "R541") (pin "1") (pinfunction "1_1") (pintype "passive"))
    )
    (net (code "1145") (name "SR66A") (class "Default")
      (node (ref "R542") (pin "1") (pinfunction "1_1") (pintype "passive"))
    )
    (net (code "1146") (name "SR66B") (class "Default")
      (node (ref "R543") (pin "1") (pinfunction "1_1") (pintype "passive"))
    )
    (net (code "1147") (name "SR66C") (class "Default")
      (node (ref "R544") (pin "1") (pinfunction "1_1") (pintype "passive"))
    )
    (net (code "1148") (name "SR66D") (class "Default")
      (node (ref "R545") (pin "1") (pinfunction "1_1") (pintype "passive"))
    )
    (net (code "1149") (name "SR66E") (class "Default")
      (node (ref "R546") (pin "1") (pinfunction "1_1") (pintype "passive"))
    )
    (net (code "1150") (name "SR66F") (class "Default")
      (node (ref "R547") (pin "1") (pinfunction "1_1") (pintype "passive"))
    )
    (net (code "1151") (name "SR66G") (class "Default")
      (node (ref "R548") (pin "1") (pinfunction "1_1") (pintype "passive"))
    )
    (net (code "1152") (name "SR66H") (class "Default")
      (node (ref "R549") (pin "1") (pinfunction "1_1") (pintype "passive"))
    )
    (net (code "1153") (name "SR67A") (class "Default")
      (node (ref "R551") (pin "2") (pinfunction "2_2") (pintype "passive"))
    )
    (net (code "1154") (name "SR67B") (class "Default")
      (node (ref "R552") (pin "2") (pinfunction "2_2") (pintype "passive"))
    )
    (net (code "1155") (name "SR67C") (class "Default")
      (node (ref "R553") (pin "2") (pinfunction "2_2") (pintype "passive"))
    )
    (net (code "1156") (name "SR67D") (class "Default")
      (node (ref "R554") (pin "2") (pinfunction "2_2") (pintype "passive"))
    )
    (net (code "1157") (name "SR67E") (class "Default")
      (node (ref "R555") (pin "2") (pinfunction "2_2") (pintype "passive"))
    )
    (net (code "1158") (name "SR67F") (class "Default")
      (node (ref "R556") (pin "2") (pinfunction "2_2") (pintype "passive"))
    )
    (net (code "1159") (name "SR67G") (class "Default")
      (node (ref "R557") (pin "2") (pinfunction "2_2") (pintype "passive"))
    )
    (net (code "1160") (name "SR67H") (class "Default")
      (node (ref "R558") (pin "2") (pinfunction "2_2") (pintype "passive"))
    )
    (net (code "1161") (name "SR68A") (class "Default")
      (node (ref "R559") (pin "2") (pinfunction "2_2") (pintype "passive"))
    )
    (net (code "1162") (name "SR68B") (class "Default")
      (node (ref "R560") (pin "2") (pinfunction "2_2") (pintype "passive"))
    )
    (net (code "1163") (name "SR68C") (class "Default")
      (node (ref "R561") (pin "2") (pinfunction "2_2") (pintype "passive"))
    )
    (net (code "1164") (name "SR68D") (class "Default")
      (node (ref "R562") (pin "2") (pinfunction "2_2") (pintype "passive"))
    )
    (net (code "1165") (name "SR68E") (class "Default")
      (node (ref "R563") (pin "2") (pinfunction "2_2") (pintype "passive"))
    )
    (net (code "1166") (name "SR68F") (class "Default")
      (node (ref "R564") (pin "2") (pinfunction "2_2") (pintype "passive"))
    )
    (net (code "1167") (name "SR68G") (class "Default")
      (node (ref "R565") (pin "2") (pinfunction "2_2") (pintype "passive"))
    )
    (net (code "1168") (name "SR68H") (class "Default")
      (node (ref "R566") (pin "2") (pinfunction "2_2") (pintype "passive"))
    )
    (net (code "1169") (name "SR69A") (class "Default")
      (node (ref "R567") (pin "2") (pinfunction "2_2") (pintype "passive"))
    )
    (net (code "1170") (name "SR69B") (class "Default")
      (node (ref "R568") (pin "2") (pinfunction "2_2") (pintype "passive"))
    )
    (net (code "1171") (name "SR69C") (class "Default")
      (node (ref "R569") (pin "2") (pinfunction "2_2") (pintype "passive"))
    )
    (net (code "1172") (name "SR69D") (class "Default")
      (node (ref "R570") (pin "2") (pinfunction "2_2") (pintype "passive"))
    )
    (net (code "1173") (name "SR69E") (class "Default")
      (node (ref "R571") (pin "2") (pinfunction "2_2") (pintype "passive"))
    )
    (net (code "1174") (name "SR69F") (class "Default")
      (node (ref "R572") (pin "2") (pinfunction "2_2") (pintype "passive"))
    )
    (net (code "1175") (name "SR69G") (class "Default")
      (node (ref "R573") (pin "2") (pinfunction "2_2") (pintype "passive"))
    )
    (net (code "1176") (name "SR69H") (class "Default")
      (node (ref "R574") (pin "2") (pinfunction "2_2") (pintype "passive"))
    )
    (net (code "1177") (name "SR70A") (class "Default")
      (node (ref "R576") (pin "1") (pinfunction "1_1") (pintype "passive"))
    )
    (net (code "1178") (name "SR70B") (class "Default")
      (node (ref "R577") (pin "1") (pinfunction "1_1") (pintype "passive"))
    )
    (net (code "1179") (name "SR70C") (class "Default")
      (node (ref "R578") (pin "1") (pinfunction "1_1") (pintype "passive"))
    )
    (net (code "1180") (name "SR70D") (class "Default")
      (node (ref "R579") (pin "1") (pinfunction "1_1") (pintype "passive"))
    )
    (net (code "1181") (name "SR70E") (class "Default")
      (node (ref "R580") (pin "1") (pinfunction "1_1") (pintype "passive"))
    )
    (net (code "1182") (name "SR70F") (class "Default")
      (node (ref "R581") (pin "1") (pinfunction "1_1") (pintype "passive"))
    )
    (net (code "1183") (name "SR70G") (class "Default")
      (node (ref "R582") (pin "1") (pinfunction "1_1") (pintype "passive"))
    )
    (net (code "1184") (name "SR70H") (class "Default")
      (node (ref "R583") (pin "1") (pinfunction "1_1") (pintype "passive"))
    )
    (net (code "1185") (name "SR71A") (class "Default")
      (node (ref "R584") (pin "1") (pinfunction "1_1") (pintype "passive"))
    )
    (net (code "1186") (name "SR71B") (class "Default")
      (node (ref "R585") (pin "1") (pinfunction "1_1") (pintype "passive"))
    )
    (net (code "1187") (name "SR71C") (class "Default")
      (node (ref "R586") (pin "1") (pinfunction "1_1") (pintype "passive"))
    )
    (net (code "1188") (name "SR71D") (class "Default")
      (node (ref "R587") (pin "1") (pinfunction "1_1") (pintype "passive"))
    )
    (net (code "1189") (name "SR71E") (class "Default")
      (node (ref "R588") (pin "1") (pinfunction "1_1") (pintype "passive"))
    )
    (net (code "1190") (name "SR71F") (class "Default")
      (node (ref "R589") (pin "1") (pinfunction "1_1") (pintype "passive"))
    )
    (net (code "1191") (name "SR71G") (class "Default")
      (node (ref "R590") (pin "1") (pinfunction "1_1") (pintype "passive"))
    )
    (net (code "1192") (name "SR71H") (class "Default")
      (node (ref "R591") (pin "1") (pinfunction "1_1") (pintype "passive"))
    )
    (net (code "1193") (name "SR72A") (class "Default")
      (node (ref "R592") (pin "1") (pinfunction "1_1") (pintype "passive"))
    )
    (net (code "1194") (name "SR72B") (class "Default")
      (node (ref "R593") (pin "1") (pinfunction "1_1") (pintype "passive"))
    )
    (net (code "1195") (name "SR72C") (class "Default")
      (node (ref "R594") (pin "1") (pinfunction "1_1") (pintype "passive"))
    )
    (net (code "1196") (name "SR72D") (class "Default")
      (node (ref "R595") (pin "1") (pinfunction "1_1") (pintype "passive"))
    )
    (net (code "1197") (name "SR72E") (class "Default")
      (node (ref "R596") (pin "1") (pinfunction "1_1") (pintype "passive"))
    )
    (net (code "1198") (name "SR72F") (class "Default")
      (node (ref "R597") (pin "1") (pinfunction "1_1") (pintype "passive"))
    )
    (net (code "1199") (name "SR72G") (class "Default")
      (node (ref "R598") (pin "1") (pinfunction "1_1") (pintype "passive"))
    )
    (net (code "1200") (name "SR72H") (class "Default")
      (node (ref "R599") (pin "1") (pinfunction "1_1") (pintype "passive"))
    )
    (net (code "1201") (name "SR73A") (class "Default")
      (node (ref "R601") (pin "2") (pinfunction "2_2") (pintype "passive"))
    )
    (net (code "1202") (name "SR73B") (class "Default")
      (node (ref "R602") (pin "2") (pinfunction "2_2") (pintype "passive"))
    )
    (net (code "1203") (name "SR73C") (class "Default")
      (node (ref "R603") (pin "2") (pinfunction "2_2") (pintype "passive"))
    )
    (net (code "1204") (name "SR73D") (class "Default")
      (node (ref "R604") (pin "2") (pinfunction "2_2") (pintype "passive"))
    )
    (net (code "1205") (name "SR73E") (class "Default")
      (node (ref "R605") (pin "2") (pinfunction "2_2") (pintype "passive"))
    )
    (net (code "1206") (name "SR73F") (class "Default")
      (node (ref "R606") (pin "2") (pinfunction "2_2") (pintype "passive"))
    )
    (net (code "1207") (name "SR73G") (class "Default")
      (node (ref "R607") (pin "2") (pinfunction "2_2") (pintype "passive"))
    )
    (net (code "1208") (name "SR73H") (class "Default")
      (node (ref "R608") (pin "2") (pinfunction "2_2") (pintype "passive"))
    )
    (net (code "1209") (name "SR74A") (class "Default")
      (node (ref "R609") (pin "2") (pinfunction "2_2") (pintype "passive"))
    )
    (net (code "1210") (name "SR74B") (class "Default")
      (node (ref "R610") (pin "2") (pinfunction "2_2") (pintype "passive"))
    )
    (net (code "1211") (name "SR74C") (class "Default")
      (node (ref "R611") (pin "2") (pinfunction "2_2") (pintype "passive"))
    )
    (net (code "1212") (name "SR74D") (class "Default")
      (node (ref "R612") (pin "2") (pinfunction "2_2") (pintype "passive"))
    )
    (net (code "1213") (name "SR74E") (class "Default")
      (node (ref "R613") (pin "2") (pinfunction "2_2") (pintype "passive"))
    )
    (net (code "1214") (name "SR74F") (class "Default")
      (node (ref "R614") (pin "2") (pinfunction "2_2") (pintype "passive"))
    )
    (net (code "1215") (name "SR74G") (class "Default")
      (node (ref "R615") (pin "2") (pinfunction "2_2") (pintype "passive"))
    )
    (net (code "1216") (name "SR74H") (class "Default")
      (node (ref "R616") (pin "2") (pinfunction "2_2") (pintype "passive"))
    )
    (net (code "1217") (name "SR75A") (class "Default")
      (node (ref "R617") (pin "2") (pinfunction "2_2") (pintype "passive"))
    )
    (net (code "1218") (name "SR75B") (class "Default")
      (node (ref "R618") (pin "2") (pinfunction "2_2") (pintype "passive"))
    )
    (net (code "1219") (name "SR75C") (class "Default")
      (node (ref "R619") (pin "2") (pinfunction "2_2") (pintype "passive"))
    )
    (net (code "1220") (name "SR75D") (class "Default")
      (node (ref "R620") (pin "2") (pinfunction "2_2") (pintype "passive"))
    )
    (net (code "1221") (name "SR75E") (class "Default")
      (node (ref "R621") (pin "2") (pinfunction "2_2") (pintype "passive"))
    )
    (net (code "1222") (name "SR75F") (class "Default")
      (node (ref "R622") (pin "2") (pinfunction "2_2") (pintype "passive"))
    )
    (net (code "1223") (name "SR75G") (class "Default")
      (node (ref "R623") (pin "2") (pinfunction "2_2") (pintype "passive"))
    )
    (net (code "1224") (name "SR75H") (class "Default")
      (node (ref "R624") (pin "2") (pinfunction "2_2") (pintype "passive"))
    )
    (net (code "1225") (name "SR76A") (class "Default")
      (node (ref "R25") (pin "2") (pinfunction "2_2") (pintype "passive"))
    )
    (net (code "1226") (name "SR76B") (class "Default")
      (node (ref "R50") (pin "1") (pinfunction "1_1") (pintype "passive"))
    )
    (net (code "1227") (name "SR76C") (class "Default")
      (node (ref "R75") (pin "2") (pinfunction "2_2") (pintype "passive"))
    )
    (net (code "1228") (name "SR76D") (class "Default")
      (node (ref "R100") (pin "1") (pinfunction "1_1") (pintype "passive"))
    )
    (net (code "1229") (name "SR76E") (class "Default")
      (node (ref "R125") (pin "2") (pinfunction "2_2") (pintype "passive"))
    )
    (net (code "1230") (name "SR76F") (class "Default")
      (node (ref "R150") (pin "1") (pinfunction "1_1") (pintype "passive"))
    )
    (net (code "1231") (name "SR76G") (class "Default")
      (node (ref "R175") (pin "2") (pinfunction "2_2") (pintype "passive"))
    )
    (net (code "1232") (name "SR76H") (class "Default")
      (node (ref "R200") (pin "1") (pinfunction "1_1") (pintype "passive"))
    )
    (net (code "1233") (name "SR77A") (class "Default")
      (node (ref "R225") (pin "2") (pinfunction "2_2") (pintype "passive"))
    )
    (net (code "1234") (name "SR77B") (class "Default")
      (node (ref "R250") (pin "1") (pinfunction "1_1") (pintype "passive"))
    )
    (net (code "1235") (name "SR77C") (class "Default")
      (node (ref "R275") (pin "2") (pinfunction "2_2") (pintype "passive"))
    )
    (net (code "1236") (name "SR77D") (class "Default")
      (node (ref "R300") (pin "1") (pinfunction "1_1") (pintype "passive"))
    )
    (net (code "1237") (name "SR77E") (class "Default")
      (node (ref "R325") (pin "2") (pinfunction "2_2") (pintype "passive"))
    )
    (net (code "1238") (name "SR77F") (class "Default")
      (node (ref "R350") (pin "1") (pinfunction "1_1") (pintype "passive"))
    )
    (net (code "1239") (name "SR77G") (class "Default")
      (node (ref "R375") (pin "2") (pinfunction "2_2") (pintype "passive"))
    )
    (net (code "1240") (name "SR77H") (class "Default")
      (node (ref "R400") (pin "1") (pinfunction "1_1") (pintype "passive"))
    )
    (net (code "1241") (name "SR78A") (class "Default")
      (node (ref "R425") (pin "2") (pinfunction "2_2") (pintype "passive"))
    )
    (net (code "1242") (name "SR78B") (class "Default")
      (node (ref "R450") (pin "1") (pinfunction "1_1") (pintype "passive"))
    )
    (net (code "1243") (name "SR78C") (class "Default")
      (node (ref "R475") (pin "2") (pinfunction "2_2") (pintype "passive"))
    )
    (net (code "1244") (name "SR78D") (class "Default")
      (node (ref "R500") (pin "1") (pinfunction "1_1") (pintype "passive"))
    )
    (net (code "1245") (name "SR78E") (class "Default")
      (node (ref "R525") (pin "2") (pinfunction "2_2") (pintype "passive"))
    )
    (net (code "1246") (name "SR78F") (class "Default")
      (node (ref "R550") (pin "1") (pinfunction "1_1") (pintype "passive"))
    )
    (net (code "1247") (name "SR78G") (class "Default")
      (node (ref "R575") (pin "2") (pinfunction "2_2") (pintype "passive"))
    )
    (net (code "1248") (name "SR78H") (class "Default")
      (node (ref "R600") (pin "1") (pinfunction "1_1") (pintype "passive"))
    )
    (net (code "1249") (name "unconnected-(Header1-Pad2)") (class "Default")
      (node (ref "Header1") (pin "2") (pintype "input+no_connect"))
    )
    (net (code "1250") (name "unconnected-(Header2-Pad4)") (class "Default")
      (node (ref "Header2") (pin "4") (pintype "input+no_connect"))
    )
    (net (code "1251") (name "unconnected-(Header3-Pad2)") (class "Default")
      (node (ref "Header3") (pin "2") (pintype "input+no_connect"))
    )
    (net (code "1252") (name "unconnected-(Header3-Pad3)") (class "Default")
      (node (ref "Header3") (pin "3") (pintype "input+no_connect"))
    )
    (net (code "1253") (name "unconnected-(Header3-Pad4)") (class "Default")
      (node (ref "Header3") (pin "4") (pintype "input+no_connect"))
    )
    (net (code "1254") (name "unconnected-(Header4-Pad6)") (class "Default")
      (node (ref "Header4") (pin "6") (pintype "input+no_connect"))
    )
    (net (code "1255") (name "unconnected-(Header4-Pad7)") (class "Default")
      (node (ref "Header4") (pin "7") (pintype "input+no_connect"))
    )
    (net (code "1256") (name "unconnected-(Header4-Pad8)") (class "Default")
      (node (ref "Header4") (pin "8") (pintype "input+no_connect"))
    )
    (net (code "1257") (name "unconnected-(Header7-Pad20)") (class "Default")
      (node (ref "Header7") (pin "20") (pintype "input+no_connect"))
    )
    (net (code "1258") (name "unconnected-(Header7-Pad21)") (class "Default")
      (node (ref "Header7") (pin "21") (pintype "input+no_connect"))
    )
    (net (code "1259") (name "unconnected-(Header7-Pad22)") (class "Default")
      (node (ref "Header7") (pin "22") (pintype "input+no_connect"))
    )
    (net (code "1260") (name "unconnected-(Header8-Pad15)") (class "Default")
      (node (ref "Header8") (pin "15") (pintype "input+no_connect"))
    )
    (net (code "1261") (name "unconnected-(Header8-Pad16)") (class "Default")
      (node (ref "Header8") (pin "16") (pintype "input+no_connect"))
    )
    (net (code "1262") (name "unconnected-(Header8-Pad17)") (class "Default")
      (node (ref "Header8") (pin "17") (pintype "input+no_connect"))
    )
    (net (code "1263") (name "unconnected-(Header9-Pad20)") (class "Default")
      (node (ref "Header9") (pin "20") (pintype "input+no_connect"))
    )
    (net (code "1264") (name "unconnected-(Header9-Pad21)") (class "Default")
      (node (ref "Header9") (pin "21") (pintype "input+no_connect"))
    )
    (net (code "1265") (name "unconnected-(Header9-Pad22)") (class "Default")
      (node (ref "Header9") (pin "22") (pintype "input+no_connect"))
    )
    (net (code "1266") (name "unconnected-(Header10-Pad15)") (class "Default")
      (node (ref "Header10") (pin "15") (pintype "input+no_connect"))
    )
    (net (code "1267") (name "unconnected-(Header10-Pad16)") (class "Default")
      (node (ref "Header10") (pin "16") (pintype "input+no_connect"))
    )
    (net (code "1268") (name "unconnected-(Header10-Pad17)") (class "Default")
      (node (ref "Header10") (pin "17") (pintype "input+no_connect"))
    )
    (net (code "1269") (name "unconnected-(Header23-Pad20)") (class "Default")
      (node (ref "Header23") (pin "20") (pintype "input+no_connect"))
    )
    (net (code "1270") (name "unconnected-(Header23-Pad21)") (class "Default")
      (node (ref "Header23") (pin "21") (pintype "input+no_connect"))
    )
    (net (code "1271") (name "unconnected-(Header23-Pad22)") (class "Default")
      (node (ref "Header23") (pin "22") (pintype "input+no_connect"))
    )
    (net (code "1272") (name "unconnected-(Header24-Pad15)") (class "Default")
      (node (ref "Header24") (pin "15") (pintype "input+no_connect"))
    )
    (net (code "1273") (name "unconnected-(Header24-Pad16)") (class "Default")
      (node (ref "Header24") (pin "16") (pintype "input+no_connect"))
    )
    (net (code "1274") (name "unconnected-(Header24-Pad17)") (class "Default")
      (node (ref "Header24") (pin "17") (pintype "input+no_connect"))
    )
    (net (code "1275") (name "unconnected-(Header25-Pad20)") (class "Default")
      (node (ref "Header25") (pin "20") (pintype "input+no_connect"))
    )
    (net (code "1276") (name "unconnected-(Header25-Pad21)") (class "Default")
      (node (ref "Header25") (pin "21") (pintype "input+no_connect"))
    )
    (net (code "1277") (name "unconnected-(Header25-Pad22)") (class "Default")
      (node (ref "Header25") (pin "22") (pintype "input+no_connect"))
    )
    (net (code "1278") (name "unconnected-(Header26-Pad15)") (class "Default")
      (node (ref "Header26") (pin "15") (pintype "input+no_connect"))
    )
    (net (code "1279") (name "unconnected-(Header26-Pad16)") (class "Default")
      (node (ref "Header26") (pin "16") (pintype "input+no_connect"))
    )
    (net (code "1280") (name "unconnected-(Header26-Pad17)") (class "Default")
      (node (ref "Header26") (pin "17") (pintype "input+no_connect"))
    )
    (net (code "1281") (name "unconnected-(Header29-Pad2)") (class "Default")
      (node (ref "Header29") (pin "2") (pintype "input+no_connect"))
    )
    (net (code "1282") (name "unconnected-(Header29-Pad3)") (class "Default")
      (node (ref "Header29") (pin "3") (pintype "input+no_connect"))
    )
    (net (code "1283") (name "unconnected-(Header29-Pad4)") (class "Default")
      (node (ref "Header29") (pin "4") (pintype "input+no_connect"))
    )
    (net (code "1284") (name "unconnected-(Header30-Pad6)") (class "Default")
      (node (ref "Header30") (pin "6") (pintype "input+no_connect"))
    )
    (net (code "1285") (name "unconnected-(Header30-Pad7)") (class "Default")
      (node (ref "Header30") (pin "7") (pintype "input+no_connect"))
    )
    (net (code "1286") (name "unconnected-(Header30-Pad8)") (class "Default")
      (node (ref "Header30") (pin "8") (pintype "input+no_connect"))
    )
    (net (code "1287") (name "unconnected-(Header31-Pad2)") (class "Default")
      (node (ref "Header31") (pin "2") (pintype "input+no_connect"))
    )
    (net (code "1288") (name "unconnected-(Header32-Pad4)") (class "Default")
      (node (ref "Header32") (pin "4") (pintype "input+no_connect"))
    )
  )
)
